# BEP33_6panel_DESKTOP-T8KKGMJ_Mai-19-0145.net
KiCad netlist of a schematic drawn in EAGLE
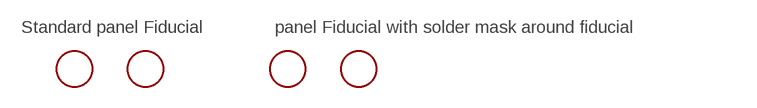
[diagram p0: schematic, sheet 1]
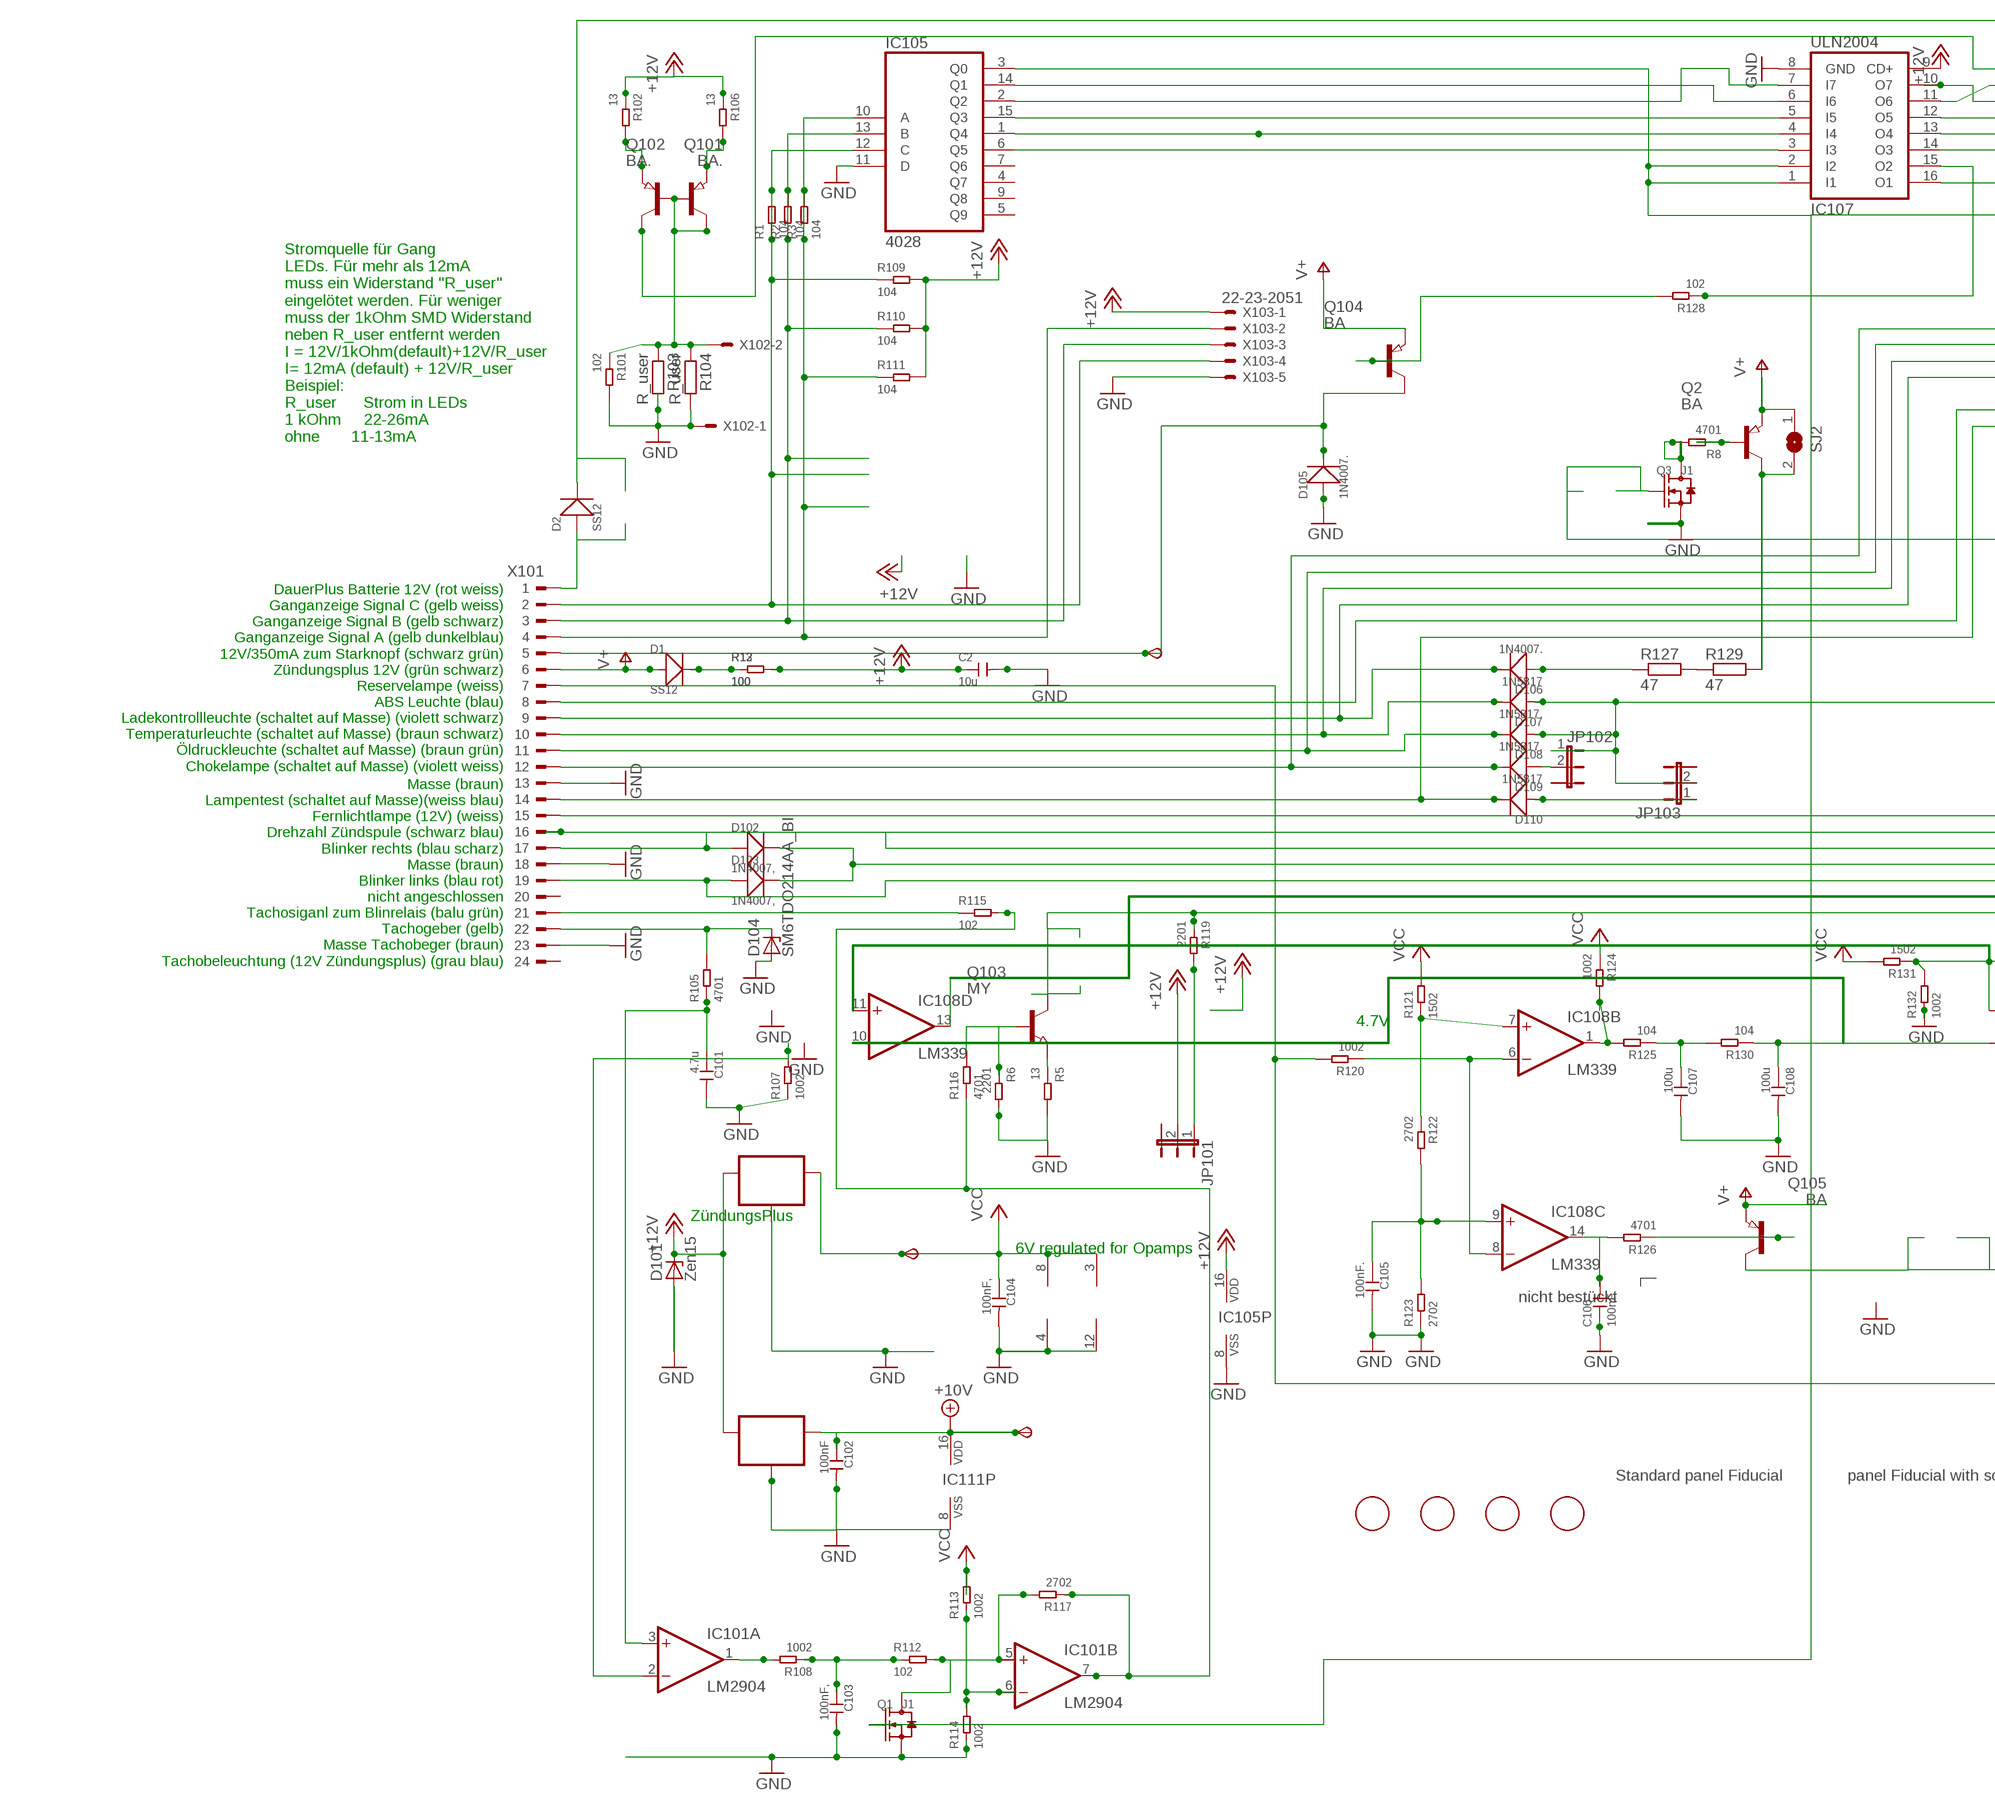
[diagram p1: schematic, sheet 2, part 1 of 2]
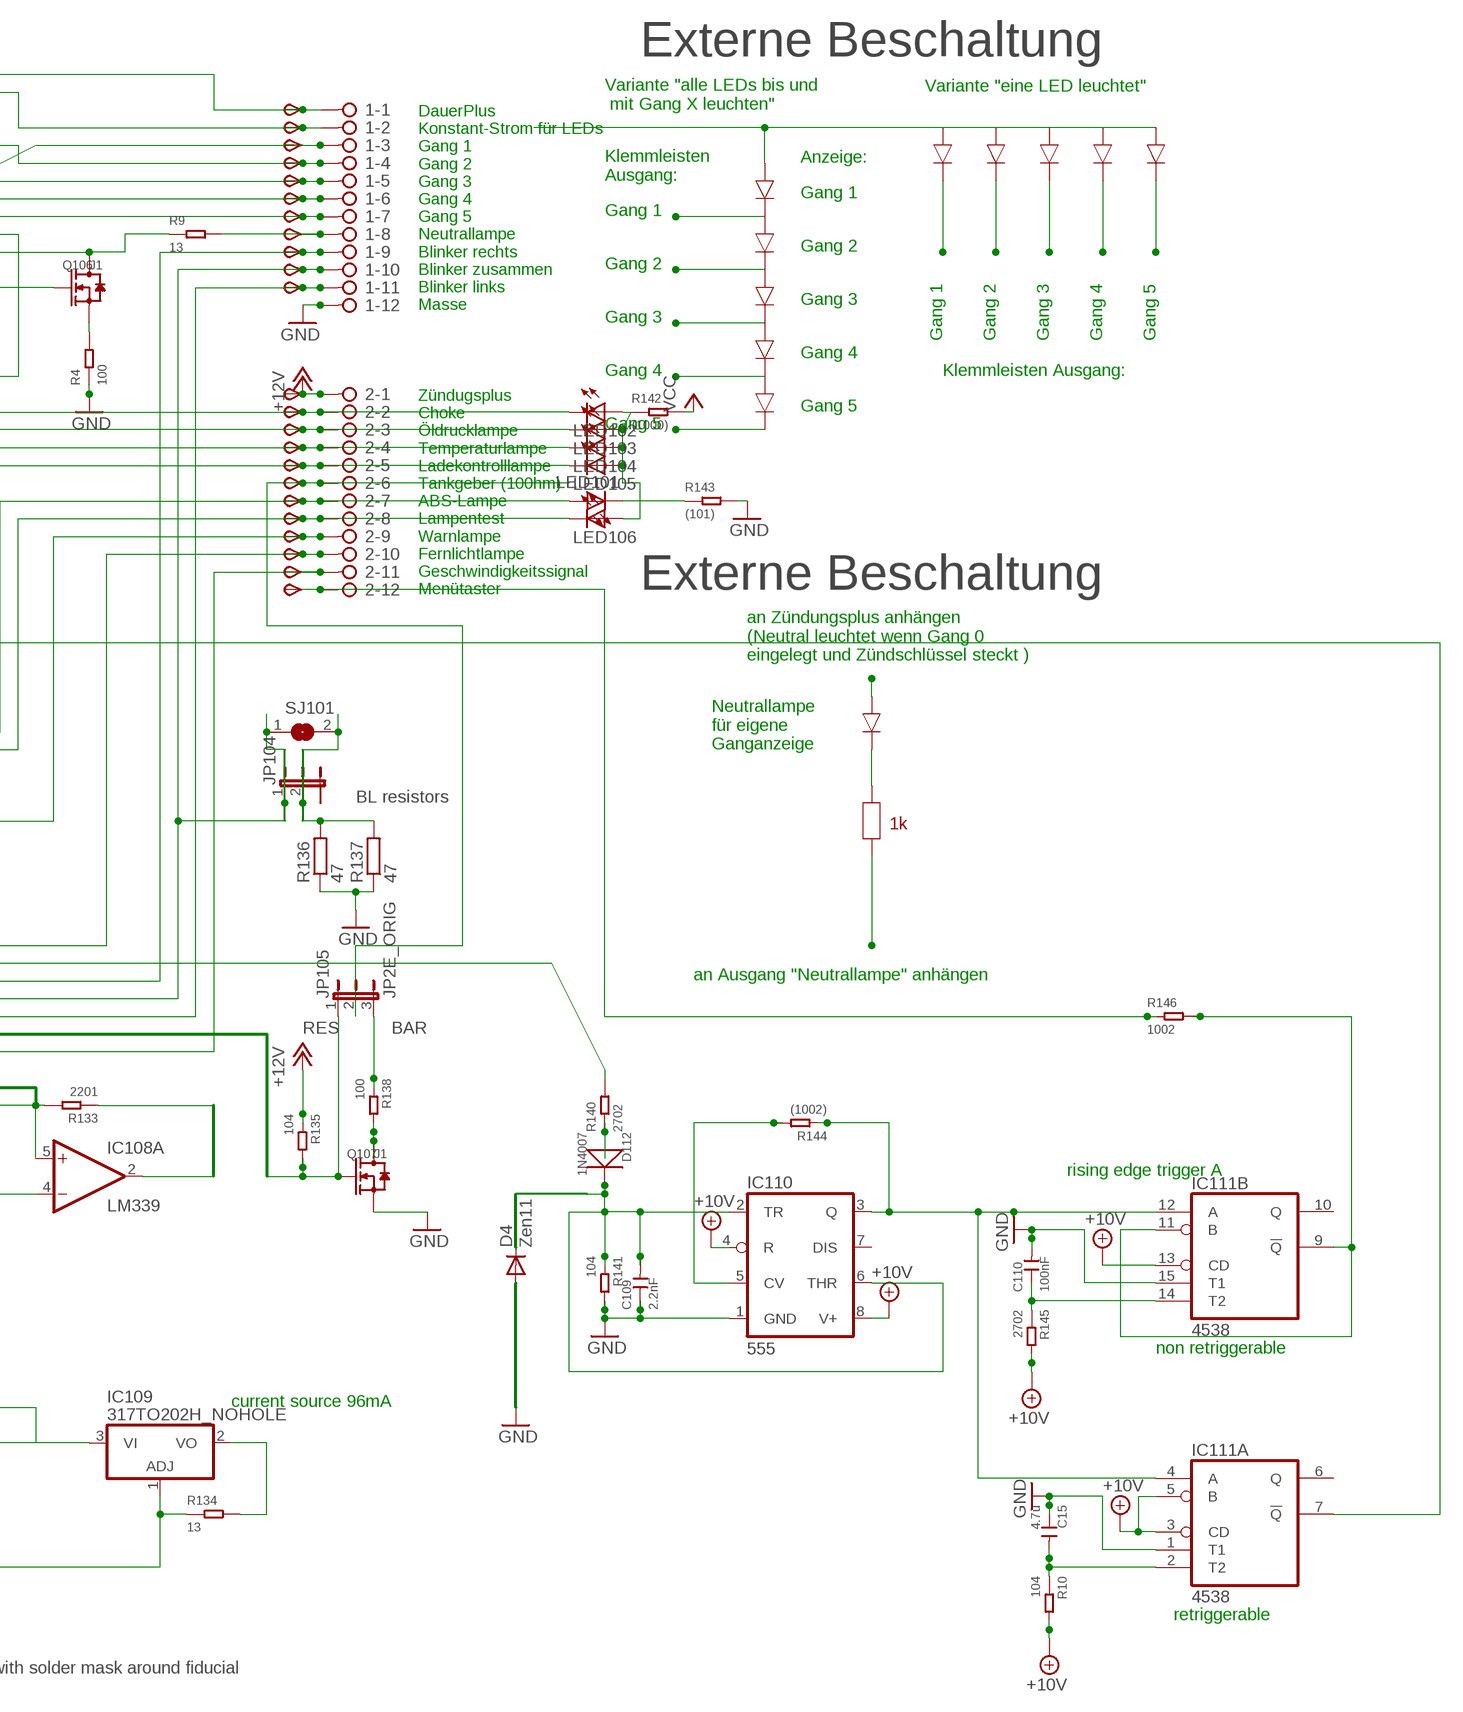
[diagram p2: schematic, sheet 2, part 2 of 2]
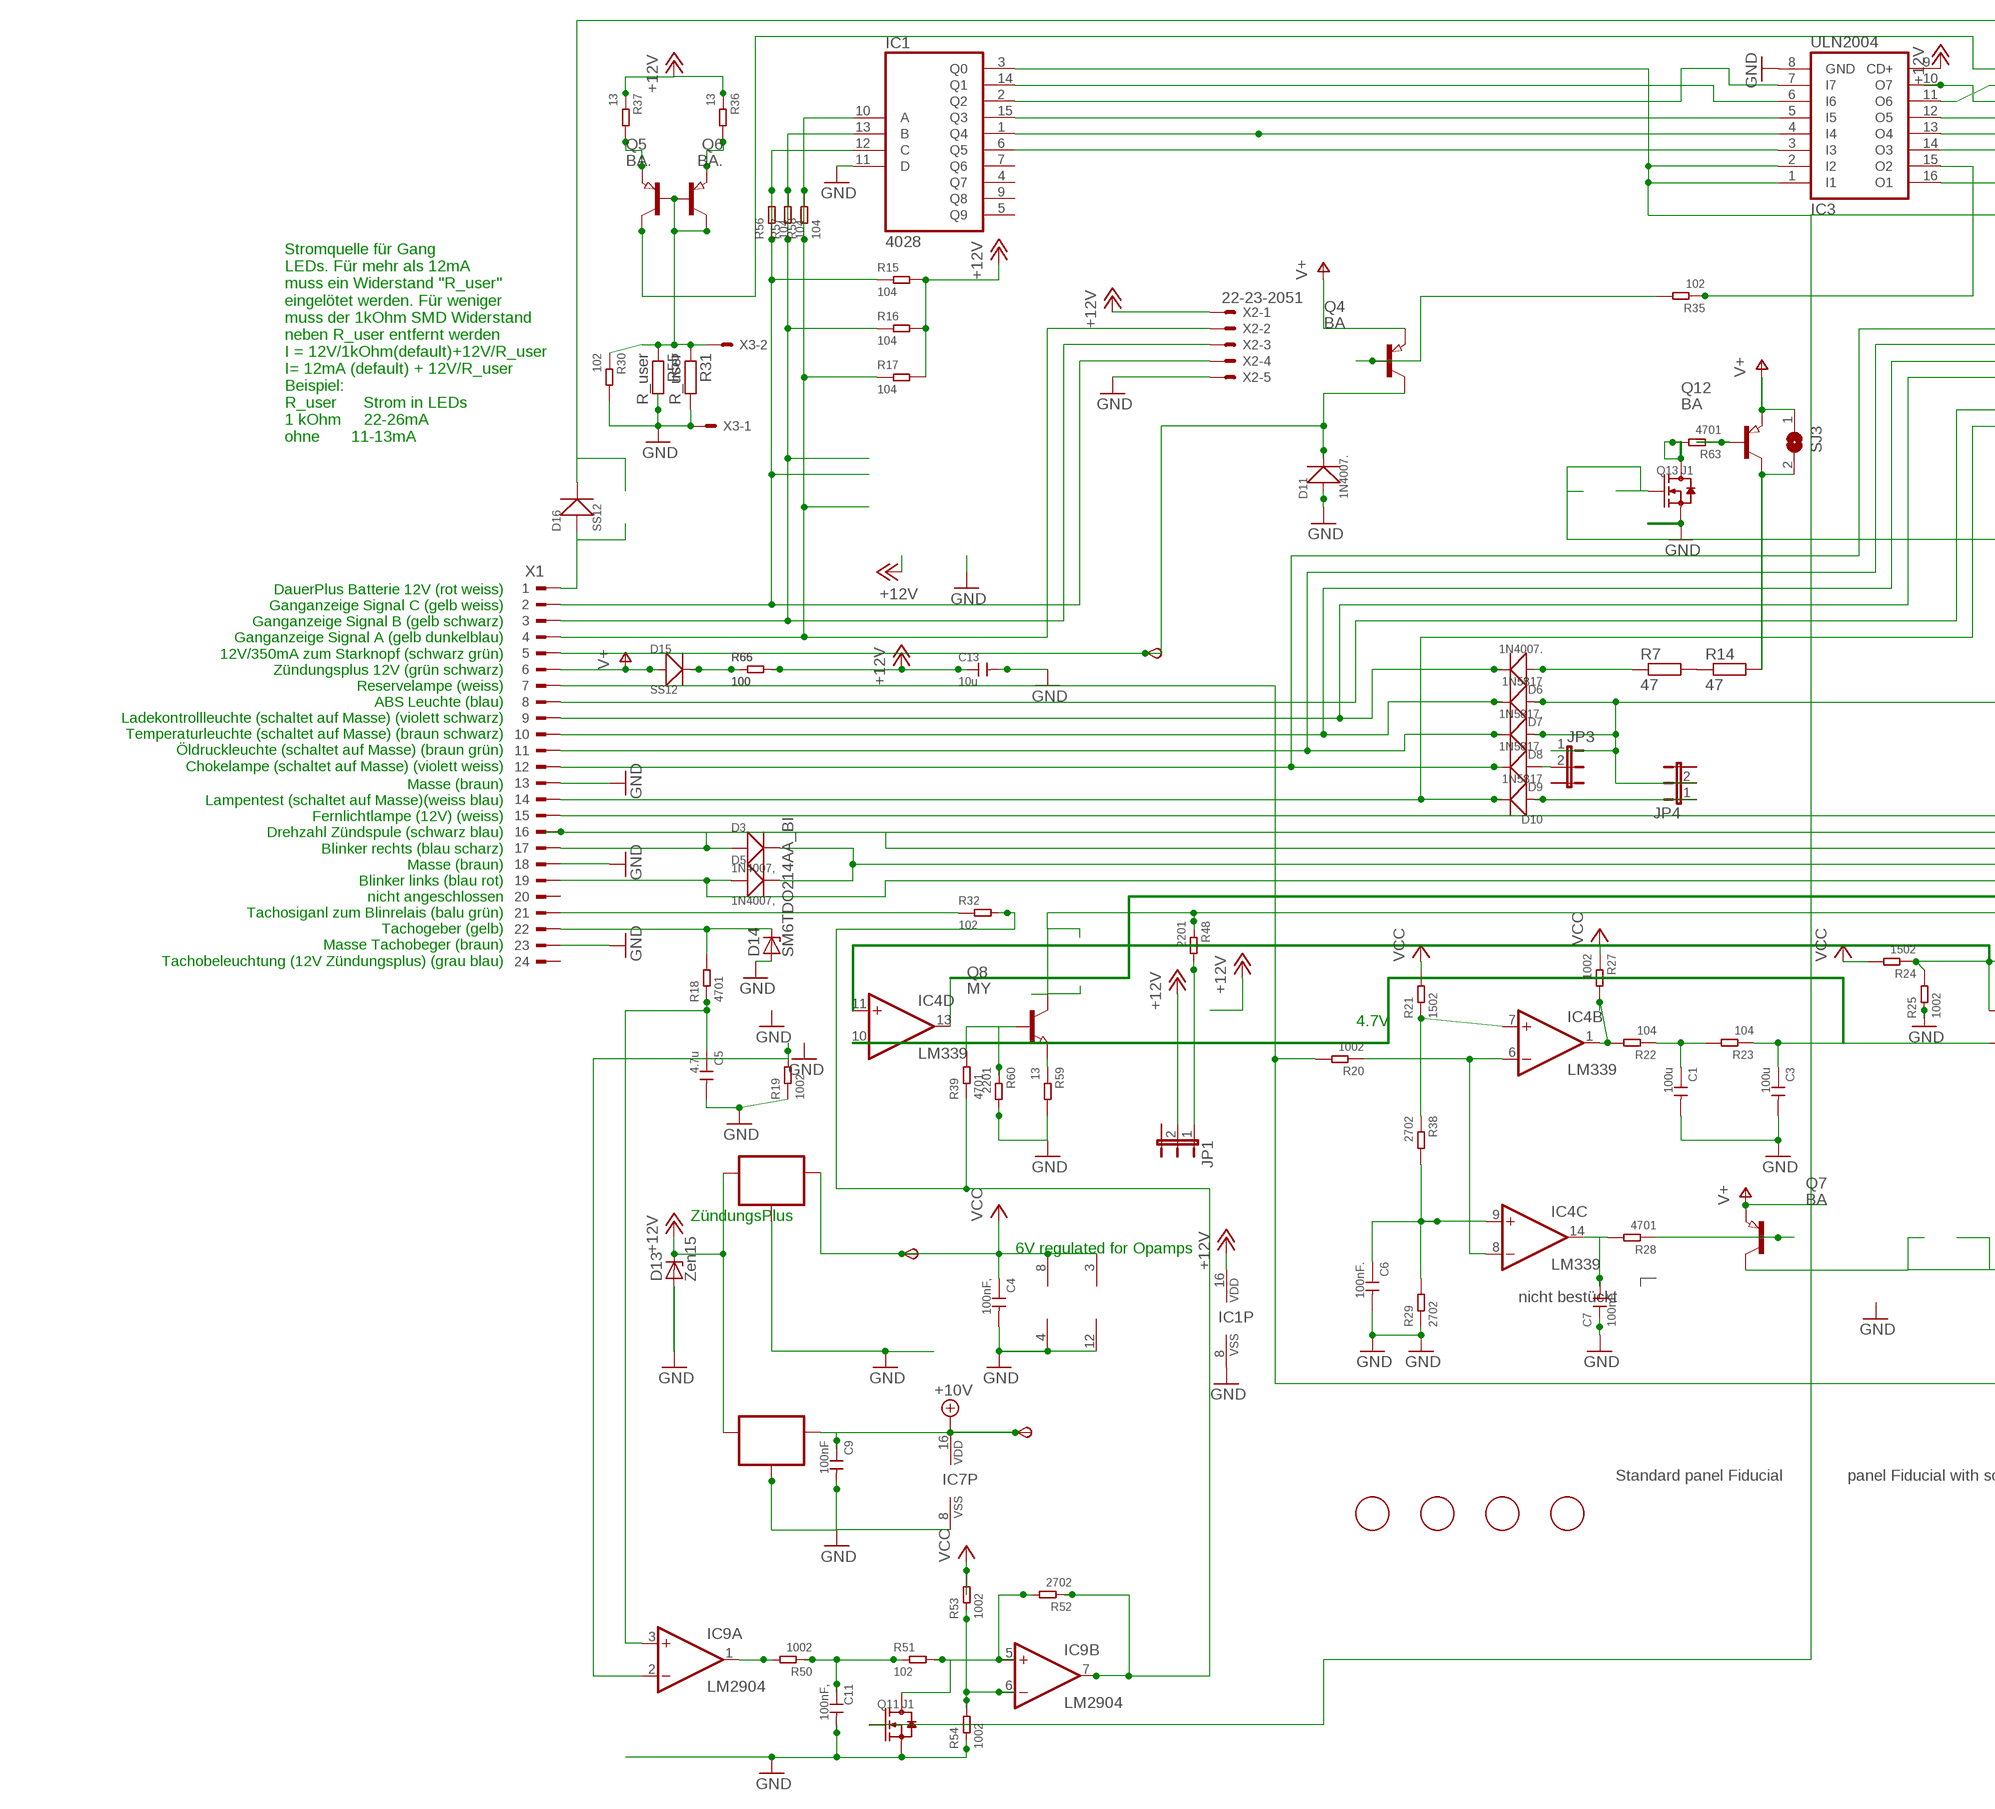
[diagram p3: schematic, sheet 3, part 1 of 2]
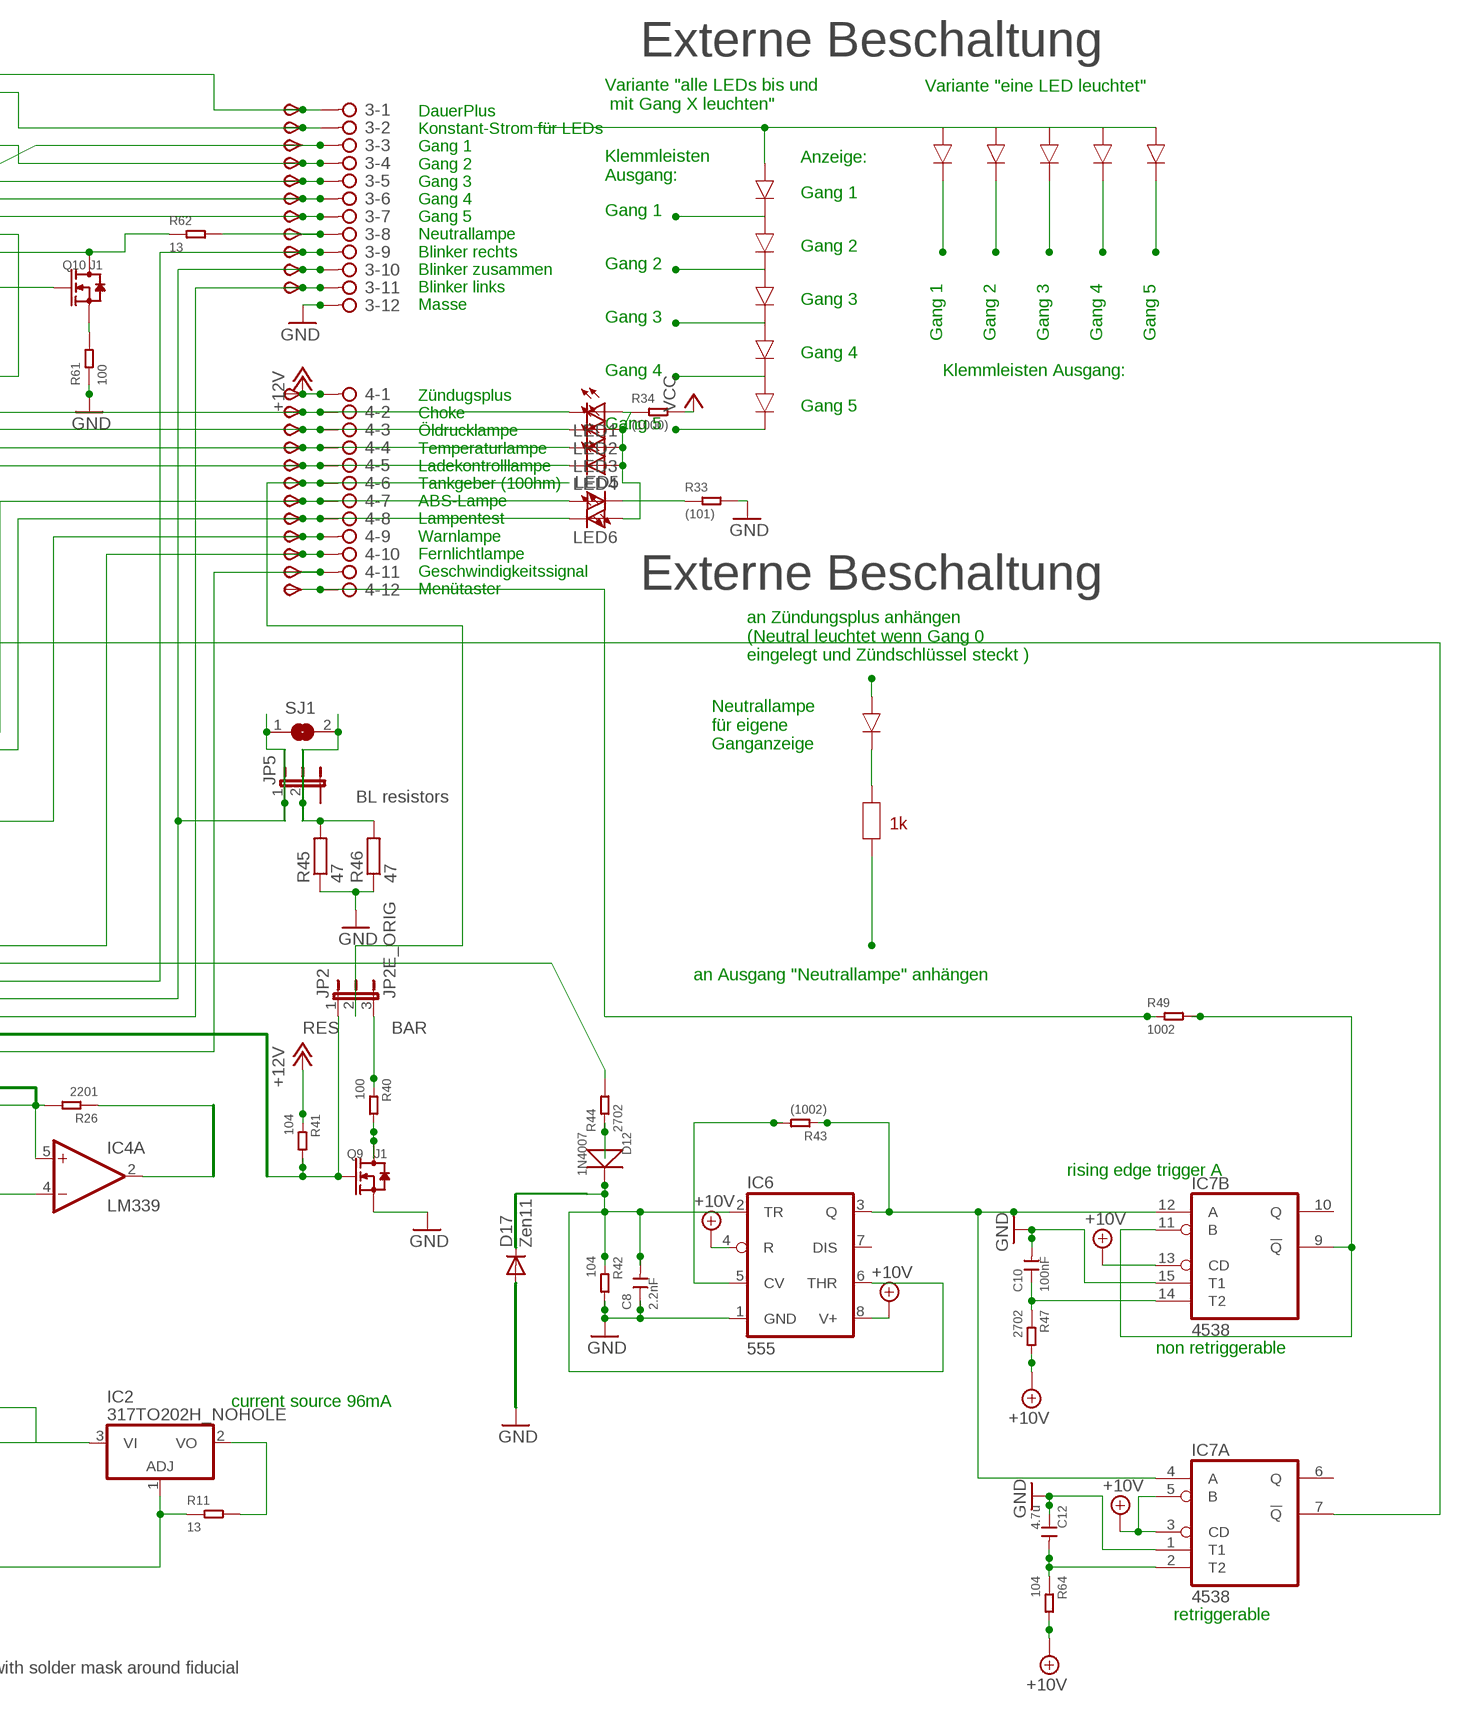
[diagram p4: schematic, sheet 3, part 2 of 2]
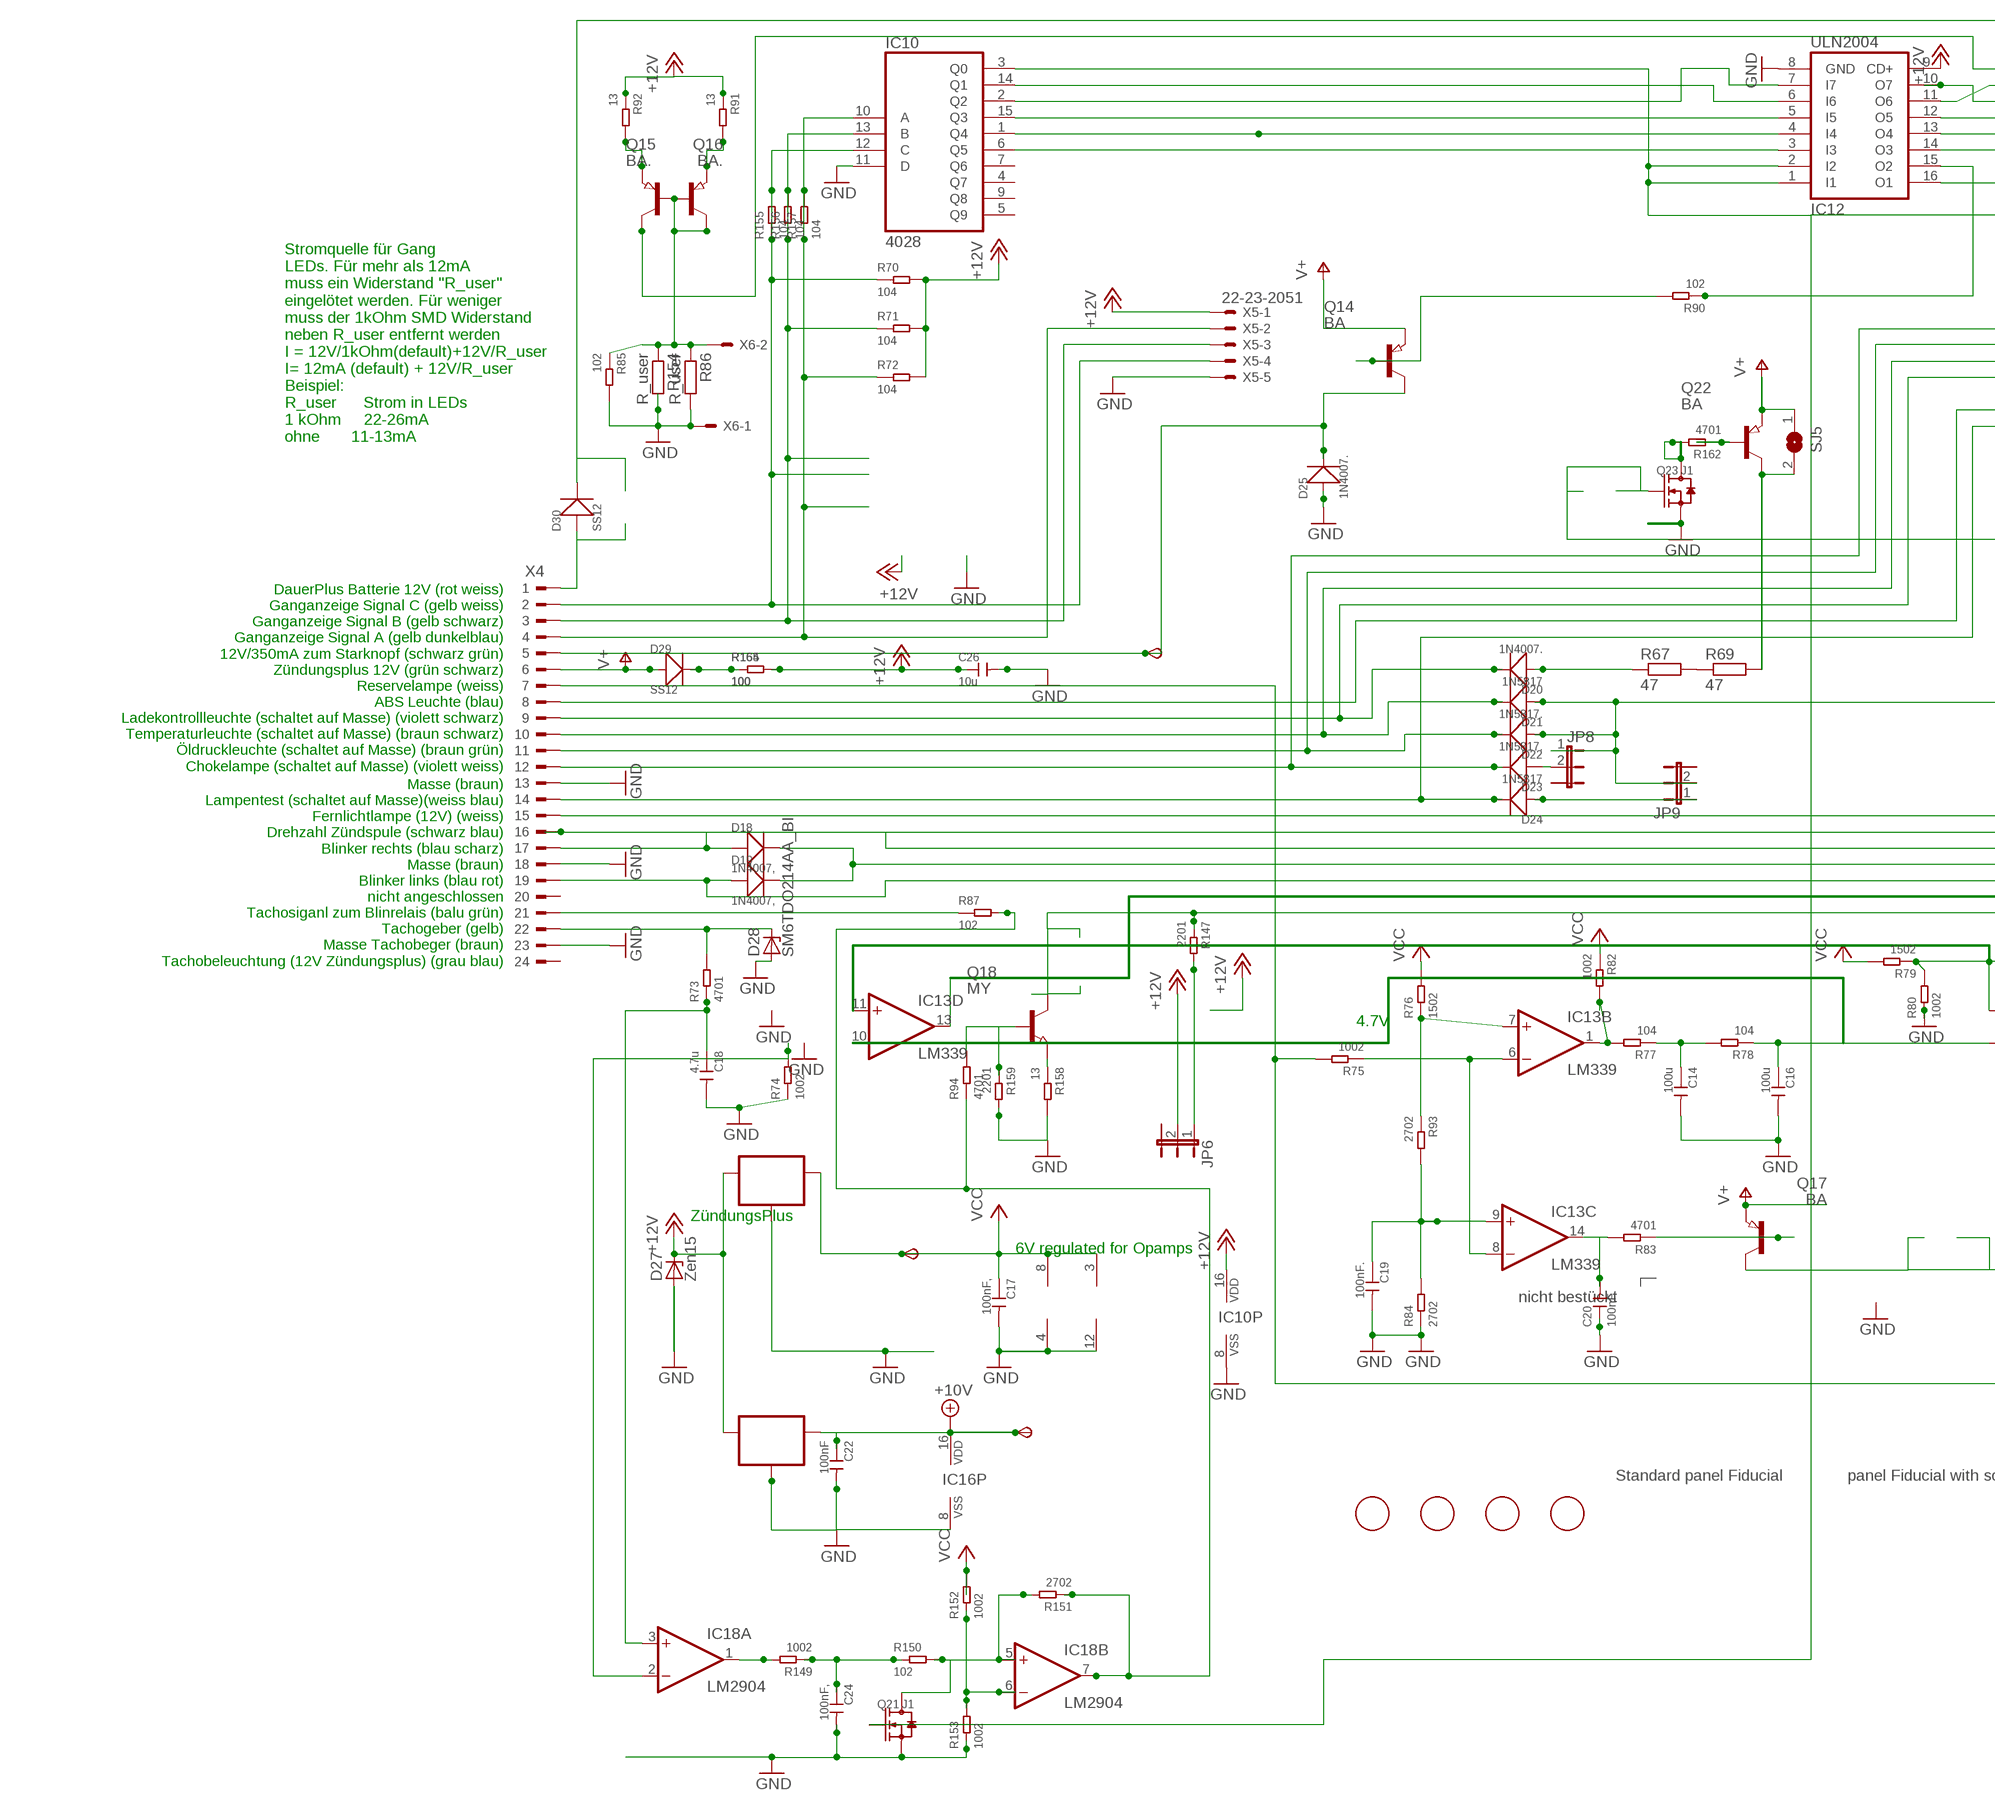
[diagram p5: schematic, sheet 4, part 1 of 2]
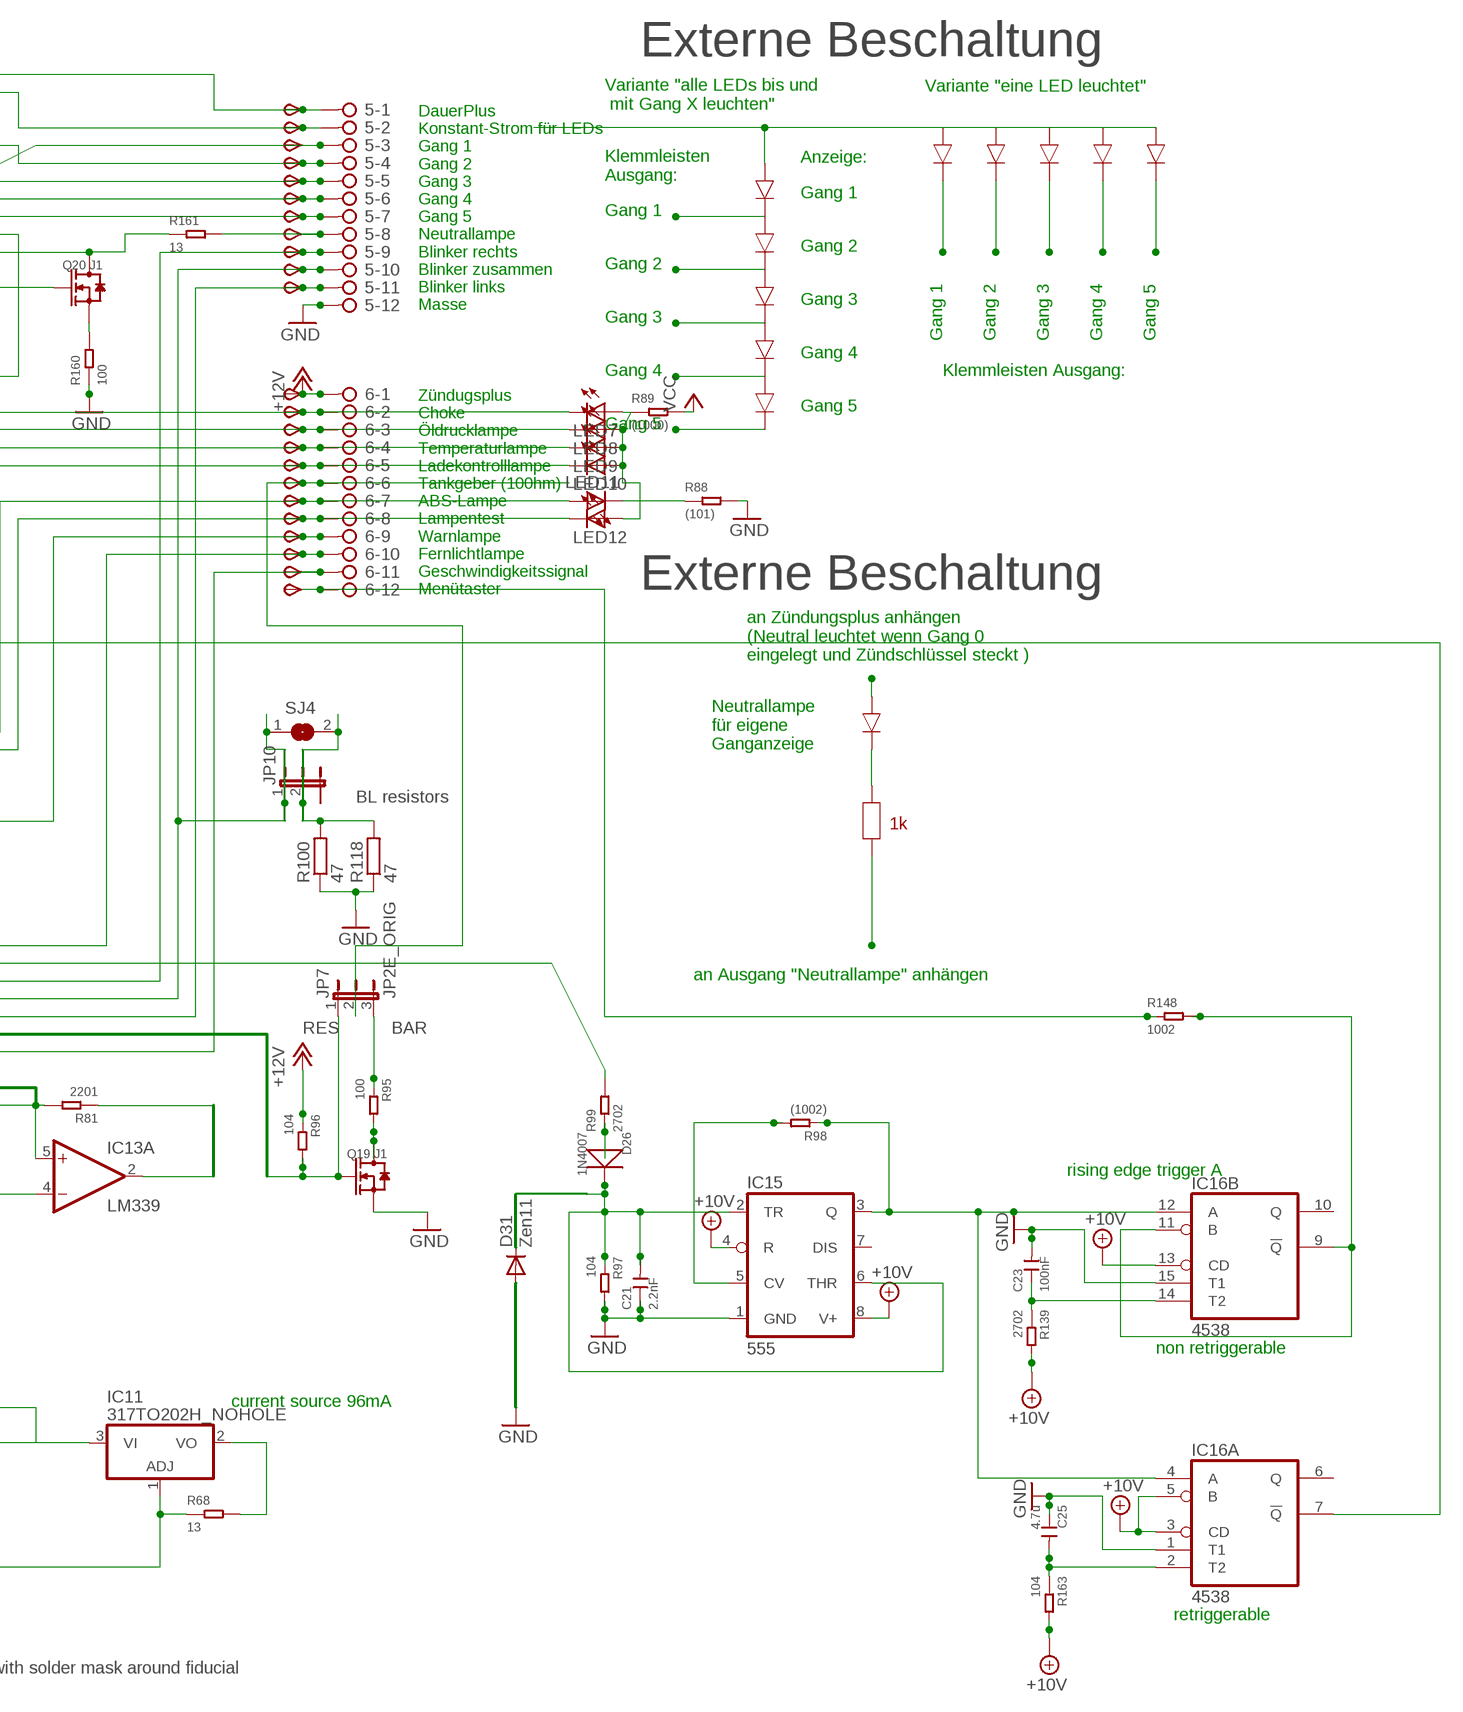
[diagram p6: schematic, sheet 4, part 2 of 2]
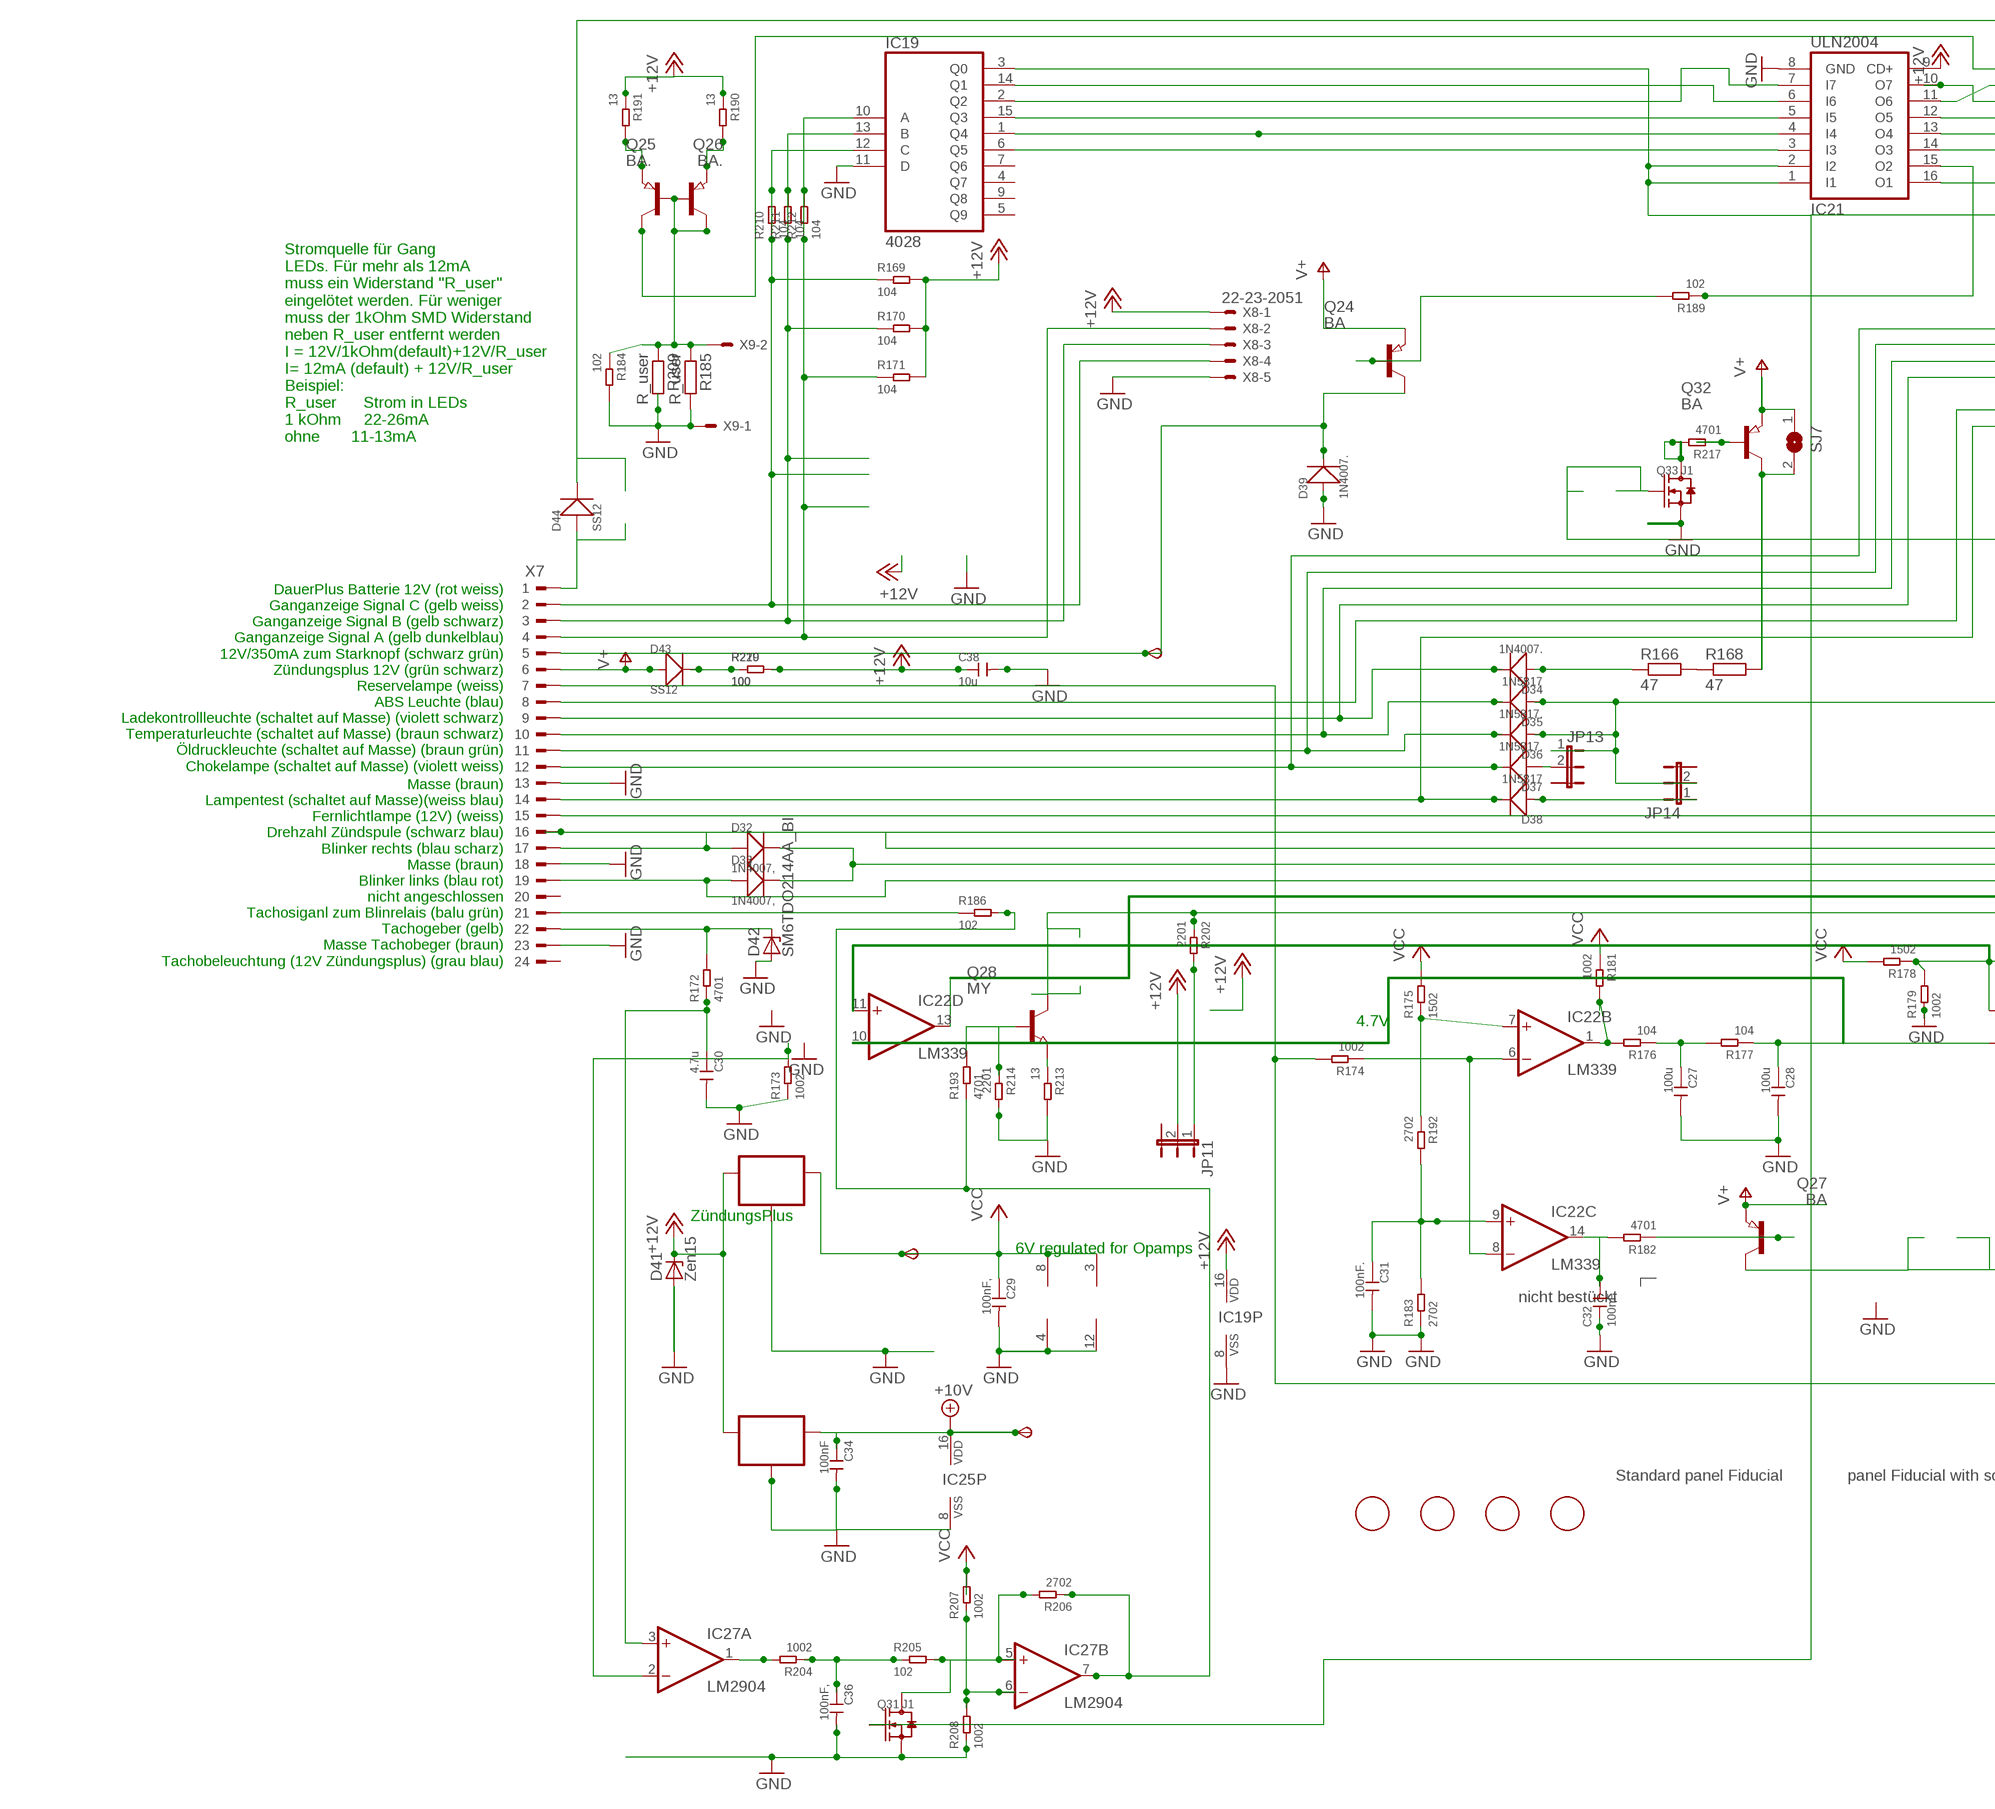
[diagram p7: schematic, sheet 5, part 1 of 2]
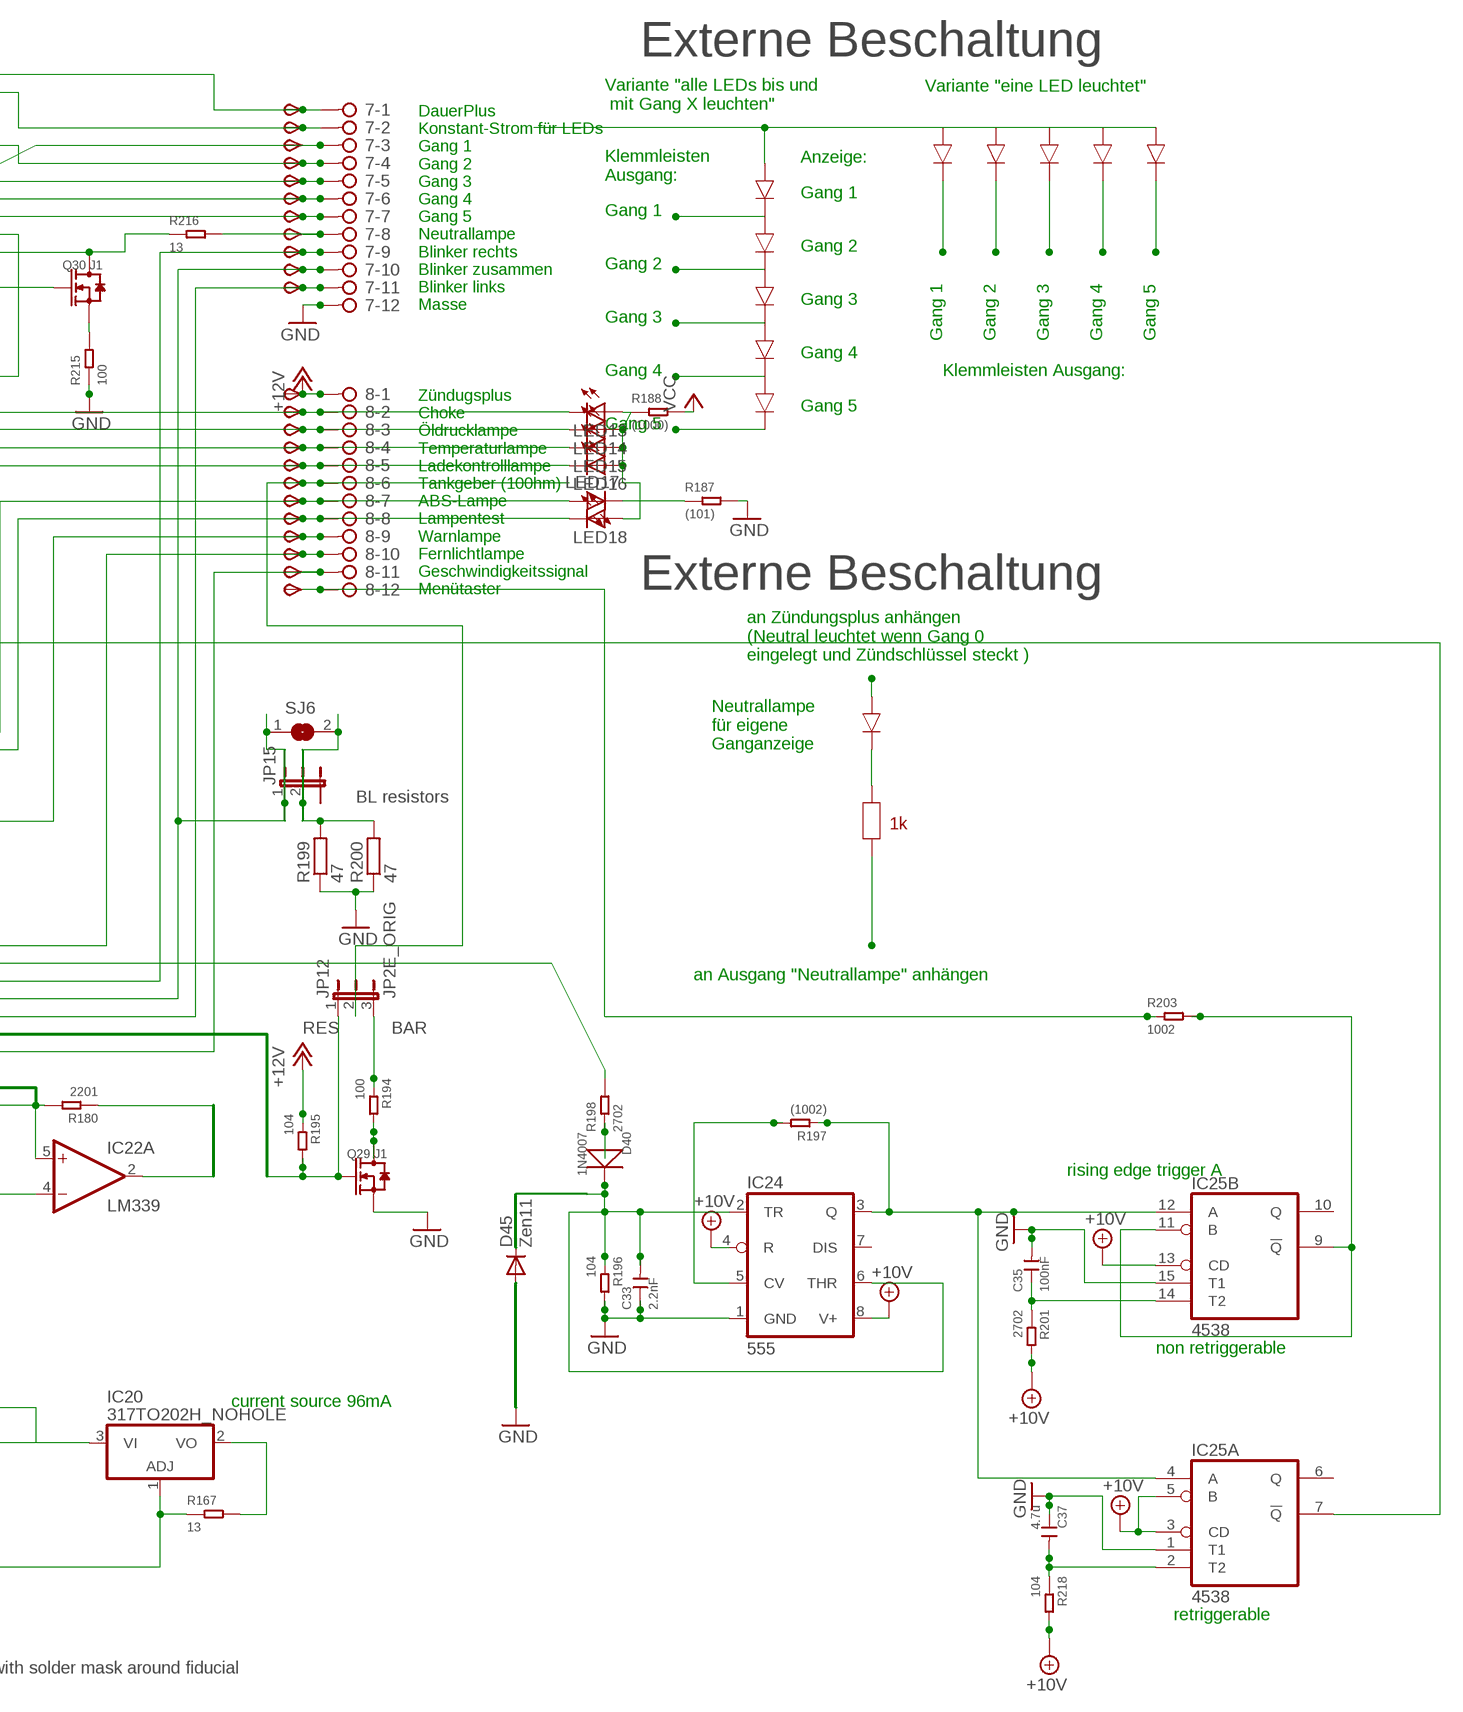
[diagram p8: schematic, sheet 5, part 2 of 2]
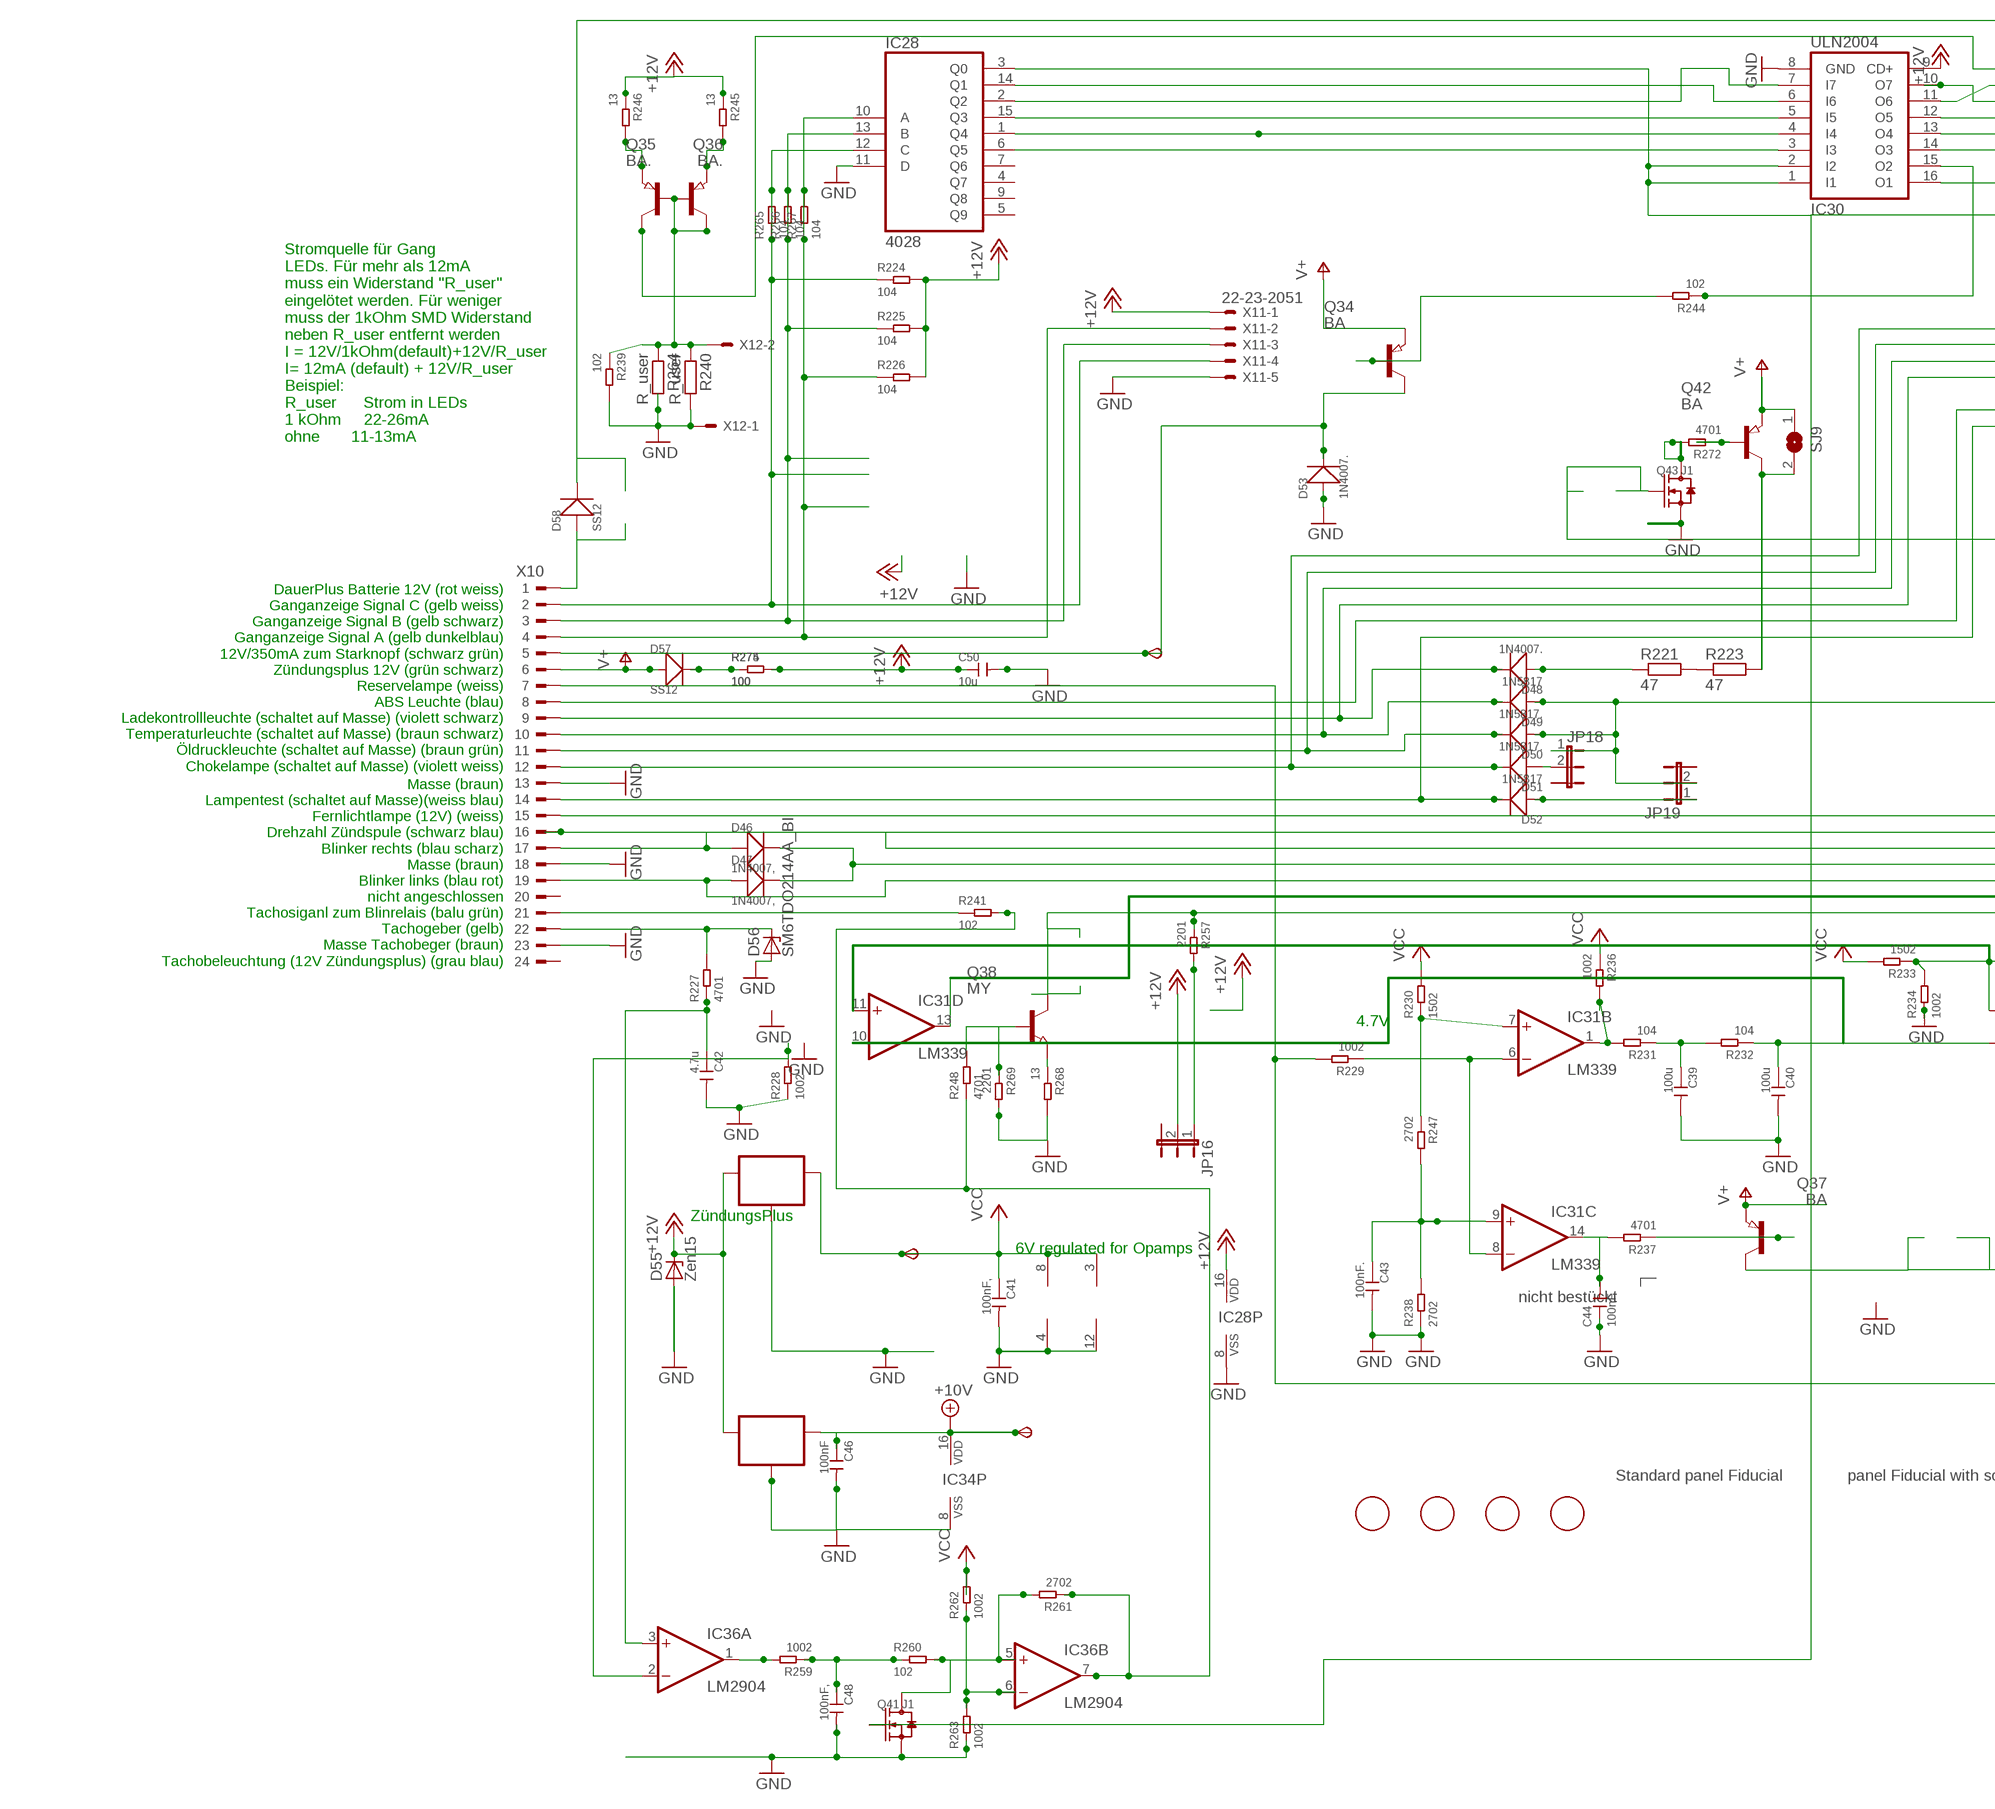
[diagram p9: schematic, sheet 6, part 1 of 2]
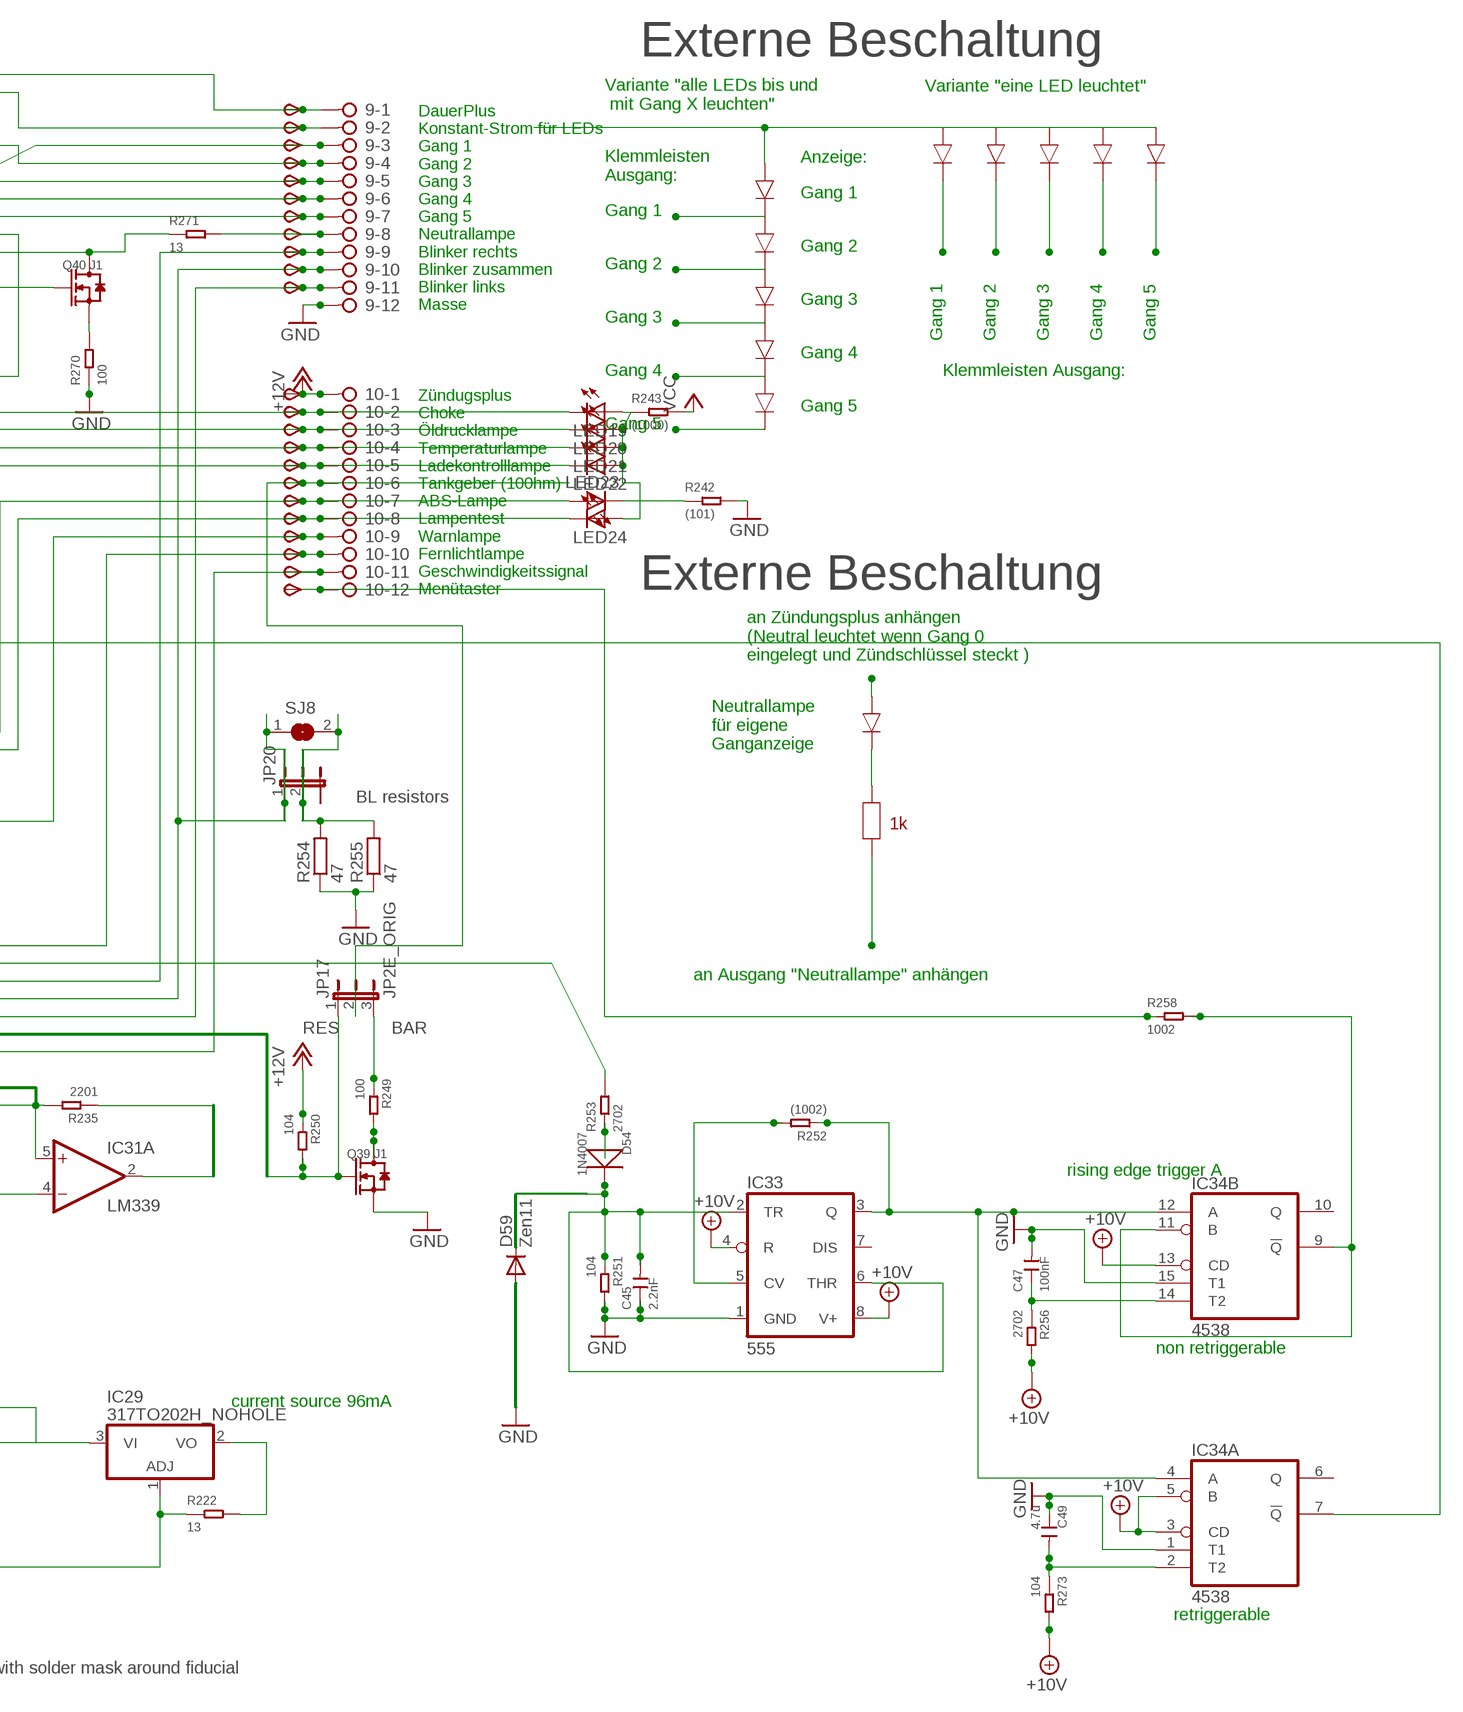
[diagram p10: schematic, sheet 6, part 2 of 2]
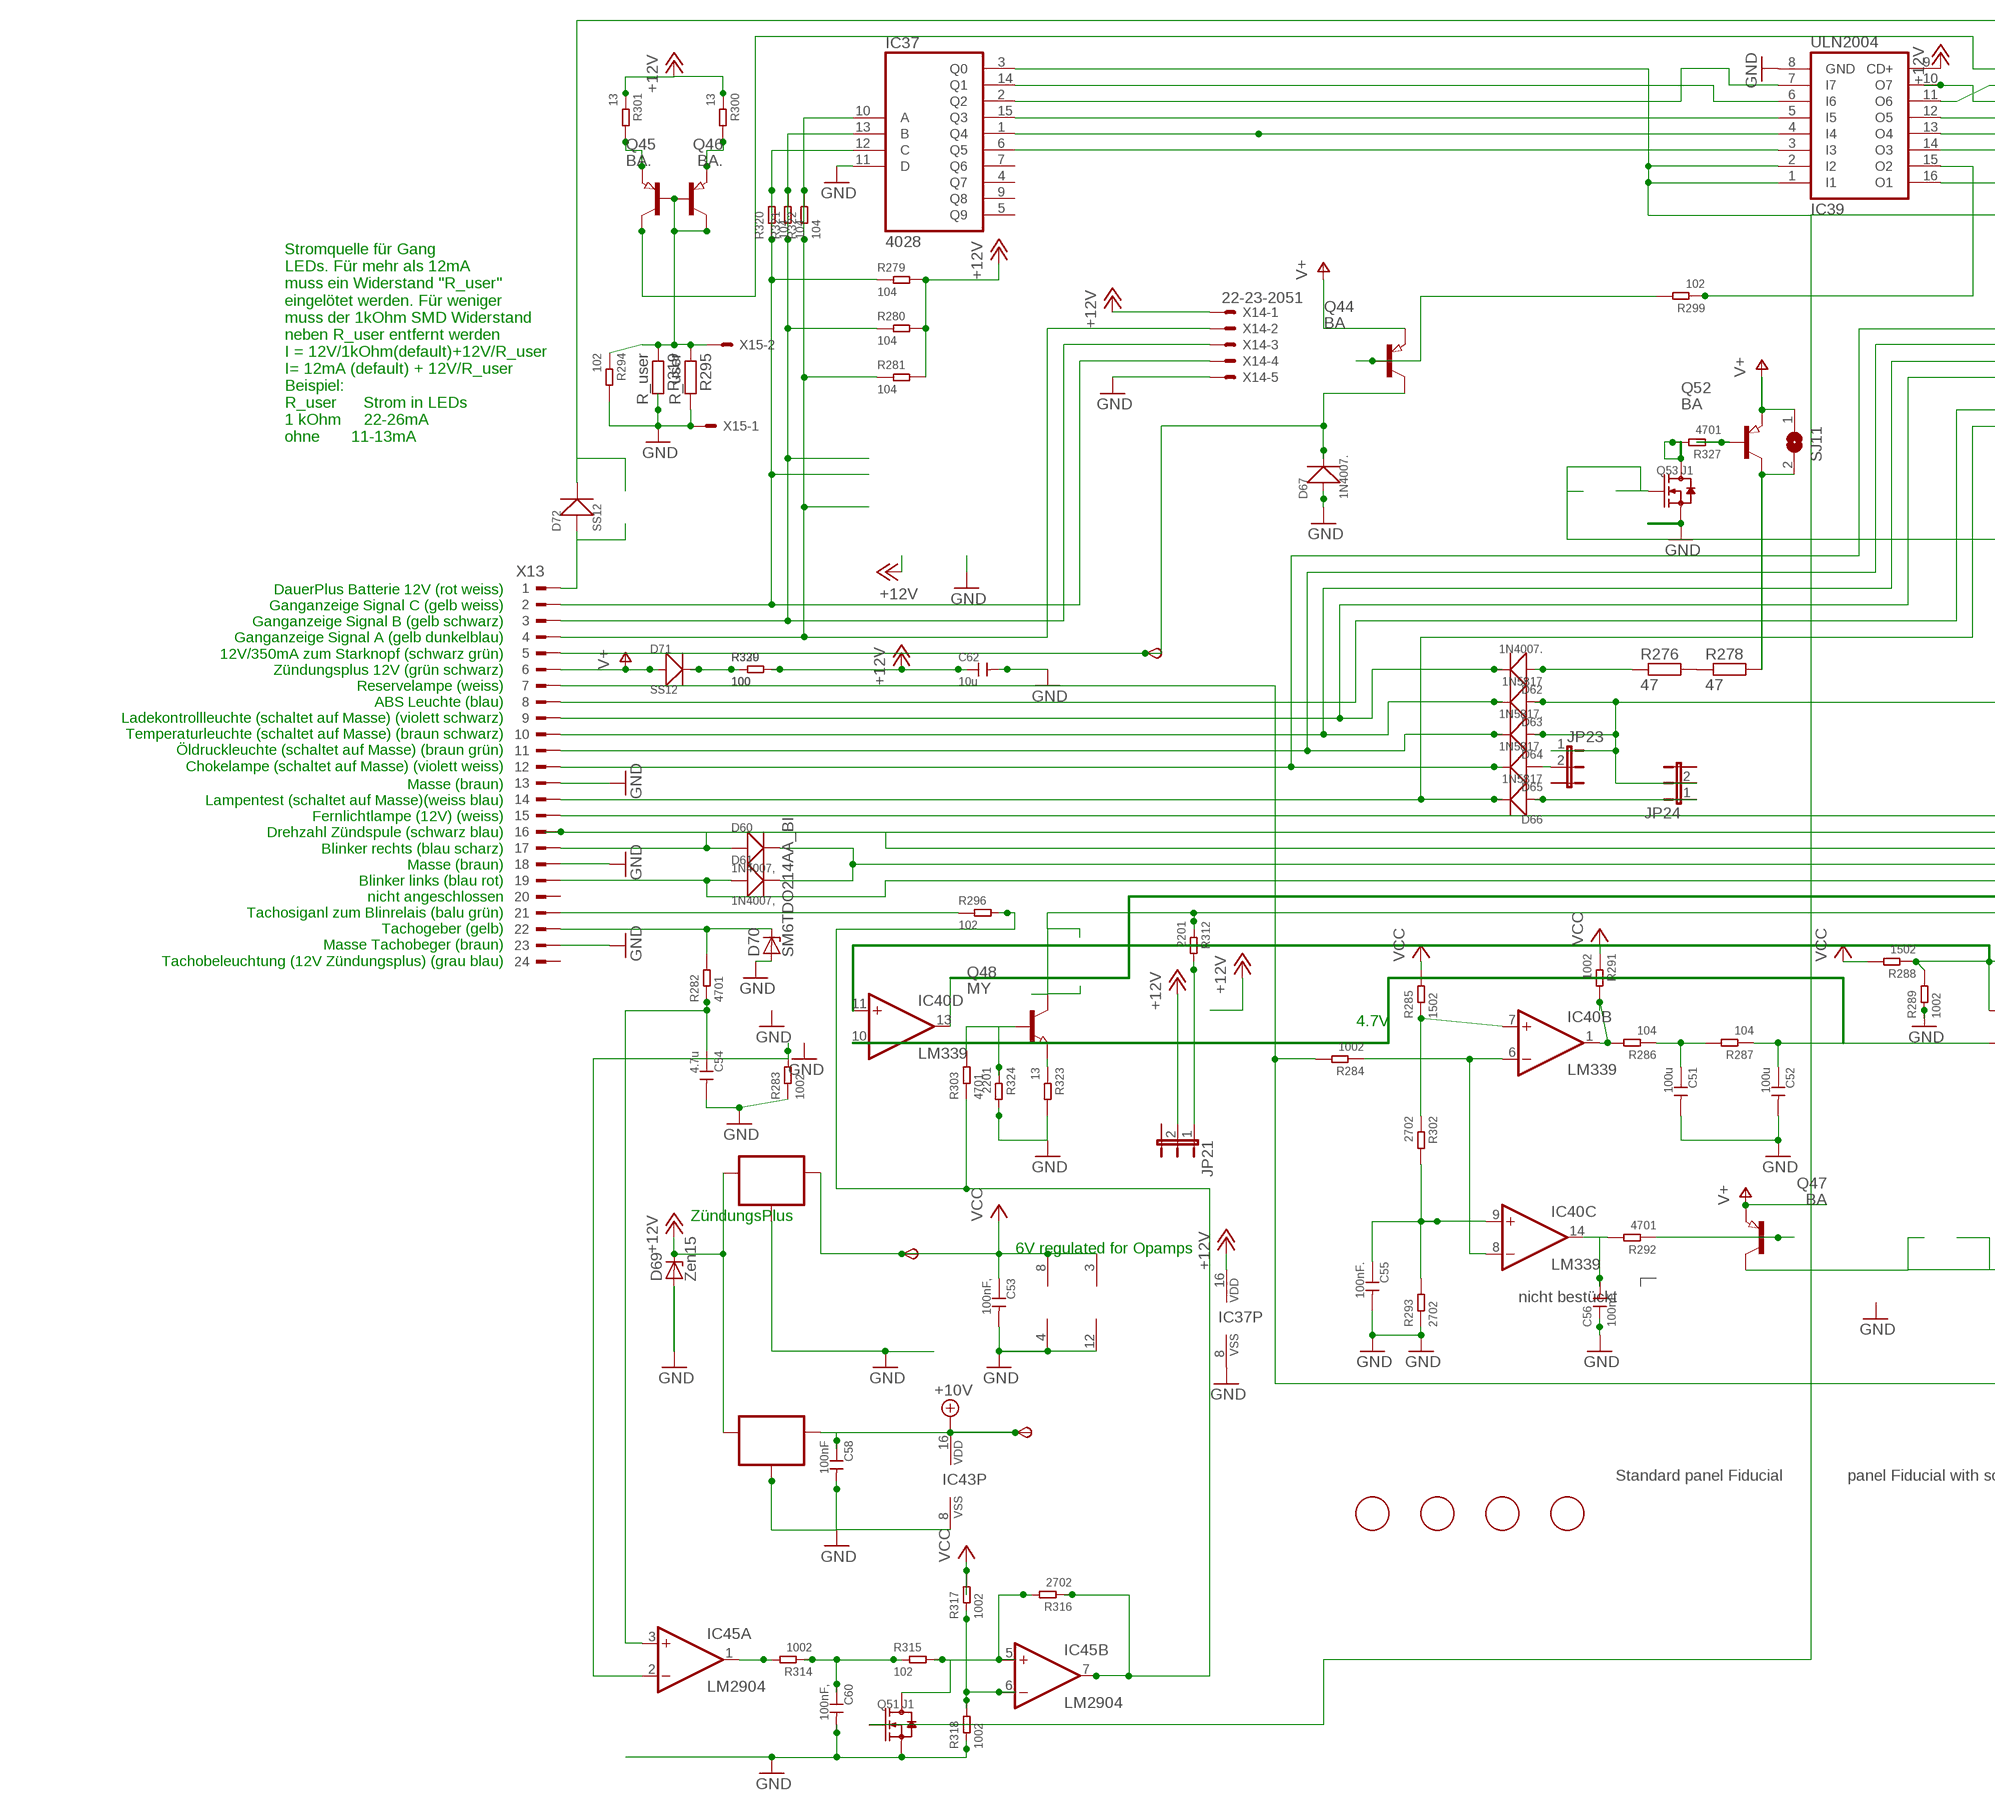
[diagram p11: schematic, sheet 7, part 1 of 2]
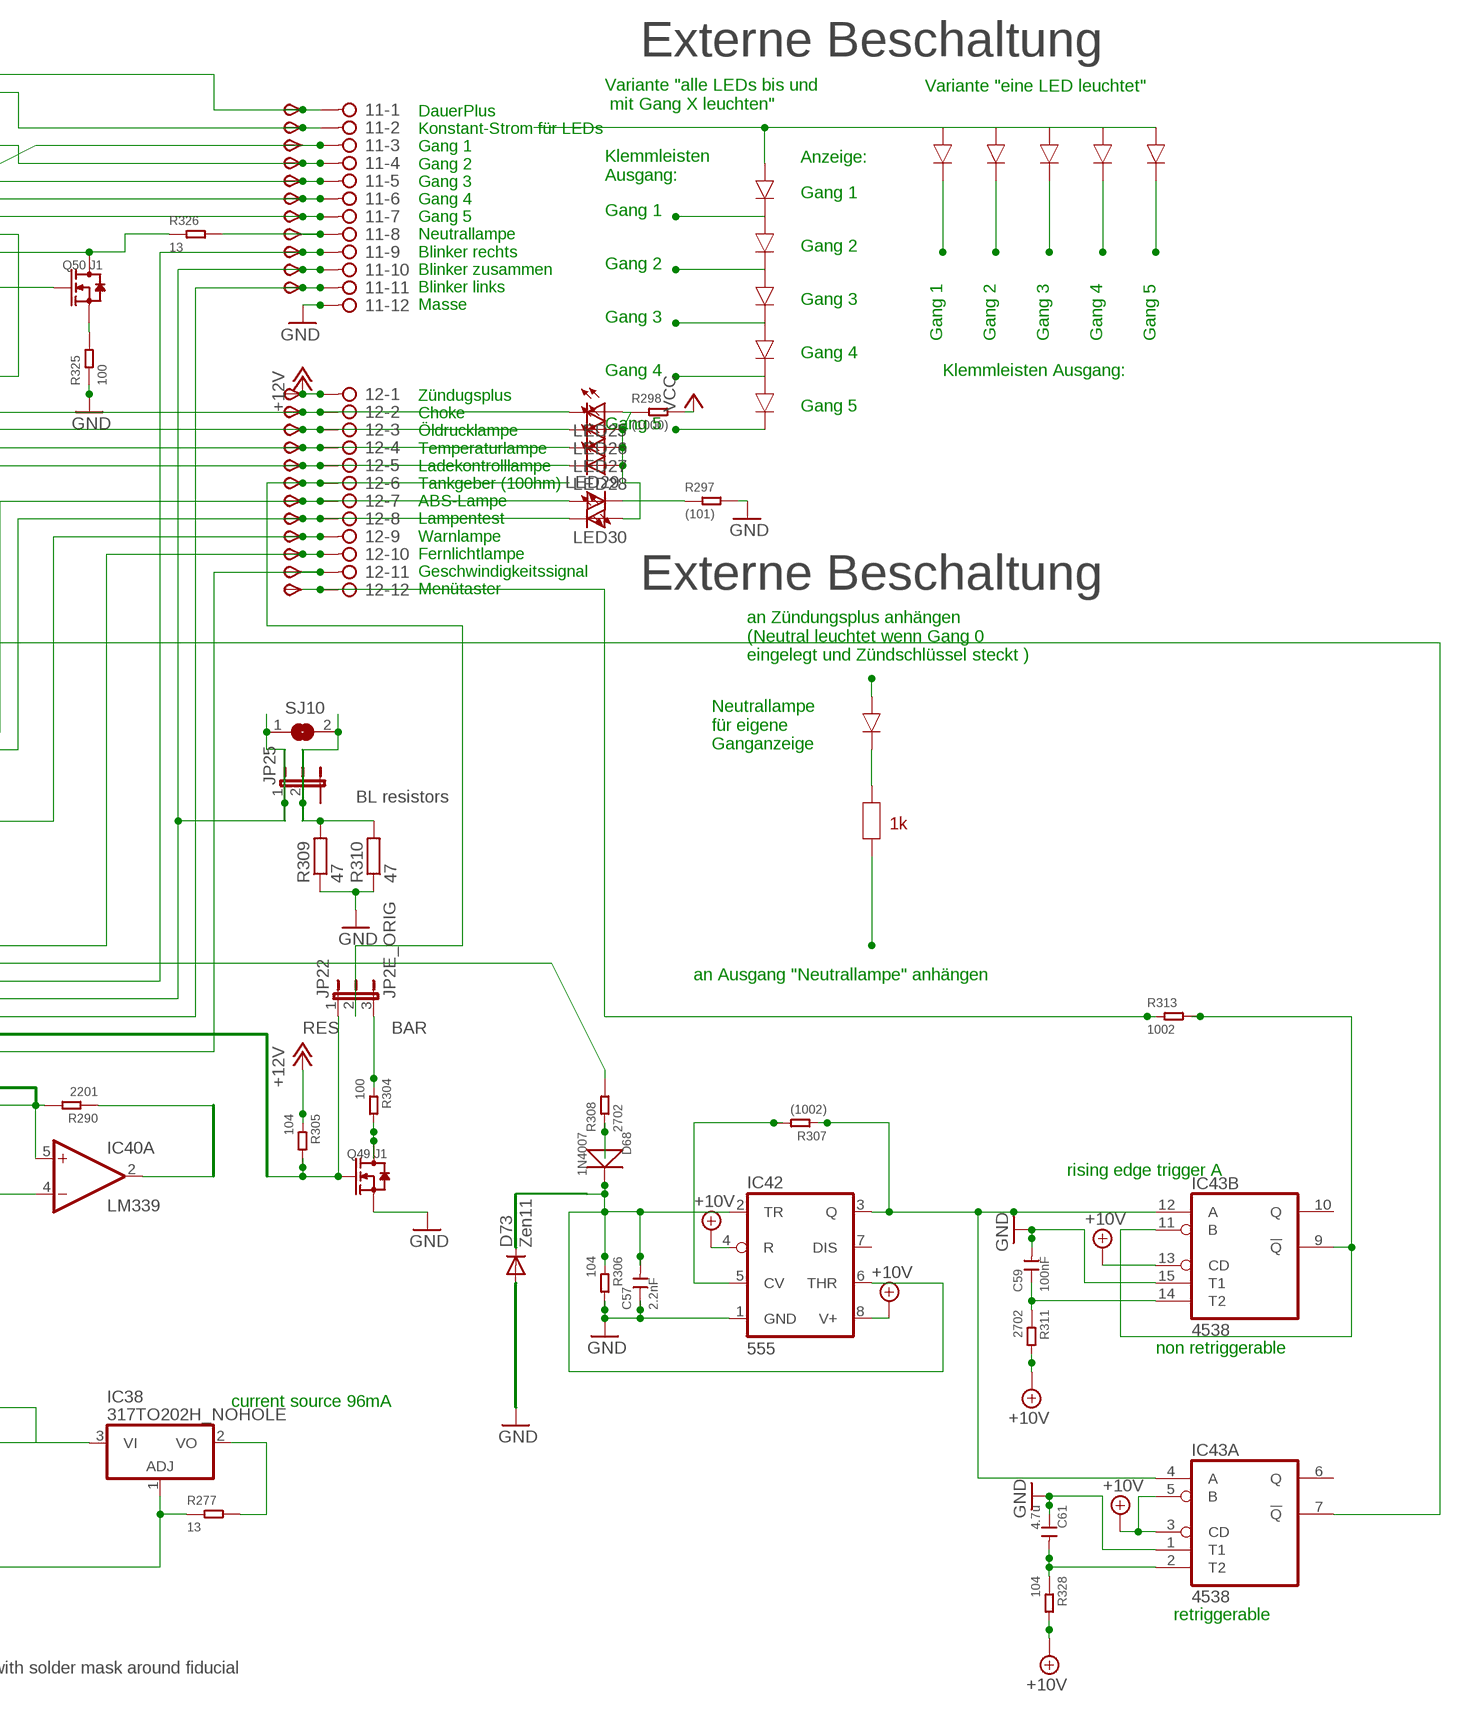
[diagram p12: schematic, sheet 7, part 2 of 2]

(export (version "E")
  (design (tool "Eeschema 10.0.6"))
  (components
    (comp (ref "3")
      (value "2081-1132")
      (footprint "eagle-import:12-PIN")
      (libsource (lib "eagle-import") (part "2081-1132"))
    )
    (comp (ref "4")
      (value "2081-1132")
      (footprint "eagle-import:12-PIN")
      (libsource (lib "eagle-import") (part "2081-1132"))
    )
    (comp (ref "6V1")
      (value "TPSB2.0")
      (footprint "eagle-import:B2.0")
      (libsource (lib "eagle-import") (part "TPSB2.0"))
    )
    (comp (ref "10V1")
      (value "TPSB2.0")
      (footprint "eagle-import:B2.0")
      (libsource (lib "eagle-import") (part "TPSB2.0"))
    )
    (comp (ref "C1")
      (value "100u")
      (footprint "eagle-import:C1206")
      (fields (field (name "MPN") "GRM31CR60J107ME39L"))
      (libsource (lib "eagle-import") (part "CERAMIC-100UF-6.3V-20%-X5R(1206)"))
    )
    (comp (ref "C3")
      (value "100u")
      (footprint "eagle-import:C1206")
      (fields (field (name "MPN") "GRM31CR60J107ME39L"))
      (libsource (lib "eagle-import") (part "CERAMIC-100UF-6.3V-20%-X5R(1206)"))
    )
    (comp (ref "C4")
      (value "100nF,")
      (footprint "eagle-import:C0805")
      (fields (field (name "MPN") "CC0805KRX7R9BB104"))
      (libsource (lib "eagle-import") (part "CERAMIC-100NF-50V-10%-X7R(0805)"))
    )
    (comp (ref "C5")
      (value "4.7u")
      (footprint "eagle-import:C0805")
      (fields (field (name "MPN") "CC0805KKX5R8BB475"))
      (libsource (lib "eagle-import") (part "CERAMIC-4.7UF-25V-10%-X5R(0805)"))
    )
    (comp (ref "C6")
      (value "100nF.")
      (footprint "eagle-import:C0805")
      (fields (field (name "MPN") "CC0805KRX7R9BB104"))
      (libsource (lib "eagle-import") (part "CERAMIC-100NF-50V-10%-X7R(0805)"))
    )
    (comp (ref "C7")
      (value "100nF.")
      (footprint "eagle-import:C0805")
      (fields (field (name "MPN") "CC0805KRX7R9BB104"))
      (libsource (lib "eagle-import") (part "CERAMIC-100NF-50V-10%-X7R(0805)"))
    )
    (comp (ref "C8")
      (value "2.2nF")
      (footprint "eagle-import:C0805")
      (fields (field (name "MPN") "CC0805KRX7R9BB104"))
      (libsource (lib "eagle-import") (part "CERAMIC-100NF-50V-10%-X7R(0805)"))
    )
    (comp (ref "C9")
      (value "100nF")
      (footprint "eagle-import:C0805")
      (fields (field (name "MPN") "CC0805KRX7R9BB104"))
      (libsource (lib "eagle-import") (part "CERAMIC-100NF-50V-10%-X7R(0805)"))
    )
    (comp (ref "C10")
      (value "100nF")
      (footprint "eagle-import:C0805")
      (fields (field (name "MPN") "CC0805KRX7R9BB104"))
      (libsource (lib "eagle-import") (part "CERAMIC-100NF-50V-10%-X7R(0805)"))
    )
    (comp (ref "C11")
      (value "100nF,")
      (footprint "eagle-import:C0805")
      (fields (field (name "MPN") "CC0805KRX7R9BB104"))
      (libsource (lib "eagle-import") (part "CERAMIC-100NF-50V-10%-X7R(0805)"))
    )
    (comp (ref "C12")
      (value "4.7u")
      (footprint "eagle-import:C0805")
      (fields (field (name "MPN") "CC0805KKX5R8BB475"))
      (libsource (lib "eagle-import") (part "CERAMIC-4.7UF-25V-10%-X5R(0805)"))
    )
    (comp (ref "C13")
      (value "10u")
      (footprint "eagle-import:C1206")
      (fields (field (name "MPN") "GRM31CR60J107ME39L"))
      (libsource (lib "eagle-import") (part "CERAMIC-100UF-6.3V-20%-X5R(1206)"))
    )
    (comp (ref "D3")
      (value "1N4007,")
      (footprint "eagle-import:DO-214AC")
      (fields (field (name "MPN") "1N4007"))
      (libsource (lib "eagle-import") (part "DIODE-GEN-PURPOSE-1KV-1A(DO-214AC)"))
    )
    (comp (ref "D5")
      (value "1N4007,")
      (footprint "eagle-import:DO-214AC")
      (fields (field (name "MPN") "1N4007"))
      (libsource (lib "eagle-import") (part "DIODE-GEN-PURPOSE-1KV-1A(DO-214AC)"))
    )
    (comp (ref "D6")
      (value "1N4007.")
      (footprint "eagle-import:DO-214AC")
      (fields (field (name "MPN") "1N4007"))
      (libsource (lib "eagle-import") (part "DIODE-GEN-PURPOSE-1KV-1A(DO-214AC)"))
    )
    (comp (ref "D7")
      (value "1N5817")
      (footprint "eagle-import:DO-214AC_SLIM")
      (libsource (lib "eagle-import") (part "DIODE-GEN-PURPOSE-1KV-1A(DO-214AC)DO-214AC/1206"))
    )
    (comp (ref "D8")
      (value "1N5817.")
      (footprint "eagle-import:DO-214AC_SLIM")
      (libsource (lib "eagle-import") (part "DIODE-GEN-PURPOSE-1KV-1A(DO-214AC)DO-214AC/1206"))
    )
    (comp (ref "D9")
      (value "1N5817.")
      (footprint "eagle-import:DO-214AC_SLIM")
      (libsource (lib "eagle-import") (part "DIODE-GEN-PURPOSE-1KV-1A(DO-214AC)DO-214AC/1206"))
    )
    (comp (ref "D10")
      (value "1N5817")
      (footprint "eagle-import:DO-214AC_SLIM")
      (libsource (lib "eagle-import") (part "DIODE-GEN-PURPOSE-1KV-1A(DO-214AC)DO-214AC/1206"))
    )
    (comp (ref "D11")
      (value "1N4007.")
      (footprint "eagle-import:DO-214AC")
      (fields (field (name "MPN") "1N4007"))
      (libsource (lib "eagle-import") (part "DIODE-GEN-PURPOSE-1KV-1A(DO-214AC)"))
    )
    (comp (ref "D12")
      (value "1N4007")
      (footprint "eagle-import:DO-214AC")
      (libsource (lib "eagle-import") (part "DIODE-GEN-PURPOSE-1KV-1A(DO-214AC)"))
    )
    (comp (ref "D13")
      (value "Zen15")
      (footprint "eagle-import:DO214AA")
      (libsource (lib "eagle-import") (part "SM6T"))
    )
    (comp (ref "D14")
      (value "SM6TDO214AA_BI")
      (footprint "eagle-import:DO214AA_BI")
      (libsource (lib "eagle-import") (part "SM6TDO214AA_BI"))
    )
    (comp (ref "D15")
      (value "SS12")
      (footprint "eagle-import:DO-214AC_SLIM")
      (libsource (lib "eagle-import") (part "DIODE-GEN-PURPOSE-1KV-1A(DO-214AC)DO-214AC/1206"))
    )
    (comp (ref "D16")
      (value "SS12")
      (footprint "eagle-import:DO-214AC_SLIM")
      (libsource (lib "eagle-import") (part "DIODE-GEN-PURPOSE-1KV-1A(DO-214AC)DO-214AC/1206"))
    )
    (comp (ref "D17")
      (value "Zen11")
      (footprint "eagle-import:SOD-123_MINI-SMA")
      (libsource (lib "eagle-import") (part "CGRM400-G1"))
    )
    (comp (ref "FID3")
      (value "FIDUCIAL")
      (footprint "eagle-import:FIDUCIAL_1MM")
      (libsource (lib "eagle-import") (part "FIDUCIAL"))
    )
    (comp (ref "FID4")
      (value "FIDUCIAL")
      (footprint "eagle-import:FIDUCIAL_1MM")
      (libsource (lib "eagle-import") (part "FIDUCIAL"))
    )
    (comp (ref "FID5")
      (value "FIDUCIAL")
      (footprint "eagle-import:FIDUCIAL_1MM")
      (libsource (lib "eagle-import") (part "FIDUCIAL"))
    )
    (comp (ref "FID6")
      (value "FIDUCIAL")
      (footprint "eagle-import:FIDUCIAL_1MM")
      (libsource (lib "eagle-import") (part "FIDUCIAL"))
    )
    (comp (ref "IC1")
      (value "4028")
      (footprint "eagle-import:SO16")
      (libsource (lib "eagle-import") (part "4028D"))
    )
    (comp (ref "IC2")
      (value "317TO202H_NOHOLE")
      (footprint "eagle-import:TO220H_NOHOLE")
      (libsource (lib "eagle-import") (part "317TO202H_NOHOLE"))
    )
    (comp (ref "IC3")
      (value "ULN2004")
      (footprint "eagle-import:SO16")
      (libsource (lib "eagle-import") (part "ULN2004AD"))
    )
    (comp (ref "IC4")
      (value "LM339")
      (footprint "eagle-import:SO14")
      (libsource (lib "eagle-import") (part "LM339D"))
    )
    (comp (ref "IC5")
      (value "78L06")
      (footprint "eagle-import:SOT89_ROUND")
      (libsource (lib "eagle-import") (part "78LXXSOT89_ROUND"))
    )
    (comp (ref "IC6")
      (value "555")
      (footprint "eagle-import:SO08")
      (libsource (lib "eagle-import") (part "555DNE"))
    )
    (comp (ref "IC7")
      (value "4538")
      (footprint "eagle-import:SO16")
      (libsource (lib "eagle-import") (part "4538D"))
    )
    (comp (ref "IC8")
      (value "78L10")
      (footprint "eagle-import:SOT89_ROUND")
      (libsource (lib "eagle-import") (part "78LXXSOT89_ROUND"))
    )
    (comp (ref "IC9")
      (value "LM2904")
      (footprint "eagle-import:SO08")
      (libsource (lib "eagle-import") (part "LM358D"))
    )
    (comp (ref "JP1")
      (value "JP2EJP2_SMALLPADS")
      (footprint "eagle-import:JP2_SMALLPADS")
      (libsource (lib "eagle-import") (part "JP2EJP2_SMALLPADS"))
    )
    (comp (ref "JP2")
      (value "JP2E_ORIG")
      (footprint "eagle-import:JP2_ORIG_SMALLPADS")
      (libsource (lib "eagle-import") (part "JP2E_ORIG"))
    )
    (comp (ref "JP3")
      (value "JP2EJP2_SMALLPADS")
      (footprint "eagle-import:JP2_SMALLPADS")
      (libsource (lib "eagle-import") (part "JP2EJP2_SMALLPADS"))
    )
    (comp (ref "JP4")
      (value "JP2EJP2_SMALLPADS")
      (footprint "eagle-import:JP2_SMALLPADS")
      (libsource (lib "eagle-import") (part "JP2EJP2_SMALLPADS"))
    )
    (comp (ref "JP5")
      (value "JP2EJP2_SMALLPADS")
      (footprint "eagle-import:JP2_SMALLPADS")
      (libsource (lib "eagle-import") (part "JP2EJP2_SMALLPADS"))
    )
    (comp (ref "LED1")
      (value "LEDLD260")
      (footprint "eagle-import:LD260")
      (libsource (lib "eagle-import") (part "LEDLD260"))
    )
    (comp (ref "LED2")
      (value "LEDLD260")
      (footprint "eagle-import:LD260")
      (libsource (lib "eagle-import") (part "LEDLD260"))
    )
    (comp (ref "LED3")
      (value "LEDLD260")
      (footprint "eagle-import:LD260")
      (libsource (lib "eagle-import") (part "LEDLD260"))
    )
    (comp (ref "LED4")
      (value "LEDLD260")
      (footprint "eagle-import:LD260")
      (libsource (lib "eagle-import") (part "LEDLD260"))
    )
    (comp (ref "LED5")
      (value "LEDLD260")
      (footprint "eagle-import:LD260")
      (libsource (lib "eagle-import") (part "LEDLD260"))
    )
    (comp (ref "LED6")
      (value "LEDLD260")
      (footprint "eagle-import:LD260")
      (libsource (lib "eagle-import") (part "LEDLD260"))
    )
    (comp (ref "Q4")
      (value "BA")
      (footprint "eagle-import:SOT89")
      (libsource (lib "eagle-import") (part "PNP-TRANSISTOR_SOT89"))
    )
    (comp (ref "Q5")
      (value "BA.")
      (footprint "eagle-import:SOT89")
      (libsource (lib "eagle-import") (part "PNP-TRANSISTOR_SOT89"))
    )
    (comp (ref "Q6")
      (value "BA.")
      (footprint "eagle-import:SOT89")
      (libsource (lib "eagle-import") (part "PNP-TRANSISTOR_SOT89"))
    )
    (comp (ref "Q7")
      (value "BA")
      (footprint "eagle-import:SOT89")
      (libsource (lib "eagle-import") (part "PNP-TRANSISTOR_SOT89"))
    )
    (comp (ref "Q8")
      (value "MY")
      (footprint "eagle-import:SOT89")
      (libsource (lib "eagle-import") (part "NPN-TRANSISTOR_SOT89"))
    )
    (comp (ref "Q9")
      (value "J1")
      (footprint "eagle-import:SOT-23")
      (fields (field (name "MPN") "BSS138W-7-F"))
      (libsource (lib "eagle-import") (part "SMD-MOSFET-N-CH-50V-200MA-BSS138W-7-F(SOT-23)"))
    )
    (comp (ref "Q10")
      (value "J1")
      (footprint "eagle-import:SOT-23")
      (fields (field (name "MPN") "BSS138W-7-F"))
      (libsource (lib "eagle-import") (part "SMD-MOSFET-N-CH-50V-200MA-BSS138W-7-F(SOT-23)"))
    )
    (comp (ref "Q11")
      (value "J1")
      (footprint "eagle-import:SOT-23")
      (fields (field (name "MPN") "BSS138W-7-F"))
      (libsource (lib "eagle-import") (part "SMD-MOSFET-N-CH-50V-200MA-BSS138W-7-F(SOT-23)"))
    )
    (comp (ref "Q12")
      (value "BA")
      (footprint "eagle-import:SOT89")
      (libsource (lib "eagle-import") (part "PNP-TRANSISTOR_SOT89"))
    )
    (comp (ref "Q13")
      (value "J1")
      (footprint "eagle-import:SOT-23")
      (fields (field (name "MPN") "BSS138W-7-F"))
      (libsource (lib "eagle-import") (part "SMD-MOSFET-N-CH-50V-200MA-BSS138W-7-F(SOT-23)"))
    )
    (comp (ref "R7")
      (value "47")
      (footprint "eagle-import:V235_17_1MM")
      (libsource (lib "eagle-import") (part "R-EU_V235/17_1MM"))
    )
    (comp (ref "R11")
      (value "13")
      (footprint "eagle-import:R1206")
      (fields (field (name "MPN") "RC1206JR-0713RL"))
      (libsource (lib "eagle-import") (part "SMD-RES-13R-5%-1/4W(1206)"))
    )
    (comp (ref "R14")
      (value "47")
      (footprint "eagle-import:V235_17_1MM")
      (libsource (lib "eagle-import") (part "R-EU_V235/17_1MM"))
    )
    (comp (ref "R15")
      (value "104")
      (footprint "eagle-import:R0805")
      (fields (field (name "MPN") "RC0805FR-0710KL"))
      (libsource (lib "eagle-import") (part "SMD-RES-10K-1%-1/8W(0805)"))
    )
    (comp (ref "R16")
      (value "104")
      (footprint "eagle-import:R0805")
      (fields (field (name "MPN") "RC0805FR-0710KL"))
      (libsource (lib "eagle-import") (part "SMD-RES-10K-1%-1/8W(0805)"))
    )
    (comp (ref "R17")
      (value "104")
      (footprint "eagle-import:R0805")
      (fields (field (name "MPN") "RC0805FR-0710KL"))
      (libsource (lib "eagle-import") (part "SMD-RES-10K-1%-1/8W(0805)"))
    )
    (comp (ref "R18")
      (value "4701")
      (footprint "eagle-import:R0805")
      (fields (field (name "MPN") "RC0805JR-074K7L"))
      (libsource (lib "eagle-import") (part "SMD-RES-4.7K-5%-1/8W(0805)"))
    )
    (comp (ref "R19")
      (value "1002")
      (footprint "eagle-import:R0805")
      (fields (field (name "MPN") "RC0805FR-0710KL"))
      (libsource (lib "eagle-import") (part "SMD-RES-10K-1%-1/8W(0805)"))
    )
    (comp (ref "R20")
      (value "1002")
      (footprint "eagle-import:R0805")
      (fields (field (name "MPN") "RC0805FR-0710KL"))
      (libsource (lib "eagle-import") (part "SMD-RES-10K-1%-1/8W(0805)"))
    )
    (comp (ref "R21")
      (value "1502")
      (footprint "eagle-import:R0805")
      (fields (field (name "MPN") "RC0805FR-0710KL"))
      (libsource (lib "eagle-import") (part "SMD-RES-10K-1%-1/8W(0805)"))
    )
    (comp (ref "R22")
      (value "104")
      (footprint "eagle-import:R0805")
      (fields (field (name "MPN") "RC0805FR-0710KL"))
      (libsource (lib "eagle-import") (part "SMD-RES-10K-1%-1/8W(0805)"))
    )
    (comp (ref "R23")
      (value "104")
      (footprint "eagle-import:R0805")
      (fields (field (name "MPN") "RC0805FR-0710KL"))
      (libsource (lib "eagle-import") (part "SMD-RES-10K-1%-1/8W(0805)"))
    )
    (comp (ref "R24")
      (value "1502")
      (footprint "eagle-import:R0805")
      (fields (field (name "MPN") "RC0805FR-0710KL"))
      (libsource (lib "eagle-import") (part "SMD-RES-10K-1%-1/8W(0805)"))
    )
    (comp (ref "R25")
      (value "1002")
      (footprint "eagle-import:R0805")
      (fields (field (name "MPN") "RC0805FR-0710KL"))
      (libsource (lib "eagle-import") (part "SMD-RES-10K-1%-1/8W(0805)"))
    )
    (comp (ref "R26")
      (value "2201")
      (footprint "eagle-import:R0805")
      (fields (field (name "MPN") "RC0805JR-072K2L"))
      (libsource (lib "eagle-import") (part "SMD-RES-2.2K-5%-1/8W(0805)"))
    )
    (comp (ref "R27")
      (value "1002")
      (footprint "eagle-import:R0805")
      (fields (field (name "MPN") "RC0805FR-0710KL"))
      (libsource (lib "eagle-import") (part "SMD-RES-10K-1%-1/8W(0805)"))
    )
    (comp (ref "R28")
      (value "4701")
      (footprint "eagle-import:R0805")
      (fields (field (name "MPN") "RC0805JR-074K7L"))
      (libsource (lib "eagle-import") (part "SMD-RES-4.7K-5%-1/8W(0805)"))
    )
    (comp (ref "R29")
      (value "2702")
      (footprint "eagle-import:R0805")
      (fields (field (name "MPN") "RC0805JR-074K7L"))
      (libsource (lib "eagle-import") (part "SMD-RES-4.7K-5%-1/8W(0805)"))
    )
    (comp (ref "R30")
      (value "102")
      (footprint "eagle-import:R0805")
      (fields (field (name "MPN") "RC0805JR-071KL"))
      (libsource (lib "eagle-import") (part "SMD-RES-1K-5%-1/8W(0805)"))
    )
    (comp (ref "R31")
      (value "R_user")
      (footprint "eagle-import:R0805")
      (libsource (lib "eagle-import") (part "R-EU_R0805"))
    )
    (comp (ref "R32")
      (value "102")
      (footprint "eagle-import:R0805")
      (fields (field (name "MPN") "RC0805JR-07220RL"))
      (libsource (lib "eagle-import") (part "SMD-RES-220R-5%-1/8W(0805)"))
    )
    (comp (ref "R33")
      (value "(101)")
      (footprint "eagle-import:R0805")
      (fields (field (name "MPN") "RC0805JR-07100RL"))
      (libsource (lib "eagle-import") (part "SMD-RES-100R-5%-1/8W(0805)"))
    )
    (comp (ref "R34")
      (value "(1000)")
      (footprint "eagle-import:R0805")
      (fields (field (name "MPN") "RC0805JR-07100RL"))
      (libsource (lib "eagle-import") (part "SMD-RES-100R-5%-1/8W(0805)"))
    )
    (comp (ref "R35")
      (value "102")
      (footprint "eagle-import:R0805")
      (fields (field (name "MPN") "RC0805JR-071KL"))
      (libsource (lib "eagle-import") (part "SMD-RES-1K-5%-1/8W(0805)"))
    )
    (comp (ref "R36")
      (value "13")
      (footprint "eagle-import:R1206")
      (fields (field (name "MPN") "RC1206JR-0713RL"))
      (libsource (lib "eagle-import") (part "SMD-RES-13R-5%-1/4W(1206)"))
    )
    (comp (ref "R37")
      (value "13")
      (footprint "eagle-import:R1206")
      (fields (field (name "MPN") "RC1206JR-0713RL"))
      (libsource (lib "eagle-import") (part "SMD-RES-13R-5%-1/4W(1206)"))
    )
    (comp (ref "R38")
      (value "2702")
      (footprint "eagle-import:R0805")
      (fields (field (name "MPN") "RC0805JR-074K7L"))
      (libsource (lib "eagle-import") (part "SMD-RES-4.7K-5%-1/8W(0805)"))
    )
    (comp (ref "R39")
      (value "4701")
      (footprint "eagle-import:R0805")
      (fields (field (name "MPN") "RC0805JR-074K7L"))
      (libsource (lib "eagle-import") (part "SMD-RES-4.7K-5%-1/8W(0805)"))
    )
    (comp (ref "R40")
      (value "100")
      (footprint "eagle-import:R0805")
      (fields (field (name "MPN") "RC0805JR-072K2L"))
      (libsource (lib "eagle-import") (part "SMD-RES-2.2K-5%-1/8W(0805)"))
    )
    (comp (ref "R41")
      (value "104")
      (footprint "eagle-import:R0805")
      (fields (field (name "MPN") "RC0805FR-0710KL"))
      (libsource (lib "eagle-import") (part "SMD-RES-10K-1%-1/8W(0805)"))
    )
    (comp (ref "R42")
      (value "104")
      (footprint "eagle-import:R0805")
      (fields (field (name "MPN") "RC0805FR-0710KL"))
      (libsource (lib "eagle-import") (part "SMD-RES-10K-1%-1/8W(0805)"))
    )
    (comp (ref "R43")
      (value "(1002)")
      (footprint "eagle-import:R0805")
      (fields (field (name "MPN") "RC0805FR-0710KL"))
      (libsource (lib "eagle-import") (part "SMD-RES-10K-1%-1/8W(0805)"))
    )
    (comp (ref "R44")
      (value "2702")
      (footprint "eagle-import:R0805")
      (fields (field (name "MPN") "RC0805FR-0710KL"))
      (libsource (lib "eagle-import") (part "SMD-RES-10K-1%-1/8W(0805)"))
    )
    (comp (ref "R45")
      (value "47")
      (footprint "eagle-import:V235_17_1MM")
      (libsource (lib "eagle-import") (part "R-EU_V235/17_1MM"))
    )
    (comp (ref "R46")
      (value "47")
      (footprint "eagle-import:V235_17_1MM")
      (libsource (lib "eagle-import") (part "R-EU_V235/17_1MM"))
    )
    (comp (ref "R47")
      (value "2702")
      (footprint "eagle-import:R0805")
      (fields (field (name "MPN") "RC0805JR-074K7L"))
      (libsource (lib "eagle-import") (part "SMD-RES-4.7K-5%-1/8W(0805)"))
    )
    (comp (ref "R48")
      (value "2201")
      (footprint "eagle-import:R0805")
      (fields (field (name "MPN") "RC0805JR-072K2L"))
      (libsource (lib "eagle-import") (part "SMD-RES-2.2K-5%-1/8W(0805)"))
    )
    (comp (ref "R49")
      (value "1002")
      (footprint "eagle-import:R0805")
      (fields (field (name "MPN") "RC0805JR-074K7L"))
      (libsource (lib "eagle-import") (part "SMD-RES-4.7K-5%-1/8W(0805)"))
    )
    (comp (ref "R50")
      (value "1002")
      (footprint "eagle-import:R0805")
      (fields (field (name "MPN") "RC0805FR-0710KL"))
      (libsource (lib "eagle-import") (part "SMD-RES-10K-1%-1/8W(0805)"))
    )
    (comp (ref "R51")
      (value "102")
      (footprint "eagle-import:R0805")
      (fields (field (name "MPN") "RC0805JR-071KL"))
      (libsource (lib "eagle-import") (part "SMD-RES-1K-5%-1/8W(0805)"))
    )
    (comp (ref "R52")
      (value "2702")
      (footprint "eagle-import:R0805")
      (fields (field (name "MPN") "RC0805JR-074K7L"))
      (libsource (lib "eagle-import") (part "SMD-RES-4.7K-5%-1/8W(0805)"))
    )
    (comp (ref "R53")
      (value "1002")
      (footprint "eagle-import:R0805")
      (fields (field (name "MPN") "RC0805JR-071KL"))
      (libsource (lib "eagle-import") (part "SMD-RES-1K-5%-1/8W(0805)"))
    )
    (comp (ref "R54")
      (value "1002")
      (footprint "eagle-import:R0805")
      (fields (field (name "MPN") "RC0805JR-071KL"))
      (libsource (lib "eagle-import") (part "SMD-RES-1K-5%-1/8W(0805)"))
    )
    (comp (ref "R55")
      (value "R_user")
      (footprint "eagle-import:R0805")
      (libsource (lib "eagle-import") (part "R-EU_R0805"))
    )
    (comp (ref "R56")
      (value "104")
      (footprint "eagle-import:R0805")
      (fields (field (name "MPN") "RC0805FR-0710KL"))
      (libsource (lib "eagle-import") (part "SMD-RES-10K-1%-1/8W(0805)"))
    )
    (comp (ref "R57")
      (value "104")
      (footprint "eagle-import:R0805")
      (fields (field (name "MPN") "RC0805FR-0710KL"))
      (libsource (lib "eagle-import") (part "SMD-RES-10K-1%-1/8W(0805)"))
    )
    (comp (ref "R58")
      (value "104")
      (footprint "eagle-import:R0805")
      (fields (field (name "MPN") "RC0805FR-0710KL"))
      (libsource (lib "eagle-import") (part "SMD-RES-10K-1%-1/8W(0805)"))
    )
    (comp (ref "R59")
      (value "13")
      (footprint "eagle-import:R1206")
      (fields (field (name "MPN") "RC1206JR-0713RL"))
      (libsource (lib "eagle-import") (part "SMD-RES-13R-5%-1/4W(1206)"))
    )
    (comp (ref "R60")
      (value "2201")
      (footprint "eagle-import:R0805")
      (fields (field (name "MPN") "RC0805JR-071KL"))
      (libsource (lib "eagle-import") (part "SMD-RES-1K-5%-1/8W(0805)"))
    )
    (comp (ref "R61")
      (value "100")
      (footprint "eagle-import:R0805")
      (fields (field (name "MPN") "RC0805JR-07220RL"))
      (libsource (lib "eagle-import") (part "SMD-RES-220R-5%-1/8W(0805)"))
    )
    (comp (ref "R62")
      (value "13")
      (footprint "eagle-import:R1206")
      (fields (field (name "MPN") "RC1206JR-0713RL"))
      (libsource (lib "eagle-import") (part "SMD-RES-13R-5%-1/4W(1206)"))
    )
    (comp (ref "R63")
      (value "4701")
      (footprint "eagle-import:R0805")
      (fields (field (name "MPN") "RC0805JR-074K7L"))
      (libsource (lib "eagle-import") (part "SMD-RES-4.7K-5%-1/8W(0805)"))
    )
    (comp (ref "R64")
      (value "104")
      (footprint "eagle-import:R0805")
      (fields (field (name "MPN") "RC0805JR-074K7L"))
      (libsource (lib "eagle-import") (part "SMD-RES-4.7K-5%-1/8W(0805)"))
    )
    (comp (ref "R65")
      (value "100")
      (footprint "eagle-import:R0805")
      (fields (field (name "MPN") "RC0805JR-072K2L"))
      (libsource (lib "eagle-import") (part "SMD-RES-2.2K-5%-1/8W(0805)"))
    )
    (comp (ref "R66")
      (value "100")
      (footprint "eagle-import:R0805")
      (fields (field (name "MPN") "RC0805JR-072K2L"))
      (libsource (lib "eagle-import") (part "SMD-RES-2.2K-5%-1/8W(0805)"))
    )
    (comp (ref "SJ1")
      (value "SJ")
      (footprint "eagle-import:SJ")
      (libsource (lib "eagle-import") (part "solder-jumper_SJ"))
    )
    (comp (ref "SJ3") (value "SJ") (footprint "eagle-import:SJ") (libsource (lib "eagle-import") (part "SJ")))
    (comp (ref "START1")
      (value "TPSB2.0")
      (footprint "eagle-import:B2.0")
      (libsource (lib "eagle-import") (part "TPSB2.0"))
    )
    (comp (ref "TP14")
      (value "TPSB2.0")
      (footprint "eagle-import:B2.0")
      (libsource (lib "eagle-import") (part "TPSB2.0"))
    )
    (comp (ref "TP15")
      (value "TPSB2.0")
      (footprint "eagle-import:B2.0")
      (libsource (lib "eagle-import") (part "TPSB2.0"))
    )
    (comp (ref "TP20")
      (value "TPSB2.0")
      (footprint "eagle-import:B2.0")
      (libsource (lib "eagle-import") (part "TPSB2.0"))
    )
    (comp (ref "TP27")
      (value "TPSB2.0")
      (footprint "eagle-import:B2.0")
      (libsource (lib "eagle-import") (part "TPSB2.0"))
    )
    (comp (ref "TP28")
      (value "TPSB2.0")
      (footprint "eagle-import:B2.0")
      (libsource (lib "eagle-import") (part "TPSB2.0"))
    )
    (comp (ref "TP29")
      (value "TPSB2.0")
      (footprint "eagle-import:B2.0")
      (libsource (lib "eagle-import") (part "TPSB2.0"))
    )
    (comp (ref "TP30")
      (value "TPSB2.0")
      (footprint "eagle-import:B2.0")
      (libsource (lib "eagle-import") (part "TPSB2.0"))
    )
    (comp (ref "TP31")
      (value "TPSB2.0")
      (footprint "eagle-import:B2.0")
      (libsource (lib "eagle-import") (part "TPSB2.0"))
    )
    (comp (ref "TP32")
      (value "TPSB2.0")
      (footprint "eagle-import:B2.0")
      (libsource (lib "eagle-import") (part "TPSB2.0"))
    )
    (comp (ref "TP33")
      (value "TPSB2.0")
      (footprint "eagle-import:B2.0")
      (libsource (lib "eagle-import") (part "TPSB2.0"))
    )
    (comp (ref "TP34")
      (value "TPSB2.0")
      (footprint "eagle-import:B2.0")
      (libsource (lib "eagle-import") (part "TPSB2.0"))
    )
    (comp (ref "TP35")
      (value "TPSB2.0")
      (footprint "eagle-import:B2.0")
      (libsource (lib "eagle-import") (part "TPSB2.0"))
    )
    (comp (ref "TP36")
      (value "TPSB2.0")
      (footprint "eagle-import:B2.0")
      (libsource (lib "eagle-import") (part "TPSB2.0"))
    )
    (comp (ref "TP37")
      (value "TPSB2.0")
      (footprint "eagle-import:B2.0")
      (libsource (lib "eagle-import") (part "TPSB2.0"))
    )
    (comp (ref "TP38")
      (value "TPSB2.0")
      (footprint "eagle-import:B2.0")
      (libsource (lib "eagle-import") (part "TPSB2.0"))
    )
    (comp (ref "TP39")
      (value "TPSB2.0")
      (footprint "eagle-import:B2.0")
      (libsource (lib "eagle-import") (part "TPSB2.0"))
    )
    (comp (ref "TP40")
      (value "TPSB2.0")
      (footprint "eagle-import:B2.0")
      (libsource (lib "eagle-import") (part "TPSB2.0"))
    )
    (comp (ref "TP41")
      (value "TPSB2.0")
      (footprint "eagle-import:B2.0")
      (libsource (lib "eagle-import") (part "TPSB2.0"))
    )
    (comp (ref "TP42")
      (value "TPSB1,27")
      (footprint "eagle-import:B1,27")
      (libsource (lib "eagle-import") (part "TPSB1,27"))
    )
    (comp (ref "TP43")
      (value "TPSB2.0")
      (footprint "eagle-import:B2.0")
      (libsource (lib "eagle-import") (part "TPSB2.0"))
    )
    (comp (ref "TP44")
      (value "TPSB2.0")
      (footprint "eagle-import:B2.0")
      (libsource (lib "eagle-import") (part "TPSB2.0"))
    )
    (comp (ref "TP45")
      (value "TPSB2.0")
      (footprint "eagle-import:B2.0")
      (libsource (lib "eagle-import") (part "TPSB2.0"))
    )
    (comp (ref "TP46")
      (value "TPSB2.0")
      (footprint "eagle-import:B2.0")
      (libsource (lib "eagle-import") (part "TPSB2.0"))
    )
    (comp (ref "X1")
      (value "CON_BMWV2")
      (footprint "eagle-import:24-PIN_V2")
      (libsource (lib "eagle-import") (part "CON_BMWV2"))
    )
    (comp (ref "X2")
      (value "22-23-2051")
      (footprint "eagle-import:22-23-2051")
      (fields (field (name "MF") "MOLEX"))
      (libsource (lib "eagle-import") (part "22-23-2051"))
    )
    (comp (ref "X3")
      (value "22-23-2021")
      (footprint "eagle-import:22-23-2021")
      (fields (field (name "MF") "MOLEX"))
      (libsource (lib "eagle-import") (part "22-23-2021"))
    )
    (comp (ref "1")
      (value "2081-1132")
      (footprint "eagle-import:12-PIN")
      (libsource (lib "eagle-import") (part "2081-1132"))
    )
    (comp (ref "2")
      (value "2081-1132")
      (footprint "eagle-import:12-PIN")
      (libsource (lib "eagle-import") (part "2081-1132"))
    )
    (comp (ref "6V")
      (value "TPSB2.0")
      (footprint "eagle-import:B2.0")
      (libsource (lib "eagle-import") (part "TPSB2.0"))
    )
    (comp (ref "10V")
      (value "TPSB2.0")
      (footprint "eagle-import:B2.0")
      (libsource (lib "eagle-import") (part "TPSB2.0"))
    )
    (comp (ref "C2")
      (value "10u")
      (footprint "eagle-import:C1206")
      (fields (field (name "MPN") "GRM31CR60J107ME39L"))
      (libsource (lib "eagle-import") (part "CERAMIC-100UF-6.3V-20%-X5R(1206)"))
    )
    (comp (ref "C15")
      (value "4.7u")
      (footprint "eagle-import:C0805")
      (fields (field (name "MPN") "CC0805KKX5R8BB475"))
      (libsource (lib "eagle-import") (part "CERAMIC-4.7UF-25V-10%-X5R(0805)"))
    )
    (comp (ref "C101")
      (value "4.7u")
      (footprint "eagle-import:C0805")
      (fields (field (name "MPN") "CC0805KKX5R8BB475"))
      (libsource (lib "eagle-import") (part "CERAMIC-4.7UF-25V-10%-X5R(0805)"))
    )
    (comp (ref "C102")
      (value "100nF")
      (footprint "eagle-import:C0805")
      (fields (field (name "MPN") "CC0805KRX7R9BB104"))
      (libsource (lib "eagle-import") (part "CERAMIC-100NF-50V-10%-X7R(0805)"))
    )
    (comp (ref "C103")
      (value "100nF,")
      (footprint "eagle-import:C0805")
      (fields (field (name "MPN") "CC0805KRX7R9BB104"))
      (libsource (lib "eagle-import") (part "CERAMIC-100NF-50V-10%-X7R(0805)"))
    )
    (comp (ref "C104")
      (value "100nF,")
      (footprint "eagle-import:C0805")
      (fields (field (name "MPN") "CC0805KRX7R9BB104"))
      (libsource (lib "eagle-import") (part "CERAMIC-100NF-50V-10%-X7R(0805)"))
    )
    (comp (ref "C105")
      (value "100nF.")
      (footprint "eagle-import:C0805")
      (fields (field (name "MPN") "CC0805KRX7R9BB104"))
      (libsource (lib "eagle-import") (part "CERAMIC-100NF-50V-10%-X7R(0805)"))
    )
    (comp (ref "C106")
      (value "100nF.")
      (footprint "eagle-import:C0805")
      (fields (field (name "MPN") "CC0805KRX7R9BB104"))
      (libsource (lib "eagle-import") (part "CERAMIC-100NF-50V-10%-X7R(0805)"))
    )
    (comp (ref "C107")
      (value "100u")
      (footprint "eagle-import:C1206")
      (fields (field (name "MPN") "GRM31CR60J107ME39L"))
      (libsource (lib "eagle-import") (part "CERAMIC-100UF-6.3V-20%-X5R(1206)"))
    )
    (comp (ref "C108")
      (value "100u")
      (footprint "eagle-import:C1206")
      (fields (field (name "MPN") "GRM31CR60J107ME39L"))
      (libsource (lib "eagle-import") (part "CERAMIC-100UF-6.3V-20%-X5R(1206)"))
    )
    (comp (ref "C109")
      (value "2.2nF")
      (footprint "eagle-import:C0805")
      (fields (field (name "MPN") "CC0805KRX7R9BB104"))
      (libsource (lib "eagle-import") (part "CERAMIC-100NF-50V-10%-X7R(0805)"))
    )
    (comp (ref "C110")
      (value "100nF")
      (footprint "eagle-import:C0805")
      (fields (field (name "MPN") "CC0805KRX7R9BB104"))
      (libsource (lib "eagle-import") (part "CERAMIC-100NF-50V-10%-X7R(0805)"))
    )
    (comp (ref "D1")
      (value "SS12")
      (footprint "eagle-import:DO-214AC_SLIM")
      (libsource (lib "eagle-import") (part "DIODE-GEN-PURPOSE-1KV-1A(DO-214AC)DO-214AC/1206"))
    )
    (comp (ref "D2")
      (value "SS12")
      (footprint "eagle-import:DO-214AC_SLIM")
      (libsource (lib "eagle-import") (part "DIODE-GEN-PURPOSE-1KV-1A(DO-214AC)DO-214AC/1206"))
    )
    (comp (ref "D4")
      (value "Zen11")
      (footprint "eagle-import:SOD-123_MINI-SMA")
      (libsource (lib "eagle-import") (part "CGRM400-G1"))
    )
    (comp (ref "D101")
      (value "Zen15")
      (footprint "eagle-import:DO214AA")
      (libsource (lib "eagle-import") (part "SM6T"))
    )
    (comp (ref "D102")
      (value "1N4007,")
      (footprint "eagle-import:DO-214AC")
      (fields (field (name "MPN") "1N4007"))
      (libsource (lib "eagle-import") (part "DIODE-GEN-PURPOSE-1KV-1A(DO-214AC)"))
    )
    (comp (ref "D103")
      (value "1N4007,")
      (footprint "eagle-import:DO-214AC")
      (fields (field (name "MPN") "1N4007"))
      (libsource (lib "eagle-import") (part "DIODE-GEN-PURPOSE-1KV-1A(DO-214AC)"))
    )
    (comp (ref "D104")
      (value "SM6TDO214AA_BI")
      (footprint "eagle-import:DO214AA_BI")
      (libsource (lib "eagle-import") (part "SM6TDO214AA_BI"))
    )
    (comp (ref "D105")
      (value "1N4007.")
      (footprint "eagle-import:DO-214AC")
      (fields (field (name "MPN") "1N4007"))
      (libsource (lib "eagle-import") (part "DIODE-GEN-PURPOSE-1KV-1A(DO-214AC)"))
    )
    (comp (ref "D106")
      (value "1N4007.")
      (footprint "eagle-import:DO-214AC")
      (fields (field (name "MPN") "1N4007"))
      (libsource (lib "eagle-import") (part "DIODE-GEN-PURPOSE-1KV-1A(DO-214AC)"))
    )
    (comp (ref "D107")
      (value "1N5817")
      (footprint "eagle-import:DO-214AC_SLIM")
      (libsource (lib "eagle-import") (part "DIODE-GEN-PURPOSE-1KV-1A(DO-214AC)DO-214AC/1206"))
    )
    (comp (ref "D108")
      (value "1N5817.")
      (footprint "eagle-import:DO-214AC_SLIM")
      (libsource (lib "eagle-import") (part "DIODE-GEN-PURPOSE-1KV-1A(DO-214AC)DO-214AC/1206"))
    )
    (comp (ref "D109")
      (value "1N5817.")
      (footprint "eagle-import:DO-214AC_SLIM")
      (libsource (lib "eagle-import") (part "DIODE-GEN-PURPOSE-1KV-1A(DO-214AC)DO-214AC/1206"))
    )
    (comp (ref "D110")
      (value "1N5817")
      (footprint "eagle-import:DO-214AC_SLIM")
      (libsource (lib "eagle-import") (part "DIODE-GEN-PURPOSE-1KV-1A(DO-214AC)DO-214AC/1206"))
    )
    (comp (ref "D112")
      (value "1N4007")
      (footprint "eagle-import:DO-214AC")
      (libsource (lib "eagle-import") (part "DIODE-GEN-PURPOSE-1KV-1A(DO-214AC)"))
    )
    (comp (ref "FID101")
      (value "FIDUCIAL")
      (footprint "eagle-import:FIDUCIAL_1MM")
      (libsource (lib "eagle-import") (part "FIDUCIAL"))
    )
    (comp (ref "FID102")
      (value "FIDUCIAL")
      (footprint "eagle-import:FIDUCIAL_1MM")
      (libsource (lib "eagle-import") (part "FIDUCIAL"))
    )
    (comp (ref "FID103")
      (value "FIDUCIAL")
      (footprint "eagle-import:FIDUCIAL_1MM")
      (libsource (lib "eagle-import") (part "FIDUCIAL"))
    )
    (comp (ref "FID104")
      (value "FIDUCIAL")
      (footprint "eagle-import:FIDUCIAL_1MM")
      (libsource (lib "eagle-import") (part "FIDUCIAL"))
    )
    (comp (ref "IC101")
      (value "LM2904")
      (footprint "eagle-import:SO08")
      (libsource (lib "eagle-import") (part "LM358D"))
    )
    (comp (ref "IC102")
      (value "78L06")
      (footprint "eagle-import:SOT89_ROUND")
      (libsource (lib "eagle-import") (part "78LXXSOT89_ROUND"))
    )
    (comp (ref "IC104")
      (value "78L10")
      (footprint "eagle-import:SOT89_ROUND")
      (libsource (lib "eagle-import") (part "78LXXSOT89_ROUND"))
    )
    (comp (ref "IC105")
      (value "4028")
      (footprint "eagle-import:SO16")
      (libsource (lib "eagle-import") (part "4028D"))
    )
    (comp (ref "IC107")
      (value "ULN2004")
      (footprint "eagle-import:SO16")
      (libsource (lib "eagle-import") (part "ULN2004AD"))
    )
    (comp (ref "IC108")
      (value "LM339")
      (footprint "eagle-import:SO14")
      (libsource (lib "eagle-import") (part "LM339D"))
    )
    (comp (ref "IC109")
      (value "317TO202H_NOHOLE")
      (footprint "eagle-import:TO220H_NOHOLE")
      (libsource (lib "eagle-import") (part "317TO202H_NOHOLE"))
    )
    (comp (ref "IC110")
      (value "555")
      (footprint "eagle-import:SO08")
      (libsource (lib "eagle-import") (part "555DNE"))
    )
    (comp (ref "IC111")
      (value "4538")
      (footprint "eagle-import:SO16")
      (libsource (lib "eagle-import") (part "4538D"))
    )
    (comp (ref "JP101")
      (value "JP2EJP2_SMALLPADS")
      (footprint "eagle-import:JP2_SMALLPADS")
      (libsource (lib "eagle-import") (part "JP2EJP2_SMALLPADS"))
    )
    (comp (ref "JP102")
      (value "JP2EJP2_SMALLPADS")
      (footprint "eagle-import:JP2_SMALLPADS")
      (libsource (lib "eagle-import") (part "JP2EJP2_SMALLPADS"))
    )
    (comp (ref "JP103")
      (value "JP2EJP2_SMALLPADS")
      (footprint "eagle-import:JP2_SMALLPADS")
      (libsource (lib "eagle-import") (part "JP2EJP2_SMALLPADS"))
    )
    (comp (ref "JP104")
      (value "JP2EJP2_SMALLPADS")
      (footprint "eagle-import:JP2_SMALLPADS")
      (libsource (lib "eagle-import") (part "JP2EJP2_SMALLPADS"))
    )
    (comp (ref "JP105")
      (value "JP2E_ORIG")
      (footprint "eagle-import:JP2_ORIG_SMALLPADS")
      (libsource (lib "eagle-import") (part "JP2E_ORIG"))
    )
    (comp (ref "LED101")
      (value "LEDLD260")
      (footprint "eagle-import:LD260")
      (libsource (lib "eagle-import") (part "LEDLD260"))
    )
    (comp (ref "LED102")
      (value "LEDLD260")
      (footprint "eagle-import:LD260")
      (libsource (lib "eagle-import") (part "LEDLD260"))
    )
    (comp (ref "LED103")
      (value "LEDLD260")
      (footprint "eagle-import:LD260")
      (libsource (lib "eagle-import") (part "LEDLD260"))
    )
    (comp (ref "LED104")
      (value "LEDLD260")
      (footprint "eagle-import:LD260")
      (libsource (lib "eagle-import") (part "LEDLD260"))
    )
    (comp (ref "LED105")
      (value "LEDLD260")
      (footprint "eagle-import:LD260")
      (libsource (lib "eagle-import") (part "LEDLD260"))
    )
    (comp (ref "LED106")
      (value "LEDLD260")
      (footprint "eagle-import:LD260")
      (libsource (lib "eagle-import") (part "LEDLD260"))
    )
    (comp (ref "Q1")
      (value "J1")
      (footprint "eagle-import:SOT-23")
      (fields (field (name "MPN") "BSS138W-7-F"))
      (libsource (lib "eagle-import") (part "SMD-MOSFET-N-CH-50V-200MA-BSS138W-7-F(SOT-23)"))
    )
    (comp (ref "Q2")
      (value "BA")
      (footprint "eagle-import:SOT89")
      (libsource (lib "eagle-import") (part "PNP-TRANSISTOR_SOT89"))
    )
    (comp (ref "Q3")
      (value "J1")
      (footprint "eagle-import:SOT-23")
      (fields (field (name "MPN") "BSS138W-7-F"))
      (libsource (lib "eagle-import") (part "SMD-MOSFET-N-CH-50V-200MA-BSS138W-7-F(SOT-23)"))
    )
    (comp (ref "Q101")
      (value "BA.")
      (footprint "eagle-import:SOT89")
      (libsource (lib "eagle-import") (part "PNP-TRANSISTOR_SOT89"))
    )
    (comp (ref "Q102")
      (value "BA.")
      (footprint "eagle-import:SOT89")
      (libsource (lib "eagle-import") (part "PNP-TRANSISTOR_SOT89"))
    )
    (comp (ref "Q103")
      (value "MY")
      (footprint "eagle-import:SOT89")
      (libsource (lib "eagle-import") (part "NPN-TRANSISTOR_SOT89"))
    )
    (comp (ref "Q104")
      (value "BA")
      (footprint "eagle-import:SOT89")
      (libsource (lib "eagle-import") (part "PNP-TRANSISTOR_SOT89"))
    )
    (comp (ref "Q105")
      (value "BA")
      (footprint "eagle-import:SOT89")
      (libsource (lib "eagle-import") (part "PNP-TRANSISTOR_SOT89"))
    )
    (comp (ref "Q106")
      (value "J1")
      (footprint "eagle-import:SOT-23")
      (fields (field (name "MPN") "BSS138W-7-F"))
      (libsource (lib "eagle-import") (part "SMD-MOSFET-N-CH-50V-200MA-BSS138W-7-F(SOT-23)"))
    )
    (comp (ref "Q107")
      (value "J1")
      (footprint "eagle-import:SOT-23")
      (fields (field (name "MPN") "BSS138W-7-F"))
      (libsource (lib "eagle-import") (part "SMD-MOSFET-N-CH-50V-200MA-BSS138W-7-F(SOT-23)"))
    )
    (comp (ref "R1")
      (value "104")
      (footprint "eagle-import:R0805")
      (fields (field (name "MPN") "RC0805FR-0710KL"))
      (libsource (lib "eagle-import") (part "SMD-RES-10K-1%-1/8W(0805)"))
    )
    (comp (ref "R2")
      (value "104")
      (footprint "eagle-import:R0805")
      (fields (field (name "MPN") "RC0805FR-0710KL"))
      (libsource (lib "eagle-import") (part "SMD-RES-10K-1%-1/8W(0805)"))
    )
    (comp (ref "R3")
      (value "104")
      (footprint "eagle-import:R0805")
      (fields (field (name "MPN") "RC0805FR-0710KL"))
      (libsource (lib "eagle-import") (part "SMD-RES-10K-1%-1/8W(0805)"))
    )
    (comp (ref "R4")
      (value "100")
      (footprint "eagle-import:R0805")
      (fields (field (name "MPN") "RC0805JR-07220RL"))
      (libsource (lib "eagle-import") (part "SMD-RES-220R-5%-1/8W(0805)"))
    )
    (comp (ref "R5")
      (value "13")
      (footprint "eagle-import:R1206")
      (fields (field (name "MPN") "RC1206JR-0713RL"))
      (libsource (lib "eagle-import") (part "SMD-RES-13R-5%-1/4W(1206)"))
    )
    (comp (ref "R6")
      (value "2201")
      (footprint "eagle-import:R0805")
      (fields (field (name "MPN") "RC0805JR-071KL"))
      (libsource (lib "eagle-import") (part "SMD-RES-1K-5%-1/8W(0805)"))
    )
    (comp (ref "R8")
      (value "4701")
      (footprint "eagle-import:R0805")
      (fields (field (name "MPN") "RC0805JR-074K7L"))
      (libsource (lib "eagle-import") (part "SMD-RES-4.7K-5%-1/8W(0805)"))
    )
    (comp (ref "R9")
      (value "13")
      (footprint "eagle-import:R1206")
      (fields (field (name "MPN") "RC1206JR-0713RL"))
      (libsource (lib "eagle-import") (part "SMD-RES-13R-5%-1/4W(1206)"))
    )
    (comp (ref "R10")
      (value "104")
      (footprint "eagle-import:R0805")
      (fields (field (name "MPN") "RC0805JR-074K7L"))
      (libsource (lib "eagle-import") (part "SMD-RES-4.7K-5%-1/8W(0805)"))
    )
    (comp (ref "R12")
      (value "100")
      (footprint "eagle-import:R0805")
      (fields (field (name "MPN") "RC0805JR-072K2L"))
      (libsource (lib "eagle-import") (part "SMD-RES-2.2K-5%-1/8W(0805)"))
    )
    (comp (ref "R13")
      (value "100")
      (footprint "eagle-import:R0805")
      (fields (field (name "MPN") "RC0805JR-072K2L"))
      (libsource (lib "eagle-import") (part "SMD-RES-2.2K-5%-1/8W(0805)"))
    )
    (comp (ref "R101")
      (value "102")
      (footprint "eagle-import:R0805")
      (fields (field (name "MPN") "RC0805JR-071KL"))
      (libsource (lib "eagle-import") (part "SMD-RES-1K-5%-1/8W(0805)"))
    )
    (comp (ref "R102")
      (value "13")
      (footprint "eagle-import:R1206")
      (fields (field (name "MPN") "RC1206JR-0713RL"))
      (libsource (lib "eagle-import") (part "SMD-RES-13R-5%-1/4W(1206)"))
    )
    (comp (ref "R103")
      (value "R_user")
      (footprint "eagle-import:R0805")
      (libsource (lib "eagle-import") (part "R-EU_R0805"))
    )
    (comp (ref "R104")
      (value "R_user")
      (footprint "eagle-import:R0805")
      (libsource (lib "eagle-import") (part "R-EU_R0805"))
    )
    (comp (ref "R105")
      (value "4701")
      (footprint "eagle-import:R0805")
      (fields (field (name "MPN") "RC0805JR-074K7L"))
      (libsource (lib "eagle-import") (part "SMD-RES-4.7K-5%-1/8W(0805)"))
    )
    (comp (ref "R106")
      (value "13")
      (footprint "eagle-import:R1206")
      (fields (field (name "MPN") "RC1206JR-0713RL"))
      (libsource (lib "eagle-import") (part "SMD-RES-13R-5%-1/4W(1206)"))
    )
    (comp (ref "R107")
      (value "1002")
      (footprint "eagle-import:R0805")
      (fields (field (name "MPN") "RC0805FR-0710KL"))
      (libsource (lib "eagle-import") (part "SMD-RES-10K-1%-1/8W(0805)"))
    )
    (comp (ref "R108")
      (value "1002")
      (footprint "eagle-import:R0805")
      (fields (field (name "MPN") "RC0805FR-0710KL"))
      (libsource (lib "eagle-import") (part "SMD-RES-10K-1%-1/8W(0805)"))
    )
    (comp (ref "R109")
      (value "104")
      (footprint "eagle-import:R0805")
      (fields (field (name "MPN") "RC0805FR-0710KL"))
      (libsource (lib "eagle-import") (part "SMD-RES-10K-1%-1/8W(0805)"))
    )
    (comp (ref "R110")
      (value "104")
      (footprint "eagle-import:R0805")
      (fields (field (name "MPN") "RC0805FR-0710KL"))
      (libsource (lib "eagle-import") (part "SMD-RES-10K-1%-1/8W(0805)"))
    )
    (comp (ref "R111")
      (value "104")
      (footprint "eagle-import:R0805")
      (fields (field (name "MPN") "RC0805FR-0710KL"))
      (libsource (lib "eagle-import") (part "SMD-RES-10K-1%-1/8W(0805)"))
    )
    (comp (ref "R112")
      (value "102")
      (footprint "eagle-import:R0805")
      (fields (field (name "MPN") "RC0805JR-071KL"))
      (libsource (lib "eagle-import") (part "SMD-RES-1K-5%-1/8W(0805)"))
    )
    (comp (ref "R113")
      (value "1002")
      (footprint "eagle-import:R0805")
      (fields (field (name "MPN") "RC0805JR-071KL"))
      (libsource (lib "eagle-import") (part "SMD-RES-1K-5%-1/8W(0805)"))
    )
    (comp (ref "R114")
      (value "1002")
      (footprint "eagle-import:R0805")
      (fields (field (name "MPN") "RC0805JR-071KL"))
      (libsource (lib "eagle-import") (part "SMD-RES-1K-5%-1/8W(0805)"))
    )
    (comp (ref "R115")
      (value "102")
      (footprint "eagle-import:R0805")
      (fields (field (name "MPN") "RC0805JR-07220RL"))
      (libsource (lib "eagle-import") (part "SMD-RES-220R-5%-1/8W(0805)"))
    )
    (comp (ref "R116")
      (value "4701")
      (footprint "eagle-import:R0805")
      (fields (field (name "MPN") "RC0805JR-074K7L"))
      (libsource (lib "eagle-import") (part "SMD-RES-4.7K-5%-1/8W(0805)"))
    )
    (comp (ref "R117")
      (value "2702")
      (footprint "eagle-import:R0805")
      (fields (field (name "MPN") "RC0805JR-074K7L"))
      (libsource (lib "eagle-import") (part "SMD-RES-4.7K-5%-1/8W(0805)"))
    )
    (comp (ref "R119")
      (value "2201")
      (footprint "eagle-import:R0805")
      (fields (field (name "MPN") "RC0805JR-072K2L"))
      (libsource (lib "eagle-import") (part "SMD-RES-2.2K-5%-1/8W(0805)"))
    )
    (comp (ref "R120")
      (value "1002")
      (footprint "eagle-import:R0805")
      (fields (field (name "MPN") "RC0805FR-0710KL"))
      (libsource (lib "eagle-import") (part "SMD-RES-10K-1%-1/8W(0805)"))
    )
    (comp (ref "R121")
      (value "1502")
      (footprint "eagle-import:R0805")
      (fields (field (name "MPN") "RC0805FR-0710KL"))
      (libsource (lib "eagle-import") (part "SMD-RES-10K-1%-1/8W(0805)"))
    )
    (comp (ref "R122")
      (value "2702")
      (footprint "eagle-import:R0805")
      (fields (field (name "MPN") "RC0805JR-074K7L"))
      (libsource (lib "eagle-import") (part "SMD-RES-4.7K-5%-1/8W(0805)"))
    )
    (comp (ref "R123")
      (value "2702")
      (footprint "eagle-import:R0805")
      (fields (field (name "MPN") "RC0805JR-074K7L"))
      (libsource (lib "eagle-import") (part "SMD-RES-4.7K-5%-1/8W(0805)"))
    )
    (comp (ref "R124")
      (value "1002")
      (footprint "eagle-import:R0805")
      (fields (field (name "MPN") "RC0805FR-0710KL"))
      (libsource (lib "eagle-import") (part "SMD-RES-10K-1%-1/8W(0805)"))
    )
    (comp (ref "R125")
      (value "104")
      (footprint "eagle-import:R0805")
      (fields (field (name "MPN") "RC0805FR-0710KL"))
      (libsource (lib "eagle-import") (part "SMD-RES-10K-1%-1/8W(0805)"))
    )
    (comp (ref "R126")
      (value "4701")
      (footprint "eagle-import:R0805")
      (fields (field (name "MPN") "RC0805JR-074K7L"))
      (libsource (lib "eagle-import") (part "SMD-RES-4.7K-5%-1/8W(0805)"))
    )
    (comp (ref "R127")
      (value "47")
      (footprint "eagle-import:V235_17_1MM")
      (libsource (lib "eagle-import") (part "R-EU_V235/17_1MM"))
    )
    (comp (ref "R128")
      (value "102")
      (footprint "eagle-import:R0805")
      (fields (field (name "MPN") "RC0805JR-071KL"))
      (libsource (lib "eagle-import") (part "SMD-RES-1K-5%-1/8W(0805)"))
    )
    (comp (ref "R129")
      (value "47")
      (footprint "eagle-import:V235_17_1MM")
      (libsource (lib "eagle-import") (part "R-EU_V235/17_1MM"))
    )
    (comp (ref "R130")
      (value "104")
      (footprint "eagle-import:R0805")
      (fields (field (name "MPN") "RC0805FR-0710KL"))
      (libsource (lib "eagle-import") (part "SMD-RES-10K-1%-1/8W(0805)"))
    )
    (comp (ref "R131")
      (value "1502")
      (footprint "eagle-import:R0805")
      (fields (field (name "MPN") "RC0805FR-0710KL"))
      (libsource (lib "eagle-import") (part "SMD-RES-10K-1%-1/8W(0805)"))
    )
    (comp (ref "R132")
      (value "1002")
      (footprint "eagle-import:R0805")
      (fields (field (name "MPN") "RC0805FR-0710KL"))
      (libsource (lib "eagle-import") (part "SMD-RES-10K-1%-1/8W(0805)"))
    )
    (comp (ref "R133")
      (value "2201")
      (footprint "eagle-import:R0805")
      (fields (field (name "MPN") "RC0805JR-072K2L"))
      (libsource (lib "eagle-import") (part "SMD-RES-2.2K-5%-1/8W(0805)"))
    )
    (comp (ref "R134")
      (value "13")
      (footprint "eagle-import:R1206")
      (fields (field (name "MPN") "RC1206JR-0713RL"))
      (libsource (lib "eagle-import") (part "SMD-RES-13R-5%-1/4W(1206)"))
    )
    (comp (ref "R135")
      (value "104")
      (footprint "eagle-import:R0805")
      (fields (field (name "MPN") "RC0805FR-0710KL"))
      (libsource (lib "eagle-import") (part "SMD-RES-10K-1%-1/8W(0805)"))
    )
    (comp (ref "R136")
      (value "47")
      (footprint "eagle-import:V235_17_1MM")
      (libsource (lib "eagle-import") (part "R-EU_V235/17_1MM"))
    )
    (comp (ref "R137")
      (value "47")
      (footprint "eagle-import:V235_17_1MM")
      (libsource (lib "eagle-import") (part "R-EU_V235/17_1MM"))
    )
    (comp (ref "R138")
      (value "100")
      (footprint "eagle-import:R0805")
      (fields (field (name "MPN") "RC0805JR-072K2L"))
      (libsource (lib "eagle-import") (part "SMD-RES-2.2K-5%-1/8W(0805)"))
    )
    (comp (ref "R140")
      (value "2702")
      (footprint "eagle-import:R0805")
      (fields (field (name "MPN") "RC0805FR-0710KL"))
      (libsource (lib "eagle-import") (part "SMD-RES-10K-1%-1/8W(0805)"))
    )
    (comp (ref "R141")
      (value "104")
      (footprint "eagle-import:R0805")
      (fields (field (name "MPN") "RC0805FR-0710KL"))
      (libsource (lib "eagle-import") (part "SMD-RES-10K-1%-1/8W(0805)"))
    )
    (comp (ref "R142")
      (value "(1000)")
      (footprint "eagle-import:R0805")
      (fields (field (name "MPN") "RC0805JR-07100RL"))
      (libsource (lib "eagle-import") (part "SMD-RES-100R-5%-1/8W(0805)"))
    )
    (comp (ref "R143")
      (value "(101)")
      (footprint "eagle-import:R0805")
      (fields (field (name "MPN") "RC0805JR-07100RL"))
      (libsource (lib "eagle-import") (part "SMD-RES-100R-5%-1/8W(0805)"))
    )
    (comp (ref "R144")
      (value "(1002)")
      (footprint "eagle-import:R0805")
      (fields (field (name "MPN") "RC0805FR-0710KL"))
      (libsource (lib "eagle-import") (part "SMD-RES-10K-1%-1/8W(0805)"))
    )
    (comp (ref "R145")
      (value "2702")
      (footprint "eagle-import:R0805")
      (fields (field (name "MPN") "RC0805JR-074K7L"))
      (libsource (lib "eagle-import") (part "SMD-RES-4.7K-5%-1/8W(0805)"))
    )
    (comp (ref "R146")
      (value "1002")
      (footprint "eagle-import:R0805")
      (fields (field (name "MPN") "RC0805JR-074K7L"))
      (libsource (lib "eagle-import") (part "SMD-RES-4.7K-5%-1/8W(0805)"))
    )
    (comp (ref "SJ2") (value "SJ") (footprint "eagle-import:SJ") (libsource (lib "eagle-import") (part "SJ")))
    (comp (ref "SJ101")
      (value "SJ")
      (footprint "eagle-import:SJ")
      (libsource (lib "eagle-import") (part "solder-jumper_SJ"))
    )
    (comp (ref "START")
      (value "TPSB2.0")
      (footprint "eagle-import:B2.0")
      (libsource (lib "eagle-import") (part "TPSB2.0"))
    )
    (comp (ref "TP1")
      (value "TPSB2.0")
      (footprint "eagle-import:B2.0")
      (libsource (lib "eagle-import") (part "TPSB2.0"))
    )
    (comp (ref "TP2")
      (value "TPSB2.0")
      (footprint "eagle-import:B2.0")
      (libsource (lib "eagle-import") (part "TPSB2.0"))
    )
    (comp (ref "TP3")
      (value "TPSB2.0")
      (footprint "eagle-import:B2.0")
      (libsource (lib "eagle-import") (part "TPSB2.0"))
    )
    (comp (ref "TP4")
      (value "TPSB2.0")
      (footprint "eagle-import:B2.0")
      (libsource (lib "eagle-import") (part "TPSB2.0"))
    )
    (comp (ref "TP5")
      (value "TPSB2.0")
      (footprint "eagle-import:B2.0")
      (libsource (lib "eagle-import") (part "TPSB2.0"))
    )
    (comp (ref "TP6")
      (value "TPSB2.0")
      (footprint "eagle-import:B2.0")
      (libsource (lib "eagle-import") (part "TPSB2.0"))
    )
    (comp (ref "TP7")
      (value "TPSB2.0")
      (footprint "eagle-import:B2.0")
      (libsource (lib "eagle-import") (part "TPSB2.0"))
    )
    (comp (ref "TP8")
      (value "TPSB2.0")
      (footprint "eagle-import:B2.0")
      (libsource (lib "eagle-import") (part "TPSB2.0"))
    )
    (comp (ref "TP9")
      (value "TPSB2.0")
      (footprint "eagle-import:B2.0")
      (libsource (lib "eagle-import") (part "TPSB2.0"))
    )
    (comp (ref "TP10")
      (value "TPSB2.0")
      (footprint "eagle-import:B2.0")
      (libsource (lib "eagle-import") (part "TPSB2.0"))
    )
    (comp (ref "TP11")
      (value "TPSB2.0")
      (footprint "eagle-import:B2.0")
      (libsource (lib "eagle-import") (part "TPSB2.0"))
    )
    (comp (ref "TP12")
      (value "TPSB2.0")
      (footprint "eagle-import:B2.0")
      (libsource (lib "eagle-import") (part "TPSB2.0"))
    )
    (comp (ref "TP13")
      (value "TPSB2.0")
      (footprint "eagle-import:B2.0")
      (libsource (lib "eagle-import") (part "TPSB2.0"))
    )
    (comp (ref "TP16")
      (value "TPSB2.0")
      (footprint "eagle-import:B2.0")
      (libsource (lib "eagle-import") (part "TPSB2.0"))
    )
    (comp (ref "TP17")
      (value "TPSB2.0")
      (footprint "eagle-import:B2.0")
      (libsource (lib "eagle-import") (part "TPSB2.0"))
    )
    (comp (ref "TP18")
      (value "TPSB2.0")
      (footprint "eagle-import:B2.0")
      (libsource (lib "eagle-import") (part "TPSB2.0"))
    )
    (comp (ref "TP19")
      (value "TPSB2.0")
      (footprint "eagle-import:B2.0")
      (libsource (lib "eagle-import") (part "TPSB2.0"))
    )
    (comp (ref "TP21")
      (value "TPSB2.0")
      (footprint "eagle-import:B2.0")
      (libsource (lib "eagle-import") (part "TPSB2.0"))
    )
    (comp (ref "TP22")
      (value "TPSB2.0")
      (footprint "eagle-import:B2.0")
      (libsource (lib "eagle-import") (part "TPSB2.0"))
    )
    (comp (ref "TP23")
      (value "TPSB2.0")
      (footprint "eagle-import:B2.0")
      (libsource (lib "eagle-import") (part "TPSB2.0"))
    )
    (comp (ref "TP24")
      (value "TPSB1,27")
      (footprint "eagle-import:B1,27")
      (libsource (lib "eagle-import") (part "TPSB1,27"))
    )
    (comp (ref "TP25")
      (value "TPSB2.0")
      (footprint "eagle-import:B2.0")
      (libsource (lib "eagle-import") (part "TPSB2.0"))
    )
    (comp (ref "TP26")
      (value "TPSB2.0")
      (footprint "eagle-import:B2.0")
      (libsource (lib "eagle-import") (part "TPSB2.0"))
    )
    (comp (ref "X101")
      (value "CON_BMWV2")
      (footprint "eagle-import:24-PIN_V2")
      (libsource (lib "eagle-import") (part "CON_BMWV2"))
    )
    (comp (ref "X102")
      (value "22-23-2021")
      (footprint "eagle-import:22-23-2021")
      (fields (field (name "MF") "MOLEX"))
      (libsource (lib "eagle-import") (part "22-23-2021"))
    )
    (comp (ref "X103")
      (value "22-23-2051")
      (footprint "eagle-import:22-23-2051")
      (fields (field (name "MF") "MOLEX"))
      (libsource (lib "eagle-import") (part "22-23-2051"))
    )
    (comp (ref "FID1")
      (value "FIDUCIAL")
      (footprint "eagle-import:FIDUCIAL_1MM")
      (libsource (lib "eagle-import") (part "FIDUCIAL"))
    )
    (comp (ref "FID1B")
      (value "FIDUCIALFIDUCIAL_1MM_WITH_SOLDERMASK")
      (footprint "eagle-import:FIDUCIAL_1MM_WITH_SOLDERMASK")
      (libsource (lib "eagle-import") (part "FIDUCIALFIDUCIAL_1MM_WITH_SOLDERMASK"))
    )
    (comp (ref "FID2")
      (value "FIDUCIAL")
      (footprint "eagle-import:FIDUCIAL_1MM")
      (libsource (lib "eagle-import") (part "FIDUCIAL"))
    )
    (comp (ref "FID2B")
      (value "FIDUCIALFIDUCIAL_1MM_WITH_SOLDERMASK")
      (footprint "eagle-import:FIDUCIAL_1MM_WITH_SOLDERMASK")
      (libsource (lib "eagle-import") (part "FIDUCIALFIDUCIAL_1MM_WITH_SOLDERMASK"))
    )
    (comp (ref "5")
      (value "2081-1132")
      (footprint "eagle-import:12-PIN")
      (libsource (lib "eagle-import") (part "2081-1132"))
    )
    (comp (ref "6")
      (value "2081-1132")
      (footprint "eagle-import:12-PIN")
      (libsource (lib "eagle-import") (part "2081-1132"))
    )
    (comp (ref "6V2")
      (value "TPSB2.0")
      (footprint "eagle-import:B2.0")
      (libsource (lib "eagle-import") (part "TPSB2.0"))
    )
    (comp (ref "10V2")
      (value "TPSB2.0")
      (footprint "eagle-import:B2.0")
      (libsource (lib "eagle-import") (part "TPSB2.0"))
    )
    (comp (ref "C14")
      (value "100u")
      (footprint "eagle-import:C1206")
      (fields (field (name "MPN") "GRM31CR60J107ME39L"))
      (libsource (lib "eagle-import") (part "CERAMIC-100UF-6.3V-20%-X5R(1206)"))
    )
    (comp (ref "C16")
      (value "100u")
      (footprint "eagle-import:C1206")
      (fields (field (name "MPN") "GRM31CR60J107ME39L"))
      (libsource (lib "eagle-import") (part "CERAMIC-100UF-6.3V-20%-X5R(1206)"))
    )
    (comp (ref "C17")
      (value "100nF,")
      (footprint "eagle-import:C0805")
      (fields (field (name "MPN") "CC0805KRX7R9BB104"))
      (libsource (lib "eagle-import") (part "CERAMIC-100NF-50V-10%-X7R(0805)"))
    )
    (comp (ref "C18")
      (value "4.7u")
      (footprint "eagle-import:C0805")
      (fields (field (name "MPN") "CC0805KKX5R8BB475"))
      (libsource (lib "eagle-import") (part "CERAMIC-4.7UF-25V-10%-X5R(0805)"))
    )
    (comp (ref "C19")
      (value "100nF.")
      (footprint "eagle-import:C0805")
      (fields (field (name "MPN") "CC0805KRX7R9BB104"))
      (libsource (lib "eagle-import") (part "CERAMIC-100NF-50V-10%-X7R(0805)"))
    )
    (comp (ref "C20")
      (value "100nF.")
      (footprint "eagle-import:C0805")
      (fields (field (name "MPN") "CC0805KRX7R9BB104"))
      (libsource (lib "eagle-import") (part "CERAMIC-100NF-50V-10%-X7R(0805)"))
    )
    (comp (ref "C21")
      (value "2.2nF")
      (footprint "eagle-import:C0805")
      (fields (field (name "MPN") "CC0805KRX7R9BB104"))
      (libsource (lib "eagle-import") (part "CERAMIC-100NF-50V-10%-X7R(0805)"))
    )
    (comp (ref "C22")
      (value "100nF")
      (footprint "eagle-import:C0805")
      (fields (field (name "MPN") "CC0805KRX7R9BB104"))
      (libsource (lib "eagle-import") (part "CERAMIC-100NF-50V-10%-X7R(0805)"))
    )
    (comp (ref "C23")
      (value "100nF")
      (footprint "eagle-import:C0805")
      (fields (field (name "MPN") "CC0805KRX7R9BB104"))
      (libsource (lib "eagle-import") (part "CERAMIC-100NF-50V-10%-X7R(0805)"))
    )
    (comp (ref "C24")
      (value "100nF,")
      (footprint "eagle-import:C0805")
      (fields (field (name "MPN") "CC0805KRX7R9BB104"))
      (libsource (lib "eagle-import") (part "CERAMIC-100NF-50V-10%-X7R(0805)"))
    )
    (comp (ref "C25")
      (value "4.7u")
      (footprint "eagle-import:C0805")
      (fields (field (name "MPN") "CC0805KKX5R8BB475"))
      (libsource (lib "eagle-import") (part "CERAMIC-4.7UF-25V-10%-X5R(0805)"))
    )
    (comp (ref "C26")
      (value "10u")
      (footprint "eagle-import:C1206")
      (fields (field (name "MPN") "GRM31CR60J107ME39L"))
      (libsource (lib "eagle-import") (part "CERAMIC-100UF-6.3V-20%-X5R(1206)"))
    )
    (comp (ref "D18")
      (value "1N4007,")
      (footprint "eagle-import:DO-214AC")
      (fields (field (name "MPN") "1N4007"))
      (libsource (lib "eagle-import") (part "DIODE-GEN-PURPOSE-1KV-1A(DO-214AC)"))
    )
    (comp (ref "D19")
      (value "1N4007,")
      (footprint "eagle-import:DO-214AC")
      (fields (field (name "MPN") "1N4007"))
      (libsource (lib "eagle-import") (part "DIODE-GEN-PURPOSE-1KV-1A(DO-214AC)"))
    )
    (comp (ref "D20")
      (value "1N4007.")
      (footprint "eagle-import:DO-214AC")
      (fields (field (name "MPN") "1N4007"))
      (libsource (lib "eagle-import") (part "DIODE-GEN-PURPOSE-1KV-1A(DO-214AC)"))
    )
    (comp (ref "D21")
      (value "1N5817")
      (footprint "eagle-import:DO-214AC_SLIM")
      (libsource (lib "eagle-import") (part "DIODE-GEN-PURPOSE-1KV-1A(DO-214AC)DO-214AC/1206"))
    )
    (comp (ref "D22")
      (value "1N5817.")
      (footprint "eagle-import:DO-214AC_SLIM")
      (libsource (lib "eagle-import") (part "DIODE-GEN-PURPOSE-1KV-1A(DO-214AC)DO-214AC/1206"))
    )
    (comp (ref "D23")
      (value "1N5817.")
      (footprint "eagle-import:DO-214AC_SLIM")
      (libsource (lib "eagle-import") (part "DIODE-GEN-PURPOSE-1KV-1A(DO-214AC)DO-214AC/1206"))
    )
    (comp (ref "D24")
      (value "1N5817")
      (footprint "eagle-import:DO-214AC_SLIM")
      (libsource (lib "eagle-import") (part "DIODE-GEN-PURPOSE-1KV-1A(DO-214AC)DO-214AC/1206"))
    )
    (comp (ref "D25")
      (value "1N4007.")
      (footprint "eagle-import:DO-214AC")
      (fields (field (name "MPN") "1N4007"))
      (libsource (lib "eagle-import") (part "DIODE-GEN-PURPOSE-1KV-1A(DO-214AC)"))
    )
    (comp (ref "D26")
      (value "1N4007")
      (footprint "eagle-import:DO-214AC")
      (libsource (lib "eagle-import") (part "DIODE-GEN-PURPOSE-1KV-1A(DO-214AC)"))
    )
    (comp (ref "D27")
      (value "Zen15")
      (footprint "eagle-import:DO214AA")
      (libsource (lib "eagle-import") (part "SM6T"))
    )
    (comp (ref "D28")
      (value "SM6TDO214AA_BI")
      (footprint "eagle-import:DO214AA_BI")
      (libsource (lib "eagle-import") (part "SM6TDO214AA_BI"))
    )
    (comp (ref "D29")
      (value "SS12")
      (footprint "eagle-import:DO-214AC_SLIM")
      (libsource (lib "eagle-import") (part "DIODE-GEN-PURPOSE-1KV-1A(DO-214AC)DO-214AC/1206"))
    )
    (comp (ref "D30")
      (value "SS12")
      (footprint "eagle-import:DO-214AC_SLIM")
      (libsource (lib "eagle-import") (part "DIODE-GEN-PURPOSE-1KV-1A(DO-214AC)DO-214AC/1206"))
    )
    (comp (ref "D31")
      (value "Zen11")
      (footprint "eagle-import:SOD-123_MINI-SMA")
      (libsource (lib "eagle-import") (part "CGRM400-G1"))
    )
    (comp (ref "FID7")
      (value "FIDUCIAL")
      (footprint "eagle-import:FIDUCIAL_1MM")
      (libsource (lib "eagle-import") (part "FIDUCIAL"))
    )
    (comp (ref "FID8")
      (value "FIDUCIAL")
      (footprint "eagle-import:FIDUCIAL_1MM")
      (libsource (lib "eagle-import") (part "FIDUCIAL"))
    )
    (comp (ref "FID9")
      (value "FIDUCIAL")
      (footprint "eagle-import:FIDUCIAL_1MM")
      (libsource (lib "eagle-import") (part "FIDUCIAL"))
    )
    (comp (ref "FID10")
      (value "FIDUCIAL")
      (footprint "eagle-import:FIDUCIAL_1MM")
      (libsource (lib "eagle-import") (part "FIDUCIAL"))
    )
    (comp (ref "IC10")
      (value "4028")
      (footprint "eagle-import:SO16")
      (libsource (lib "eagle-import") (part "4028D"))
    )
    (comp (ref "IC11")
      (value "317TO202H_NOHOLE")
      (footprint "eagle-import:TO220H_NOHOLE")
      (libsource (lib "eagle-import") (part "317TO202H_NOHOLE"))
    )
    (comp (ref "IC12")
      (value "ULN2004")
      (footprint "eagle-import:SO16")
      (libsource (lib "eagle-import") (part "ULN2004AD"))
    )
    (comp (ref "IC13")
      (value "LM339")
      (footprint "eagle-import:SO14")
      (libsource (lib "eagle-import") (part "LM339D"))
    )
    (comp (ref "IC14")
      (value "78L06")
      (footprint "eagle-import:SOT89_ROUND")
      (libsource (lib "eagle-import") (part "78LXXSOT89_ROUND"))
    )
    (comp (ref "IC15")
      (value "555")
      (footprint "eagle-import:SO08")
      (libsource (lib "eagle-import") (part "555DNE"))
    )
    (comp (ref "IC16")
      (value "4538")
      (footprint "eagle-import:SO16")
      (libsource (lib "eagle-import") (part "4538D"))
    )
    (comp (ref "IC17")
      (value "78L10")
      (footprint "eagle-import:SOT89_ROUND")
      (libsource (lib "eagle-import") (part "78LXXSOT89_ROUND"))
    )
    (comp (ref "IC18")
      (value "LM2904")
      (footprint "eagle-import:SO08")
      (libsource (lib "eagle-import") (part "LM358D"))
    )
    (comp (ref "JP6")
      (value "JP2EJP2_SMALLPADS")
      (footprint "eagle-import:JP2_SMALLPADS")
      (libsource (lib "eagle-import") (part "JP2EJP2_SMALLPADS"))
    )
    (comp (ref "JP7")
      (value "JP2E_ORIG")
      (footprint "eagle-import:JP2_ORIG_SMALLPADS")
      (libsource (lib "eagle-import") (part "JP2E_ORIG"))
    )
    (comp (ref "JP8")
      (value "JP2EJP2_SMALLPADS")
      (footprint "eagle-import:JP2_SMALLPADS")
      (libsource (lib "eagle-import") (part "JP2EJP2_SMALLPADS"))
    )
    (comp (ref "JP9")
      (value "JP2EJP2_SMALLPADS")
      (footprint "eagle-import:JP2_SMALLPADS")
      (libsource (lib "eagle-import") (part "JP2EJP2_SMALLPADS"))
    )
    (comp (ref "JP10")
      (value "JP2EJP2_SMALLPADS")
      (footprint "eagle-import:JP2_SMALLPADS")
      (libsource (lib "eagle-import") (part "JP2EJP2_SMALLPADS"))
    )
    (comp (ref "LED7")
      (value "LEDLD260")
      (footprint "eagle-import:LD260")
      (libsource (lib "eagle-import") (part "LEDLD260"))
    )
    (comp (ref "LED8")
      (value "LEDLD260")
      (footprint "eagle-import:LD260")
      (libsource (lib "eagle-import") (part "LEDLD260"))
    )
    (comp (ref "LED9")
      (value "LEDLD260")
      (footprint "eagle-import:LD260")
      (libsource (lib "eagle-import") (part "LEDLD260"))
    )
    (comp (ref "LED10")
      (value "LEDLD260")
      (footprint "eagle-import:LD260")
      (libsource (lib "eagle-import") (part "LEDLD260"))
    )
    (comp (ref "LED11")
      (value "LEDLD260")
      (footprint "eagle-import:LD260")
      (libsource (lib "eagle-import") (part "LEDLD260"))
    )
    (comp (ref "LED12")
      (value "LEDLD260")
      (footprint "eagle-import:LD260")
      (libsource (lib "eagle-import") (part "LEDLD260"))
    )
    (comp (ref "Q14")
      (value "BA")
      (footprint "eagle-import:SOT89")
      (libsource (lib "eagle-import") (part "PNP-TRANSISTOR_SOT89"))
    )
    (comp (ref "Q15")
      (value "BA.")
      (footprint "eagle-import:SOT89")
      (libsource (lib "eagle-import") (part "PNP-TRANSISTOR_SOT89"))
    )
    (comp (ref "Q16")
      (value "BA.")
      (footprint "eagle-import:SOT89")
      (libsource (lib "eagle-import") (part "PNP-TRANSISTOR_SOT89"))
    )
    (comp (ref "Q17")
      (value "BA")
      (footprint "eagle-import:SOT89")
      (libsource (lib "eagle-import") (part "PNP-TRANSISTOR_SOT89"))
    )
    (comp (ref "Q18")
      (value "MY")
      (footprint "eagle-import:SOT89")
      (libsource (lib "eagle-import") (part "NPN-TRANSISTOR_SOT89"))
    )
    (comp (ref "Q19")
      (value "J1")
      (footprint "eagle-import:SOT-23")
      (fields (field (name "MPN") "BSS138W-7-F"))
      (libsource (lib "eagle-import") (part "SMD-MOSFET-N-CH-50V-200MA-BSS138W-7-F(SOT-23)"))
    )
    (comp (ref "Q20")
      (value "J1")
      (footprint "eagle-import:SOT-23")
      (fields (field (name "MPN") "BSS138W-7-F"))
      (libsource (lib "eagle-import") (part "SMD-MOSFET-N-CH-50V-200MA-BSS138W-7-F(SOT-23)"))
    )
    (comp (ref "Q21")
      (value "J1")
      (footprint "eagle-import:SOT-23")
      (fields (field (name "MPN") "BSS138W-7-F"))
      (libsource (lib "eagle-import") (part "SMD-MOSFET-N-CH-50V-200MA-BSS138W-7-F(SOT-23)"))
    )
    (comp (ref "Q22")
      (value "BA")
      (footprint "eagle-import:SOT89")
      (libsource (lib "eagle-import") (part "PNP-TRANSISTOR_SOT89"))
    )
    (comp (ref "Q23")
      (value "J1")
      (footprint "eagle-import:SOT-23")
      (fields (field (name "MPN") "BSS138W-7-F"))
      (libsource (lib "eagle-import") (part "SMD-MOSFET-N-CH-50V-200MA-BSS138W-7-F(SOT-23)"))
    )
    (comp (ref "R67")
      (value "47")
      (footprint "eagle-import:V235_17_1MM")
      (libsource (lib "eagle-import") (part "R-EU_V235/17_1MM"))
    )
    (comp (ref "R68")
      (value "13")
      (footprint "eagle-import:R1206")
      (fields (field (name "MPN") "RC1206JR-0713RL"))
      (libsource (lib "eagle-import") (part "SMD-RES-13R-5%-1/4W(1206)"))
    )
    (comp (ref "R69")
      (value "47")
      (footprint "eagle-import:V235_17_1MM")
      (libsource (lib "eagle-import") (part "R-EU_V235/17_1MM"))
    )
    (comp (ref "R70")
      (value "104")
      (footprint "eagle-import:R0805")
      (fields (field (name "MPN") "RC0805FR-0710KL"))
      (libsource (lib "eagle-import") (part "SMD-RES-10K-1%-1/8W(0805)"))
    )
    (comp (ref "R71")
      (value "104")
      (footprint "eagle-import:R0805")
      (fields (field (name "MPN") "RC0805FR-0710KL"))
      (libsource (lib "eagle-import") (part "SMD-RES-10K-1%-1/8W(0805)"))
    )
    (comp (ref "R72")
      (value "104")
      (footprint "eagle-import:R0805")
      (fields (field (name "MPN") "RC0805FR-0710KL"))
      (libsource (lib "eagle-import") (part "SMD-RES-10K-1%-1/8W(0805)"))
    )
    (comp (ref "R73")
      (value "4701")
      (footprint "eagle-import:R0805")
      (fields (field (name "MPN") "RC0805JR-074K7L"))
      (libsource (lib "eagle-import") (part "SMD-RES-4.7K-5%-1/8W(0805)"))
    )
    (comp (ref "R74")
      (value "1002")
      (footprint "eagle-import:R0805")
      (fields (field (name "MPN") "RC0805FR-0710KL"))
      (libsource (lib "eagle-import") (part "SMD-RES-10K-1%-1/8W(0805)"))
    )
    (comp (ref "R75")
      (value "1002")
      (footprint "eagle-import:R0805")
      (fields (field (name "MPN") "RC0805FR-0710KL"))
      (libsource (lib "eagle-import") (part "SMD-RES-10K-1%-1/8W(0805)"))
    )
    (comp (ref "R76")
      (value "1502")
      (footprint "eagle-import:R0805")
      (fields (field (name "MPN") "RC0805FR-0710KL"))
      (libsource (lib "eagle-import") (part "SMD-RES-10K-1%-1/8W(0805)"))
    )
    (comp (ref "R77")
      (value "104")
      (footprint "eagle-import:R0805")
      (fields (field (name "MPN") "RC0805FR-0710KL"))
      (libsource (lib "eagle-import") (part "SMD-RES-10K-1%-1/8W(0805)"))
    )
    (comp (ref "R78")
      (value "104")
      (footprint "eagle-import:R0805")
      (fields (field (name "MPN") "RC0805FR-0710KL"))
      (libsource (lib "eagle-import") (part "SMD-RES-10K-1%-1/8W(0805)"))
    )
    (comp (ref "R79")
      (value "1502")
      (footprint "eagle-import:R0805")
      (fields (field (name "MPN") "RC0805FR-0710KL"))
      (libsource (lib "eagle-import") (part "SMD-RES-10K-1%-1/8W(0805)"))
    )
    (comp (ref "R80")
      (value "1002")
      (footprint "eagle-import:R0805")
      (fields (field (name "MPN") "RC0805FR-0710KL"))
      (libsource (lib "eagle-import") (part "SMD-RES-10K-1%-1/8W(0805)"))
    )
    (comp (ref "R81")
      (value "2201")
      (footprint "eagle-import:R0805")
      (fields (field (name "MPN") "RC0805JR-072K2L"))
      (libsource (lib "eagle-import") (part "SMD-RES-2.2K-5%-1/8W(0805)"))
    )
    (comp (ref "R82")
      (value "1002")
      (footprint "eagle-import:R0805")
      (fields (field (name "MPN") "RC0805FR-0710KL"))
      (libsource (lib "eagle-import") (part "SMD-RES-10K-1%-1/8W(0805)"))
    )
    (comp (ref "R83")
      (value "4701")
      (footprint "eagle-import:R0805")
      (fields (field (name "MPN") "RC0805JR-074K7L"))
      (libsource (lib "eagle-import") (part "SMD-RES-4.7K-5%-1/8W(0805)"))
    )
    (comp (ref "R84")
      (value "2702")
      (footprint "eagle-import:R0805")
      (fields (field (name "MPN") "RC0805JR-074K7L"))
      (libsource (lib "eagle-import") (part "SMD-RES-4.7K-5%-1/8W(0805)"))
    )
    (comp (ref "R85")
      (value "102")
      (footprint "eagle-import:R0805")
      (fields (field (name "MPN") "RC0805JR-071KL"))
      (libsource (lib "eagle-import") (part "SMD-RES-1K-5%-1/8W(0805)"))
    )
    (comp (ref "R86")
      (value "R_user")
      (footprint "eagle-import:R0805")
      (libsource (lib "eagle-import") (part "R-EU_R0805"))
    )
    (comp (ref "R87")
      (value "102")
      (footprint "eagle-import:R0805")
      (fields (field (name "MPN") "RC0805JR-07220RL"))
      (libsource (lib "eagle-import") (part "SMD-RES-220R-5%-1/8W(0805)"))
    )
    (comp (ref "R88")
      (value "(101)")
      (footprint "eagle-import:R0805")
      (fields (field (name "MPN") "RC0805JR-07100RL"))
      (libsource (lib "eagle-import") (part "SMD-RES-100R-5%-1/8W(0805)"))
    )
    (comp (ref "R89")
      (value "(1000)")
      (footprint "eagle-import:R0805")
      (fields (field (name "MPN") "RC0805JR-07100RL"))
      (libsource (lib "eagle-import") (part "SMD-RES-100R-5%-1/8W(0805)"))
    )
    (comp (ref "R90")
      (value "102")
      (footprint "eagle-import:R0805")
      (fields (field (name "MPN") "RC0805JR-071KL"))
      (libsource (lib "eagle-import") (part "SMD-RES-1K-5%-1/8W(0805)"))
    )
    (comp (ref "R91")
      (value "13")
      (footprint "eagle-import:R1206")
      (fields (field (name "MPN") "RC1206JR-0713RL"))
      (libsource (lib "eagle-import") (part "SMD-RES-13R-5%-1/4W(1206)"))
    )
    (comp (ref "R92")
      (value "13")
      (footprint "eagle-import:R1206")
      (fields (field (name "MPN") "RC1206JR-0713RL"))
      (libsource (lib "eagle-import") (part "SMD-RES-13R-5%-1/4W(1206)"))
    )
    (comp (ref "R93")
      (value "2702")
      (footprint "eagle-import:R0805")
      (fields (field (name "MPN") "RC0805JR-074K7L"))
      (libsource (lib "eagle-import") (part "SMD-RES-4.7K-5%-1/8W(0805)"))
    )
    (comp (ref "R94")
      (value "4701")
      (footprint "eagle-import:R0805")
      (fields (field (name "MPN") "RC0805JR-074K7L"))
      (libsource (lib "eagle-import") (part "SMD-RES-4.7K-5%-1/8W(0805)"))
    )
    (comp (ref "R95")
      (value "100")
      (footprint "eagle-import:R0805")
      (fields (field (name "MPN") "RC0805JR-072K2L"))
      (libsource (lib "eagle-import") (part "SMD-RES-2.2K-5%-1/8W(0805)"))
    )
    (comp (ref "R96")
      (value "104")
      (footprint "eagle-import:R0805")
      (fields (field (name "MPN") "RC0805FR-0710KL"))
      (libsource (lib "eagle-import") (part "SMD-RES-10K-1%-1/8W(0805)"))
    )
    (comp (ref "R97")
      (value "104")
      (footprint "eagle-import:R0805")
      (fields (field (name "MPN") "RC0805FR-0710KL"))
      (libsource (lib "eagle-import") (part "SMD-RES-10K-1%-1/8W(0805)"))
    )
    (comp (ref "R98")
      (value "(1002)")
      (footprint "eagle-import:R0805")
      (fields (field (name "MPN") "RC0805FR-0710KL"))
      (libsource (lib "eagle-import") (part "SMD-RES-10K-1%-1/8W(0805)"))
    )
    (comp (ref "R99")
      (value "2702")
      (footprint "eagle-import:R0805")
      (fields (field (name "MPN") "RC0805FR-0710KL"))
      (libsource (lib "eagle-import") (part "SMD-RES-10K-1%-1/8W(0805)"))
    )
    (comp (ref "R100")
      (value "47")
      (footprint "eagle-import:V235_17_1MM")
      (libsource (lib "eagle-import") (part "R-EU_V235/17_1MM"))
    )
    (comp (ref "R118")
      (value "47")
      (footprint "eagle-import:V235_17_1MM")
      (libsource (lib "eagle-import") (part "R-EU_V235/17_1MM"))
    )
    (comp (ref "R139")
      (value "2702")
      (footprint "eagle-import:R0805")
      (fields (field (name "MPN") "RC0805JR-074K7L"))
      (libsource (lib "eagle-import") (part "SMD-RES-4.7K-5%-1/8W(0805)"))
    )
    (comp (ref "R147")
      (value "2201")
      (footprint "eagle-import:R0805")
      (fields (field (name "MPN") "RC0805JR-072K2L"))
      (libsource (lib "eagle-import") (part "SMD-RES-2.2K-5%-1/8W(0805)"))
    )
    (comp (ref "R148")
      (value "1002")
      (footprint "eagle-import:R0805")
      (fields (field (name "MPN") "RC0805JR-074K7L"))
      (libsource (lib "eagle-import") (part "SMD-RES-4.7K-5%-1/8W(0805)"))
    )
    (comp (ref "R149")
      (value "1002")
      (footprint "eagle-import:R0805")
      (fields (field (name "MPN") "RC0805FR-0710KL"))
      (libsource (lib "eagle-import") (part "SMD-RES-10K-1%-1/8W(0805)"))
    )
    (comp (ref "R150")
      (value "102")
      (footprint "eagle-import:R0805")
      (fields (field (name "MPN") "RC0805JR-071KL"))
      (libsource (lib "eagle-import") (part "SMD-RES-1K-5%-1/8W(0805)"))
    )
    (comp (ref "R151")
      (value "2702")
      (footprint "eagle-import:R0805")
      (fields (field (name "MPN") "RC0805JR-074K7L"))
      (libsource (lib "eagle-import") (part "SMD-RES-4.7K-5%-1/8W(0805)"))
    )
    (comp (ref "R152")
      (value "1002")
      (footprint "eagle-import:R0805")
      (fields (field (name "MPN") "RC0805JR-071KL"))
      (libsource (lib "eagle-import") (part "SMD-RES-1K-5%-1/8W(0805)"))
    )
    (comp (ref "R153")
      (value "1002")
      (footprint "eagle-import:R0805")
      (fields (field (name "MPN") "RC0805JR-071KL"))
      (libsource (lib "eagle-import") (part "SMD-RES-1K-5%-1/8W(0805)"))
    )
    (comp (ref "R154")
      (value "R_user")
      (footprint "eagle-import:R0805")
      (libsource (lib "eagle-import") (part "R-EU_R0805"))
    )
    (comp (ref "R155")
      (value "104")
      (footprint "eagle-import:R0805")
      (fields (field (name "MPN") "RC0805FR-0710KL"))
      (libsource (lib "eagle-import") (part "SMD-RES-10K-1%-1/8W(0805)"))
    )
    (comp (ref "R156")
      (value "104")
      (footprint "eagle-import:R0805")
      (fields (field (name "MPN") "RC0805FR-0710KL"))
      (libsource (lib "eagle-import") (part "SMD-RES-10K-1%-1/8W(0805)"))
    )
    (comp (ref "R157")
      (value "104")
      (footprint "eagle-import:R0805")
      (fields (field (name "MPN") "RC0805FR-0710KL"))
      (libsource (lib "eagle-import") (part "SMD-RES-10K-1%-1/8W(0805)"))
    )
    (comp (ref "R158")
      (value "13")
      (footprint "eagle-import:R1206")
      (fields (field (name "MPN") "RC1206JR-0713RL"))
      (libsource (lib "eagle-import") (part "SMD-RES-13R-5%-1/4W(1206)"))
    )
    (comp (ref "R159")
      (value "2201")
      (footprint "eagle-import:R0805")
      (fields (field (name "MPN") "RC0805JR-071KL"))
      (libsource (lib "eagle-import") (part "SMD-RES-1K-5%-1/8W(0805)"))
    )
    (comp (ref "R160")
      (value "100")
      (footprint "eagle-import:R0805")
      (fields (field (name "MPN") "RC0805JR-07220RL"))
      (libsource (lib "eagle-import") (part "SMD-RES-220R-5%-1/8W(0805)"))
    )
    (comp (ref "R161")
      (value "13")
      (footprint "eagle-import:R1206")
      (fields (field (name "MPN") "RC1206JR-0713RL"))
      (libsource (lib "eagle-import") (part "SMD-RES-13R-5%-1/4W(1206)"))
    )
    (comp (ref "R162")
      (value "4701")
      (footprint "eagle-import:R0805")
      (fields (field (name "MPN") "RC0805JR-074K7L"))
      (libsource (lib "eagle-import") (part "SMD-RES-4.7K-5%-1/8W(0805)"))
    )
    (comp (ref "R163")
      (value "104")
      (footprint "eagle-import:R0805")
      (fields (field (name "MPN") "RC0805JR-074K7L"))
      (libsource (lib "eagle-import") (part "SMD-RES-4.7K-5%-1/8W(0805)"))
    )
    (comp (ref "R164")
      (value "100")
      (footprint "eagle-import:R0805")
      (fields (field (name "MPN") "RC0805JR-072K2L"))
      (libsource (lib "eagle-import") (part "SMD-RES-2.2K-5%-1/8W(0805)"))
    )
    (comp (ref "R165")
      (value "100")
      (footprint "eagle-import:R0805")
      (fields (field (name "MPN") "RC0805JR-072K2L"))
      (libsource (lib "eagle-import") (part "SMD-RES-2.2K-5%-1/8W(0805)"))
    )
    (comp (ref "SJ4")
      (value "SJ")
      (footprint "eagle-import:SJ")
      (libsource (lib "eagle-import") (part "solder-jumper_SJ"))
    )
    (comp (ref "SJ5") (value "SJ") (footprint "eagle-import:SJ") (libsource (lib "eagle-import") (part "SJ")))
    (comp (ref "START2")
      (value "TPSB2.0")
      (footprint "eagle-import:B2.0")
      (libsource (lib "eagle-import") (part "TPSB2.0"))
    )
    (comp (ref "TP47")
      (value "TPSB2.0")
      (footprint "eagle-import:B2.0")
      (libsource (lib "eagle-import") (part "TPSB2.0"))
    )
    (comp (ref "TP48")
      (value "TPSB2.0")
      (footprint "eagle-import:B2.0")
      (libsource (lib "eagle-import") (part "TPSB2.0"))
    )
    (comp (ref "TP49")
      (value "TPSB2.0")
      (footprint "eagle-import:B2.0")
      (libsource (lib "eagle-import") (part "TPSB2.0"))
    )
    (comp (ref "TP50")
      (value "TPSB2.0")
      (footprint "eagle-import:B2.0")
      (libsource (lib "eagle-import") (part "TPSB2.0"))
    )
    (comp (ref "TP51")
      (value "TPSB2.0")
      (footprint "eagle-import:B2.0")
      (libsource (lib "eagle-import") (part "TPSB2.0"))
    )
    (comp (ref "TP52")
      (value "TPSB2.0")
      (footprint "eagle-import:B2.0")
      (libsource (lib "eagle-import") (part "TPSB2.0"))
    )
    (comp (ref "TP53")
      (value "TPSB2.0")
      (footprint "eagle-import:B2.0")
      (libsource (lib "eagle-import") (part "TPSB2.0"))
    )
    (comp (ref "TP54")
      (value "TPSB2.0")
      (footprint "eagle-import:B2.0")
      (libsource (lib "eagle-import") (part "TPSB2.0"))
    )
    (comp (ref "TP55")
      (value "TPSB2.0")
      (footprint "eagle-import:B2.0")
      (libsource (lib "eagle-import") (part "TPSB2.0"))
    )
    (comp (ref "TP56")
      (value "TPSB2.0")
      (footprint "eagle-import:B2.0")
      (libsource (lib "eagle-import") (part "TPSB2.0"))
    )
    (comp (ref "TP57")
      (value "TPSB2.0")
      (footprint "eagle-import:B2.0")
      (libsource (lib "eagle-import") (part "TPSB2.0"))
    )
    (comp (ref "TP58")
      (value "TPSB2.0")
      (footprint "eagle-import:B2.0")
      (libsource (lib "eagle-import") (part "TPSB2.0"))
    )
    (comp (ref "TP59")
      (value "TPSB2.0")
      (footprint "eagle-import:B2.0")
      (libsource (lib "eagle-import") (part "TPSB2.0"))
    )
    (comp (ref "TP60")
      (value "TPSB2.0")
      (footprint "eagle-import:B2.0")
      (libsource (lib "eagle-import") (part "TPSB2.0"))
    )
    (comp (ref "TP61")
      (value "TPSB2.0")
      (footprint "eagle-import:B2.0")
      (libsource (lib "eagle-import") (part "TPSB2.0"))
    )
    (comp (ref "TP62")
      (value "TPSB2.0")
      (footprint "eagle-import:B2.0")
      (libsource (lib "eagle-import") (part "TPSB2.0"))
    )
    (comp (ref "TP63")
      (value "TPSB2.0")
      (footprint "eagle-import:B2.0")
      (libsource (lib "eagle-import") (part "TPSB2.0"))
    )
    (comp (ref "TP64")
      (value "TPSB2.0")
      (footprint "eagle-import:B2.0")
      (libsource (lib "eagle-import") (part "TPSB2.0"))
    )
    (comp (ref "TP65")
      (value "TPSB1,27")
      (footprint "eagle-import:B1,27")
      (libsource (lib "eagle-import") (part "TPSB1,27"))
    )
    (comp (ref "TP66")
      (value "TPSB2.0")
      (footprint "eagle-import:B2.0")
      (libsource (lib "eagle-import") (part "TPSB2.0"))
    )
    (comp (ref "TP67")
      (value "TPSB2.0")
      (footprint "eagle-import:B2.0")
      (libsource (lib "eagle-import") (part "TPSB2.0"))
    )
    (comp (ref "TP68")
      (value "TPSB2.0")
      (footprint "eagle-import:B2.0")
      (libsource (lib "eagle-import") (part "TPSB2.0"))
    )
    (comp (ref "TP69")
      (value "TPSB2.0")
      (footprint "eagle-import:B2.0")
      (libsource (lib "eagle-import") (part "TPSB2.0"))
    )
    (comp (ref "X4")
      (value "CON_BMWV2")
      (footprint "eagle-import:24-PIN_V2")
      (libsource (lib "eagle-import") (part "CON_BMWV2"))
    )
    (comp (ref "X5")
      (value "22-23-2051")
      (footprint "eagle-import:22-23-2051")
      (fields (field (name "MF") "MOLEX"))
      (libsource (lib "eagle-import") (part "22-23-2051"))
    )
    (comp (ref "X6")
      (value "22-23-2021")
      (footprint "eagle-import:22-23-2021")
      (fields (field (name "MF") "MOLEX"))
      (libsource (lib "eagle-import") (part "22-23-2021"))
    )
    (comp (ref "6V3")
      (value "TPSB2.0")
      (footprint "eagle-import:B2.0")
      (libsource (lib "eagle-import") (part "TPSB2.0"))
    )
    (comp (ref "7")
      (value "2081-1132")
      (footprint "eagle-import:12-PIN")
      (libsource (lib "eagle-import") (part "2081-1132"))
    )
    (comp (ref "8")
      (value "2081-1132")
      (footprint "eagle-import:12-PIN")
      (libsource (lib "eagle-import") (part "2081-1132"))
    )
    (comp (ref "10V3")
      (value "TPSB2.0")
      (footprint "eagle-import:B2.0")
      (libsource (lib "eagle-import") (part "TPSB2.0"))
    )
    (comp (ref "C27")
      (value "100u")
      (footprint "eagle-import:C1206")
      (fields (field (name "MPN") "GRM31CR60J107ME39L"))
      (libsource (lib "eagle-import") (part "CERAMIC-100UF-6.3V-20%-X5R(1206)"))
    )
    (comp (ref "C28")
      (value "100u")
      (footprint "eagle-import:C1206")
      (fields (field (name "MPN") "GRM31CR60J107ME39L"))
      (libsource (lib "eagle-import") (part "CERAMIC-100UF-6.3V-20%-X5R(1206)"))
    )
    (comp (ref "C29")
      (value "100nF,")
      (footprint "eagle-import:C0805")
      (fields (field (name "MPN") "CC0805KRX7R9BB104"))
      (libsource (lib "eagle-import") (part "CERAMIC-100NF-50V-10%-X7R(0805)"))
    )
    (comp (ref "C30")
      (value "4.7u")
      (footprint "eagle-import:C0805")
      (fields (field (name "MPN") "CC0805KKX5R8BB475"))
      (libsource (lib "eagle-import") (part "CERAMIC-4.7UF-25V-10%-X5R(0805)"))
    )
    (comp (ref "C31")
      (value "100nF.")
      (footprint "eagle-import:C0805")
      (fields (field (name "MPN") "CC0805KRX7R9BB104"))
      (libsource (lib "eagle-import") (part "CERAMIC-100NF-50V-10%-X7R(0805)"))
    )
    (comp (ref "C32")
      (value "100nF.")
      (footprint "eagle-import:C0805")
      (fields (field (name "MPN") "CC0805KRX7R9BB104"))
      (libsource (lib "eagle-import") (part "CERAMIC-100NF-50V-10%-X7R(0805)"))
    )
    (comp (ref "C33")
      (value "2.2nF")
      (footprint "eagle-import:C0805")
      (fields (field (name "MPN") "CC0805KRX7R9BB104"))
      (libsource (lib "eagle-import") (part "CERAMIC-100NF-50V-10%-X7R(0805)"))
    )
    (comp (ref "C34")
      (value "100nF")
      (footprint "eagle-import:C0805")
      (fields (field (name "MPN") "CC0805KRX7R9BB104"))
      (libsource (lib "eagle-import") (part "CERAMIC-100NF-50V-10%-X7R(0805)"))
    )
    (comp (ref "C35")
      (value "100nF")
      (footprint "eagle-import:C0805")
      (fields (field (name "MPN") "CC0805KRX7R9BB104"))
      (libsource (lib "eagle-import") (part "CERAMIC-100NF-50V-10%-X7R(0805)"))
    )
    (comp (ref "C36")
      (value "100nF,")
      (footprint "eagle-import:C0805")
      (fields (field (name "MPN") "CC0805KRX7R9BB104"))
      (libsource (lib "eagle-import") (part "CERAMIC-100NF-50V-10%-X7R(0805)"))
    )
    (comp (ref "C37")
      (value "4.7u")
      (footprint "eagle-import:C0805")
      (fields (field (name "MPN") "CC0805KKX5R8BB475"))
      (libsource (lib "eagle-import") (part "CERAMIC-4.7UF-25V-10%-X5R(0805)"))
    )
    (comp (ref "C38")
      (value "10u")
      (footprint "eagle-import:C1206")
      (fields (field (name "MPN") "GRM31CR60J107ME39L"))
      (libsource (lib "eagle-import") (part "CERAMIC-100UF-6.3V-20%-X5R(1206)"))
    )
    (comp (ref "D32")
      (value "1N4007,")
      (footprint "eagle-import:DO-214AC")
      (fields (field (name "MPN") "1N4007"))
      (libsource (lib "eagle-import") (part "DIODE-GEN-PURPOSE-1KV-1A(DO-214AC)"))
    )
    (comp (ref "D33")
      (value "1N4007,")
      (footprint "eagle-import:DO-214AC")
      (fields (field (name "MPN") "1N4007"))
      (libsource (lib "eagle-import") (part "DIODE-GEN-PURPOSE-1KV-1A(DO-214AC)"))
    )
    (comp (ref "D34")
      (value "1N4007.")
      (footprint "eagle-import:DO-214AC")
      (fields (field (name "MPN") "1N4007"))
      (libsource (lib "eagle-import") (part "DIODE-GEN-PURPOSE-1KV-1A(DO-214AC)"))
    )
    (comp (ref "D35")
      (value "1N5817")
      (footprint "eagle-import:DO-214AC_SLIM")
      (libsource (lib "eagle-import") (part "DIODE-GEN-PURPOSE-1KV-1A(DO-214AC)DO-214AC/1206"))
    )
    (comp (ref "D36")
      (value "1N5817.")
      (footprint "eagle-import:DO-214AC_SLIM")
      (libsource (lib "eagle-import") (part "DIODE-GEN-PURPOSE-1KV-1A(DO-214AC)DO-214AC/1206"))
    )
    (comp (ref "D37")
      (value "1N5817.")
      (footprint "eagle-import:DO-214AC_SLIM")
      (libsource (lib "eagle-import") (part "DIODE-GEN-PURPOSE-1KV-1A(DO-214AC)DO-214AC/1206"))
    )
    (comp (ref "D38")
      (value "1N5817")
      (footprint "eagle-import:DO-214AC_SLIM")
      (libsource (lib "eagle-import") (part "DIODE-GEN-PURPOSE-1KV-1A(DO-214AC)DO-214AC/1206"))
    )
    (comp (ref "D39")
      (value "1N4007.")
      (footprint "eagle-import:DO-214AC")
      (fields (field (name "MPN") "1N4007"))
      (libsource (lib "eagle-import") (part "DIODE-GEN-PURPOSE-1KV-1A(DO-214AC)"))
    )
    (comp (ref "D40")
      (value "1N4007")
      (footprint "eagle-import:DO-214AC")
      (libsource (lib "eagle-import") (part "DIODE-GEN-PURPOSE-1KV-1A(DO-214AC)"))
    )
    (comp (ref "D41")
      (value "Zen15")
      (footprint "eagle-import:DO214AA")
      (libsource (lib "eagle-import") (part "SM6T"))
    )
    (comp (ref "D42")
      (value "SM6TDO214AA_BI")
      (footprint "eagle-import:DO214AA_BI")
      (libsource (lib "eagle-import") (part "SM6TDO214AA_BI"))
    )
    (comp (ref "D43")
      (value "SS12")
      (footprint "eagle-import:DO-214AC_SLIM")
      (libsource (lib "eagle-import") (part "DIODE-GEN-PURPOSE-1KV-1A(DO-214AC)DO-214AC/1206"))
    )
    (comp (ref "D44")
      (value "SS12")
      (footprint "eagle-import:DO-214AC_SLIM")
      (libsource (lib "eagle-import") (part "DIODE-GEN-PURPOSE-1KV-1A(DO-214AC)DO-214AC/1206"))
    )
    (comp (ref "D45")
      (value "Zen11")
      (footprint "eagle-import:SOD-123_MINI-SMA")
      (libsource (lib "eagle-import") (part "CGRM400-G1"))
    )
    (comp (ref "FID11")
      (value "FIDUCIAL")
      (footprint "eagle-import:FIDUCIAL_1MM")
      (libsource (lib "eagle-import") (part "FIDUCIAL"))
    )
    (comp (ref "FID12")
      (value "FIDUCIAL")
      (footprint "eagle-import:FIDUCIAL_1MM")
      (libsource (lib "eagle-import") (part "FIDUCIAL"))
    )
    (comp (ref "FID13")
      (value "FIDUCIAL")
      (footprint "eagle-import:FIDUCIAL_1MM")
      (libsource (lib "eagle-import") (part "FIDUCIAL"))
    )
    (comp (ref "FID14")
      (value "FIDUCIAL")
      (footprint "eagle-import:FIDUCIAL_1MM")
      (libsource (lib "eagle-import") (part "FIDUCIAL"))
    )
    (comp (ref "IC19")
      (value "4028")
      (footprint "eagle-import:SO16")
      (libsource (lib "eagle-import") (part "4028D"))
    )
    (comp (ref "IC20")
      (value "317TO202H_NOHOLE")
      (footprint "eagle-import:TO220H_NOHOLE")
      (libsource (lib "eagle-import") (part "317TO202H_NOHOLE"))
    )
    (comp (ref "IC21")
      (value "ULN2004")
      (footprint "eagle-import:SO16")
      (libsource (lib "eagle-import") (part "ULN2004AD"))
    )
    (comp (ref "IC22")
      (value "LM339")
      (footprint "eagle-import:SO14")
      (libsource (lib "eagle-import") (part "LM339D"))
    )
    (comp (ref "IC23")
      (value "78L06")
      (footprint "eagle-import:SOT89_ROUND")
      (libsource (lib "eagle-import") (part "78LXXSOT89_ROUND"))
    )
    (comp (ref "IC24")
      (value "555")
      (footprint "eagle-import:SO08")
      (libsource (lib "eagle-import") (part "555DNE"))
    )
    (comp (ref "IC25")
      (value "4538")
      (footprint "eagle-import:SO16")
      (libsource (lib "eagle-import") (part "4538D"))
    )
    (comp (ref "IC26")
      (value "78L10")
      (footprint "eagle-import:SOT89_ROUND")
      (libsource (lib "eagle-import") (part "78LXXSOT89_ROUND"))
    )
    (comp (ref "IC27")
      (value "LM2904")
      (footprint "eagle-import:SO08")
      (libsource (lib "eagle-import") (part "LM358D"))
    )
    (comp (ref "JP11")
      (value "JP2EJP2_SMALLPADS")
      (footprint "eagle-import:JP2_SMALLPADS")
      (libsource (lib "eagle-import") (part "JP2EJP2_SMALLPADS"))
    )
    (comp (ref "JP12")
      (value "JP2E_ORIG")
      (footprint "eagle-import:JP2_ORIG_SMALLPADS")
      (libsource (lib "eagle-import") (part "JP2E_ORIG"))
    )
    (comp (ref "JP13")
      (value "JP2EJP2_SMALLPADS")
      (footprint "eagle-import:JP2_SMALLPADS")
      (libsource (lib "eagle-import") (part "JP2EJP2_SMALLPADS"))
    )
    (comp (ref "JP14")
      (value "JP2EJP2_SMALLPADS")
      (footprint "eagle-import:JP2_SMALLPADS")
      (libsource (lib "eagle-import") (part "JP2EJP2_SMALLPADS"))
    )
    (comp (ref "JP15")
      (value "JP2EJP2_SMALLPADS")
      (footprint "eagle-import:JP2_SMALLPADS")
      (libsource (lib "eagle-import") (part "JP2EJP2_SMALLPADS"))
    )
    (comp (ref "LED13")
      (value "LEDLD260")
      (footprint "eagle-import:LD260")
      (libsource (lib "eagle-import") (part "LEDLD260"))
    )
    (comp (ref "LED14")
      (value "LEDLD260")
      (footprint "eagle-import:LD260")
      (libsource (lib "eagle-import") (part "LEDLD260"))
    )
    (comp (ref "LED15")
      (value "LEDLD260")
      (footprint "eagle-import:LD260")
      (libsource (lib "eagle-import") (part "LEDLD260"))
    )
    (comp (ref "LED16")
      (value "LEDLD260")
      (footprint "eagle-import:LD260")
      (libsource (lib "eagle-import") (part "LEDLD260"))
    )
    (comp (ref "LED17")
      (value "LEDLD260")
      (footprint "eagle-import:LD260")
      (libsource (lib "eagle-import") (part "LEDLD260"))
    )
    (comp (ref "LED18")
      (value "LEDLD260")
      (footprint "eagle-import:LD260")
      (libsource (lib "eagle-import") (part "LEDLD260"))
    )
    (comp (ref "Q24")
      (value "BA")
      (footprint "eagle-import:SOT89")
      (libsource (lib "eagle-import") (part "PNP-TRANSISTOR_SOT89"))
    )
    (comp (ref "Q25")
      (value "BA.")
      (footprint "eagle-import:SOT89")
      (libsource (lib "eagle-import") (part "PNP-TRANSISTOR_SOT89"))
    )
    (comp (ref "Q26")
      (value "BA.")
      (footprint "eagle-import:SOT89")
      (libsource (lib "eagle-import") (part "PNP-TRANSISTOR_SOT89"))
    )
    (comp (ref "Q27")
      (value "BA")
      (footprint "eagle-import:SOT89")
      (libsource (lib "eagle-import") (part "PNP-TRANSISTOR_SOT89"))
    )
    (comp (ref "Q28")
      (value "MY")
      (footprint "eagle-import:SOT89")
      (libsource (lib "eagle-import") (part "NPN-TRANSISTOR_SOT89"))
    )
    (comp (ref "Q29")
      (value "J1")
      (footprint "eagle-import:SOT-23")
      (fields (field (name "MPN") "BSS138W-7-F"))
      (libsource (lib "eagle-import") (part "SMD-MOSFET-N-CH-50V-200MA-BSS138W-7-F(SOT-23)"))
    )
    (comp (ref "Q30")
      (value "J1")
      (footprint "eagle-import:SOT-23")
      (fields (field (name "MPN") "BSS138W-7-F"))
      (libsource (lib "eagle-import") (part "SMD-MOSFET-N-CH-50V-200MA-BSS138W-7-F(SOT-23)"))
    )
    (comp (ref "Q31")
      (value "J1")
      (footprint "eagle-import:SOT-23")
      (fields (field (name "MPN") "BSS138W-7-F"))
      (libsource (lib "eagle-import") (part "SMD-MOSFET-N-CH-50V-200MA-BSS138W-7-F(SOT-23)"))
    )
    (comp (ref "Q32")
      (value "BA")
      (footprint "eagle-import:SOT89")
      (libsource (lib "eagle-import") (part "PNP-TRANSISTOR_SOT89"))
    )
    (comp (ref "Q33")
      (value "J1")
      (footprint "eagle-import:SOT-23")
      (fields (field (name "MPN") "BSS138W-7-F"))
      (libsource (lib "eagle-import") (part "SMD-MOSFET-N-CH-50V-200MA-BSS138W-7-F(SOT-23)"))
    )
    (comp (ref "R166")
      (value "47")
      (footprint "eagle-import:V235_17_1MM")
      (libsource (lib "eagle-import") (part "R-EU_V235/17_1MM"))
    )
    (comp (ref "R167")
      (value "13")
      (footprint "eagle-import:R1206")
      (fields (field (name "MPN") "RC1206JR-0713RL"))
      (libsource (lib "eagle-import") (part "SMD-RES-13R-5%-1/4W(1206)"))
    )
    (comp (ref "R168")
      (value "47")
      (footprint "eagle-import:V235_17_1MM")
      (libsource (lib "eagle-import") (part "R-EU_V235/17_1MM"))
    )
    (comp (ref "R169")
      (value "104")
      (footprint "eagle-import:R0805")
      (fields (field (name "MPN") "RC0805FR-0710KL"))
      (libsource (lib "eagle-import") (part "SMD-RES-10K-1%-1/8W(0805)"))
    )
    (comp (ref "R170")
      (value "104")
      (footprint "eagle-import:R0805")
      (fields (field (name "MPN") "RC0805FR-0710KL"))
      (libsource (lib "eagle-import") (part "SMD-RES-10K-1%-1/8W(0805)"))
    )
    (comp (ref "R171")
      (value "104")
      (footprint "eagle-import:R0805")
      (fields (field (name "MPN") "RC0805FR-0710KL"))
      (libsource (lib "eagle-import") (part "SMD-RES-10K-1%-1/8W(0805)"))
    )
    (comp (ref "R172")
      (value "4701")
      (footprint "eagle-import:R0805")
      (fields (field (name "MPN") "RC0805JR-074K7L"))
      (libsource (lib "eagle-import") (part "SMD-RES-4.7K-5%-1/8W(0805)"))
    )
    (comp (ref "R173")
      (value "1002")
      (footprint "eagle-import:R0805")
      (fields (field (name "MPN") "RC0805FR-0710KL"))
      (libsource (lib "eagle-import") (part "SMD-RES-10K-1%-1/8W(0805)"))
    )
    (comp (ref "R174")
      (value "1002")
      (footprint "eagle-import:R0805")
      (fields (field (name "MPN") "RC0805FR-0710KL"))
      (libsource (lib "eagle-import") (part "SMD-RES-10K-1%-1/8W(0805)"))
    )
    (comp (ref "R175")
      (value "1502")
      (footprint "eagle-import:R0805")
      (fields (field (name "MPN") "RC0805FR-0710KL"))
      (libsource (lib "eagle-import") (part "SMD-RES-10K-1%-1/8W(0805)"))
    )
    (comp (ref "R176")
      (value "104")
      (footprint "eagle-import:R0805")
      (fields (field (name "MPN") "RC0805FR-0710KL"))
      (libsource (lib "eagle-import") (part "SMD-RES-10K-1%-1/8W(0805)"))
    )
    (comp (ref "R177")
      (value "104")
      (footprint "eagle-import:R0805")
      (fields (field (name "MPN") "RC0805FR-0710KL"))
      (libsource (lib "eagle-import") (part "SMD-RES-10K-1%-1/8W(0805)"))
    )
    (comp (ref "R178")
      (value "1502")
      (footprint "eagle-import:R0805")
      (fields (field (name "MPN") "RC0805FR-0710KL"))
      (libsource (lib "eagle-import") (part "SMD-RES-10K-1%-1/8W(0805)"))
    )
    (comp (ref "R179")
      (value "1002")
      (footprint "eagle-import:R0805")
      (fields (field (name "MPN") "RC0805FR-0710KL"))
      (libsource (lib "eagle-import") (part "SMD-RES-10K-1%-1/8W(0805)"))
    )
    (comp (ref "R180")
      (value "2201")
      (footprint "eagle-import:R0805")
      (fields (field (name "MPN") "RC0805JR-072K2L"))
      (libsource (lib "eagle-import") (part "SMD-RES-2.2K-5%-1/8W(0805)"))
    )
    (comp (ref "R181")
      (value "1002")
      (footprint "eagle-import:R0805")
      (fields (field (name "MPN") "RC0805FR-0710KL"))
      (libsource (lib "eagle-import") (part "SMD-RES-10K-1%-1/8W(0805)"))
    )
    (comp (ref "R182")
      (value "4701")
      (footprint "eagle-import:R0805")
      (fields (field (name "MPN") "RC0805JR-074K7L"))
      (libsource (lib "eagle-import") (part "SMD-RES-4.7K-5%-1/8W(0805)"))
    )
    (comp (ref "R183")
      (value "2702")
      (footprint "eagle-import:R0805")
      (fields (field (name "MPN") "RC0805JR-074K7L"))
      (libsource (lib "eagle-import") (part "SMD-RES-4.7K-5%-1/8W(0805)"))
    )
    (comp (ref "R184")
      (value "102")
      (footprint "eagle-import:R0805")
      (fields (field (name "MPN") "RC0805JR-071KL"))
      (libsource (lib "eagle-import") (part "SMD-RES-1K-5%-1/8W(0805)"))
    )
    (comp (ref "R185")
      (value "R_user")
      (footprint "eagle-import:R0805")
      (libsource (lib "eagle-import") (part "R-EU_R0805"))
    )
    (comp (ref "R186")
      (value "102")
      (footprint "eagle-import:R0805")
      (fields (field (name "MPN") "RC0805JR-07220RL"))
      (libsource (lib "eagle-import") (part "SMD-RES-220R-5%-1/8W(0805)"))
    )
    (comp (ref "R187")
      (value "(101)")
      (footprint "eagle-import:R0805")
      (fields (field (name "MPN") "RC0805JR-07100RL"))
      (libsource (lib "eagle-import") (part "SMD-RES-100R-5%-1/8W(0805)"))
    )
    (comp (ref "R188")
      (value "(1000)")
      (footprint "eagle-import:R0805")
      (fields (field (name "MPN") "RC0805JR-07100RL"))
      (libsource (lib "eagle-import") (part "SMD-RES-100R-5%-1/8W(0805)"))
    )
    (comp (ref "R189")
      (value "102")
      (footprint "eagle-import:R0805")
      (fields (field (name "MPN") "RC0805JR-071KL"))
      (libsource (lib "eagle-import") (part "SMD-RES-1K-5%-1/8W(0805)"))
    )
    (comp (ref "R190")
      (value "13")
      (footprint "eagle-import:R1206")
      (fields (field (name "MPN") "RC1206JR-0713RL"))
      (libsource (lib "eagle-import") (part "SMD-RES-13R-5%-1/4W(1206)"))
    )
    (comp (ref "R191")
      (value "13")
      (footprint "eagle-import:R1206")
      (fields (field (name "MPN") "RC1206JR-0713RL"))
      (libsource (lib "eagle-import") (part "SMD-RES-13R-5%-1/4W(1206)"))
    )
    (comp (ref "R192")
      (value "2702")
      (footprint "eagle-import:R0805")
      (fields (field (name "MPN") "RC0805JR-074K7L"))
      (libsource (lib "eagle-import") (part "SMD-RES-4.7K-5%-1/8W(0805)"))
    )
    (comp (ref "R193")
      (value "4701")
      (footprint "eagle-import:R0805")
      (fields (field (name "MPN") "RC0805JR-074K7L"))
      (libsource (lib "eagle-import") (part "SMD-RES-4.7K-5%-1/8W(0805)"))
    )
    (comp (ref "R194")
      (value "100")
      (footprint "eagle-import:R0805")
      (fields (field (name "MPN") "RC0805JR-072K2L"))
      (libsource (lib "eagle-import") (part "SMD-RES-2.2K-5%-1/8W(0805)"))
    )
    (comp (ref "R195")
      (value "104")
      (footprint "eagle-import:R0805")
      (fields (field (name "MPN") "RC0805FR-0710KL"))
      (libsource (lib "eagle-import") (part "SMD-RES-10K-1%-1/8W(0805)"))
    )
    (comp (ref "R196")
      (value "104")
      (footprint "eagle-import:R0805")
      (fields (field (name "MPN") "RC0805FR-0710KL"))
      (libsource (lib "eagle-import") (part "SMD-RES-10K-1%-1/8W(0805)"))
    )
    (comp (ref "R197")
      (value "(1002)")
      (footprint "eagle-import:R0805")
      (fields (field (name "MPN") "RC0805FR-0710KL"))
      (libsource (lib "eagle-import") (part "SMD-RES-10K-1%-1/8W(0805)"))
    )
    (comp (ref "R198")
      (value "2702")
      (footprint "eagle-import:R0805")
      (fields (field (name "MPN") "RC0805FR-0710KL"))
      (libsource (lib "eagle-import") (part "SMD-RES-10K-1%-1/8W(0805)"))
    )
    (comp (ref "R199")
      (value "47")
      (footprint "eagle-import:V235_17_1MM")
      (libsource (lib "eagle-import") (part "R-EU_V235/17_1MM"))
    )
    (comp (ref "R200")
      (value "47")
      (footprint "eagle-import:V235_17_1MM")
      (libsource (lib "eagle-import") (part "R-EU_V235/17_1MM"))
    )
    (comp (ref "R201")
      (value "2702")
      (footprint "eagle-import:R0805")
      (fields (field (name "MPN") "RC0805JR-074K7L"))
      (libsource (lib "eagle-import") (part "SMD-RES-4.7K-5%-1/8W(0805)"))
    )
    (comp (ref "R202")
      (value "2201")
      (footprint "eagle-import:R0805")
      (fields (field (name "MPN") "RC0805JR-072K2L"))
      (libsource (lib "eagle-import") (part "SMD-RES-2.2K-5%-1/8W(0805)"))
    )
    (comp (ref "R203")
      (value "1002")
      (footprint "eagle-import:R0805")
      (fields (field (name "MPN") "RC0805JR-074K7L"))
      (libsource (lib "eagle-import") (part "SMD-RES-4.7K-5%-1/8W(0805)"))
    )
    (comp (ref "R204")
      (value "1002")
      (footprint "eagle-import:R0805")
      (fields (field (name "MPN") "RC0805FR-0710KL"))
      (libsource (lib "eagle-import") (part "SMD-RES-10K-1%-1/8W(0805)"))
    )
    (comp (ref "R205")
      (value "102")
      (footprint "eagle-import:R0805")
      (fields (field (name "MPN") "RC0805JR-071KL"))
      (libsource (lib "eagle-import") (part "SMD-RES-1K-5%-1/8W(0805)"))
    )
    (comp (ref "R206")
      (value "2702")
      (footprint "eagle-import:R0805")
      (fields (field (name "MPN") "RC0805JR-074K7L"))
      (libsource (lib "eagle-import") (part "SMD-RES-4.7K-5%-1/8W(0805)"))
    )
    (comp (ref "R207")
      (value "1002")
      (footprint "eagle-import:R0805")
      (fields (field (name "MPN") "RC0805JR-071KL"))
      (libsource (lib "eagle-import") (part "SMD-RES-1K-5%-1/8W(0805)"))
    )
    (comp (ref "R208")
      (value "1002")
      (footprint "eagle-import:R0805")
      (fields (field (name "MPN") "RC0805JR-071KL"))
      (libsource (lib "eagle-import") (part "SMD-RES-1K-5%-1/8W(0805)"))
    )
    (comp (ref "R209")
      (value "R_user")
      (footprint "eagle-import:R0805")
      (libsource (lib "eagle-import") (part "R-EU_R0805"))
    )
    (comp (ref "R210")
      (value "104")
      (footprint "eagle-import:R0805")
      (fields (field (name "MPN") "RC0805FR-0710KL"))
      (libsource (lib "eagle-import") (part "SMD-RES-10K-1%-1/8W(0805)"))
    )
    (comp (ref "R211")
      (value "104")
      (footprint "eagle-import:R0805")
      (fields (field (name "MPN") "RC0805FR-0710KL"))
      (libsource (lib "eagle-import") (part "SMD-RES-10K-1%-1/8W(0805)"))
    )
    (comp (ref "R212")
      (value "104")
      (footprint "eagle-import:R0805")
      (fields (field (name "MPN") "RC0805FR-0710KL"))
      (libsource (lib "eagle-import") (part "SMD-RES-10K-1%-1/8W(0805)"))
    )
    (comp (ref "R213")
      (value "13")
      (footprint "eagle-import:R1206")
      (fields (field (name "MPN") "RC1206JR-0713RL"))
      (libsource (lib "eagle-import") (part "SMD-RES-13R-5%-1/4W(1206)"))
    )
    (comp (ref "R214")
      (value "2201")
      (footprint "eagle-import:R0805")
      (fields (field (name "MPN") "RC0805JR-071KL"))
      (libsource (lib "eagle-import") (part "SMD-RES-1K-5%-1/8W(0805)"))
    )
    (comp (ref "R215")
      (value "100")
      (footprint "eagle-import:R0805")
      (fields (field (name "MPN") "RC0805JR-07220RL"))
      (libsource (lib "eagle-import") (part "SMD-RES-220R-5%-1/8W(0805)"))
    )
    (comp (ref "R216")
      (value "13")
      (footprint "eagle-import:R1206")
      (fields (field (name "MPN") "RC1206JR-0713RL"))
      (libsource (lib "eagle-import") (part "SMD-RES-13R-5%-1/4W(1206)"))
    )
    (comp (ref "R217")
      (value "4701")
      (footprint "eagle-import:R0805")
      (fields (field (name "MPN") "RC0805JR-074K7L"))
      (libsource (lib "eagle-import") (part "SMD-RES-4.7K-5%-1/8W(0805)"))
    )
    (comp (ref "R218")
      (value "104")
      (footprint "eagle-import:R0805")
      (fields (field (name "MPN") "RC0805JR-074K7L"))
      (libsource (lib "eagle-import") (part "SMD-RES-4.7K-5%-1/8W(0805)"))
    )
    (comp (ref "R219")
      (value "100")
      (footprint "eagle-import:R0805")
      (fields (field (name "MPN") "RC0805JR-072K2L"))
      (libsource (lib "eagle-import") (part "SMD-RES-2.2K-5%-1/8W(0805)"))
    )
    (comp (ref "R220")
      (value "100")
      (footprint "eagle-import:R0805")
      (fields (field (name "MPN") "RC0805JR-072K2L"))
      (libsource (lib "eagle-import") (part "SMD-RES-2.2K-5%-1/8W(0805)"))
    )
    (comp (ref "SJ6")
      (value "SJ")
      (footprint "eagle-import:SJ")
      (libsource (lib "eagle-import") (part "solder-jumper_SJ"))
    )
    (comp (ref "SJ7") (value "SJ") (footprint "eagle-import:SJ") (libsource (lib "eagle-import") (part "SJ")))
    (comp (ref "START3")
      (value "TPSB2.0")
      (footprint "eagle-import:B2.0")
      (libsource (lib "eagle-import") (part "TPSB2.0"))
    )
    (comp (ref "TP70")
      (value "TPSB2.0")
      (footprint "eagle-import:B2.0")
      (libsource (lib "eagle-import") (part "TPSB2.0"))
    )
    (comp (ref "TP71")
      (value "TPSB2.0")
      (footprint "eagle-import:B2.0")
      (libsource (lib "eagle-import") (part "TPSB2.0"))
    )
    (comp (ref "TP72")
      (value "TPSB2.0")
      (footprint "eagle-import:B2.0")
      (libsource (lib "eagle-import") (part "TPSB2.0"))
    )
    (comp (ref "TP73")
      (value "TPSB2.0")
      (footprint "eagle-import:B2.0")
      (libsource (lib "eagle-import") (part "TPSB2.0"))
    )
    (comp (ref "TP74")
      (value "TPSB2.0")
      (footprint "eagle-import:B2.0")
      (libsource (lib "eagle-import") (part "TPSB2.0"))
    )
    (comp (ref "TP75")
      (value "TPSB2.0")
      (footprint "eagle-import:B2.0")
      (libsource (lib "eagle-import") (part "TPSB2.0"))
    )
    (comp (ref "TP76")
      (value "TPSB2.0")
      (footprint "eagle-import:B2.0")
      (libsource (lib "eagle-import") (part "TPSB2.0"))
    )
    (comp (ref "TP77")
      (value "TPSB2.0")
      (footprint "eagle-import:B2.0")
      (libsource (lib "eagle-import") (part "TPSB2.0"))
    )
    (comp (ref "TP78")
      (value "TPSB2.0")
      (footprint "eagle-import:B2.0")
      (libsource (lib "eagle-import") (part "TPSB2.0"))
    )
    (comp (ref "TP79")
      (value "TPSB2.0")
      (footprint "eagle-import:B2.0")
      (libsource (lib "eagle-import") (part "TPSB2.0"))
    )
    (comp (ref "TP80")
      (value "TPSB2.0")
      (footprint "eagle-import:B2.0")
      (libsource (lib "eagle-import") (part "TPSB2.0"))
    )
    (comp (ref "TP81")
      (value "TPSB2.0")
      (footprint "eagle-import:B2.0")
      (libsource (lib "eagle-import") (part "TPSB2.0"))
    )
    (comp (ref "TP82")
      (value "TPSB2.0")
      (footprint "eagle-import:B2.0")
      (libsource (lib "eagle-import") (part "TPSB2.0"))
    )
    (comp (ref "TP83")
      (value "TPSB2.0")
      (footprint "eagle-import:B2.0")
      (libsource (lib "eagle-import") (part "TPSB2.0"))
    )
    (comp (ref "TP84")
      (value "TPSB2.0")
      (footprint "eagle-import:B2.0")
      (libsource (lib "eagle-import") (part "TPSB2.0"))
    )
    (comp (ref "TP85")
      (value "TPSB2.0")
      (footprint "eagle-import:B2.0")
      (libsource (lib "eagle-import") (part "TPSB2.0"))
    )
    (comp (ref "TP86")
      (value "TPSB2.0")
      (footprint "eagle-import:B2.0")
      (libsource (lib "eagle-import") (part "TPSB2.0"))
    )
    (comp (ref "TP87")
      (value "TPSB2.0")
      (footprint "eagle-import:B2.0")
      (libsource (lib "eagle-import") (part "TPSB2.0"))
    )
    (comp (ref "TP88")
      (value "TPSB1,27")
      (footprint "eagle-import:B1,27")
      (libsource (lib "eagle-import") (part "TPSB1,27"))
    )
    (comp (ref "TP89")
      (value "TPSB2.0")
      (footprint "eagle-import:B2.0")
      (libsource (lib "eagle-import") (part "TPSB2.0"))
    )
    (comp (ref "TP90")
      (value "TPSB2.0")
      (footprint "eagle-import:B2.0")
      (libsource (lib "eagle-import") (part "TPSB2.0"))
    )
    (comp (ref "TP91")
      (value "TPSB2.0")
      (footprint "eagle-import:B2.0")
      (libsource (lib "eagle-import") (part "TPSB2.0"))
    )
    (comp (ref "TP92")
      (value "TPSB2.0")
      (footprint "eagle-import:B2.0")
      (libsource (lib "eagle-import") (part "TPSB2.0"))
    )
    (comp (ref "X7")
      (value "CON_BMWV2")
      (footprint "eagle-import:24-PIN_V2")
      (libsource (lib "eagle-import") (part "CON_BMWV2"))
    )
    (comp (ref "X8")
      (value "22-23-2051")
      (footprint "eagle-import:22-23-2051")
      (fields (field (name "MF") "MOLEX"))
      (libsource (lib "eagle-import") (part "22-23-2051"))
    )
    (comp (ref "X9")
      (value "22-23-2021")
      (footprint "eagle-import:22-23-2021")
      (fields (field (name "MF") "MOLEX"))
      (libsource (lib "eagle-import") (part "22-23-2021"))
    )
    (comp (ref "6V4")
      (value "TPSB2.0")
      (footprint "eagle-import:B2.0")
      (libsource (lib "eagle-import") (part "TPSB2.0"))
    )
    (comp (ref "9")
      (value "2081-1132")
      (footprint "eagle-import:12-PIN")
      (libsource (lib "eagle-import") (part "2081-1132"))
    )
    (comp (ref "10")
      (value "2081-1132")
      (footprint "eagle-import:12-PIN")
      (libsource (lib "eagle-import") (part "2081-1132"))
    )
    (comp (ref "10V4")
      (value "TPSB2.0")
      (footprint "eagle-import:B2.0")
      (libsource (lib "eagle-import") (part "TPSB2.0"))
    )
    (comp (ref "C39")
      (value "100u")
      (footprint "eagle-import:C1206")
      (fields (field (name "MPN") "GRM31CR60J107ME39L"))
      (libsource (lib "eagle-import") (part "CERAMIC-100UF-6.3V-20%-X5R(1206)"))
    )
    (comp (ref "C40")
      (value "100u")
      (footprint "eagle-import:C1206")
      (fields (field (name "MPN") "GRM31CR60J107ME39L"))
      (libsource (lib "eagle-import") (part "CERAMIC-100UF-6.3V-20%-X5R(1206)"))
    )
    (comp (ref "C41")
      (value "100nF,")
      (footprint "eagle-import:C0805")
      (fields (field (name "MPN") "CC0805KRX7R9BB104"))
      (libsource (lib "eagle-import") (part "CERAMIC-100NF-50V-10%-X7R(0805)"))
    )
    (comp (ref "C42")
      (value "4.7u")
      (footprint "eagle-import:C0805")
      (fields (field (name "MPN") "CC0805KKX5R8BB475"))
      (libsource (lib "eagle-import") (part "CERAMIC-4.7UF-25V-10%-X5R(0805)"))
    )
    (comp (ref "C43")
      (value "100nF.")
      (footprint "eagle-import:C0805")
      (fields (field (name "MPN") "CC0805KRX7R9BB104"))
      (libsource (lib "eagle-import") (part "CERAMIC-100NF-50V-10%-X7R(0805)"))
    )
    (comp (ref "C44")
      (value "100nF.")
      (footprint "eagle-import:C0805")
      (fields (field (name "MPN") "CC0805KRX7R9BB104"))
      (libsource (lib "eagle-import") (part "CERAMIC-100NF-50V-10%-X7R(0805)"))
    )
    (comp (ref "C45")
      (value "2.2nF")
      (footprint "eagle-import:C0805")
      (fields (field (name "MPN") "CC0805KRX7R9BB104"))
      (libsource (lib "eagle-import") (part "CERAMIC-100NF-50V-10%-X7R(0805)"))
    )
    (comp (ref "C46")
      (value "100nF")
      (footprint "eagle-import:C0805")
      (fields (field (name "MPN") "CC0805KRX7R9BB104"))
      (libsource (lib "eagle-import") (part "CERAMIC-100NF-50V-10%-X7R(0805)"))
    )
    (comp (ref "C47")
      (value "100nF")
      (footprint "eagle-import:C0805")
      (fields (field (name "MPN") "CC0805KRX7R9BB104"))
      (libsource (lib "eagle-import") (part "CERAMIC-100NF-50V-10%-X7R(0805)"))
    )
    (comp (ref "C48")
      (value "100nF,")
      (footprint "eagle-import:C0805")
      (fields (field (name "MPN") "CC0805KRX7R9BB104"))
      (libsource (lib "eagle-import") (part "CERAMIC-100NF-50V-10%-X7R(0805)"))
    )
    (comp (ref "C49")
      (value "4.7u")
      (footprint "eagle-import:C0805")
      (fields (field (name "MPN") "CC0805KKX5R8BB475"))
      (libsource (lib "eagle-import") (part "CERAMIC-4.7UF-25V-10%-X5R(0805)"))
    )
    (comp (ref "C50")
      (value "10u")
      (footprint "eagle-import:C1206")
      (fields (field (name "MPN") "GRM31CR60J107ME39L"))
      (libsource (lib "eagle-import") (part "CERAMIC-100UF-6.3V-20%-X5R(1206)"))
    )
    (comp (ref "D46")
      (value "1N4007,")
      (footprint "eagle-import:DO-214AC")
      (fields (field (name "MPN") "1N4007"))
      (libsource (lib "eagle-import") (part "DIODE-GEN-PURPOSE-1KV-1A(DO-214AC)"))
    )
    (comp (ref "D47")
      (value "1N4007,")
      (footprint "eagle-import:DO-214AC")
      (fields (field (name "MPN") "1N4007"))
      (libsource (lib "eagle-import") (part "DIODE-GEN-PURPOSE-1KV-1A(DO-214AC)"))
    )
    (comp (ref "D48")
      (value "1N4007.")
      (footprint "eagle-import:DO-214AC")
      (fields (field (name "MPN") "1N4007"))
      (libsource (lib "eagle-import") (part "DIODE-GEN-PURPOSE-1KV-1A(DO-214AC)"))
    )
    (comp (ref "D49")
      (value "1N5817")
      (footprint "eagle-import:DO-214AC_SLIM")
      (libsource (lib "eagle-import") (part "DIODE-GEN-PURPOSE-1KV-1A(DO-214AC)DO-214AC/1206"))
    )
    (comp (ref "D50")
      (value "1N5817.")
      (footprint "eagle-import:DO-214AC_SLIM")
      (libsource (lib "eagle-import") (part "DIODE-GEN-PURPOSE-1KV-1A(DO-214AC)DO-214AC/1206"))
    )
    (comp (ref "D51")
      (value "1N5817.")
      (footprint "eagle-import:DO-214AC_SLIM")
      (libsource (lib "eagle-import") (part "DIODE-GEN-PURPOSE-1KV-1A(DO-214AC)DO-214AC/1206"))
    )
    (comp (ref "D52")
      (value "1N5817")
      (footprint "eagle-import:DO-214AC_SLIM")
      (libsource (lib "eagle-import") (part "DIODE-GEN-PURPOSE-1KV-1A(DO-214AC)DO-214AC/1206"))
    )
    (comp (ref "D53")
      (value "1N4007.")
      (footprint "eagle-import:DO-214AC")
      (fields (field (name "MPN") "1N4007"))
      (libsource (lib "eagle-import") (part "DIODE-GEN-PURPOSE-1KV-1A(DO-214AC)"))
    )
    (comp (ref "D54")
      (value "1N4007")
      (footprint "eagle-import:DO-214AC")
      (libsource (lib "eagle-import") (part "DIODE-GEN-PURPOSE-1KV-1A(DO-214AC)"))
    )
    (comp (ref "D55")
      (value "Zen15")
      (footprint "eagle-import:DO214AA")
      (libsource (lib "eagle-import") (part "SM6T"))
    )
    (comp (ref "D56")
      (value "SM6TDO214AA_BI")
      (footprint "eagle-import:DO214AA_BI")
      (libsource (lib "eagle-import") (part "SM6TDO214AA_BI"))
    )
    (comp (ref "D57")
      (value "SS12")
      (footprint "eagle-import:DO-214AC_SLIM")
      (libsource (lib "eagle-import") (part "DIODE-GEN-PURPOSE-1KV-1A(DO-214AC)DO-214AC/1206"))
    )
    (comp (ref "D58")
      (value "SS12")
      (footprint "eagle-import:DO-214AC_SLIM")
      (libsource (lib "eagle-import") (part "DIODE-GEN-PURPOSE-1KV-1A(DO-214AC)DO-214AC/1206"))
    )
    (comp (ref "D59")
      (value "Zen11")
      (footprint "eagle-import:SOD-123_MINI-SMA")
      (libsource (lib "eagle-import") (part "CGRM400-G1"))
    )
    (comp (ref "FID15")
      (value "FIDUCIAL")
      (footprint "eagle-import:FIDUCIAL_1MM")
      (libsource (lib "eagle-import") (part "FIDUCIAL"))
    )
    (comp (ref "FID16")
      (value "FIDUCIAL")
      (footprint "eagle-import:FIDUCIAL_1MM")
      (libsource (lib "eagle-import") (part "FIDUCIAL"))
    )
    (comp (ref "FID17")
      (value "FIDUCIAL")
      (footprint "eagle-import:FIDUCIAL_1MM")
      (libsource (lib "eagle-import") (part "FIDUCIAL"))
    )
    (comp (ref "FID18")
      (value "FIDUCIAL")
      (footprint "eagle-import:FIDUCIAL_1MM")
      (libsource (lib "eagle-import") (part "FIDUCIAL"))
    )
    (comp (ref "IC28")
      (value "4028")
      (footprint "eagle-import:SO16")
      (libsource (lib "eagle-import") (part "4028D"))
    )
    (comp (ref "IC29")
      (value "317TO202H_NOHOLE")
      (footprint "eagle-import:TO220H_NOHOLE")
      (libsource (lib "eagle-import") (part "317TO202H_NOHOLE"))
    )
    (comp (ref "IC30")
      (value "ULN2004")
      (footprint "eagle-import:SO16")
      (libsource (lib "eagle-import") (part "ULN2004AD"))
    )
    (comp (ref "IC31")
      (value "LM339")
      (footprint "eagle-import:SO14")
      (libsource (lib "eagle-import") (part "LM339D"))
    )
    (comp (ref "IC32")
      (value "78L06")
      (footprint "eagle-import:SOT89_ROUND")
      (libsource (lib "eagle-import") (part "78LXXSOT89_ROUND"))
    )
    (comp (ref "IC33")
      (value "555")
      (footprint "eagle-import:SO08")
      (libsource (lib "eagle-import") (part "555DNE"))
    )
    (comp (ref "IC34")
      (value "4538")
      (footprint "eagle-import:SO16")
      (libsource (lib "eagle-import") (part "4538D"))
    )
    (comp (ref "IC35")
      (value "78L10")
      (footprint "eagle-import:SOT89_ROUND")
      (libsource (lib "eagle-import") (part "78LXXSOT89_ROUND"))
    )
    (comp (ref "IC36")
      (value "LM2904")
      (footprint "eagle-import:SO08")
      (libsource (lib "eagle-import") (part "LM358D"))
    )
    (comp (ref "JP16")
      (value "JP2EJP2_SMALLPADS")
      (footprint "eagle-import:JP2_SMALLPADS")
      (libsource (lib "eagle-import") (part "JP2EJP2_SMALLPADS"))
    )
    (comp (ref "JP17")
      (value "JP2E_ORIG")
      (footprint "eagle-import:JP2_ORIG_SMALLPADS")
      (libsource (lib "eagle-import") (part "JP2E_ORIG"))
    )
    (comp (ref "JP18")
      (value "JP2EJP2_SMALLPADS")
      (footprint "eagle-import:JP2_SMALLPADS")
      (libsource (lib "eagle-import") (part "JP2EJP2_SMALLPADS"))
    )
    (comp (ref "JP19")
      (value "JP2EJP2_SMALLPADS")
      (footprint "eagle-import:JP2_SMALLPADS")
      (libsource (lib "eagle-import") (part "JP2EJP2_SMALLPADS"))
    )
    (comp (ref "JP20")
      (value "JP2EJP2_SMALLPADS")
      (footprint "eagle-import:JP2_SMALLPADS")
      (libsource (lib "eagle-import") (part "JP2EJP2_SMALLPADS"))
    )
    (comp (ref "LED19")
      (value "LEDLD260")
      (footprint "eagle-import:LD260")
      (libsource (lib "eagle-import") (part "LEDLD260"))
    )
    (comp (ref "LED20")
      (value "LEDLD260")
      (footprint "eagle-import:LD260")
      (libsource (lib "eagle-import") (part "LEDLD260"))
    )
    (comp (ref "LED21")
      (value "LEDLD260")
      (footprint "eagle-import:LD260")
      (libsource (lib "eagle-import") (part "LEDLD260"))
    )
    (comp (ref "LED22")
      (value "LEDLD260")
      (footprint "eagle-import:LD260")
      (libsource (lib "eagle-import") (part "LEDLD260"))
    )
    (comp (ref "LED23")
      (value "LEDLD260")
      (footprint "eagle-import:LD260")
      (libsource (lib "eagle-import") (part "LEDLD260"))
    )
    (comp (ref "LED24")
      (value "LEDLD260")
      (footprint "eagle-import:LD260")
      (libsource (lib "eagle-import") (part "LEDLD260"))
    )
    (comp (ref "Q34")
      (value "BA")
      (footprint "eagle-import:SOT89")
      (libsource (lib "eagle-import") (part "PNP-TRANSISTOR_SOT89"))
    )
    (comp (ref "Q35")
      (value "BA.")
      (footprint "eagle-import:SOT89")
      (libsource (lib "eagle-import") (part "PNP-TRANSISTOR_SOT89"))
    )
    (comp (ref "Q36")
      (value "BA.")
      (footprint "eagle-import:SOT89")
      (libsource (lib "eagle-import") (part "PNP-TRANSISTOR_SOT89"))
    )
    (comp (ref "Q37")
      (value "BA")
      (footprint "eagle-import:SOT89")
      (libsource (lib "eagle-import") (part "PNP-TRANSISTOR_SOT89"))
    )
    (comp (ref "Q38")
      (value "MY")
      (footprint "eagle-import:SOT89")
      (libsource (lib "eagle-import") (part "NPN-TRANSISTOR_SOT89"))
    )
    (comp (ref "Q39")
      (value "J1")
      (footprint "eagle-import:SOT-23")
      (fields (field (name "MPN") "BSS138W-7-F"))
      (libsource (lib "eagle-import") (part "SMD-MOSFET-N-CH-50V-200MA-BSS138W-7-F(SOT-23)"))
    )
    (comp (ref "Q40")
      (value "J1")
      (footprint "eagle-import:SOT-23")
      (fields (field (name "MPN") "BSS138W-7-F"))
      (libsource (lib "eagle-import") (part "SMD-MOSFET-N-CH-50V-200MA-BSS138W-7-F(SOT-23)"))
    )
    (comp (ref "Q41")
      (value "J1")
      (footprint "eagle-import:SOT-23")
      (fields (field (name "MPN") "BSS138W-7-F"))
      (libsource (lib "eagle-import") (part "SMD-MOSFET-N-CH-50V-200MA-BSS138W-7-F(SOT-23)"))
    )
    (comp (ref "Q42")
      (value "BA")
      (footprint "eagle-import:SOT89")
      (libsource (lib "eagle-import") (part "PNP-TRANSISTOR_SOT89"))
    )
    (comp (ref "Q43")
      (value "J1")
      (footprint "eagle-import:SOT-23")
      (fields (field (name "MPN") "BSS138W-7-F"))
      (libsource (lib "eagle-import") (part "SMD-MOSFET-N-CH-50V-200MA-BSS138W-7-F(SOT-23)"))
    )
    (comp (ref "R221")
      (value "47")
      (footprint "eagle-import:V235_17_1MM")
      (libsource (lib "eagle-import") (part "R-EU_V235/17_1MM"))
    )
    (comp (ref "R222")
      (value "13")
      (footprint "eagle-import:R1206")
      (fields (field (name "MPN") "RC1206JR-0713RL"))
      (libsource (lib "eagle-import") (part "SMD-RES-13R-5%-1/4W(1206)"))
    )
    (comp (ref "R223")
      (value "47")
      (footprint "eagle-import:V235_17_1MM")
      (libsource (lib "eagle-import") (part "R-EU_V235/17_1MM"))
    )
    (comp (ref "R224")
      (value "104")
      (footprint "eagle-import:R0805")
      (fields (field (name "MPN") "RC0805FR-0710KL"))
      (libsource (lib "eagle-import") (part "SMD-RES-10K-1%-1/8W(0805)"))
    )
    (comp (ref "R225")
      (value "104")
      (footprint "eagle-import:R0805")
      (fields (field (name "MPN") "RC0805FR-0710KL"))
      (libsource (lib "eagle-import") (part "SMD-RES-10K-1%-1/8W(0805)"))
    )
    (comp (ref "R226")
      (value "104")
      (footprint "eagle-import:R0805")
      (fields (field (name "MPN") "RC0805FR-0710KL"))
      (libsource (lib "eagle-import") (part "SMD-RES-10K-1%-1/8W(0805)"))
    )
    (comp (ref "R227")
      (value "4701")
      (footprint "eagle-import:R0805")
      (fields (field (name "MPN") "RC0805JR-074K7L"))
      (libsource (lib "eagle-import") (part "SMD-RES-4.7K-5%-1/8W(0805)"))
    )
    (comp (ref "R228")
      (value "1002")
      (footprint "eagle-import:R0805")
      (fields (field (name "MPN") "RC0805FR-0710KL"))
      (libsource (lib "eagle-import") (part "SMD-RES-10K-1%-1/8W(0805)"))
    )
    (comp (ref "R229")
      (value "1002")
      (footprint "eagle-import:R0805")
      (fields (field (name "MPN") "RC0805FR-0710KL"))
      (libsource (lib "eagle-import") (part "SMD-RES-10K-1%-1/8W(0805)"))
    )
    (comp (ref "R230")
      (value "1502")
      (footprint "eagle-import:R0805")
      (fields (field (name "MPN") "RC0805FR-0710KL"))
      (libsource (lib "eagle-import") (part "SMD-RES-10K-1%-1/8W(0805)"))
    )
    (comp (ref "R231")
      (value "104")
      (footprint "eagle-import:R0805")
      (fields (field (name "MPN") "RC0805FR-0710KL"))
      (libsource (lib "eagle-import") (part "SMD-RES-10K-1%-1/8W(0805)"))
    )
    (comp (ref "R232")
      (value "104")
      (footprint "eagle-import:R0805")
      (fields (field (name "MPN") "RC0805FR-0710KL"))
      (libsource (lib "eagle-import") (part "SMD-RES-10K-1%-1/8W(0805)"))
    )
    (comp (ref "R233")
      (value "1502")
      (footprint "eagle-import:R0805")
      (fields (field (name "MPN") "RC0805FR-0710KL"))
      (libsource (lib "eagle-import") (part "SMD-RES-10K-1%-1/8W(0805)"))
    )
    (comp (ref "R234")
      (value "1002")
      (footprint "eagle-import:R0805")
      (fields (field (name "MPN") "RC0805FR-0710KL"))
      (libsource (lib "eagle-import") (part "SMD-RES-10K-1%-1/8W(0805)"))
    )
    (comp (ref "R235")
      (value "2201")
      (footprint "eagle-import:R0805")
      (fields (field (name "MPN") "RC0805JR-072K2L"))
      (libsource (lib "eagle-import") (part "SMD-RES-2.2K-5%-1/8W(0805)"))
    )
    (comp (ref "R236")
      (value "1002")
      (footprint "eagle-import:R0805")
      (fields (field (name "MPN") "RC0805FR-0710KL"))
      (libsource (lib "eagle-import") (part "SMD-RES-10K-1%-1/8W(0805)"))
    )
    (comp (ref "R237")
      (value "4701")
      (footprint "eagle-import:R0805")
      (fields (field (name "MPN") "RC0805JR-074K7L"))
      (libsource (lib "eagle-import") (part "SMD-RES-4.7K-5%-1/8W(0805)"))
    )
    (comp (ref "R238")
      (value "2702")
      (footprint "eagle-import:R0805")
      (fields (field (name "MPN") "RC0805JR-074K7L"))
      (libsource (lib "eagle-import") (part "SMD-RES-4.7K-5%-1/8W(0805)"))
    )
    (comp (ref "R239")
      (value "102")
      (footprint "eagle-import:R0805")
      (fields (field (name "MPN") "RC0805JR-071KL"))
      (libsource (lib "eagle-import") (part "SMD-RES-1K-5%-1/8W(0805)"))
    )
    (comp (ref "R240")
      (value "R_user")
      (footprint "eagle-import:R0805")
      (libsource (lib "eagle-import") (part "R-EU_R0805"))
    )
    (comp (ref "R241")
      (value "102")
      (footprint "eagle-import:R0805")
      (fields (field (name "MPN") "RC0805JR-07220RL"))
      (libsource (lib "eagle-import") (part "SMD-RES-220R-5%-1/8W(0805)"))
    )
    (comp (ref "R242")
      (value "(101)")
      (footprint "eagle-import:R0805")
      (fields (field (name "MPN") "RC0805JR-07100RL"))
      (libsource (lib "eagle-import") (part "SMD-RES-100R-5%-1/8W(0805)"))
    )
    (comp (ref "R243")
      (value "(1000)")
      (footprint "eagle-import:R0805")
      (fields (field (name "MPN") "RC0805JR-07100RL"))
      (libsource (lib "eagle-import") (part "SMD-RES-100R-5%-1/8W(0805)"))
    )
    (comp (ref "R244")
      (value "102")
      (footprint "eagle-import:R0805")
      (fields (field (name "MPN") "RC0805JR-071KL"))
      (libsource (lib "eagle-import") (part "SMD-RES-1K-5%-1/8W(0805)"))
    )
    (comp (ref "R245")
      (value "13")
      (footprint "eagle-import:R1206")
      (fields (field (name "MPN") "RC1206JR-0713RL"))
      (libsource (lib "eagle-import") (part "SMD-RES-13R-5%-1/4W(1206)"))
    )
    (comp (ref "R246")
      (value "13")
      (footprint "eagle-import:R1206")
      (fields (field (name "MPN") "RC1206JR-0713RL"))
      (libsource (lib "eagle-import") (part "SMD-RES-13R-5%-1/4W(1206)"))
    )
    (comp (ref "R247")
      (value "2702")
      (footprint "eagle-import:R0805")
      (fields (field (name "MPN") "RC0805JR-074K7L"))
      (libsource (lib "eagle-import") (part "SMD-RES-4.7K-5%-1/8W(0805)"))
    )
    (comp (ref "R248")
      (value "4701")
      (footprint "eagle-import:R0805")
      (fields (field (name "MPN") "RC0805JR-074K7L"))
      (libsource (lib "eagle-import") (part "SMD-RES-4.7K-5%-1/8W(0805)"))
    )
    (comp (ref "R249")
      (value "100")
      (footprint "eagle-import:R0805")
      (fields (field (name "MPN") "RC0805JR-072K2L"))
      (libsource (lib "eagle-import") (part "SMD-RES-2.2K-5%-1/8W(0805)"))
    )
    (comp (ref "R250")
      (value "104")
      (footprint "eagle-import:R0805")
      (fields (field (name "MPN") "RC0805FR-0710KL"))
      (libsource (lib "eagle-import") (part "SMD-RES-10K-1%-1/8W(0805)"))
    )
    (comp (ref "R251")
      (value "104")
      (footprint "eagle-import:R0805")
      (fields (field (name "MPN") "RC0805FR-0710KL"))
      (libsource (lib "eagle-import") (part "SMD-RES-10K-1%-1/8W(0805)"))
    )
    (comp (ref "R252")
      (value "(1002)")
      (footprint "eagle-import:R0805")
      (fields (field (name "MPN") "RC0805FR-0710KL"))
      (libsource (lib "eagle-import") (part "SMD-RES-10K-1%-1/8W(0805)"))
    )
    (comp (ref "R253")
      (value "2702")
      (footprint "eagle-import:R0805")
      (fields (field (name "MPN") "RC0805FR-0710KL"))
      (libsource (lib "eagle-import") (part "SMD-RES-10K-1%-1/8W(0805)"))
    )
    (comp (ref "R254")
      (value "47")
      (footprint "eagle-import:V235_17_1MM")
      (libsource (lib "eagle-import") (part "R-EU_V235/17_1MM"))
    )
    (comp (ref "R255")
      (value "47")
      (footprint "eagle-import:V235_17_1MM")
      (libsource (lib "eagle-import") (part "R-EU_V235/17_1MM"))
    )
    (comp (ref "R256")
      (value "2702")
      (footprint "eagle-import:R0805")
      (fields (field (name "MPN") "RC0805JR-074K7L"))
      (libsource (lib "eagle-import") (part "SMD-RES-4.7K-5%-1/8W(0805)"))
    )
    (comp (ref "R257")
      (value "2201")
      (footprint "eagle-import:R0805")
      (fields (field (name "MPN") "RC0805JR-072K2L"))
      (libsource (lib "eagle-import") (part "SMD-RES-2.2K-5%-1/8W(0805)"))
    )
    (comp (ref "R258")
      (value "1002")
      (footprint "eagle-import:R0805")
      (fields (field (name "MPN") "RC0805JR-074K7L"))
      (libsource (lib "eagle-import") (part "SMD-RES-4.7K-5%-1/8W(0805)"))
    )
    (comp (ref "R259")
      (value "1002")
      (footprint "eagle-import:R0805")
      (fields (field (name "MPN") "RC0805FR-0710KL"))
      (libsource (lib "eagle-import") (part "SMD-RES-10K-1%-1/8W(0805)"))
    )
    (comp (ref "R260")
      (value "102")
      (footprint "eagle-import:R0805")
      (fields (field (name "MPN") "RC0805JR-071KL"))
      (libsource (lib "eagle-import") (part "SMD-RES-1K-5%-1/8W(0805)"))
    )
    (comp (ref "R261")
      (value "2702")
      (footprint "eagle-import:R0805")
      (fields (field (name "MPN") "RC0805JR-074K7L"))
      (libsource (lib "eagle-import") (part "SMD-RES-4.7K-5%-1/8W(0805)"))
    )
    (comp (ref "R262")
      (value "1002")
      (footprint "eagle-import:R0805")
      (fields (field (name "MPN") "RC0805JR-071KL"))
      (libsource (lib "eagle-import") (part "SMD-RES-1K-5%-1/8W(0805)"))
    )
    (comp (ref "R263")
      (value "1002")
      (footprint "eagle-import:R0805")
      (fields (field (name "MPN") "RC0805JR-071KL"))
      (libsource (lib "eagle-import") (part "SMD-RES-1K-5%-1/8W(0805)"))
    )
    (comp (ref "R264")
      (value "R_user")
      (footprint "eagle-import:R0805")
      (libsource (lib "eagle-import") (part "R-EU_R0805"))
    )
    (comp (ref "R265")
      (value "104")
      (footprint "eagle-import:R0805")
      (fields (field (name "MPN") "RC0805FR-0710KL"))
      (libsource (lib "eagle-import") (part "SMD-RES-10K-1%-1/8W(0805)"))
    )
    (comp (ref "R266")
      (value "104")
      (footprint "eagle-import:R0805")
      (fields (field (name "MPN") "RC0805FR-0710KL"))
      (libsource (lib "eagle-import") (part "SMD-RES-10K-1%-1/8W(0805)"))
    )
    (comp (ref "R267")
      (value "104")
      (footprint "eagle-import:R0805")
      (fields (field (name "MPN") "RC0805FR-0710KL"))
      (libsource (lib "eagle-import") (part "SMD-RES-10K-1%-1/8W(0805)"))
    )
    (comp (ref "R268")
      (value "13")
      (footprint "eagle-import:R1206")
      (fields (field (name "MPN") "RC1206JR-0713RL"))
      (libsource (lib "eagle-import") (part "SMD-RES-13R-5%-1/4W(1206)"))
    )
    (comp (ref "R269")
      (value "2201")
      (footprint "eagle-import:R0805")
      (fields (field (name "MPN") "RC0805JR-071KL"))
      (libsource (lib "eagle-import") (part "SMD-RES-1K-5%-1/8W(0805)"))
    )
    (comp (ref "R270")
      (value "100")
      (footprint "eagle-import:R0805")
      (fields (field (name "MPN") "RC0805JR-07220RL"))
      (libsource (lib "eagle-import") (part "SMD-RES-220R-5%-1/8W(0805)"))
    )
    (comp (ref "R271")
      (value "13")
      (footprint "eagle-import:R1206")
      (fields (field (name "MPN") "RC1206JR-0713RL"))
      (libsource (lib "eagle-import") (part "SMD-RES-13R-5%-1/4W(1206)"))
    )
    (comp (ref "R272")
      (value "4701")
      (footprint "eagle-import:R0805")
      (fields (field (name "MPN") "RC0805JR-074K7L"))
      (libsource (lib "eagle-import") (part "SMD-RES-4.7K-5%-1/8W(0805)"))
    )
    (comp (ref "R273")
      (value "104")
      (footprint "eagle-import:R0805")
      (fields (field (name "MPN") "RC0805JR-074K7L"))
      (libsource (lib "eagle-import") (part "SMD-RES-4.7K-5%-1/8W(0805)"))
    )
    (comp (ref "R274")
      (value "100")
      (footprint "eagle-import:R0805")
      (fields (field (name "MPN") "RC0805JR-072K2L"))
      (libsource (lib "eagle-import") (part "SMD-RES-2.2K-5%-1/8W(0805)"))
    )
    (comp (ref "R275")
      (value "100")
      (footprint "eagle-import:R0805")
      (fields (field (name "MPN") "RC0805JR-072K2L"))
      (libsource (lib "eagle-import") (part "SMD-RES-2.2K-5%-1/8W(0805)"))
    )
    (comp (ref "SJ8")
      (value "SJ")
      (footprint "eagle-import:SJ")
      (libsource (lib "eagle-import") (part "solder-jumper_SJ"))
    )
    (comp (ref "SJ9") (value "SJ") (footprint "eagle-import:SJ") (libsource (lib "eagle-import") (part "SJ")))
    (comp (ref "START4")
      (value "TPSB2.0")
      (footprint "eagle-import:B2.0")
      (libsource (lib "eagle-import") (part "TPSB2.0"))
    )
    (comp (ref "TP93")
      (value "TPSB2.0")
      (footprint "eagle-import:B2.0")
      (libsource (lib "eagle-import") (part "TPSB2.0"))
    )
    (comp (ref "TP94")
      (value "TPSB2.0")
      (footprint "eagle-import:B2.0")
      (libsource (lib "eagle-import") (part "TPSB2.0"))
    )
    (comp (ref "TP95")
      (value "TPSB2.0")
      (footprint "eagle-import:B2.0")
      (libsource (lib "eagle-import") (part "TPSB2.0"))
    )
    (comp (ref "TP96")
      (value "TPSB2.0")
      (footprint "eagle-import:B2.0")
      (libsource (lib "eagle-import") (part "TPSB2.0"))
    )
    (comp (ref "TP97")
      (value "TPSB2.0")
      (footprint "eagle-import:B2.0")
      (libsource (lib "eagle-import") (part "TPSB2.0"))
    )
    (comp (ref "TP98")
      (value "TPSB2.0")
      (footprint "eagle-import:B2.0")
      (libsource (lib "eagle-import") (part "TPSB2.0"))
    )
    (comp (ref "TP99")
      (value "TPSB2.0")
      (footprint "eagle-import:B2.0")
      (libsource (lib "eagle-import") (part "TPSB2.0"))
    )
    (comp (ref "TP100")
      (value "TPSB2.0")
      (footprint "eagle-import:B2.0")
      (libsource (lib "eagle-import") (part "TPSB2.0"))
    )
    (comp (ref "TP101")
      (value "TPSB2.0")
      (footprint "eagle-import:B2.0")
      (libsource (lib "eagle-import") (part "TPSB2.0"))
    )
    (comp (ref "TP102")
      (value "TPSB2.0")
      (footprint "eagle-import:B2.0")
      (libsource (lib "eagle-import") (part "TPSB2.0"))
    )
    (comp (ref "TP103")
      (value "TPSB2.0")
      (footprint "eagle-import:B2.0")
      (libsource (lib "eagle-import") (part "TPSB2.0"))
    )
    (comp (ref "TP104")
      (value "TPSB2.0")
      (footprint "eagle-import:B2.0")
      (libsource (lib "eagle-import") (part "TPSB2.0"))
    )
    (comp (ref "TP105")
      (value "TPSB2.0")
      (footprint "eagle-import:B2.0")
      (libsource (lib "eagle-import") (part "TPSB2.0"))
    )
    (comp (ref "TP106")
      (value "TPSB2.0")
      (footprint "eagle-import:B2.0")
      (libsource (lib "eagle-import") (part "TPSB2.0"))
    )
    (comp (ref "TP107")
      (value "TPSB2.0")
      (footprint "eagle-import:B2.0")
      (libsource (lib "eagle-import") (part "TPSB2.0"))
    )
    (comp (ref "TP108")
      (value "TPSB2.0")
      (footprint "eagle-import:B2.0")
      (libsource (lib "eagle-import") (part "TPSB2.0"))
    )
    (comp (ref "TP109")
      (value "TPSB2.0")
      (footprint "eagle-import:B2.0")
      (libsource (lib "eagle-import") (part "TPSB2.0"))
    )
    (comp (ref "TP110")
      (value "TPSB2.0")
      (footprint "eagle-import:B2.0")
      (libsource (lib "eagle-import") (part "TPSB2.0"))
    )
    (comp (ref "TP111")
      (value "TPSB1,27")
      (footprint "eagle-import:B1,27")
      (libsource (lib "eagle-import") (part "TPSB1,27"))
    )
    (comp (ref "TP112")
      (value "TPSB2.0")
      (footprint "eagle-import:B2.0")
      (libsource (lib "eagle-import") (part "TPSB2.0"))
    )
    (comp (ref "TP113")
      (value "TPSB2.0")
      (footprint "eagle-import:B2.0")
      (libsource (lib "eagle-import") (part "TPSB2.0"))
    )
    (comp (ref "TP114")
      (value "TPSB2.0")
      (footprint "eagle-import:B2.0")
      (libsource (lib "eagle-import") (part "TPSB2.0"))
    )
    (comp (ref "TP115")
      (value "TPSB2.0")
      (footprint "eagle-import:B2.0")
      (libsource (lib "eagle-import") (part "TPSB2.0"))
    )
    (comp (ref "X10")
      (value "CON_BMWV2")
      (footprint "eagle-import:24-PIN_V2")
      (libsource (lib "eagle-import") (part "CON_BMWV2"))
    )
    (comp (ref "X11")
      (value "22-23-2051")
      (footprint "eagle-import:22-23-2051")
      (fields (field (name "MF") "MOLEX"))
      (libsource (lib "eagle-import") (part "22-23-2051"))
    )
    (comp (ref "X12")
      (value "22-23-2021")
      (footprint "eagle-import:22-23-2021")
      (fields (field (name "MF") "MOLEX"))
      (libsource (lib "eagle-import") (part "22-23-2021"))
    )
    (comp (ref "6V5")
      (value "TPSB2.0")
      (footprint "eagle-import:B2.0")
      (libsource (lib "eagle-import") (part "TPSB2.0"))
    )
    (comp (ref "10V5")
      (value "TPSB2.0")
      (footprint "eagle-import:B2.0")
      (libsource (lib "eagle-import") (part "TPSB2.0"))
    )
    (comp (ref "11")
      (value "2081-1132")
      (footprint "eagle-import:12-PIN")
      (libsource (lib "eagle-import") (part "2081-1132"))
    )
    (comp (ref "12")
      (value "2081-1132")
      (footprint "eagle-import:12-PIN")
      (libsource (lib "eagle-import") (part "2081-1132"))
    )
    (comp (ref "C51")
      (value "100u")
      (footprint "eagle-import:C1206")
      (fields (field (name "MPN") "GRM31CR60J107ME39L"))
      (libsource (lib "eagle-import") (part "CERAMIC-100UF-6.3V-20%-X5R(1206)"))
    )
    (comp (ref "C52")
      (value "100u")
      (footprint "eagle-import:C1206")
      (fields (field (name "MPN") "GRM31CR60J107ME39L"))
      (libsource (lib "eagle-import") (part "CERAMIC-100UF-6.3V-20%-X5R(1206)"))
    )
    (comp (ref "C53")
      (value "100nF,")
      (footprint "eagle-import:C0805")
      (fields (field (name "MPN") "CC0805KRX7R9BB104"))
      (libsource (lib "eagle-import") (part "CERAMIC-100NF-50V-10%-X7R(0805)"))
    )
    (comp (ref "C54")
      (value "4.7u")
      (footprint "eagle-import:C0805")
      (fields (field (name "MPN") "CC0805KKX5R8BB475"))
      (libsource (lib "eagle-import") (part "CERAMIC-4.7UF-25V-10%-X5R(0805)"))
    )
    (comp (ref "C55")
      (value "100nF.")
      (footprint "eagle-import:C0805")
      (fields (field (name "MPN") "CC0805KRX7R9BB104"))
      (libsource (lib "eagle-import") (part "CERAMIC-100NF-50V-10%-X7R(0805)"))
    )
    (comp (ref "C56")
      (value "100nF.")
      (footprint "eagle-import:C0805")
      (fields (field (name "MPN") "CC0805KRX7R9BB104"))
      (libsource (lib "eagle-import") (part "CERAMIC-100NF-50V-10%-X7R(0805)"))
    )
    (comp (ref "C57")
      (value "2.2nF")
      (footprint "eagle-import:C0805")
      (fields (field (name "MPN") "CC0805KRX7R9BB104"))
      (libsource (lib "eagle-import") (part "CERAMIC-100NF-50V-10%-X7R(0805)"))
    )
    (comp (ref "C58")
      (value "100nF")
      (footprint "eagle-import:C0805")
      (fields (field (name "MPN") "CC0805KRX7R9BB104"))
      (libsource (lib "eagle-import") (part "CERAMIC-100NF-50V-10%-X7R(0805)"))
    )
    (comp (ref "C59")
      (value "100nF")
      (footprint "eagle-import:C0805")
      (fields (field (name "MPN") "CC0805KRX7R9BB104"))
      (libsource (lib "eagle-import") (part "CERAMIC-100NF-50V-10%-X7R(0805)"))
    )
    (comp (ref "C60")
      (value "100nF,")
      (footprint "eagle-import:C0805")
      (fields (field (name "MPN") "CC0805KRX7R9BB104"))
      (libsource (lib "eagle-import") (part "CERAMIC-100NF-50V-10%-X7R(0805)"))
    )
    (comp (ref "C61")
      (value "4.7u")
      (footprint "eagle-import:C0805")
      (fields (field (name "MPN") "CC0805KKX5R8BB475"))
      (libsource (lib "eagle-import") (part "CERAMIC-4.7UF-25V-10%-X5R(0805)"))
    )
    (comp (ref "C62")
      (value "10u")
      (footprint "eagle-import:C1206")
      (fields (field (name "MPN") "GRM31CR60J107ME39L"))
      (libsource (lib "eagle-import") (part "CERAMIC-100UF-6.3V-20%-X5R(1206)"))
    )
    (comp (ref "D60")
      (value "1N4007,")
      (footprint "eagle-import:DO-214AC")
      (fields (field (name "MPN") "1N4007"))
      (libsource (lib "eagle-import") (part "DIODE-GEN-PURPOSE-1KV-1A(DO-214AC)"))
    )
    (comp (ref "D61")
      (value "1N4007,")
      (footprint "eagle-import:DO-214AC")
      (fields (field (name "MPN") "1N4007"))
      (libsource (lib "eagle-import") (part "DIODE-GEN-PURPOSE-1KV-1A(DO-214AC)"))
    )
    (comp (ref "D62")
      (value "1N4007.")
      (footprint "eagle-import:DO-214AC")
      (fields (field (name "MPN") "1N4007"))
      (libsource (lib "eagle-import") (part "DIODE-GEN-PURPOSE-1KV-1A(DO-214AC)"))
    )
    (comp (ref "D63")
      (value "1N5817")
      (footprint "eagle-import:DO-214AC_SLIM")
      (libsource (lib "eagle-import") (part "DIODE-GEN-PURPOSE-1KV-1A(DO-214AC)DO-214AC/1206"))
    )
    (comp (ref "D64")
      (value "1N5817.")
      (footprint "eagle-import:DO-214AC_SLIM")
      (libsource (lib "eagle-import") (part "DIODE-GEN-PURPOSE-1KV-1A(DO-214AC)DO-214AC/1206"))
    )
    (comp (ref "D65")
      (value "1N5817.")
      (footprint "eagle-import:DO-214AC_SLIM")
      (libsource (lib "eagle-import") (part "DIODE-GEN-PURPOSE-1KV-1A(DO-214AC)DO-214AC/1206"))
    )
    (comp (ref "D66")
      (value "1N5817")
      (footprint "eagle-import:DO-214AC_SLIM")
      (libsource (lib "eagle-import") (part "DIODE-GEN-PURPOSE-1KV-1A(DO-214AC)DO-214AC/1206"))
    )
    (comp (ref "D67")
      (value "1N4007.")
      (footprint "eagle-import:DO-214AC")
      (fields (field (name "MPN") "1N4007"))
      (libsource (lib "eagle-import") (part "DIODE-GEN-PURPOSE-1KV-1A(DO-214AC)"))
    )
    (comp (ref "D68")
      (value "1N4007")
      (footprint "eagle-import:DO-214AC")
      (libsource (lib "eagle-import") (part "DIODE-GEN-PURPOSE-1KV-1A(DO-214AC)"))
    )
    (comp (ref "D69")
      (value "Zen15")
      (footprint "eagle-import:DO214AA")
      (libsource (lib "eagle-import") (part "SM6T"))
    )
    (comp (ref "D70")
      (value "SM6TDO214AA_BI")
      (footprint "eagle-import:DO214AA_BI")
      (libsource (lib "eagle-import") (part "SM6TDO214AA_BI"))
    )
    (comp (ref "D71")
      (value "SS12")
      (footprint "eagle-import:DO-214AC_SLIM")
      (libsource (lib "eagle-import") (part "DIODE-GEN-PURPOSE-1KV-1A(DO-214AC)DO-214AC/1206"))
    )
    (comp (ref "D72")
      (value "SS12")
      (footprint "eagle-import:DO-214AC_SLIM")
      (libsource (lib "eagle-import") (part "DIODE-GEN-PURPOSE-1KV-1A(DO-214AC)DO-214AC/1206"))
    )
    (comp (ref "D73")
      (value "Zen11")
      (footprint "eagle-import:SOD-123_MINI-SMA")
      (libsource (lib "eagle-import") (part "CGRM400-G1"))
    )
    (comp (ref "FID19")
      (value "FIDUCIAL")
      (footprint "eagle-import:FIDUCIAL_1MM")
      (libsource (lib "eagle-import") (part "FIDUCIAL"))
    )
    (comp (ref "FID20")
      (value "FIDUCIAL")
      (footprint "eagle-import:FIDUCIAL_1MM")
      (libsource (lib "eagle-import") (part "FIDUCIAL"))
    )
    (comp (ref "FID21")
      (value "FIDUCIAL")
      (footprint "eagle-import:FIDUCIAL_1MM")
      (libsource (lib "eagle-import") (part "FIDUCIAL"))
    )
    (comp (ref "FID22")
      (value "FIDUCIAL")
      (footprint "eagle-import:FIDUCIAL_1MM")
      (libsource (lib "eagle-import") (part "FIDUCIAL"))
    )
    (comp (ref "IC37")
      (value "4028")
      (footprint "eagle-import:SO16")
      (libsource (lib "eagle-import") (part "4028D"))
    )
    (comp (ref "IC38")
      (value "317TO202H_NOHOLE")
      (footprint "eagle-import:TO220H_NOHOLE")
      (libsource (lib "eagle-import") (part "317TO202H_NOHOLE"))
    )
    (comp (ref "IC39")
      (value "ULN2004")
      (footprint "eagle-import:SO16")
      (libsource (lib "eagle-import") (part "ULN2004AD"))
    )
    (comp (ref "IC40")
      (value "LM339")
      (footprint "eagle-import:SO14")
      (libsource (lib "eagle-import") (part "LM339D"))
    )
    (comp (ref "IC41")
      (value "78L06")
      (footprint "eagle-import:SOT89_ROUND")
      (libsource (lib "eagle-import") (part "78LXXSOT89_ROUND"))
    )
    (comp (ref "IC42")
      (value "555")
      (footprint "eagle-import:SO08")
      (libsource (lib "eagle-import") (part "555DNE"))
    )
    (comp (ref "IC43")
      (value "4538")
      (footprint "eagle-import:SO16")
      (libsource (lib "eagle-import") (part "4538D"))
    )
    (comp (ref "IC44")
      (value "78L10")
      (footprint "eagle-import:SOT89_ROUND")
      (libsource (lib "eagle-import") (part "78LXXSOT89_ROUND"))
    )
    (comp (ref "IC45")
      (value "LM2904")
      (footprint "eagle-import:SO08")
      (libsource (lib "eagle-import") (part "LM358D"))
    )
    (comp (ref "JP21")
      (value "JP2EJP2_SMALLPADS")
      (footprint "eagle-import:JP2_SMALLPADS")
      (libsource (lib "eagle-import") (part "JP2EJP2_SMALLPADS"))
    )
    (comp (ref "JP22")
      (value "JP2E_ORIG")
      (footprint "eagle-import:JP2_ORIG_SMALLPADS")
      (libsource (lib "eagle-import") (part "JP2E_ORIG"))
    )
    (comp (ref "JP23")
      (value "JP2EJP2_SMALLPADS")
      (footprint "eagle-import:JP2_SMALLPADS")
      (libsource (lib "eagle-import") (part "JP2EJP2_SMALLPADS"))
    )
    (comp (ref "JP24")
      (value "JP2EJP2_SMALLPADS")
      (footprint "eagle-import:JP2_SMALLPADS")
      (libsource (lib "eagle-import") (part "JP2EJP2_SMALLPADS"))
    )
    (comp (ref "JP25")
      (value "JP2EJP2_SMALLPADS")
      (footprint "eagle-import:JP2_SMALLPADS")
      (libsource (lib "eagle-import") (part "JP2EJP2_SMALLPADS"))
    )
    (comp (ref "LED25")
      (value "LEDLD260")
      (footprint "eagle-import:LD260")
      (libsource (lib "eagle-import") (part "LEDLD260"))
    )
    (comp (ref "LED26")
      (value "LEDLD260")
      (footprint "eagle-import:LD260")
      (libsource (lib "eagle-import") (part "LEDLD260"))
    )
    (comp (ref "LED27")
      (value "LEDLD260")
      (footprint "eagle-import:LD260")
      (libsource (lib "eagle-import") (part "LEDLD260"))
    )
    (comp (ref "LED28")
      (value "LEDLD260")
      (footprint "eagle-import:LD260")
      (libsource (lib "eagle-import") (part "LEDLD260"))
    )
    (comp (ref "LED29")
      (value "LEDLD260")
      (footprint "eagle-import:LD260")
      (libsource (lib "eagle-import") (part "LEDLD260"))
    )
    (comp (ref "LED30")
      (value "LEDLD260")
      (footprint "eagle-import:LD260")
      (libsource (lib "eagle-import") (part "LEDLD260"))
    )
    (comp (ref "Q44")
      (value "BA")
      (footprint "eagle-import:SOT89")
      (libsource (lib "eagle-import") (part "PNP-TRANSISTOR_SOT89"))
    )
    (comp (ref "Q45")
      (value "BA.")
      (footprint "eagle-import:SOT89")
      (libsource (lib "eagle-import") (part "PNP-TRANSISTOR_SOT89"))
    )
    (comp (ref "Q46")
      (value "BA.")
      (footprint "eagle-import:SOT89")
      (libsource (lib "eagle-import") (part "PNP-TRANSISTOR_SOT89"))
    )
    (comp (ref "Q47")
      (value "BA")
      (footprint "eagle-import:SOT89")
      (libsource (lib "eagle-import") (part "PNP-TRANSISTOR_SOT89"))
    )
    (comp (ref "Q48")
      (value "MY")
      (footprint "eagle-import:SOT89")
      (libsource (lib "eagle-import") (part "NPN-TRANSISTOR_SOT89"))
    )
    (comp (ref "Q49")
      (value "J1")
      (footprint "eagle-import:SOT-23")
      (fields (field (name "MPN") "BSS138W-7-F"))
      (libsource (lib "eagle-import") (part "SMD-MOSFET-N-CH-50V-200MA-BSS138W-7-F(SOT-23)"))
    )
    (comp (ref "Q50")
      (value "J1")
      (footprint "eagle-import:SOT-23")
      (fields (field (name "MPN") "BSS138W-7-F"))
      (libsource (lib "eagle-import") (part "SMD-MOSFET-N-CH-50V-200MA-BSS138W-7-F(SOT-23)"))
    )
    (comp (ref "Q51")
      (value "J1")
      (footprint "eagle-import:SOT-23")
      (fields (field (name "MPN") "BSS138W-7-F"))
      (libsource (lib "eagle-import") (part "SMD-MOSFET-N-CH-50V-200MA-BSS138W-7-F(SOT-23)"))
    )
    (comp (ref "Q52")
      (value "BA")
      (footprint "eagle-import:SOT89")
      (libsource (lib "eagle-import") (part "PNP-TRANSISTOR_SOT89"))
    )
    (comp (ref "Q53")
      (value "J1")
      (footprint "eagle-import:SOT-23")
      (fields (field (name "MPN") "BSS138W-7-F"))
      (libsource (lib "eagle-import") (part "SMD-MOSFET-N-CH-50V-200MA-BSS138W-7-F(SOT-23)"))
    )
    (comp (ref "R276")
      (value "47")
      (footprint "eagle-import:V235_17_1MM")
      (libsource (lib "eagle-import") (part "R-EU_V235/17_1MM"))
    )
    (comp (ref "R277")
      (value "13")
      (footprint "eagle-import:R1206")
      (fields (field (name "MPN") "RC1206JR-0713RL"))
      (libsource (lib "eagle-import") (part "SMD-RES-13R-5%-1/4W(1206)"))
    )
    (comp (ref "R278")
      (value "47")
      (footprint "eagle-import:V235_17_1MM")
      (libsource (lib "eagle-import") (part "R-EU_V235/17_1MM"))
    )
    (comp (ref "R279")
      (value "104")
      (footprint "eagle-import:R0805")
      (fields (field (name "MPN") "RC0805FR-0710KL"))
      (libsource (lib "eagle-import") (part "SMD-RES-10K-1%-1/8W(0805)"))
    )
    (comp (ref "R280")
      (value "104")
      (footprint "eagle-import:R0805")
      (fields (field (name "MPN") "RC0805FR-0710KL"))
      (libsource (lib "eagle-import") (part "SMD-RES-10K-1%-1/8W(0805)"))
    )
    (comp (ref "R281")
      (value "104")
      (footprint "eagle-import:R0805")
      (fields (field (name "MPN") "RC0805FR-0710KL"))
      (libsource (lib "eagle-import") (part "SMD-RES-10K-1%-1/8W(0805)"))
    )
    (comp (ref "R282")
      (value "4701")
      (footprint "eagle-import:R0805")
      (fields (field (name "MPN") "RC0805JR-074K7L"))
      (libsource (lib "eagle-import") (part "SMD-RES-4.7K-5%-1/8W(0805)"))
    )
    (comp (ref "R283")
      (value "1002")
      (footprint "eagle-import:R0805")
      (fields (field (name "MPN") "RC0805FR-0710KL"))
      (libsource (lib "eagle-import") (part "SMD-RES-10K-1%-1/8W(0805)"))
    )
    (comp (ref "R284")
      (value "1002")
      (footprint "eagle-import:R0805")
      (fields (field (name "MPN") "RC0805FR-0710KL"))
      (libsource (lib "eagle-import") (part "SMD-RES-10K-1%-1/8W(0805)"))
    )
    (comp (ref "R285")
      (value "1502")
      (footprint "eagle-import:R0805")
      (fields (field (name "MPN") "RC0805FR-0710KL"))
      (libsource (lib "eagle-import") (part "SMD-RES-10K-1%-1/8W(0805)"))
    )
    (comp (ref "R286")
      (value "104")
      (footprint "eagle-import:R0805")
      (fields (field (name "MPN") "RC0805FR-0710KL"))
      (libsource (lib "eagle-import") (part "SMD-RES-10K-1%-1/8W(0805)"))
    )
    (comp (ref "R287")
      (value "104")
      (footprint "eagle-import:R0805")
      (fields (field (name "MPN") "RC0805FR-0710KL"))
      (libsource (lib "eagle-import") (part "SMD-RES-10K-1%-1/8W(0805)"))
    )
    (comp (ref "R288")
      (value "1502")
      (footprint "eagle-import:R0805")
      (fields (field (name "MPN") "RC0805FR-0710KL"))
      (libsource (lib "eagle-import") (part "SMD-RES-10K-1%-1/8W(0805)"))
    )
    (comp (ref "R289")
      (value "1002")
      (footprint "eagle-import:R0805")
      (fields (field (name "MPN") "RC0805FR-0710KL"))
      (libsource (lib "eagle-import") (part "SMD-RES-10K-1%-1/8W(0805)"))
    )
    (comp (ref "R290")
      (value "2201")
      (footprint "eagle-import:R0805")
      (fields (field (name "MPN") "RC0805JR-072K2L"))
      (libsource (lib "eagle-import") (part "SMD-RES-2.2K-5%-1/8W(0805)"))
    )
    (comp (ref "R291")
      (value "1002")
      (footprint "eagle-import:R0805")
      (fields (field (name "MPN") "RC0805FR-0710KL"))
      (libsource (lib "eagle-import") (part "SMD-RES-10K-1%-1/8W(0805)"))
    )
    (comp (ref "R292")
      (value "4701")
      (footprint "eagle-import:R0805")
      (fields (field (name "MPN") "RC0805JR-074K7L"))
      (libsource (lib "eagle-import") (part "SMD-RES-4.7K-5%-1/8W(0805)"))
    )
    (comp (ref "R293")
      (value "2702")
      (footprint "eagle-import:R0805")
      (fields (field (name "MPN") "RC0805JR-074K7L"))
      (libsource (lib "eagle-import") (part "SMD-RES-4.7K-5%-1/8W(0805)"))
    )
    (comp (ref "R294")
      (value "102")
      (footprint "eagle-import:R0805")
      (fields (field (name "MPN") "RC0805JR-071KL"))
      (libsource (lib "eagle-import") (part "SMD-RES-1K-5%-1/8W(0805)"))
    )
    (comp (ref "R295")
      (value "R_user")
      (footprint "eagle-import:R0805")
      (libsource (lib "eagle-import") (part "R-EU_R0805"))
    )
    (comp (ref "R296")
      (value "102")
      (footprint "eagle-import:R0805")
      (fields (field (name "MPN") "RC0805JR-07220RL"))
      (libsource (lib "eagle-import") (part "SMD-RES-220R-5%-1/8W(0805)"))
    )
    (comp (ref "R297")
      (value "(101)")
      (footprint "eagle-import:R0805")
      (fields (field (name "MPN") "RC0805JR-07100RL"))
      (libsource (lib "eagle-import") (part "SMD-RES-100R-5%-1/8W(0805)"))
    )
    (comp (ref "R298")
      (value "(1000)")
      (footprint "eagle-import:R0805")
      (fields (field (name "MPN") "RC0805JR-07100RL"))
      (libsource (lib "eagle-import") (part "SMD-RES-100R-5%-1/8W(0805)"))
    )
    (comp (ref "R299")
      (value "102")
      (footprint "eagle-import:R0805")
      (fields (field (name "MPN") "RC0805JR-071KL"))
      (libsource (lib "eagle-import") (part "SMD-RES-1K-5%-1/8W(0805)"))
    )
    (comp (ref "R300")
      (value "13")
      (footprint "eagle-import:R1206")
      (fields (field (name "MPN") "RC1206JR-0713RL"))
      (libsource (lib "eagle-import") (part "SMD-RES-13R-5%-1/4W(1206)"))
    )
    (comp (ref "R301")
      (value "13")
      (footprint "eagle-import:R1206")
      (fields (field (name "MPN") "RC1206JR-0713RL"))
      (libsource (lib "eagle-import") (part "SMD-RES-13R-5%-1/4W(1206)"))
    )
    (comp (ref "R302")
      (value "2702")
      (footprint "eagle-import:R0805")
      (fields (field (name "MPN") "RC0805JR-074K7L"))
      (libsource (lib "eagle-import") (part "SMD-RES-4.7K-5%-1/8W(0805)"))
    )
    (comp (ref "R303")
      (value "4701")
      (footprint "eagle-import:R0805")
      (fields (field (name "MPN") "RC0805JR-074K7L"))
      (libsource (lib "eagle-import") (part "SMD-RES-4.7K-5%-1/8W(0805)"))
    )
    (comp (ref "R304")
      (value "100")
      (footprint "eagle-import:R0805")
      (fields (field (name "MPN") "RC0805JR-072K2L"))
      (libsource (lib "eagle-import") (part "SMD-RES-2.2K-5%-1/8W(0805)"))
    )
    (comp (ref "R305")
      (value "104")
      (footprint "eagle-import:R0805")
      (fields (field (name "MPN") "RC0805FR-0710KL"))
      (libsource (lib "eagle-import") (part "SMD-RES-10K-1%-1/8W(0805)"))
    )
    (comp (ref "R306")
      (value "104")
      (footprint "eagle-import:R0805")
      (fields (field (name "MPN") "RC0805FR-0710KL"))
      (libsource (lib "eagle-import") (part "SMD-RES-10K-1%-1/8W(0805)"))
    )
    (comp (ref "R307")
      (value "(1002)")
      (footprint "eagle-import:R0805")
      (fields (field (name "MPN") "RC0805FR-0710KL"))
      (libsource (lib "eagle-import") (part "SMD-RES-10K-1%-1/8W(0805)"))
    )
    (comp (ref "R308")
      (value "2702")
      (footprint "eagle-import:R0805")
      (fields (field (name "MPN") "RC0805FR-0710KL"))
      (libsource (lib "eagle-import") (part "SMD-RES-10K-1%-1/8W(0805)"))
    )
    (comp (ref "R309")
      (value "47")
      (footprint "eagle-import:V235_17_1MM")
      (libsource (lib "eagle-import") (part "R-EU_V235/17_1MM"))
    )
    (comp (ref "R310")
      (value "47")
      (footprint "eagle-import:V235_17_1MM")
      (libsource (lib "eagle-import") (part "R-EU_V235/17_1MM"))
    )
    (comp (ref "R311")
      (value "2702")
      (footprint "eagle-import:R0805")
      (fields (field (name "MPN") "RC0805JR-074K7L"))
      (libsource (lib "eagle-import") (part "SMD-RES-4.7K-5%-1/8W(0805)"))
    )
    (comp (ref "R312")
      (value "2201")
      (footprint "eagle-import:R0805")
      (fields (field (name "MPN") "RC0805JR-072K2L"))
      (libsource (lib "eagle-import") (part "SMD-RES-2.2K-5%-1/8W(0805)"))
    )
    (comp (ref "R313")
      (value "1002")
      (footprint "eagle-import:R0805")
      (fields (field (name "MPN") "RC0805JR-074K7L"))
      (libsource (lib "eagle-import") (part "SMD-RES-4.7K-5%-1/8W(0805)"))
    )
    (comp (ref "R314")
      (value "1002")
      (footprint "eagle-import:R0805")
      (fields (field (name "MPN") "RC0805FR-0710KL"))
      (libsource (lib "eagle-import") (part "SMD-RES-10K-1%-1/8W(0805)"))
    )
    (comp (ref "R315")
      (value "102")
      (footprint "eagle-import:R0805")
      (fields (field (name "MPN") "RC0805JR-071KL"))
      (libsource (lib "eagle-import") (part "SMD-RES-1K-5%-1/8W(0805)"))
    )
    (comp (ref "R316")
      (value "2702")
      (footprint "eagle-import:R0805")
      (fields (field (name "MPN") "RC0805JR-074K7L"))
      (libsource (lib "eagle-import") (part "SMD-RES-4.7K-5%-1/8W(0805)"))
    )
    (comp (ref "R317")
      (value "1002")
      (footprint "eagle-import:R0805")
      (fields (field (name "MPN") "RC0805JR-071KL"))
      (libsource (lib "eagle-import") (part "SMD-RES-1K-5%-1/8W(0805)"))
    )
    (comp (ref "R318")
      (value "1002")
      (footprint "eagle-import:R0805")
      (fields (field (name "MPN") "RC0805JR-071KL"))
      (libsource (lib "eagle-import") (part "SMD-RES-1K-5%-1/8W(0805)"))
    )
    (comp (ref "R319")
      (value "R_user")
      (footprint "eagle-import:R0805")
      (libsource (lib "eagle-import") (part "R-EU_R0805"))
    )
    (comp (ref "R320")
      (value "104")
      (footprint "eagle-import:R0805")
      (fields (field (name "MPN") "RC0805FR-0710KL"))
      (libsource (lib "eagle-import") (part "SMD-RES-10K-1%-1/8W(0805)"))
    )
    (comp (ref "R321")
      (value "104")
      (footprint "eagle-import:R0805")
      (fields (field (name "MPN") "RC0805FR-0710KL"))
      (libsource (lib "eagle-import") (part "SMD-RES-10K-1%-1/8W(0805)"))
    )
    (comp (ref "R322")
      (value "104")
      (footprint "eagle-import:R0805")
      (fields (field (name "MPN") "RC0805FR-0710KL"))
      (libsource (lib "eagle-import") (part "SMD-RES-10K-1%-1/8W(0805)"))
    )
    (comp (ref "R323")
      (value "13")
      (footprint "eagle-import:R1206")
      (fields (field (name "MPN") "RC1206JR-0713RL"))
      (libsource (lib "eagle-import") (part "SMD-RES-13R-5%-1/4W(1206)"))
    )
    (comp (ref "R324")
      (value "2201")
      (footprint "eagle-import:R0805")
      (fields (field (name "MPN") "RC0805JR-071KL"))
      (libsource (lib "eagle-import") (part "SMD-RES-1K-5%-1/8W(0805)"))
    )
    (comp (ref "R325")
      (value "100")
      (footprint "eagle-import:R0805")
      (fields (field (name "MPN") "RC0805JR-07220RL"))
      (libsource (lib "eagle-import") (part "SMD-RES-220R-5%-1/8W(0805)"))
    )
    (comp (ref "R326")
      (value "13")
      (footprint "eagle-import:R1206")
      (fields (field (name "MPN") "RC1206JR-0713RL"))
      (libsource (lib "eagle-import") (part "SMD-RES-13R-5%-1/4W(1206)"))
    )
    (comp (ref "R327")
      (value "4701")
      (footprint "eagle-import:R0805")
      (fields (field (name "MPN") "RC0805JR-074K7L"))
      (libsource (lib "eagle-import") (part "SMD-RES-4.7K-5%-1/8W(0805)"))
    )
    (comp (ref "R328")
      (value "104")
      (footprint "eagle-import:R0805")
      (fields (field (name "MPN") "RC0805JR-074K7L"))
      (libsource (lib "eagle-import") (part "SMD-RES-4.7K-5%-1/8W(0805)"))
    )
    (comp (ref "R329")
      (value "100")
      (footprint "eagle-import:R0805")
      (fields (field (name "MPN") "RC0805JR-072K2L"))
      (libsource (lib "eagle-import") (part "SMD-RES-2.2K-5%-1/8W(0805)"))
    )
    (comp (ref "R330")
      (value "100")
      (footprint "eagle-import:R0805")
      (fields (field (name "MPN") "RC0805JR-072K2L"))
      (libsource (lib "eagle-import") (part "SMD-RES-2.2K-5%-1/8W(0805)"))
    )
    (comp (ref "SJ10")
      (value "SJ")
      (footprint "eagle-import:SJ")
      (libsource (lib "eagle-import") (part "solder-jumper_SJ"))
    )
    (comp (ref "SJ11")
      (value "SJ")
      (footprint "eagle-import:SJ")
      (libsource (lib "eagle-import") (part "SJ"))
    )
    (comp (ref "START5")
      (value "TPSB2.0")
      (footprint "eagle-import:B2.0")
      (libsource (lib "eagle-import") (part "TPSB2.0"))
    )
    (comp (ref "TP116")
      (value "TPSB2.0")
      (footprint "eagle-import:B2.0")
      (libsource (lib "eagle-import") (part "TPSB2.0"))
    )
    (comp (ref "TP117")
      (value "TPSB2.0")
      (footprint "eagle-import:B2.0")
      (libsource (lib "eagle-import") (part "TPSB2.0"))
    )
    (comp (ref "TP118")
      (value "TPSB2.0")
      (footprint "eagle-import:B2.0")
      (libsource (lib "eagle-import") (part "TPSB2.0"))
    )
    (comp (ref "TP119")
      (value "TPSB2.0")
      (footprint "eagle-import:B2.0")
      (libsource (lib "eagle-import") (part "TPSB2.0"))
    )
    (comp (ref "TP120")
      (value "TPSB2.0")
      (footprint "eagle-import:B2.0")
      (libsource (lib "eagle-import") (part "TPSB2.0"))
    )
    (comp (ref "TP121")
      (value "TPSB2.0")
      (footprint "eagle-import:B2.0")
      (libsource (lib "eagle-import") (part "TPSB2.0"))
    )
    (comp (ref "TP122")
      (value "TPSB2.0")
      (footprint "eagle-import:B2.0")
      (libsource (lib "eagle-import") (part "TPSB2.0"))
    )
    (comp (ref "TP123")
      (value "TPSB2.0")
      (footprint "eagle-import:B2.0")
      (libsource (lib "eagle-import") (part "TPSB2.0"))
    )
    (comp (ref "TP124")
      (value "TPSB2.0")
      (footprint "eagle-import:B2.0")
      (libsource (lib "eagle-import") (part "TPSB2.0"))
    )
    (comp (ref "TP125")
      (value "TPSB2.0")
      (footprint "eagle-import:B2.0")
      (libsource (lib "eagle-import") (part "TPSB2.0"))
    )
    (comp (ref "TP126")
      (value "TPSB2.0")
      (footprint "eagle-import:B2.0")
      (libsource (lib "eagle-import") (part "TPSB2.0"))
    )
    (comp (ref "TP127")
      (value "TPSB2.0")
      (footprint "eagle-import:B2.0")
      (libsource (lib "eagle-import") (part "TPSB2.0"))
    )
    (comp (ref "TP128")
      (value "TPSB2.0")
      (footprint "eagle-import:B2.0")
      (libsource (lib "eagle-import") (part "TPSB2.0"))
    )
    (comp (ref "TP129")
      (value "TPSB2.0")
      (footprint "eagle-import:B2.0")
      (libsource (lib "eagle-import") (part "TPSB2.0"))
    )
    (comp (ref "TP130")
      (value "TPSB2.0")
      (footprint "eagle-import:B2.0")
      (libsource (lib "eagle-import") (part "TPSB2.0"))
    )
    (comp (ref "TP131")
      (value "TPSB2.0")
      (footprint "eagle-import:B2.0")
      (libsource (lib "eagle-import") (part "TPSB2.0"))
    )
    (comp (ref "TP132")
      (value "TPSB2.0")
      (footprint "eagle-import:B2.0")
      (libsource (lib "eagle-import") (part "TPSB2.0"))
    )
    (comp (ref "TP133")
      (value "TPSB2.0")
      (footprint "eagle-import:B2.0")
      (libsource (lib "eagle-import") (part "TPSB2.0"))
    )
    (comp (ref "TP134")
      (value "TPSB1,27")
      (footprint "eagle-import:B1,27")
      (libsource (lib "eagle-import") (part "TPSB1,27"))
    )
    (comp (ref "TP135")
      (value "TPSB2.0")
      (footprint "eagle-import:B2.0")
      (libsource (lib "eagle-import") (part "TPSB2.0"))
    )
    (comp (ref "TP136")
      (value "TPSB2.0")
      (footprint "eagle-import:B2.0")
      (libsource (lib "eagle-import") (part "TPSB2.0"))
    )
    (comp (ref "TP137")
      (value "TPSB2.0")
      (footprint "eagle-import:B2.0")
      (libsource (lib "eagle-import") (part "TPSB2.0"))
    )
    (comp (ref "TP138")
      (value "TPSB2.0")
      (footprint "eagle-import:B2.0")
      (libsource (lib "eagle-import") (part "TPSB2.0"))
    )
    (comp (ref "X13")
      (value "CON_BMWV2")
      (footprint "eagle-import:24-PIN_V2")
      (libsource (lib "eagle-import") (part "CON_BMWV2"))
    )
    (comp (ref "X14")
      (value "22-23-2051")
      (footprint "eagle-import:22-23-2051")
      (fields (field (name "MF") "MOLEX"))
      (libsource (lib "eagle-import") (part "22-23-2051"))
    )
    (comp (ref "X15")
      (value "22-23-2021")
      (footprint "eagle-import:22-23-2021")
      (fields (field (name "MF") "MOLEX"))
      (libsource (lib "eagle-import") (part "22-23-2021"))
    )
  )
  (nets
    (net (code "1") (name "+10V") (class "Default")
      (node (ref "10V") (pin "TP") (pinfunction "PP_TP") (pintype "input"))
      (node (ref "10V1") (pin "TP") (pinfunction "PP_TP") (pintype "input"))
      (node (ref "10V2") (pin "TP") (pinfunction "PP_TP") (pintype "input"))
      (node (ref "10V3") (pin "TP") (pinfunction "PP_TP") (pintype "input"))
      (node (ref "10V4") (pin "TP") (pinfunction "PP_TP") (pintype "input"))
      (node (ref "10V5") (pin "TP") (pinfunction "PP_TP") (pintype "input"))
      (node (ref "C102") (pin "1") (pinfunction "1_1") (pintype "passive"))
      (node (ref "C22") (pin "1") (pinfunction "1_1") (pintype "passive"))
      (node (ref "C34") (pin "1") (pinfunction "1_1") (pintype "passive"))
      (node (ref "C46") (pin "1") (pinfunction "1_1") (pintype "passive"))
      (node (ref "C58") (pin "1") (pinfunction "1_1") (pintype "passive"))
      (node (ref "C9") (pin "1") (pinfunction "1_1") (pintype "passive"))
      (node (ref "IC104") (pin "1") (pinfunction "OUT_1") (pintype "passive"))
      (node (ref "IC110") (pin "4") (pinfunction "R_4") (pintype "input"))
      (node (ref "IC110") (pin "8") (pinfunction "V+_8") (pintype "power_in"))
      (node (ref "IC111") (pin "13") (pinfunction "CD_13") (pintype "input"))
      (node (ref "IC111") (pin "16") (pinfunction "VDD_16") (pintype "power_in"))
      (node (ref "IC111") (pin "3") (pinfunction "CD_3") (pintype "input"))
      (node (ref "IC111") (pin "5") (pinfunction "B_5") (pintype "input"))
      (node (ref "IC15") (pin "4") (pinfunction "R_4") (pintype "input"))
      (node (ref "IC15") (pin "8") (pinfunction "V+_8") (pintype "power_in"))
      (node (ref "IC16") (pin "13") (pinfunction "CD_13") (pintype "input"))
      (node (ref "IC16") (pin "16") (pinfunction "VDD_16") (pintype "power_in"))
      (node (ref "IC16") (pin "3") (pinfunction "CD_3") (pintype "input"))
      (node (ref "IC16") (pin "5") (pinfunction "B_5") (pintype "input"))
      (node (ref "IC17") (pin "1") (pinfunction "OUT_1") (pintype "passive"))
      (node (ref "IC24") (pin "4") (pinfunction "R_4") (pintype "input"))
      (node (ref "IC24") (pin "8") (pinfunction "V+_8") (pintype "power_in"))
      (node (ref "IC25") (pin "13") (pinfunction "CD_13") (pintype "input"))
      (node (ref "IC25") (pin "16") (pinfunction "VDD_16") (pintype "power_in"))
      (node (ref "IC25") (pin "3") (pinfunction "CD_3") (pintype "input"))
      (node (ref "IC25") (pin "5") (pinfunction "B_5") (pintype "input"))
      (node (ref "IC26") (pin "1") (pinfunction "OUT_1") (pintype "passive"))
      (node (ref "IC33") (pin "4") (pinfunction "R_4") (pintype "input"))
      (node (ref "IC33") (pin "8") (pinfunction "V+_8") (pintype "power_in"))
      (node (ref "IC34") (pin "13") (pinfunction "CD_13") (pintype "input"))
      (node (ref "IC34") (pin "16") (pinfunction "VDD_16") (pintype "power_in"))
      (node (ref "IC34") (pin "3") (pinfunction "CD_3") (pintype "input"))
      (node (ref "IC34") (pin "5") (pinfunction "B_5") (pintype "input"))
      (node (ref "IC35") (pin "1") (pinfunction "OUT_1") (pintype "passive"))
      (node (ref "IC42") (pin "4") (pinfunction "R_4") (pintype "input"))
      (node (ref "IC42") (pin "8") (pinfunction "V+_8") (pintype "power_in"))
      (node (ref "IC43") (pin "13") (pinfunction "CD_13") (pintype "input"))
      (node (ref "IC43") (pin "16") (pinfunction "VDD_16") (pintype "power_in"))
      (node (ref "IC43") (pin "3") (pinfunction "CD_3") (pintype "input"))
      (node (ref "IC43") (pin "5") (pinfunction "B_5") (pintype "input"))
      (node (ref "IC44") (pin "1") (pinfunction "OUT_1") (pintype "passive"))
      (node (ref "IC6") (pin "4") (pinfunction "R_4") (pintype "input"))
      (node (ref "IC6") (pin "8") (pinfunction "V+_8") (pintype "power_in"))
      (node (ref "IC7") (pin "13") (pinfunction "CD_13") (pintype "input"))
      (node (ref "IC7") (pin "16") (pinfunction "VDD_16") (pintype "power_in"))
      (node (ref "IC7") (pin "3") (pinfunction "CD_3") (pintype "input"))
      (node (ref "IC7") (pin "5") (pinfunction "B_5") (pintype "input"))
      (node (ref "IC8") (pin "1") (pinfunction "OUT_1") (pintype "passive"))
      (node (ref "R10") (pin "2") (pinfunction "2_2") (pintype "passive"))
      (node (ref "R139") (pin "2") (pinfunction "2_2") (pintype "passive"))
      (node (ref "R145") (pin "2") (pinfunction "2_2") (pintype "passive"))
      (node (ref "R163") (pin "2") (pinfunction "2_2") (pintype "passive"))
      (node (ref "R201") (pin "2") (pinfunction "2_2") (pintype "passive"))
      (node (ref "R218") (pin "2") (pinfunction "2_2") (pintype "passive"))
      (node (ref "R256") (pin "2") (pinfunction "2_2") (pintype "passive"))
      (node (ref "R273") (pin "2") (pinfunction "2_2") (pintype "passive"))
      (node (ref "R311") (pin "2") (pinfunction "2_2") (pintype "passive"))
      (node (ref "R328") (pin "2") (pinfunction "2_2") (pintype "passive"))
      (node (ref "R47") (pin "2") (pinfunction "2_2") (pintype "passive"))
      (node (ref "R64") (pin "2") (pinfunction "2_2") (pintype "passive"))
    )
    (net (code "2") (name "+12V") (class "Default")
      (node (ref "10") (pin "1") (pinfunction "KL_1") (pintype "passive"))
      (node (ref "12") (pin "1") (pinfunction "KL_1") (pintype "passive"))
      (node (ref "2") (pin "1") (pinfunction "KL_1") (pintype "passive"))
      (node (ref "4") (pin "1") (pinfunction "KL_1") (pintype "passive"))
      (node (ref "6") (pin "1") (pinfunction "KL_1") (pintype "passive"))
      (node (ref "8") (pin "1") (pinfunction "KL_1") (pintype "passive"))
      (node (ref "C13") (pin "1") (pinfunction "1_1") (pintype "passive"))
      (node (ref "C2") (pin "1") (pinfunction "1_1") (pintype "passive"))
      (node (ref "C26") (pin "1") (pinfunction "1_1") (pintype "passive"))
      (node (ref "C38") (pin "1") (pinfunction "1_1") (pintype "passive"))
      (node (ref "C50") (pin "1") (pinfunction "1_1") (pintype "passive"))
      (node (ref "C62") (pin "1") (pinfunction "1_1") (pintype "passive"))
      (node (ref "D101") (pin "C") (pinfunction "C_C") (pintype "passive"))
      (node (ref "D13") (pin "C") (pinfunction "C_C") (pintype "passive"))
      (node (ref "D27") (pin "C") (pinfunction "C_C") (pintype "passive"))
      (node (ref "D41") (pin "C") (pinfunction "C_C") (pintype "passive"))
      (node (ref "D55") (pin "C") (pinfunction "C_C") (pintype "passive"))
      (node (ref "D69") (pin "C") (pinfunction "C_C") (pintype "passive"))
      (node (ref "IC1") (pin "16") (pinfunction "VDD_16") (pintype "power_in"))
      (node (ref "IC10") (pin "16") (pinfunction "VDD_16") (pintype "power_in"))
      (node (ref "IC102") (pin "3") (pinfunction "IN_3") (pintype "input"))
      (node (ref "IC104") (pin "3") (pinfunction "IN_3") (pintype "input"))
      (node (ref "IC105") (pin "16") (pinfunction "VDD_16") (pintype "power_in"))
      (node (ref "IC107") (pin "9") (pinfunction "CD+_9") (pintype "passive"))
      (node (ref "IC12") (pin "9") (pinfunction "CD+_9") (pintype "passive"))
      (node (ref "IC14") (pin "3") (pinfunction "IN_3") (pintype "input"))
      (node (ref "IC17") (pin "3") (pinfunction "IN_3") (pintype "input"))
      (node (ref "IC19") (pin "16") (pinfunction "VDD_16") (pintype "power_in"))
      (node (ref "IC21") (pin "9") (pinfunction "CD+_9") (pintype "passive"))
      (node (ref "IC23") (pin "3") (pinfunction "IN_3") (pintype "input"))
      (node (ref "IC26") (pin "3") (pinfunction "IN_3") (pintype "input"))
      (node (ref "IC28") (pin "16") (pinfunction "VDD_16") (pintype "power_in"))
      (node (ref "IC3") (pin "9") (pinfunction "CD+_9") (pintype "passive"))
      (node (ref "IC30") (pin "9") (pinfunction "CD+_9") (pintype "passive"))
      (node (ref "IC32") (pin "3") (pinfunction "IN_3") (pintype "input"))
      (node (ref "IC35") (pin "3") (pinfunction "IN_3") (pintype "input"))
      (node (ref "IC37") (pin "16") (pinfunction "VDD_16") (pintype "power_in"))
      (node (ref "IC39") (pin "9") (pinfunction "CD+_9") (pintype "passive"))
      (node (ref "IC41") (pin "3") (pinfunction "IN_3") (pintype "input"))
      (node (ref "IC44") (pin "3") (pinfunction "IN_3") (pintype "input"))
      (node (ref "IC5") (pin "3") (pinfunction "IN_3") (pintype "input"))
      (node (ref "IC8") (pin "3") (pinfunction "IN_3") (pintype "input"))
      (node (ref "JP1") (pin "2") (pinfunction "2_2") (pintype "passive"))
      (node (ref "JP101") (pin "2") (pinfunction "2_2") (pintype "passive"))
      (node (ref "JP11") (pin "2") (pinfunction "2_2") (pintype "passive"))
      (node (ref "JP16") (pin "2") (pinfunction "2_2") (pintype "passive"))
      (node (ref "JP21") (pin "2") (pinfunction "2_2") (pintype "passive"))
      (node (ref "JP6") (pin "2") (pinfunction "2_2") (pintype "passive"))
      (node (ref "R102") (pin "1") (pinfunction "1_1") (pintype "passive"))
      (node (ref "R106") (pin "1") (pinfunction "1_1") (pintype "passive"))
      (node (ref "R109") (pin "2") (pinfunction "2_2") (pintype "passive"))
      (node (ref "R110") (pin "2") (pinfunction "2_2") (pintype "passive"))
      (node (ref "R111") (pin "2") (pinfunction "2_2") (pintype "passive"))
      (node (ref "R12") (pin "2") (pinfunction "2_2") (pintype "passive"))
      (node (ref "R13") (pin "2") (pinfunction "2_2") (pintype "passive"))
      (node (ref "R135") (pin "1") (pinfunction "1_1") (pintype "passive"))
      (node (ref "R15") (pin "2") (pinfunction "2_2") (pintype "passive"))
      (node (ref "R16") (pin "2") (pinfunction "2_2") (pintype "passive"))
      (node (ref "R164") (pin "2") (pinfunction "2_2") (pintype "passive"))
      (node (ref "R165") (pin "2") (pinfunction "2_2") (pintype "passive"))
      (node (ref "R169") (pin "2") (pinfunction "2_2") (pintype "passive"))
      (node (ref "R17") (pin "2") (pinfunction "2_2") (pintype "passive"))
      (node (ref "R170") (pin "2") (pinfunction "2_2") (pintype "passive"))
      (node (ref "R171") (pin "2") (pinfunction "2_2") (pintype "passive"))
      (node (ref "R190") (pin "1") (pinfunction "1_1") (pintype "passive"))
      (node (ref "R191") (pin "1") (pinfunction "1_1") (pintype "passive"))
      (node (ref "R195") (pin "1") (pinfunction "1_1") (pintype "passive"))
      (node (ref "R219") (pin "2") (pinfunction "2_2") (pintype "passive"))
      (node (ref "R220") (pin "2") (pinfunction "2_2") (pintype "passive"))
      (node (ref "R224") (pin "2") (pinfunction "2_2") (pintype "passive"))
      (node (ref "R225") (pin "2") (pinfunction "2_2") (pintype "passive"))
      (node (ref "R226") (pin "2") (pinfunction "2_2") (pintype "passive"))
      (node (ref "R245") (pin "1") (pinfunction "1_1") (pintype "passive"))
      (node (ref "R246") (pin "1") (pinfunction "1_1") (pintype "passive"))
      (node (ref "R250") (pin "1") (pinfunction "1_1") (pintype "passive"))
      (node (ref "R274") (pin "2") (pinfunction "2_2") (pintype "passive"))
      (node (ref "R275") (pin "2") (pinfunction "2_2") (pintype "passive"))
      (node (ref "R279") (pin "2") (pinfunction "2_2") (pintype "passive"))
      (node (ref "R280") (pin "2") (pinfunction "2_2") (pintype "passive"))
      (node (ref "R281") (pin "2") (pinfunction "2_2") (pintype "passive"))
      (node (ref "R300") (pin "1") (pinfunction "1_1") (pintype "passive"))
      (node (ref "R301") (pin "1") (pinfunction "1_1") (pintype "passive"))
      (node (ref "R305") (pin "1") (pinfunction "1_1") (pintype "passive"))
      (node (ref "R329") (pin "2") (pinfunction "2_2") (pintype "passive"))
      (node (ref "R330") (pin "2") (pinfunction "2_2") (pintype "passive"))
      (node (ref "R36") (pin "1") (pinfunction "1_1") (pintype "passive"))
      (node (ref "R37") (pin "1") (pinfunction "1_1") (pintype "passive"))
      (node (ref "R41") (pin "1") (pinfunction "1_1") (pintype "passive"))
      (node (ref "R65") (pin "2") (pinfunction "2_2") (pintype "passive"))
      (node (ref "R66") (pin "2") (pinfunction "2_2") (pintype "passive"))
      (node (ref "R70") (pin "2") (pinfunction "2_2") (pintype "passive"))
      (node (ref "R71") (pin "2") (pinfunction "2_2") (pintype "passive"))
      (node (ref "R72") (pin "2") (pinfunction "2_2") (pintype "passive"))
      (node (ref "R91") (pin "1") (pinfunction "1_1") (pintype "passive"))
      (node (ref "R92") (pin "1") (pinfunction "1_1") (pintype "passive"))
      (node (ref "R96") (pin "1") (pinfunction "1_1") (pintype "passive"))
      (node (ref "TP114") (pin "TP") (pinfunction "PP_TP") (pintype "input"))
      (node (ref "TP12") (pin "TP") (pinfunction "PP_TP") (pintype "input"))
      (node (ref "TP137") (pin "TP") (pinfunction "PP_TP") (pintype "input"))
      (node (ref "TP45") (pin "TP") (pinfunction "PP_TP") (pintype "input"))
      (node (ref "TP68") (pin "TP") (pinfunction "PP_TP") (pintype "input"))
      (node (ref "TP91") (pin "TP") (pinfunction "PP_TP") (pintype "input"))
      (node (ref "X103") (pin "1") (pinfunction "S_1") (pintype "passive"))
      (node (ref "X11") (pin "1") (pinfunction "S_1") (pintype "passive"))
      (node (ref "X14") (pin "1") (pinfunction "S_1") (pintype "passive"))
      (node (ref "X2") (pin "1") (pinfunction "S_1") (pintype "passive"))
      (node (ref "X5") (pin "1") (pinfunction "S_1") (pintype "passive"))
      (node (ref "X8") (pin "1") (pinfunction "S_1") (pintype "passive"))
    )
    (net (code "3") (name "GND") (class "Default")
      (node (ref "1") (pin "12") (pinfunction "KL_12") (pintype "passive"))
      (node (ref "11") (pin "12") (pinfunction "KL_12") (pintype "passive"))
      (node (ref "3") (pin "12") (pinfunction "KL_12") (pintype "passive"))
      (node (ref "5") (pin "12") (pinfunction "KL_12") (pintype "passive"))
      (node (ref "7") (pin "12") (pinfunction "KL_12") (pintype "passive"))
      (node (ref "9") (pin "12") (pinfunction "KL_12") (pintype "passive"))
      (node (ref "C1") (pin "2") (pinfunction "2_2") (pintype "passive"))
      (node (ref "C10") (pin "2") (pinfunction "2_2") (pintype "passive"))
      (node (ref "C101") (pin "2") (pinfunction "2_2") (pintype "passive"))
      (node (ref "C102") (pin "2") (pinfunction "2_2") (pintype "passive"))
      (node (ref "C103") (pin "2") (pinfunction "2_2") (pintype "passive"))
      (node (ref "C104") (pin "2") (pinfunction "2_2") (pintype "passive"))
      (node (ref "C105") (pin "2") (pinfunction "2_2") (pintype "passive"))
      (node (ref "C106") (pin "1") (pinfunction "1_1") (pintype "passive"))
      (node (ref "C107") (pin "2") (pinfunction "2_2") (pintype "passive"))
      (node (ref "C108") (pin "2") (pinfunction "2_2") (pintype "passive"))
      (node (ref "C109") (pin "1") (pinfunction "1_1") (pintype "passive"))
      (node (ref "C11") (pin "2") (pinfunction "2_2") (pintype "passive"))
      (node (ref "C110") (pin "2") (pinfunction "2_2") (pintype "passive"))
      (node (ref "C12") (pin "1") (pinfunction "1_1") (pintype "passive"))
      (node (ref "C13") (pin "2") (pinfunction "2_2") (pintype "passive"))
      (node (ref "C14") (pin "2") (pinfunction "2_2") (pintype "passive"))
      (node (ref "C15") (pin "1") (pinfunction "1_1") (pintype "passive"))
      (node (ref "C16") (pin "2") (pinfunction "2_2") (pintype "passive"))
      (node (ref "C17") (pin "2") (pinfunction "2_2") (pintype "passive"))
      (node (ref "C18") (pin "2") (pinfunction "2_2") (pintype "passive"))
      (node (ref "C19") (pin "2") (pinfunction "2_2") (pintype "passive"))
      (node (ref "C2") (pin "2") (pinfunction "2_2") (pintype "passive"))
      (node (ref "C20") (pin "1") (pinfunction "1_1") (pintype "passive"))
      (node (ref "C21") (pin "1") (pinfunction "1_1") (pintype "passive"))
      (node (ref "C22") (pin "2") (pinfunction "2_2") (pintype "passive"))
      (node (ref "C23") (pin "2") (pinfunction "2_2") (pintype "passive"))
      (node (ref "C24") (pin "2") (pinfunction "2_2") (pintype "passive"))
      (node (ref "C25") (pin "1") (pinfunction "1_1") (pintype "passive"))
      (node (ref "C26") (pin "2") (pinfunction "2_2") (pintype "passive"))
      (node (ref "C27") (pin "2") (pinfunction "2_2") (pintype "passive"))
      (node (ref "C28") (pin "2") (pinfunction "2_2") (pintype "passive"))
      (node (ref "C29") (pin "2") (pinfunction "2_2") (pintype "passive"))
      (node (ref "C3") (pin "2") (pinfunction "2_2") (pintype "passive"))
      (node (ref "C30") (pin "2") (pinfunction "2_2") (pintype "passive"))
      (node (ref "C31") (pin "2") (pinfunction "2_2") (pintype "passive"))
      (node (ref "C32") (pin "1") (pinfunction "1_1") (pintype "passive"))
      (node (ref "C33") (pin "1") (pinfunction "1_1") (pintype "passive"))
      (node (ref "C34") (pin "2") (pinfunction "2_2") (pintype "passive"))
      (node (ref "C35") (pin "2") (pinfunction "2_2") (pintype "passive"))
      (node (ref "C36") (pin "2") (pinfunction "2_2") (pintype "passive"))
      (node (ref "C37") (pin "1") (pinfunction "1_1") (pintype "passive"))
      (node (ref "C38") (pin "2") (pinfunction "2_2") (pintype "passive"))
      (node (ref "C39") (pin "2") (pinfunction "2_2") (pintype "passive"))
      (node (ref "C4") (pin "2") (pinfunction "2_2") (pintype "passive"))
      (node (ref "C40") (pin "2") (pinfunction "2_2") (pintype "passive"))
      (node (ref "C41") (pin "2") (pinfunction "2_2") (pintype "passive"))
      (node (ref "C42") (pin "2") (pinfunction "2_2") (pintype "passive"))
      (node (ref "C43") (pin "2") (pinfunction "2_2") (pintype "passive"))
      (node (ref "C44") (pin "1") (pinfunction "1_1") (pintype "passive"))
      (node (ref "C45") (pin "1") (pinfunction "1_1") (pintype "passive"))
      (node (ref "C46") (pin "2") (pinfunction "2_2") (pintype "passive"))
      (node (ref "C47") (pin "2") (pinfunction "2_2") (pintype "passive"))
      (node (ref "C48") (pin "2") (pinfunction "2_2") (pintype "passive"))
      (node (ref "C49") (pin "1") (pinfunction "1_1") (pintype "passive"))
      (node (ref "C5") (pin "2") (pinfunction "2_2") (pintype "passive"))
      (node (ref "C50") (pin "2") (pinfunction "2_2") (pintype "passive"))
      (node (ref "C51") (pin "2") (pinfunction "2_2") (pintype "passive"))
      (node (ref "C52") (pin "2") (pinfunction "2_2") (pintype "passive"))
      (node (ref "C53") (pin "2") (pinfunction "2_2") (pintype "passive"))
      (node (ref "C54") (pin "2") (pinfunction "2_2") (pintype "passive"))
      (node (ref "C55") (pin "2") (pinfunction "2_2") (pintype "passive"))
      (node (ref "C56") (pin "1") (pinfunction "1_1") (pintype "passive"))
      (node (ref "C57") (pin "1") (pinfunction "1_1") (pintype "passive"))
      (node (ref "C58") (pin "2") (pinfunction "2_2") (pintype "passive"))
      (node (ref "C59") (pin "2") (pinfunction "2_2") (pintype "passive"))
      (node (ref "C6") (pin "2") (pinfunction "2_2") (pintype "passive"))
      (node (ref "C60") (pin "2") (pinfunction "2_2") (pintype "passive"))
      (node (ref "C61") (pin "1") (pinfunction "1_1") (pintype "passive"))
      (node (ref "C62") (pin "2") (pinfunction "2_2") (pintype "passive"))
      (node (ref "C7") (pin "1") (pinfunction "1_1") (pintype "passive"))
      (node (ref "C8") (pin "1") (pinfunction "1_1") (pintype "passive"))
      (node (ref "C9") (pin "2") (pinfunction "2_2") (pintype "passive"))
      (node (ref "D101") (pin "A") (pinfunction "A_A") (pintype "passive"))
      (node (ref "D104") (pin "A") (pinfunction "A_A") (pintype "passive"))
      (node (ref "D105") (pin "1") (pinfunction "+_1") (pintype "passive"))
      (node (ref "D11") (pin "1") (pinfunction "+_1") (pintype "passive"))
      (node (ref "D13") (pin "A") (pinfunction "A_A") (pintype "passive"))
      (node (ref "D14") (pin "A") (pinfunction "A_A") (pintype "passive"))
      (node (ref "D17") (pin "A") (pinfunction "A_A") (pintype "passive"))
      (node (ref "D25") (pin "1") (pinfunction "+_1") (pintype "passive"))
      (node (ref "D27") (pin "A") (pinfunction "A_A") (pintype "passive"))
      (node (ref "D28") (pin "A") (pinfunction "A_A") (pintype "passive"))
      (node (ref "D31") (pin "A") (pinfunction "A_A") (pintype "passive"))
      (node (ref "D39") (pin "1") (pinfunction "+_1") (pintype "passive"))
      (node (ref "D4") (pin "A") (pinfunction "A_A") (pintype "passive"))
      (node (ref "D41") (pin "A") (pinfunction "A_A") (pintype "passive"))
      (node (ref "D42") (pin "A") (pinfunction "A_A") (pintype "passive"))
      (node (ref "D45") (pin "A") (pinfunction "A_A") (pintype "passive"))
      (node (ref "D53") (pin "1") (pinfunction "+_1") (pintype "passive"))
      (node (ref "D55") (pin "A") (pinfunction "A_A") (pintype "passive"))
      (node (ref "D56") (pin "A") (pinfunction "A_A") (pintype "passive"))
      (node (ref "D59") (pin "A") (pinfunction "A_A") (pintype "passive"))
      (node (ref "D67") (pin "1") (pinfunction "+_1") (pintype "passive"))
      (node (ref "D69") (pin "A") (pinfunction "A_A") (pintype "passive"))
      (node (ref "D70") (pin "A") (pinfunction "A_A") (pintype "passive"))
      (node (ref "D73") (pin "A") (pinfunction "A_A") (pintype "passive"))
      (node (ref "IC1") (pin "11") (pinfunction "D_11") (pintype "input"))
      (node (ref "IC1") (pin "8") (pinfunction "VSS_8") (pintype "power_in"))
      (node (ref "IC10") (pin "11") (pinfunction "D_11") (pintype "input"))
      (node (ref "IC10") (pin "8") (pinfunction "VSS_8") (pintype "power_in"))
      (node (ref "IC101") (pin "4") (pinfunction "V-_4") (pintype "power_in"))
      (node (ref "IC102") (pin "2") (pinfunction "GND_2") (pintype "input"))
      (node (ref "IC102") (pin "2@1") (pinfunction "GND_2@1") (pintype "input"))
      (node (ref "IC104") (pin "2") (pinfunction "GND_2") (pintype "input"))
      (node (ref "IC104") (pin "2@1") (pinfunction "GND_2@1") (pintype "input"))
      (node (ref "IC105") (pin "11") (pinfunction "D_11") (pintype "input"))
      (node (ref "IC105") (pin "8") (pinfunction "VSS_8") (pintype "power_in"))
      (node (ref "IC107") (pin "8") (pinfunction "GND_8") (pintype "power_in"))
      (node (ref "IC108") (pin "12") (pinfunction "GND_12") (pintype "power_in"))
      (node (ref "IC110") (pin "1") (pinfunction "GND_1") (pintype "power_in"))
      (node (ref "IC111") (pin "1") (pinfunction "T1_1") (pintype "input"))
      (node (ref "IC111") (pin "15") (pinfunction "T1_15") (pintype "input"))
      (node (ref "IC111") (pin "8") (pinfunction "VSS_8") (pintype "power_in"))
      (node (ref "IC12") (pin "8") (pinfunction "GND_8") (pintype "power_in"))
      (node (ref "IC13") (pin "12") (pinfunction "GND_12") (pintype "power_in"))
      (node (ref "IC14") (pin "2") (pinfunction "GND_2") (pintype "input"))
      (node (ref "IC14") (pin "2@1") (pinfunction "GND_2@1") (pintype "input"))
      (node (ref "IC15") (pin "1") (pinfunction "GND_1") (pintype "power_in"))
      (node (ref "IC16") (pin "1") (pinfunction "T1_1") (pintype "input"))
      (node (ref "IC16") (pin "15") (pinfunction "T1_15") (pintype "input"))
      (node (ref "IC16") (pin "8") (pinfunction "VSS_8") (pintype "power_in"))
      (node (ref "IC17") (pin "2") (pinfunction "GND_2") (pintype "input"))
      (node (ref "IC17") (pin "2@1") (pinfunction "GND_2@1") (pintype "input"))
      (node (ref "IC18") (pin "4") (pinfunction "V-_4") (pintype "power_in"))
      (node (ref "IC19") (pin "11") (pinfunction "D_11") (pintype "input"))
      (node (ref "IC19") (pin "8") (pinfunction "VSS_8") (pintype "power_in"))
      (node (ref "IC21") (pin "8") (pinfunction "GND_8") (pintype "power_in"))
      (node (ref "IC22") (pin "12") (pinfunction "GND_12") (pintype "power_in"))
      (node (ref "IC23") (pin "2") (pinfunction "GND_2") (pintype "input"))
      (node (ref "IC23") (pin "2@1") (pinfunction "GND_2@1") (pintype "input"))
      (node (ref "IC24") (pin "1") (pinfunction "GND_1") (pintype "power_in"))
      (node (ref "IC25") (pin "1") (pinfunction "T1_1") (pintype "input"))
      (node (ref "IC25") (pin "15") (pinfunction "T1_15") (pintype "input"))
      (node (ref "IC25") (pin "8") (pinfunction "VSS_8") (pintype "power_in"))
      (node (ref "IC26") (pin "2") (pinfunction "GND_2") (pintype "input"))
      (node (ref "IC26") (pin "2@1") (pinfunction "GND_2@1") (pintype "input"))
      (node (ref "IC27") (pin "4") (pinfunction "V-_4") (pintype "power_in"))
      (node (ref "IC28") (pin "11") (pinfunction "D_11") (pintype "input"))
      (node (ref "IC28") (pin "8") (pinfunction "VSS_8") (pintype "power_in"))
      (node (ref "IC3") (pin "8") (pinfunction "GND_8") (pintype "power_in"))
      (node (ref "IC30") (pin "8") (pinfunction "GND_8") (pintype "power_in"))
      (node (ref "IC31") (pin "12") (pinfunction "GND_12") (pintype "power_in"))
      (node (ref "IC32") (pin "2") (pinfunction "GND_2") (pintype "input"))
      (node (ref "IC32") (pin "2@1") (pinfunction "GND_2@1") (pintype "input"))
      (node (ref "IC33") (pin "1") (pinfunction "GND_1") (pintype "power_in"))
      (node (ref "IC34") (pin "1") (pinfunction "T1_1") (pintype "input"))
      (node (ref "IC34") (pin "15") (pinfunction "T1_15") (pintype "input"))
      (node (ref "IC34") (pin "8") (pinfunction "VSS_8") (pintype "power_in"))
      (node (ref "IC35") (pin "2") (pinfunction "GND_2") (pintype "input"))
      (node (ref "IC35") (pin "2@1") (pinfunction "GND_2@1") (pintype "input"))
      (node (ref "IC36") (pin "4") (pinfunction "V-_4") (pintype "power_in"))
      (node (ref "IC37") (pin "11") (pinfunction "D_11") (pintype "input"))
      (node (ref "IC37") (pin "8") (pinfunction "VSS_8") (pintype "power_in"))
      (node (ref "IC39") (pin "8") (pinfunction "GND_8") (pintype "power_in"))
      (node (ref "IC4") (pin "12") (pinfunction "GND_12") (pintype "power_in"))
      (node (ref "IC40") (pin "12") (pinfunction "GND_12") (pintype "power_in"))
      (node (ref "IC41") (pin "2") (pinfunction "GND_2") (pintype "input"))
      (node (ref "IC41") (pin "2@1") (pinfunction "GND_2@1") (pintype "input"))
      (node (ref "IC42") (pin "1") (pinfunction "GND_1") (pintype "power_in"))
      (node (ref "IC43") (pin "1") (pinfunction "T1_1") (pintype "input"))
      (node (ref "IC43") (pin "15") (pinfunction "T1_15") (pintype "input"))
      (node (ref "IC43") (pin "8") (pinfunction "VSS_8") (pintype "power_in"))
      (node (ref "IC44") (pin "2") (pinfunction "GND_2") (pintype "input"))
      (node (ref "IC44") (pin "2@1") (pinfunction "GND_2@1") (pintype "input"))
      (node (ref "IC45") (pin "4") (pinfunction "V-_4") (pintype "power_in"))
      (node (ref "IC5") (pin "2") (pinfunction "GND_2") (pintype "input"))
      (node (ref "IC5") (pin "2@1") (pinfunction "GND_2@1") (pintype "input"))
      (node (ref "IC6") (pin "1") (pinfunction "GND_1") (pintype "power_in"))
      (node (ref "IC7") (pin "1") (pinfunction "T1_1") (pintype "input"))
      (node (ref "IC7") (pin "15") (pinfunction "T1_15") (pintype "input"))
      (node (ref "IC7") (pin "8") (pinfunction "VSS_8") (pintype "power_in"))
      (node (ref "IC8") (pin "2") (pinfunction "GND_2") (pintype "input"))
      (node (ref "IC8") (pin "2@1") (pinfunction "GND_2@1") (pintype "input"))
      (node (ref "IC9") (pin "4") (pinfunction "V-_4") (pintype "power_in"))
      (node (ref "Q1") (pin "2") (pinfunction "S_2") (pintype "passive"))
      (node (ref "Q107") (pin "2") (pinfunction "S_2") (pintype "passive"))
      (node (ref "Q11") (pin "2") (pinfunction "S_2") (pintype "passive"))
      (node (ref "Q13") (pin "2") (pinfunction "S_2") (pintype "passive"))
      (node (ref "Q19") (pin "2") (pinfunction "S_2") (pintype "passive"))
      (node (ref "Q21") (pin "2") (pinfunction "S_2") (pintype "passive"))
      (node (ref "Q23") (pin "2") (pinfunction "S_2") (pintype "passive"))
      (node (ref "Q29") (pin "2") (pinfunction "S_2") (pintype "passive"))
      (node (ref "Q3") (pin "2") (pinfunction "S_2") (pintype "passive"))
      (node (ref "Q31") (pin "2") (pinfunction "S_2") (pintype "passive"))
      (node (ref "Q33") (pin "2") (pinfunction "S_2") (pintype "passive"))
      (node (ref "Q39") (pin "2") (pinfunction "S_2") (pintype "passive"))
      (node (ref "Q41") (pin "2") (pinfunction "S_2") (pintype "passive"))
      (node (ref "Q43") (pin "2") (pinfunction "S_2") (pintype "passive"))
      (node (ref "Q49") (pin "2") (pinfunction "S_2") (pintype "passive"))
      (node (ref "Q51") (pin "2") (pinfunction "S_2") (pintype "passive"))
      (node (ref "Q53") (pin "2") (pinfunction "S_2") (pintype "passive"))
      (node (ref "Q9") (pin "2") (pinfunction "S_2") (pintype "passive"))
      (node (ref "R100") (pin "1") (pinfunction "1_1") (pintype "passive"))
      (node (ref "R101") (pin "2") (pinfunction "2_2") (pintype "passive"))
      (node (ref "R103") (pin "2") (pinfunction "2_2") (pintype "passive"))
      (node (ref "R104") (pin "2") (pinfunction "2_2") (pintype "passive"))
      (node (ref "R107") (pin "1") (pinfunction "1_1") (pintype "passive"))
      (node (ref "R114") (pin "1") (pinfunction "1_1") (pintype "passive"))
      (node (ref "R118") (pin "1") (pinfunction "1_1") (pintype "passive"))
      (node (ref "R123") (pin "1") (pinfunction "1_1") (pintype "passive"))
      (node (ref "R132") (pin "1") (pinfunction "1_1") (pintype "passive"))
      (node (ref "R136") (pin "1") (pinfunction "1_1") (pintype "passive"))
      (node (ref "R137") (pin "1") (pinfunction "1_1") (pintype "passive"))
      (node (ref "R141") (pin "2") (pinfunction "2_2") (pintype "passive"))
      (node (ref "R143") (pin "2") (pinfunction "2_2") (pintype "passive"))
      (node (ref "R153") (pin "1") (pinfunction "1_1") (pintype "passive"))
      (node (ref "R154") (pin "2") (pinfunction "2_2") (pintype "passive"))
      (node (ref "R158") (pin "2") (pinfunction "2_2") (pintype "passive"))
      (node (ref "R159") (pin "2") (pinfunction "2_2") (pintype "passive"))
      (node (ref "R160") (pin "1") (pinfunction "1_1") (pintype "passive"))
      (node (ref "R173") (pin "1") (pinfunction "1_1") (pintype "passive"))
      (node (ref "R179") (pin "1") (pinfunction "1_1") (pintype "passive"))
      (node (ref "R183") (pin "1") (pinfunction "1_1") (pintype "passive"))
      (node (ref "R184") (pin "2") (pinfunction "2_2") (pintype "passive"))
      (node (ref "R185") (pin "2") (pinfunction "2_2") (pintype "passive"))
      (node (ref "R187") (pin "2") (pinfunction "2_2") (pintype "passive"))
      (node (ref "R19") (pin "1") (pinfunction "1_1") (pintype "passive"))
      (node (ref "R196") (pin "2") (pinfunction "2_2") (pintype "passive"))
      (node (ref "R199") (pin "1") (pinfunction "1_1") (pintype "passive"))
      (node (ref "R200") (pin "1") (pinfunction "1_1") (pintype "passive"))
      (node (ref "R208") (pin "1") (pinfunction "1_1") (pintype "passive"))
      (node (ref "R209") (pin "2") (pinfunction "2_2") (pintype "passive"))
      (node (ref "R213") (pin "2") (pinfunction "2_2") (pintype "passive"))
      (node (ref "R214") (pin "2") (pinfunction "2_2") (pintype "passive"))
      (node (ref "R215") (pin "1") (pinfunction "1_1") (pintype "passive"))
      (node (ref "R228") (pin "1") (pinfunction "1_1") (pintype "passive"))
      (node (ref "R234") (pin "1") (pinfunction "1_1") (pintype "passive"))
      (node (ref "R238") (pin "1") (pinfunction "1_1") (pintype "passive"))
      (node (ref "R239") (pin "2") (pinfunction "2_2") (pintype "passive"))
      (node (ref "R240") (pin "2") (pinfunction "2_2") (pintype "passive"))
      (node (ref "R242") (pin "2") (pinfunction "2_2") (pintype "passive"))
      (node (ref "R25") (pin "1") (pinfunction "1_1") (pintype "passive"))
      (node (ref "R251") (pin "2") (pinfunction "2_2") (pintype "passive"))
      (node (ref "R254") (pin "1") (pinfunction "1_1") (pintype "passive"))
      (node (ref "R255") (pin "1") (pinfunction "1_1") (pintype "passive"))
      (node (ref "R263") (pin "1") (pinfunction "1_1") (pintype "passive"))
      (node (ref "R264") (pin "2") (pinfunction "2_2") (pintype "passive"))
      (node (ref "R268") (pin "2") (pinfunction "2_2") (pintype "passive"))
      (node (ref "R269") (pin "2") (pinfunction "2_2") (pintype "passive"))
      (node (ref "R270") (pin "1") (pinfunction "1_1") (pintype "passive"))
      (node (ref "R283") (pin "1") (pinfunction "1_1") (pintype "passive"))
      (node (ref "R289") (pin "1") (pinfunction "1_1") (pintype "passive"))
      (node (ref "R29") (pin "1") (pinfunction "1_1") (pintype "passive"))
      (node (ref "R293") (pin "1") (pinfunction "1_1") (pintype "passive"))
      (node (ref "R294") (pin "2") (pinfunction "2_2") (pintype "passive"))
      (node (ref "R295") (pin "2") (pinfunction "2_2") (pintype "passive"))
      (node (ref "R297") (pin "2") (pinfunction "2_2") (pintype "passive"))
      (node (ref "R30") (pin "2") (pinfunction "2_2") (pintype "passive"))
      (node (ref "R306") (pin "2") (pinfunction "2_2") (pintype "passive"))
      (node (ref "R309") (pin "1") (pinfunction "1_1") (pintype "passive"))
      (node (ref "R31") (pin "2") (pinfunction "2_2") (pintype "passive"))
      (node (ref "R310") (pin "1") (pinfunction "1_1") (pintype "passive"))
      (node (ref "R318") (pin "1") (pinfunction "1_1") (pintype "passive"))
      (node (ref "R319") (pin "2") (pinfunction "2_2") (pintype "passive"))
      (node (ref "R323") (pin "2") (pinfunction "2_2") (pintype "passive"))
      (node (ref "R324") (pin "2") (pinfunction "2_2") (pintype "passive"))
      (node (ref "R325") (pin "1") (pinfunction "1_1") (pintype "passive"))
      (node (ref "R33") (pin "2") (pinfunction "2_2") (pintype "passive"))
      (node (ref "R4") (pin "1") (pinfunction "1_1") (pintype "passive"))
      (node (ref "R42") (pin "2") (pinfunction "2_2") (pintype "passive"))
      (node (ref "R45") (pin "1") (pinfunction "1_1") (pintype "passive"))
      (node (ref "R46") (pin "1") (pinfunction "1_1") (pintype "passive"))
      (node (ref "R5") (pin "2") (pinfunction "2_2") (pintype "passive"))
      (node (ref "R54") (pin "1") (pinfunction "1_1") (pintype "passive"))
      (node (ref "R55") (pin "2") (pinfunction "2_2") (pintype "passive"))
      (node (ref "R59") (pin "2") (pinfunction "2_2") (pintype "passive"))
      (node (ref "R6") (pin "2") (pinfunction "2_2") (pintype "passive"))
      (node (ref "R60") (pin "2") (pinfunction "2_2") (pintype "passive"))
      (node (ref "R61") (pin "1") (pinfunction "1_1") (pintype "passive"))
      (node (ref "R74") (pin "1") (pinfunction "1_1") (pintype "passive"))
      (node (ref "R80") (pin "1") (pinfunction "1_1") (pintype "passive"))
      (node (ref "R84") (pin "1") (pinfunction "1_1") (pintype "passive"))
      (node (ref "R85") (pin "2") (pinfunction "2_2") (pintype "passive"))
      (node (ref "R86") (pin "2") (pinfunction "2_2") (pintype "passive"))
      (node (ref "R88") (pin "2") (pinfunction "2_2") (pintype "passive"))
      (node (ref "R97") (pin "2") (pinfunction "2_2") (pintype "passive"))
      (node (ref "X1") (pin "13") (pinfunction "13_13") (pintype "passive"))
      (node (ref "X1") (pin "18") (pinfunction "18_18") (pintype "passive"))
      (node (ref "X1") (pin "23") (pinfunction "23_23") (pintype "passive"))
      (node (ref "X10") (pin "13") (pinfunction "13_13") (pintype "passive"))
      (node (ref "X10") (pin "18") (pinfunction "18_18") (pintype "passive"))
      (node (ref "X10") (pin "23") (pinfunction "23_23") (pintype "passive"))
      (node (ref "X101") (pin "13") (pinfunction "13_13") (pintype "passive"))
      (node (ref "X101") (pin "18") (pinfunction "18_18") (pintype "passive"))
      (node (ref "X101") (pin "23") (pinfunction "23_23") (pintype "passive"))
      (node (ref "X102") (pin "1") (pinfunction "S_1") (pintype "passive"))
      (node (ref "X103") (pin "5") (pinfunction "S_5") (pintype "passive"))
      (node (ref "X11") (pin "5") (pinfunction "S_5") (pintype "passive"))
      (node (ref "X12") (pin "1") (pinfunction "S_1") (pintype "passive"))
      (node (ref "X13") (pin "13") (pinfunction "13_13") (pintype "passive"))
      (node (ref "X13") (pin "18") (pinfunction "18_18") (pintype "passive"))
      (node (ref "X13") (pin "23") (pinfunction "23_23") (pintype "passive"))
      (node (ref "X14") (pin "5") (pinfunction "S_5") (pintype "passive"))
      (node (ref "X15") (pin "1") (pinfunction "S_1") (pintype "passive"))
      (node (ref "X2") (pin "5") (pinfunction "S_5") (pintype "passive"))
      (node (ref "X3") (pin "1") (pinfunction "S_1") (pintype "passive"))
      (node (ref "X4") (pin "13") (pinfunction "13_13") (pintype "passive"))
      (node (ref "X4") (pin "18") (pinfunction "18_18") (pintype "passive"))
      (node (ref "X4") (pin "23") (pinfunction "23_23") (pintype "passive"))
      (node (ref "X5") (pin "5") (pinfunction "S_5") (pintype "passive"))
      (node (ref "X6") (pin "1") (pinfunction "S_1") (pintype "passive"))
      (node (ref "X7") (pin "13") (pinfunction "13_13") (pintype "passive"))
      (node (ref "X7") (pin "18") (pinfunction "18_18") (pintype "passive"))
      (node (ref "X7") (pin "23") (pinfunction "23_23") (pintype "passive"))
      (node (ref "X8") (pin "5") (pinfunction "S_5") (pintype "passive"))
      (node (ref "X9") (pin "1") (pinfunction "S_1") (pintype "passive"))
    )
    (net (code "4") (name "Net-(1A-KL)") (class "Default")
      (node (ref "1") (pin "1") (pinfunction "KL_1") (pintype "passive"))
      (node (ref "D2") (pin "2") (pinfunction "-_2") (pintype "passive"))
      (node (ref "TP1") (pin "TP") (pinfunction "PP_TP") (pintype "input"))
    )
    (net (code "5") (name "Net-(1B-KL)") (class "Default")
      (node (ref "1") (pin "10") (pinfunction "KL_10") (pintype "passive"))
      (node (ref "D102") (pin "2") (pinfunction "-_2") (pintype "passive"))
      (node (ref "D103") (pin "2") (pinfunction "-_2") (pintype "passive"))
      (node (ref "JP104") (pin "1") (pinfunction "1_1") (pintype "passive"))
      (node (ref "SJ101") (pin "1") (pinfunction "1_1") (pintype "passive"))
      (node (ref "TP10") (pin "TP") (pinfunction "PP_TP") (pintype "input"))
    )
    (net (code "6") (name "Net-(1C-KL)") (class "Default")
      (node (ref "1") (pin "11") (pinfunction "KL_11") (pintype "passive"))
      (node (ref "D103") (pin "1") (pinfunction "+_1") (pintype "passive"))
      (node (ref "TP11") (pin "TP") (pinfunction "PP_TP") (pintype "input"))
      (node (ref "X101") (pin "19") (pinfunction "19_19") (pintype "passive"))
    )
    (net (code "7") (name "Net-(1E-KL)") (class "Default")
      (node (ref "1") (pin "2") (pinfunction "KL_2") (pintype "passive"))
      (node (ref "Q101") (pin "2") (pinfunction "C_2") (pintype "passive"))
      (node (ref "TP2") (pin "TP") (pinfunction "PP_TP") (pintype "input"))
    )
    (net (code "8") (name "Net-(1F-KL)") (class "Default")
      (node (ref "1") (pin "3") (pinfunction "KL_3") (pintype "passive"))
      (node (ref "IC107") (pin "11") (pinfunction "O6_11") (pintype "open_collector"))
      (node (ref "TP3") (pin "TP") (pinfunction "PP_TP") (pintype "input"))
    )
    (net (code "9") (name "Net-(1G-KL)") (class "Default")
      (node (ref "1") (pin "4") (pinfunction "KL_4") (pintype "passive"))
      (node (ref "IC107") (pin "10") (pinfunction "O7_10") (pintype "open_collector"))
      (node (ref "TP4") (pin "TP") (pinfunction "PP_TP") (pintype "input"))
    )
    (net (code "10") (name "Net-(1H-KL)") (class "Default")
      (node (ref "1") (pin "5") (pinfunction "KL_5") (pintype "passive"))
      (node (ref "IC107") (pin "12") (pinfunction "O5_12") (pintype "open_collector"))
      (node (ref "TP5") (pin "TP") (pinfunction "PP_TP") (pintype "input"))
    )
    (net (code "11") (name "Net-(1I-KL)") (class "Default")
      (node (ref "1") (pin "6") (pinfunction "KL_6") (pintype "passive"))
      (node (ref "IC107") (pin "13") (pinfunction "O4_13") (pintype "open_collector"))
      (node (ref "TP6") (pin "TP") (pinfunction "PP_TP") (pintype "input"))
    )
    (net (code "12") (name "Net-(1J-KL)") (class "Default")
      (node (ref "1") (pin "7") (pinfunction "KL_7") (pintype "passive"))
      (node (ref "IC107") (pin "14") (pinfunction "O3_14") (pintype "open_collector"))
      (node (ref "TP7") (pin "TP") (pinfunction "PP_TP") (pintype "input"))
    )
    (net (code "13") (name "Net-(1K-KL)") (class "Default")
      (node (ref "1") (pin "8") (pinfunction "KL_8") (pintype "passive"))
      (node (ref "R9") (pin "2") (pinfunction "2_2") (pintype "passive"))
      (node (ref "TP8") (pin "TP") (pinfunction "PP_TP") (pintype "input"))
    )
    (net (code "14") (name "Net-(1L-KL)") (class "Default")
      (node (ref "1") (pin "9") (pinfunction "KL_9") (pintype "passive"))
      (node (ref "D102") (pin "1") (pinfunction "+_1") (pintype "passive"))
      (node (ref "TP9") (pin "TP") (pinfunction "PP_TP") (pintype "input"))
      (node (ref "X101") (pin "17") (pinfunction "17_17") (pintype "passive"))
    )
    (net (code "15") (name "Net-(2B-KL)") (class "Default")
      (node (ref "2") (pin "10") (pinfunction "KL_10") (pintype "passive"))
      (node (ref "TP25") (pin "TP") (pinfunction "PP_TP") (pintype "input"))
      (node (ref "X101") (pin "15") (pinfunction "15_15") (pintype "passive"))
    )
    (net (code "16") (name "Net-(2C-KL)") (class "Default")
      (node (ref "2") (pin "11") (pinfunction "KL_11") (pintype "passive"))
      (node (ref "Q103") (pin "2") (pinfunction "C_2") (pintype "passive"))
      (node (ref "R119") (pin "1") (pinfunction "1_1") (pintype "passive"))
      (node (ref "TP26") (pin "TP") (pinfunction "PP_TP") (pintype "input"))
    )
    (net (code "17") (name "Net-(2D-KL)") (class "Default")
      (node (ref "2") (pin "12") (pinfunction "KL_12") (pintype "passive"))
      (node (ref "R146") (pin "1") (pinfunction "1_1") (pintype "passive"))
      (node (ref "TP13") (pin "TP") (pinfunction "PP_TP") (pintype "input"))
    )
    (net (code "18") (name "Net-(2E-KL)") (class "Default")
      (node (ref "2") (pin "2") (pinfunction "KL_2") (pintype "passive"))
      (node (ref "D109") (pin "2") (pinfunction "-_2") (pintype "passive"))
      (node (ref "LED102") (pin "K") (pinfunction "C_K") (pintype "passive"))
      (node (ref "TP16") (pin "TP") (pinfunction "PP_TP") (pintype "input"))
      (node (ref "X101") (pin "12") (pinfunction "12_12") (pintype "passive"))
    )
    (net (code "19") (name "Net-(2F-KL)") (class "Default")
      (node (ref "2") (pin "3") (pinfunction "KL_3") (pintype "passive"))
      (node (ref "D108") (pin "2") (pinfunction "-_2") (pintype "passive"))
      (node (ref "LED103") (pin "K") (pinfunction "C_K") (pintype "passive"))
      (node (ref "TP17") (pin "TP") (pinfunction "PP_TP") (pintype "input"))
      (node (ref "X101") (pin "11") (pinfunction "11_11") (pintype "passive"))
    )
    (net (code "20") (name "Net-(2G-KL)") (class "Default")
      (node (ref "2") (pin "4") (pinfunction "KL_4") (pintype "passive"))
      (node (ref "D107") (pin "2") (pinfunction "-_2") (pintype "passive"))
      (node (ref "LED104") (pin "K") (pinfunction "C_K") (pintype "passive"))
      (node (ref "TP18") (pin "TP") (pinfunction "PP_TP") (pintype "input"))
      (node (ref "X101") (pin "10") (pinfunction "10_10") (pintype "passive"))
    )
    (net (code "21") (name "Net-(2H-KL)") (class "Default")
      (node (ref "2") (pin "5") (pinfunction "KL_5") (pintype "passive"))
      (node (ref "D106") (pin "2") (pinfunction "-_2") (pintype "passive"))
      (node (ref "LED105") (pin "K") (pinfunction "C_K") (pintype "passive"))
      (node (ref "TP19") (pin "TP") (pinfunction "PP_TP") (pintype "input"))
      (node (ref "X101") (pin "9") (pinfunction "9_9") (pintype "passive"))
    )
    (net (code "22") (name "Net-(2I-KL)") (class "Default")
      (node (ref "2") (pin "6") (pinfunction "KL_6") (pintype "passive"))
      (node (ref "JP105") (pin "2") (pinfunction "2_2") (pintype "passive"))
      (node (ref "TP21") (pin "TP") (pinfunction "PP_TP") (pintype "input"))
    )
    (net (code "23") (name "Net-(2J-KL)") (class "Default")
      (node (ref "2") (pin "7") (pinfunction "KL_7") (pintype "passive"))
      (node (ref "LED101") (pin "A") (pinfunction "A_A") (pintype "passive"))
      (node (ref "TP22") (pin "TP") (pinfunction "PP_TP") (pintype "input"))
      (node (ref "X101") (pin "8") (pinfunction "8_8") (pintype "passive"))
    )
    (net (code "24") (name "Net-(2K-KL)") (class "Default")
      (node (ref "2") (pin "8") (pinfunction "KL_8") (pintype "passive"))
      (node (ref "D110") (pin "2") (pinfunction "-_2") (pintype "passive"))
      (node (ref "LED106") (pin "K") (pinfunction "C_K") (pintype "passive"))
      (node (ref "TP23") (pin "TP") (pinfunction "PP_TP") (pintype "input"))
      (node (ref "X101") (pin "14") (pinfunction "14_14") (pintype "passive"))
    )
    (net (code "25") (name "Net-(2L-KL)") (class "Default")
      (node (ref "2") (pin "9") (pinfunction "KL_9") (pintype "passive"))
      (node (ref "D107") (pin "1") (pinfunction "+_1") (pintype "passive"))
      (node (ref "D108") (pin "1") (pinfunction "+_1") (pintype "passive"))
      (node (ref "JP102") (pin "1") (pinfunction "1_1") (pintype "passive"))
      (node (ref "JP103") (pin "2") (pinfunction "2_2") (pintype "passive"))
      (node (ref "TP24") (pin "TP") (pinfunction "PP_TP") (pintype "input"))
    )
    (net (code "26") (name "Net-(3A-KL)") (class "Default")
      (node (ref "3") (pin "1") (pinfunction "KL_1") (pintype "passive"))
      (node (ref "D16") (pin "2") (pinfunction "-_2") (pintype "passive"))
      (node (ref "TP14") (pin "TP") (pinfunction "PP_TP") (pintype "input"))
    )
    (net (code "27") (name "Net-(3B-KL)") (class "Default")
      (node (ref "3") (pin "10") (pinfunction "KL_10") (pintype "passive"))
      (node (ref "D3") (pin "2") (pinfunction "-_2") (pintype "passive"))
      (node (ref "D5") (pin "2") (pinfunction "-_2") (pintype "passive"))
      (node (ref "JP5") (pin "1") (pinfunction "1_1") (pintype "passive"))
      (node (ref "SJ1") (pin "1") (pinfunction "1_1") (pintype "passive"))
      (node (ref "TP33") (pin "TP") (pinfunction "PP_TP") (pintype "input"))
    )
    (net (code "28") (name "Net-(3C-KL)") (class "Default")
      (node (ref "3") (pin "11") (pinfunction "KL_11") (pintype "passive"))
      (node (ref "D5") (pin "1") (pinfunction "+_1") (pintype "passive"))
      (node (ref "TP34") (pin "TP") (pinfunction "PP_TP") (pintype "input"))
      (node (ref "X1") (pin "19") (pinfunction "19_19") (pintype "passive"))
    )
    (net (code "29") (name "Net-(3E-KL)") (class "Default")
      (node (ref "3") (pin "2") (pinfunction "KL_2") (pintype "passive"))
      (node (ref "Q6") (pin "2") (pinfunction "C_2") (pintype "passive"))
      (node (ref "TP15") (pin "TP") (pinfunction "PP_TP") (pintype "input"))
    )
    (net (code "30") (name "Net-(3F-KL)") (class "Default")
      (node (ref "3") (pin "3") (pinfunction "KL_3") (pintype "passive"))
      (node (ref "IC3") (pin "11") (pinfunction "O6_11") (pintype "open_collector"))
      (node (ref "TP20") (pin "TP") (pinfunction "PP_TP") (pintype "input"))
    )
    (net (code "31") (name "Net-(3G-KL)") (class "Default")
      (node (ref "3") (pin "4") (pinfunction "KL_4") (pintype "passive"))
      (node (ref "IC3") (pin "10") (pinfunction "O7_10") (pintype "open_collector"))
      (node (ref "TP27") (pin "TP") (pinfunction "PP_TP") (pintype "input"))
    )
    (net (code "32") (name "Net-(3H-KL)") (class "Default")
      (node (ref "3") (pin "5") (pinfunction "KL_5") (pintype "passive"))
      (node (ref "IC3") (pin "12") (pinfunction "O5_12") (pintype "open_collector"))
      (node (ref "TP28") (pin "TP") (pinfunction "PP_TP") (pintype "input"))
    )
    (net (code "33") (name "Net-(3I-KL)") (class "Default")
      (node (ref "3") (pin "6") (pinfunction "KL_6") (pintype "passive"))
      (node (ref "IC3") (pin "13") (pinfunction "O4_13") (pintype "open_collector"))
      (node (ref "TP29") (pin "TP") (pinfunction "PP_TP") (pintype "input"))
    )
    (net (code "34") (name "Net-(3J-KL)") (class "Default")
      (node (ref "3") (pin "7") (pinfunction "KL_7") (pintype "passive"))
      (node (ref "IC3") (pin "14") (pinfunction "O3_14") (pintype "open_collector"))
      (node (ref "TP30") (pin "TP") (pinfunction "PP_TP") (pintype "input"))
    )
    (net (code "35") (name "Net-(3K-KL)") (class "Default")
      (node (ref "3") (pin "8") (pinfunction "KL_8") (pintype "passive"))
      (node (ref "R62") (pin "2") (pinfunction "2_2") (pintype "passive"))
      (node (ref "TP31") (pin "TP") (pinfunction "PP_TP") (pintype "input"))
    )
    (net (code "36") (name "Net-(3L-KL)") (class "Default")
      (node (ref "3") (pin "9") (pinfunction "KL_9") (pintype "passive"))
      (node (ref "D3") (pin "1") (pinfunction "+_1") (pintype "passive"))
      (node (ref "TP32") (pin "TP") (pinfunction "PP_TP") (pintype "input"))
      (node (ref "X1") (pin "17") (pinfunction "17_17") (pintype "passive"))
    )
    (net (code "37") (name "Net-(4B-KL)") (class "Default")
      (node (ref "4") (pin "10") (pinfunction "KL_10") (pintype "passive"))
      (node (ref "TP43") (pin "TP") (pinfunction "PP_TP") (pintype "input"))
      (node (ref "X1") (pin "15") (pinfunction "15_15") (pintype "passive"))
    )
    (net (code "38") (name "Net-(4C-KL)") (class "Default")
      (node (ref "4") (pin "11") (pinfunction "KL_11") (pintype "passive"))
      (node (ref "Q8") (pin "2") (pinfunction "C_2") (pintype "passive"))
      (node (ref "R48") (pin "1") (pinfunction "1_1") (pintype "passive"))
      (node (ref "TP44") (pin "TP") (pinfunction "PP_TP") (pintype "input"))
    )
    (net (code "39") (name "Net-(4D-KL)") (class "Default")
      (node (ref "4") (pin "12") (pinfunction "KL_12") (pintype "passive"))
      (node (ref "R49") (pin "1") (pinfunction "1_1") (pintype "passive"))
      (node (ref "TP46") (pin "TP") (pinfunction "PP_TP") (pintype "input"))
    )
    (net (code "40") (name "Net-(4E-KL)") (class "Default")
      (node (ref "4") (pin "2") (pinfunction "KL_2") (pintype "passive"))
      (node (ref "D9") (pin "2") (pinfunction "-_2") (pintype "passive"))
      (node (ref "LED1") (pin "K") (pinfunction "C_K") (pintype "passive"))
      (node (ref "TP35") (pin "TP") (pinfunction "PP_TP") (pintype "input"))
      (node (ref "X1") (pin "12") (pinfunction "12_12") (pintype "passive"))
    )
    (net (code "41") (name "Net-(4F-KL)") (class "Default")
      (node (ref "4") (pin "3") (pinfunction "KL_3") (pintype "passive"))
      (node (ref "D8") (pin "2") (pinfunction "-_2") (pintype "passive"))
      (node (ref "LED2") (pin "K") (pinfunction "C_K") (pintype "passive"))
      (node (ref "TP36") (pin "TP") (pinfunction "PP_TP") (pintype "input"))
      (node (ref "X1") (pin "11") (pinfunction "11_11") (pintype "passive"))
    )
    (net (code "42") (name "Net-(4G-KL)") (class "Default")
      (node (ref "4") (pin "4") (pinfunction "KL_4") (pintype "passive"))
      (node (ref "D7") (pin "2") (pinfunction "-_2") (pintype "passive"))
      (node (ref "LED3") (pin "K") (pinfunction "C_K") (pintype "passive"))
      (node (ref "TP37") (pin "TP") (pinfunction "PP_TP") (pintype "input"))
      (node (ref "X1") (pin "10") (pinfunction "10_10") (pintype "passive"))
    )
    (net (code "43") (name "Net-(4H-KL)") (class "Default")
      (node (ref "4") (pin "5") (pinfunction "KL_5") (pintype "passive"))
      (node (ref "D6") (pin "2") (pinfunction "-_2") (pintype "passive"))
      (node (ref "LED4") (pin "K") (pinfunction "C_K") (pintype "passive"))
      (node (ref "TP38") (pin "TP") (pinfunction "PP_TP") (pintype "input"))
      (node (ref "X1") (pin "9") (pinfunction "9_9") (pintype "passive"))
    )
    (net (code "44") (name "Net-(4I-KL)") (class "Default")
      (node (ref "4") (pin "6") (pinfunction "KL_6") (pintype "passive"))
      (node (ref "JP2") (pin "2") (pinfunction "2_2") (pintype "passive"))
      (node (ref "TP39") (pin "TP") (pinfunction "PP_TP") (pintype "input"))
    )
    (net (code "45") (name "Net-(4J-KL)") (class "Default")
      (node (ref "4") (pin "7") (pinfunction "KL_7") (pintype "passive"))
      (node (ref "LED5") (pin "A") (pinfunction "A_A") (pintype "passive"))
      (node (ref "TP40") (pin "TP") (pinfunction "PP_TP") (pintype "input"))
      (node (ref "X1") (pin "8") (pinfunction "8_8") (pintype "passive"))
    )
    (net (code "46") (name "Net-(4K-KL)") (class "Default")
      (node (ref "4") (pin "8") (pinfunction "KL_8") (pintype "passive"))
      (node (ref "D10") (pin "2") (pinfunction "-_2") (pintype "passive"))
      (node (ref "LED6") (pin "K") (pinfunction "C_K") (pintype "passive"))
      (node (ref "TP41") (pin "TP") (pinfunction "PP_TP") (pintype "input"))
      (node (ref "X1") (pin "14") (pinfunction "14_14") (pintype "passive"))
    )
    (net (code "47") (name "Net-(4L-KL)") (class "Default")
      (node (ref "4") (pin "9") (pinfunction "KL_9") (pintype "passive"))
      (node (ref "D7") (pin "1") (pinfunction "+_1") (pintype "passive"))
      (node (ref "D8") (pin "1") (pinfunction "+_1") (pintype "passive"))
      (node (ref "JP3") (pin "1") (pinfunction "1_1") (pintype "passive"))
      (node (ref "JP4") (pin "2") (pinfunction "2_2") (pintype "passive"))
      (node (ref "TP42") (pin "TP") (pinfunction "PP_TP") (pintype "input"))
    )
    (net (code "48") (name "Net-(5A-KL)") (class "Default")
      (node (ref "5") (pin "1") (pinfunction "KL_1") (pintype "passive"))
      (node (ref "D30") (pin "2") (pinfunction "-_2") (pintype "passive"))
      (node (ref "TP47") (pin "TP") (pinfunction "PP_TP") (pintype "input"))
    )
    (net (code "49") (name "Net-(5B-KL)") (class "Default")
      (node (ref "5") (pin "10") (pinfunction "KL_10") (pintype "passive"))
      (node (ref "D18") (pin "2") (pinfunction "-_2") (pintype "passive"))
      (node (ref "D19") (pin "2") (pinfunction "-_2") (pintype "passive"))
      (node (ref "JP10") (pin "1") (pinfunction "1_1") (pintype "passive"))
      (node (ref "SJ4") (pin "1") (pinfunction "1_1") (pintype "passive"))
      (node (ref "TP56") (pin "TP") (pinfunction "PP_TP") (pintype "input"))
    )
    (net (code "50") (name "Net-(5C-KL)") (class "Default")
      (node (ref "5") (pin "11") (pinfunction "KL_11") (pintype "passive"))
      (node (ref "D19") (pin "1") (pinfunction "+_1") (pintype "passive"))
      (node (ref "TP57") (pin "TP") (pinfunction "PP_TP") (pintype "input"))
      (node (ref "X4") (pin "19") (pinfunction "19_19") (pintype "passive"))
    )
    (net (code "51") (name "Net-(5E-KL)") (class "Default")
      (node (ref "5") (pin "2") (pinfunction "KL_2") (pintype "passive"))
      (node (ref "Q16") (pin "2") (pinfunction "C_2") (pintype "passive"))
      (node (ref "TP48") (pin "TP") (pinfunction "PP_TP") (pintype "input"))
    )
    (net (code "52") (name "Net-(5F-KL)") (class "Default")
      (node (ref "5") (pin "3") (pinfunction "KL_3") (pintype "passive"))
      (node (ref "IC12") (pin "11") (pinfunction "O6_11") (pintype "open_collector"))
      (node (ref "TP49") (pin "TP") (pinfunction "PP_TP") (pintype "input"))
    )
    (net (code "53") (name "Net-(5G-KL)") (class "Default")
      (node (ref "5") (pin "4") (pinfunction "KL_4") (pintype "passive"))
      (node (ref "IC12") (pin "10") (pinfunction "O7_10") (pintype "open_collector"))
      (node (ref "TP50") (pin "TP") (pinfunction "PP_TP") (pintype "input"))
    )
    (net (code "54") (name "Net-(5H-KL)") (class "Default")
      (node (ref "5") (pin "5") (pinfunction "KL_5") (pintype "passive"))
      (node (ref "IC12") (pin "12") (pinfunction "O5_12") (pintype "open_collector"))
      (node (ref "TP51") (pin "TP") (pinfunction "PP_TP") (pintype "input"))
    )
    (net (code "55") (name "Net-(5I-KL)") (class "Default")
      (node (ref "5") (pin "6") (pinfunction "KL_6") (pintype "passive"))
      (node (ref "IC12") (pin "13") (pinfunction "O4_13") (pintype "open_collector"))
      (node (ref "TP52") (pin "TP") (pinfunction "PP_TP") (pintype "input"))
    )
    (net (code "56") (name "Net-(5J-KL)") (class "Default")
      (node (ref "5") (pin "7") (pinfunction "KL_7") (pintype "passive"))
      (node (ref "IC12") (pin "14") (pinfunction "O3_14") (pintype "open_collector"))
      (node (ref "TP53") (pin "TP") (pinfunction "PP_TP") (pintype "input"))
    )
    (net (code "57") (name "Net-(5K-KL)") (class "Default")
      (node (ref "5") (pin "8") (pinfunction "KL_8") (pintype "passive"))
      (node (ref "R161") (pin "2") (pinfunction "2_2") (pintype "passive"))
      (node (ref "TP54") (pin "TP") (pinfunction "PP_TP") (pintype "input"))
    )
    (net (code "58") (name "Net-(5L-KL)") (class "Default")
      (node (ref "5") (pin "9") (pinfunction "KL_9") (pintype "passive"))
      (node (ref "D18") (pin "1") (pinfunction "+_1") (pintype "passive"))
      (node (ref "TP55") (pin "TP") (pinfunction "PP_TP") (pintype "input"))
      (node (ref "X4") (pin "17") (pinfunction "17_17") (pintype "passive"))
    )
    (net (code "59") (name "Net-(6B-KL)") (class "Default")
      (node (ref "6") (pin "10") (pinfunction "KL_10") (pintype "passive"))
      (node (ref "TP66") (pin "TP") (pinfunction "PP_TP") (pintype "input"))
      (node (ref "X4") (pin "15") (pinfunction "15_15") (pintype "passive"))
    )
    (net (code "60") (name "Net-(6C-KL)") (class "Default")
      (node (ref "6") (pin "11") (pinfunction "KL_11") (pintype "passive"))
      (node (ref "Q18") (pin "2") (pinfunction "C_2") (pintype "passive"))
      (node (ref "R147") (pin "1") (pinfunction "1_1") (pintype "passive"))
      (node (ref "TP67") (pin "TP") (pinfunction "PP_TP") (pintype "input"))
    )
    (net (code "61") (name "Net-(6D-KL)") (class "Default")
      (node (ref "6") (pin "12") (pinfunction "KL_12") (pintype "passive"))
      (node (ref "R148") (pin "1") (pinfunction "1_1") (pintype "passive"))
      (node (ref "TP69") (pin "TP") (pinfunction "PP_TP") (pintype "input"))
    )
    (net (code "62") (name "Net-(6E-KL)") (class "Default")
      (node (ref "6") (pin "2") (pinfunction "KL_2") (pintype "passive"))
      (node (ref "D23") (pin "2") (pinfunction "-_2") (pintype "passive"))
      (node (ref "LED7") (pin "K") (pinfunction "C_K") (pintype "passive"))
      (node (ref "TP58") (pin "TP") (pinfunction "PP_TP") (pintype "input"))
      (node (ref "X4") (pin "12") (pinfunction "12_12") (pintype "passive"))
    )
    (net (code "63") (name "Net-(6F-KL)") (class "Default")
      (node (ref "6") (pin "3") (pinfunction "KL_3") (pintype "passive"))
      (node (ref "D22") (pin "2") (pinfunction "-_2") (pintype "passive"))
      (node (ref "LED8") (pin "K") (pinfunction "C_K") (pintype "passive"))
      (node (ref "TP59") (pin "TP") (pinfunction "PP_TP") (pintype "input"))
      (node (ref "X4") (pin "11") (pinfunction "11_11") (pintype "passive"))
    )
    (net (code "64") (name "Net-(6G-KL)") (class "Default")
      (node (ref "6") (pin "4") (pinfunction "KL_4") (pintype "passive"))
      (node (ref "D21") (pin "2") (pinfunction "-_2") (pintype "passive"))
      (node (ref "LED9") (pin "K") (pinfunction "C_K") (pintype "passive"))
      (node (ref "TP60") (pin "TP") (pinfunction "PP_TP") (pintype "input"))
      (node (ref "X4") (pin "10") (pinfunction "10_10") (pintype "passive"))
    )
    (net (code "65") (name "Net-(6H-KL)") (class "Default")
      (node (ref "6") (pin "5") (pinfunction "KL_5") (pintype "passive"))
      (node (ref "D20") (pin "2") (pinfunction "-_2") (pintype "passive"))
      (node (ref "LED10") (pin "K") (pinfunction "C_K") (pintype "passive"))
      (node (ref "TP61") (pin "TP") (pinfunction "PP_TP") (pintype "input"))
      (node (ref "X4") (pin "9") (pinfunction "9_9") (pintype "passive"))
    )
    (net (code "66") (name "Net-(6I-KL)") (class "Default")
      (node (ref "6") (pin "6") (pinfunction "KL_6") (pintype "passive"))
      (node (ref "JP7") (pin "2") (pinfunction "2_2") (pintype "passive"))
      (node (ref "TP62") (pin "TP") (pinfunction "PP_TP") (pintype "input"))
    )
    (net (code "67") (name "Net-(6J-KL)") (class "Default")
      (node (ref "6") (pin "7") (pinfunction "KL_7") (pintype "passive"))
      (node (ref "LED11") (pin "A") (pinfunction "A_A") (pintype "passive"))
      (node (ref "TP63") (pin "TP") (pinfunction "PP_TP") (pintype "input"))
      (node (ref "X4") (pin "8") (pinfunction "8_8") (pintype "passive"))
    )
    (net (code "68") (name "Net-(6K-KL)") (class "Default")
      (node (ref "6") (pin "8") (pinfunction "KL_8") (pintype "passive"))
      (node (ref "D24") (pin "2") (pinfunction "-_2") (pintype "passive"))
      (node (ref "LED12") (pin "K") (pinfunction "C_K") (pintype "passive"))
      (node (ref "TP64") (pin "TP") (pinfunction "PP_TP") (pintype "input"))
      (node (ref "X4") (pin "14") (pinfunction "14_14") (pintype "passive"))
    )
    (net (code "69") (name "Net-(6L-KL)") (class "Default")
      (node (ref "6") (pin "9") (pinfunction "KL_9") (pintype "passive"))
      (node (ref "D21") (pin "1") (pinfunction "+_1") (pintype "passive"))
      (node (ref "D22") (pin "1") (pinfunction "+_1") (pintype "passive"))
      (node (ref "JP8") (pin "1") (pinfunction "1_1") (pintype "passive"))
      (node (ref "JP9") (pin "2") (pinfunction "2_2") (pintype "passive"))
      (node (ref "TP65") (pin "TP") (pinfunction "PP_TP") (pintype "input"))
    )
    (net (code "70") (name "Net-(7A-KL)") (class "Default")
      (node (ref "7") (pin "1") (pinfunction "KL_1") (pintype "passive"))
      (node (ref "D44") (pin "2") (pinfunction "-_2") (pintype "passive"))
      (node (ref "TP70") (pin "TP") (pinfunction "PP_TP") (pintype "input"))
    )
    (net (code "71") (name "Net-(7B-KL)") (class "Default")
      (node (ref "7") (pin "10") (pinfunction "KL_10") (pintype "passive"))
      (node (ref "D32") (pin "2") (pinfunction "-_2") (pintype "passive"))
      (node (ref "D33") (pin "2") (pinfunction "-_2") (pintype "passive"))
      (node (ref "JP15") (pin "1") (pinfunction "1_1") (pintype "passive"))
      (node (ref "SJ6") (pin "1") (pinfunction "1_1") (pintype "passive"))
      (node (ref "TP79") (pin "TP") (pinfunction "PP_TP") (pintype "input"))
    )
    (net (code "72") (name "Net-(7C-KL)") (class "Default")
      (node (ref "7") (pin "11") (pinfunction "KL_11") (pintype "passive"))
      (node (ref "D33") (pin "1") (pinfunction "+_1") (pintype "passive"))
      (node (ref "TP80") (pin "TP") (pinfunction "PP_TP") (pintype "input"))
      (node (ref "X7") (pin "19") (pinfunction "19_19") (pintype "passive"))
    )
    (net (code "73") (name "Net-(7E-KL)") (class "Default")
      (node (ref "7") (pin "2") (pinfunction "KL_2") (pintype "passive"))
      (node (ref "Q26") (pin "2") (pinfunction "C_2") (pintype "passive"))
      (node (ref "TP71") (pin "TP") (pinfunction "PP_TP") (pintype "input"))
    )
    (net (code "74") (name "Net-(7F-KL)") (class "Default")
      (node (ref "7") (pin "3") (pinfunction "KL_3") (pintype "passive"))
      (node (ref "IC21") (pin "11") (pinfunction "O6_11") (pintype "open_collector"))
      (node (ref "TP72") (pin "TP") (pinfunction "PP_TP") (pintype "input"))
    )
    (net (code "75") (name "Net-(7G-KL)") (class "Default")
      (node (ref "7") (pin "4") (pinfunction "KL_4") (pintype "passive"))
      (node (ref "IC21") (pin "10") (pinfunction "O7_10") (pintype "open_collector"))
      (node (ref "TP73") (pin "TP") (pinfunction "PP_TP") (pintype "input"))
    )
    (net (code "76") (name "Net-(7H-KL)") (class "Default")
      (node (ref "7") (pin "5") (pinfunction "KL_5") (pintype "passive"))
      (node (ref "IC21") (pin "12") (pinfunction "O5_12") (pintype "open_collector"))
      (node (ref "TP74") (pin "TP") (pinfunction "PP_TP") (pintype "input"))
    )
    (net (code "77") (name "Net-(7I-KL)") (class "Default")
      (node (ref "7") (pin "6") (pinfunction "KL_6") (pintype "passive"))
      (node (ref "IC21") (pin "13") (pinfunction "O4_13") (pintype "open_collector"))
      (node (ref "TP75") (pin "TP") (pinfunction "PP_TP") (pintype "input"))
    )
    (net (code "78") (name "Net-(7J-KL)") (class "Default")
      (node (ref "7") (pin "7") (pinfunction "KL_7") (pintype "passive"))
      (node (ref "IC21") (pin "14") (pinfunction "O3_14") (pintype "open_collector"))
      (node (ref "TP76") (pin "TP") (pinfunction "PP_TP") (pintype "input"))
    )
    (net (code "79") (name "Net-(7K-KL)") (class "Default")
      (node (ref "7") (pin "8") (pinfunction "KL_8") (pintype "passive"))
      (node (ref "R216") (pin "2") (pinfunction "2_2") (pintype "passive"))
      (node (ref "TP77") (pin "TP") (pinfunction "PP_TP") (pintype "input"))
    )
    (net (code "80") (name "Net-(7L-KL)") (class "Default")
      (node (ref "7") (pin "9") (pinfunction "KL_9") (pintype "passive"))
      (node (ref "D32") (pin "1") (pinfunction "+_1") (pintype "passive"))
      (node (ref "TP78") (pin "TP") (pinfunction "PP_TP") (pintype "input"))
      (node (ref "X7") (pin "17") (pinfunction "17_17") (pintype "passive"))
    )
    (net (code "81") (name "Net-(8B-KL)") (class "Default")
      (node (ref "8") (pin "10") (pinfunction "KL_10") (pintype "passive"))
      (node (ref "TP89") (pin "TP") (pinfunction "PP_TP") (pintype "input"))
      (node (ref "X7") (pin "15") (pinfunction "15_15") (pintype "passive"))
    )
    (net (code "82") (name "Net-(8C-KL)") (class "Default")
      (node (ref "8") (pin "11") (pinfunction "KL_11") (pintype "passive"))
      (node (ref "Q28") (pin "2") (pinfunction "C_2") (pintype "passive"))
      (node (ref "R202") (pin "1") (pinfunction "1_1") (pintype "passive"))
      (node (ref "TP90") (pin "TP") (pinfunction "PP_TP") (pintype "input"))
    )
    (net (code "83") (name "Net-(8D-KL)") (class "Default")
      (node (ref "8") (pin "12") (pinfunction "KL_12") (pintype "passive"))
      (node (ref "R203") (pin "1") (pinfunction "1_1") (pintype "passive"))
      (node (ref "TP92") (pin "TP") (pinfunction "PP_TP") (pintype "input"))
    )
    (net (code "84") (name "Net-(8E-KL)") (class "Default")
      (node (ref "8") (pin "2") (pinfunction "KL_2") (pintype "passive"))
      (node (ref "D37") (pin "2") (pinfunction "-_2") (pintype "passive"))
      (node (ref "LED13") (pin "K") (pinfunction "C_K") (pintype "passive"))
      (node (ref "TP81") (pin "TP") (pinfunction "PP_TP") (pintype "input"))
      (node (ref "X7") (pin "12") (pinfunction "12_12") (pintype "passive"))
    )
    (net (code "85") (name "Net-(8F-KL)") (class "Default")
      (node (ref "8") (pin "3") (pinfunction "KL_3") (pintype "passive"))
      (node (ref "D36") (pin "2") (pinfunction "-_2") (pintype "passive"))
      (node (ref "LED14") (pin "K") (pinfunction "C_K") (pintype "passive"))
      (node (ref "TP82") (pin "TP") (pinfunction "PP_TP") (pintype "input"))
      (node (ref "X7") (pin "11") (pinfunction "11_11") (pintype "passive"))
    )
    (net (code "86") (name "Net-(8G-KL)") (class "Default")
      (node (ref "8") (pin "4") (pinfunction "KL_4") (pintype "passive"))
      (node (ref "D35") (pin "2") (pinfunction "-_2") (pintype "passive"))
      (node (ref "LED15") (pin "K") (pinfunction "C_K") (pintype "passive"))
      (node (ref "TP83") (pin "TP") (pinfunction "PP_TP") (pintype "input"))
      (node (ref "X7") (pin "10") (pinfunction "10_10") (pintype "passive"))
    )
    (net (code "87") (name "Net-(8H-KL)") (class "Default")
      (node (ref "8") (pin "5") (pinfunction "KL_5") (pintype "passive"))
      (node (ref "D34") (pin "2") (pinfunction "-_2") (pintype "passive"))
      (node (ref "LED16") (pin "K") (pinfunction "C_K") (pintype "passive"))
      (node (ref "TP84") (pin "TP") (pinfunction "PP_TP") (pintype "input"))
      (node (ref "X7") (pin "9") (pinfunction "9_9") (pintype "passive"))
    )
    (net (code "88") (name "Net-(8I-KL)") (class "Default")
      (node (ref "8") (pin "6") (pinfunction "KL_6") (pintype "passive"))
      (node (ref "JP12") (pin "2") (pinfunction "2_2") (pintype "passive"))
      (node (ref "TP85") (pin "TP") (pinfunction "PP_TP") (pintype "input"))
    )
    (net (code "89") (name "Net-(8J-KL)") (class "Default")
      (node (ref "8") (pin "7") (pinfunction "KL_7") (pintype "passive"))
      (node (ref "LED17") (pin "A") (pinfunction "A_A") (pintype "passive"))
      (node (ref "TP86") (pin "TP") (pinfunction "PP_TP") (pintype "input"))
      (node (ref "X7") (pin "8") (pinfunction "8_8") (pintype "passive"))
    )
    (net (code "90") (name "Net-(8K-KL)") (class "Default")
      (node (ref "8") (pin "8") (pinfunction "KL_8") (pintype "passive"))
      (node (ref "D38") (pin "2") (pinfunction "-_2") (pintype "passive"))
      (node (ref "LED18") (pin "K") (pinfunction "C_K") (pintype "passive"))
      (node (ref "TP87") (pin "TP") (pinfunction "PP_TP") (pintype "input"))
      (node (ref "X7") (pin "14") (pinfunction "14_14") (pintype "passive"))
    )
    (net (code "91") (name "Net-(8L-KL)") (class "Default")
      (node (ref "8") (pin "9") (pinfunction "KL_9") (pintype "passive"))
      (node (ref "D35") (pin "1") (pinfunction "+_1") (pintype "passive"))
      (node (ref "D36") (pin "1") (pinfunction "+_1") (pintype "passive"))
      (node (ref "JP13") (pin "1") (pinfunction "1_1") (pintype "passive"))
      (node (ref "JP14") (pin "2") (pinfunction "2_2") (pintype "passive"))
      (node (ref "TP88") (pin "TP") (pinfunction "PP_TP") (pintype "input"))
    )
    (net (code "92") (name "Net-(9A-KL)") (class "Default")
      (node (ref "9") (pin "1") (pinfunction "KL_1") (pintype "passive"))
      (node (ref "D58") (pin "2") (pinfunction "-_2") (pintype "passive"))
      (node (ref "TP93") (pin "TP") (pinfunction "PP_TP") (pintype "input"))
    )
    (net (code "93") (name "Net-(9B-KL)") (class "Default")
      (node (ref "9") (pin "10") (pinfunction "KL_10") (pintype "passive"))
      (node (ref "D46") (pin "2") (pinfunction "-_2") (pintype "passive"))
      (node (ref "D47") (pin "2") (pinfunction "-_2") (pintype "passive"))
      (node (ref "JP20") (pin "1") (pinfunction "1_1") (pintype "passive"))
      (node (ref "SJ8") (pin "1") (pinfunction "1_1") (pintype "passive"))
      (node (ref "TP102") (pin "TP") (pinfunction "PP_TP") (pintype "input"))
    )
    (net (code "94") (name "Net-(9C-KL)") (class "Default")
      (node (ref "9") (pin "11") (pinfunction "KL_11") (pintype "passive"))
      (node (ref "D47") (pin "1") (pinfunction "+_1") (pintype "passive"))
      (node (ref "TP103") (pin "TP") (pinfunction "PP_TP") (pintype "input"))
      (node (ref "X10") (pin "19") (pinfunction "19_19") (pintype "passive"))
    )
    (net (code "95") (name "Net-(9E-KL)") (class "Default")
      (node (ref "9") (pin "2") (pinfunction "KL_2") (pintype "passive"))
      (node (ref "Q36") (pin "2") (pinfunction "C_2") (pintype "passive"))
      (node (ref "TP94") (pin "TP") (pinfunction "PP_TP") (pintype "input"))
    )
    (net (code "96") (name "Net-(9F-KL)") (class "Default")
      (node (ref "9") (pin "3") (pinfunction "KL_3") (pintype "passive"))
      (node (ref "IC30") (pin "11") (pinfunction "O6_11") (pintype "open_collector"))
      (node (ref "TP95") (pin "TP") (pinfunction "PP_TP") (pintype "input"))
    )
    (net (code "97") (name "Net-(9G-KL)") (class "Default")
      (node (ref "9") (pin "4") (pinfunction "KL_4") (pintype "passive"))
      (node (ref "IC30") (pin "10") (pinfunction "O7_10") (pintype "open_collector"))
      (node (ref "TP96") (pin "TP") (pinfunction "PP_TP") (pintype "input"))
    )
    (net (code "98") (name "Net-(9H-KL)") (class "Default")
      (node (ref "9") (pin "5") (pinfunction "KL_5") (pintype "passive"))
      (node (ref "IC30") (pin "12") (pinfunction "O5_12") (pintype "open_collector"))
      (node (ref "TP97") (pin "TP") (pinfunction "PP_TP") (pintype "input"))
    )
    (net (code "99") (name "Net-(9I-KL)") (class "Default")
      (node (ref "9") (pin "6") (pinfunction "KL_6") (pintype "passive"))
      (node (ref "IC30") (pin "13") (pinfunction "O4_13") (pintype "open_collector"))
      (node (ref "TP98") (pin "TP") (pinfunction "PP_TP") (pintype "input"))
    )
    (net (code "100") (name "Net-(9J-KL)") (class "Default")
      (node (ref "9") (pin "7") (pinfunction "KL_7") (pintype "passive"))
      (node (ref "IC30") (pin "14") (pinfunction "O3_14") (pintype "open_collector"))
      (node (ref "TP99") (pin "TP") (pinfunction "PP_TP") (pintype "input"))
    )
    (net (code "101") (name "Net-(9K-KL)") (class "Default")
      (node (ref "9") (pin "8") (pinfunction "KL_8") (pintype "passive"))
      (node (ref "R271") (pin "2") (pinfunction "2_2") (pintype "passive"))
      (node (ref "TP100") (pin "TP") (pinfunction "PP_TP") (pintype "input"))
    )
    (net (code "102") (name "Net-(9L-KL)") (class "Default")
      (node (ref "9") (pin "9") (pinfunction "KL_9") (pintype "passive"))
      (node (ref "D46") (pin "1") (pinfunction "+_1") (pintype "passive"))
      (node (ref "TP101") (pin "TP") (pinfunction "PP_TP") (pintype "input"))
      (node (ref "X10") (pin "17") (pinfunction "17_17") (pintype "passive"))
    )
    (net (code "103") (name "Net-(10B-KL)") (class "Default")
      (node (ref "10") (pin "10") (pinfunction "KL_10") (pintype "passive"))
      (node (ref "TP112") (pin "TP") (pinfunction "PP_TP") (pintype "input"))
      (node (ref "X10") (pin "15") (pinfunction "15_15") (pintype "passive"))
    )
    (net (code "104") (name "Net-(10C-KL)") (class "Default")
      (node (ref "10") (pin "11") (pinfunction "KL_11") (pintype "passive"))
      (node (ref "Q38") (pin "2") (pinfunction "C_2") (pintype "passive"))
      (node (ref "R257") (pin "1") (pinfunction "1_1") (pintype "passive"))
      (node (ref "TP113") (pin "TP") (pinfunction "PP_TP") (pintype "input"))
    )
    (net (code "105") (name "Net-(10D-KL)") (class "Default")
      (node (ref "10") (pin "12") (pinfunction "KL_12") (pintype "passive"))
      (node (ref "R258") (pin "1") (pinfunction "1_1") (pintype "passive"))
      (node (ref "TP115") (pin "TP") (pinfunction "PP_TP") (pintype "input"))
    )
    (net (code "106") (name "Net-(10E-KL)") (class "Default")
      (node (ref "10") (pin "2") (pinfunction "KL_2") (pintype "passive"))
      (node (ref "D51") (pin "2") (pinfunction "-_2") (pintype "passive"))
      (node (ref "LED19") (pin "K") (pinfunction "C_K") (pintype "passive"))
      (node (ref "TP104") (pin "TP") (pinfunction "PP_TP") (pintype "input"))
      (node (ref "X10") (pin "12") (pinfunction "12_12") (pintype "passive"))
    )
    (net (code "107") (name "Net-(10F-KL)") (class "Default")
      (node (ref "10") (pin "3") (pinfunction "KL_3") (pintype "passive"))
      (node (ref "D50") (pin "2") (pinfunction "-_2") (pintype "passive"))
      (node (ref "LED20") (pin "K") (pinfunction "C_K") (pintype "passive"))
      (node (ref "TP105") (pin "TP") (pinfunction "PP_TP") (pintype "input"))
      (node (ref "X10") (pin "11") (pinfunction "11_11") (pintype "passive"))
    )
    (net (code "108") (name "Net-(10G-KL)") (class "Default")
      (node (ref "10") (pin "4") (pinfunction "KL_4") (pintype "passive"))
      (node (ref "D49") (pin "2") (pinfunction "-_2") (pintype "passive"))
      (node (ref "LED21") (pin "K") (pinfunction "C_K") (pintype "passive"))
      (node (ref "TP106") (pin "TP") (pinfunction "PP_TP") (pintype "input"))
      (node (ref "X10") (pin "10") (pinfunction "10_10") (pintype "passive"))
    )
    (net (code "109") (name "Net-(10H-KL)") (class "Default")
      (node (ref "10") (pin "5") (pinfunction "KL_5") (pintype "passive"))
      (node (ref "D48") (pin "2") (pinfunction "-_2") (pintype "passive"))
      (node (ref "LED22") (pin "K") (pinfunction "C_K") (pintype "passive"))
      (node (ref "TP107") (pin "TP") (pinfunction "PP_TP") (pintype "input"))
      (node (ref "X10") (pin "9") (pinfunction "9_9") (pintype "passive"))
    )
    (net (code "110") (name "Net-(10I-KL)") (class "Default")
      (node (ref "10") (pin "6") (pinfunction "KL_6") (pintype "passive"))
      (node (ref "JP17") (pin "2") (pinfunction "2_2") (pintype "passive"))
      (node (ref "TP108") (pin "TP") (pinfunction "PP_TP") (pintype "input"))
    )
    (net (code "111") (name "Net-(10J-KL)") (class "Default")
      (node (ref "10") (pin "7") (pinfunction "KL_7") (pintype "passive"))
      (node (ref "LED23") (pin "A") (pinfunction "A_A") (pintype "passive"))
      (node (ref "TP109") (pin "TP") (pinfunction "PP_TP") (pintype "input"))
      (node (ref "X10") (pin "8") (pinfunction "8_8") (pintype "passive"))
    )
    (net (code "112") (name "Net-(10K-KL)") (class "Default")
      (node (ref "10") (pin "8") (pinfunction "KL_8") (pintype "passive"))
      (node (ref "D52") (pin "2") (pinfunction "-_2") (pintype "passive"))
      (node (ref "LED24") (pin "K") (pinfunction "C_K") (pintype "passive"))
      (node (ref "TP110") (pin "TP") (pinfunction "PP_TP") (pintype "input"))
      (node (ref "X10") (pin "14") (pinfunction "14_14") (pintype "passive"))
    )
    (net (code "113") (name "Net-(10L-KL)") (class "Default")
      (node (ref "10") (pin "9") (pinfunction "KL_9") (pintype "passive"))
      (node (ref "D49") (pin "1") (pinfunction "+_1") (pintype "passive"))
      (node (ref "D50") (pin "1") (pinfunction "+_1") (pintype "passive"))
      (node (ref "JP18") (pin "1") (pinfunction "1_1") (pintype "passive"))
      (node (ref "JP19") (pin "2") (pinfunction "2_2") (pintype "passive"))
      (node (ref "TP111") (pin "TP") (pinfunction "PP_TP") (pintype "input"))
    )
    (net (code "114") (name "Net-(11A-KL)") (class "Default")
      (node (ref "11") (pin "1") (pinfunction "KL_1") (pintype "passive"))
      (node (ref "D72") (pin "2") (pinfunction "-_2") (pintype "passive"))
      (node (ref "TP116") (pin "TP") (pinfunction "PP_TP") (pintype "input"))
    )
    (net (code "115") (name "Net-(11B-KL)") (class "Default")
      (node (ref "11") (pin "10") (pinfunction "KL_10") (pintype "passive"))
      (node (ref "D60") (pin "2") (pinfunction "-_2") (pintype "passive"))
      (node (ref "D61") (pin "2") (pinfunction "-_2") (pintype "passive"))
      (node (ref "JP25") (pin "1") (pinfunction "1_1") (pintype "passive"))
      (node (ref "SJ10") (pin "1") (pinfunction "1_1") (pintype "passive"))
      (node (ref "TP125") (pin "TP") (pinfunction "PP_TP") (pintype "input"))
    )
    (net (code "116") (name "Net-(11C-KL)") (class "Default")
      (node (ref "11") (pin "11") (pinfunction "KL_11") (pintype "passive"))
      (node (ref "D61") (pin "1") (pinfunction "+_1") (pintype "passive"))
      (node (ref "TP126") (pin "TP") (pinfunction "PP_TP") (pintype "input"))
      (node (ref "X13") (pin "19") (pinfunction "19_19") (pintype "passive"))
    )
    (net (code "117") (name "Net-(11E-KL)") (class "Default")
      (node (ref "11") (pin "2") (pinfunction "KL_2") (pintype "passive"))
      (node (ref "Q46") (pin "2") (pinfunction "C_2") (pintype "passive"))
      (node (ref "TP117") (pin "TP") (pinfunction "PP_TP") (pintype "input"))
    )
    (net (code "118") (name "Net-(11F-KL)") (class "Default")
      (node (ref "11") (pin "3") (pinfunction "KL_3") (pintype "passive"))
      (node (ref "IC39") (pin "11") (pinfunction "O6_11") (pintype "open_collector"))
      (node (ref "TP118") (pin "TP") (pinfunction "PP_TP") (pintype "input"))
    )
    (net (code "119") (name "Net-(11G-KL)") (class "Default")
      (node (ref "11") (pin "4") (pinfunction "KL_4") (pintype "passive"))
      (node (ref "IC39") (pin "10") (pinfunction "O7_10") (pintype "open_collector"))
      (node (ref "TP119") (pin "TP") (pinfunction "PP_TP") (pintype "input"))
    )
    (net (code "120") (name "Net-(11H-KL)") (class "Default")
      (node (ref "11") (pin "5") (pinfunction "KL_5") (pintype "passive"))
      (node (ref "IC39") (pin "12") (pinfunction "O5_12") (pintype "open_collector"))
      (node (ref "TP120") (pin "TP") (pinfunction "PP_TP") (pintype "input"))
    )
    (net (code "121") (name "Net-(11I-KL)") (class "Default")
      (node (ref "11") (pin "6") (pinfunction "KL_6") (pintype "passive"))
      (node (ref "IC39") (pin "13") (pinfunction "O4_13") (pintype "open_collector"))
      (node (ref "TP121") (pin "TP") (pinfunction "PP_TP") (pintype "input"))
    )
    (net (code "122") (name "Net-(11J-KL)") (class "Default")
      (node (ref "11") (pin "7") (pinfunction "KL_7") (pintype "passive"))
      (node (ref "IC39") (pin "14") (pinfunction "O3_14") (pintype "open_collector"))
      (node (ref "TP122") (pin "TP") (pinfunction "PP_TP") (pintype "input"))
    )
    (net (code "123") (name "Net-(11K-KL)") (class "Default")
      (node (ref "11") (pin "8") (pinfunction "KL_8") (pintype "passive"))
      (node (ref "R326") (pin "2") (pinfunction "2_2") (pintype "passive"))
      (node (ref "TP123") (pin "TP") (pinfunction "PP_TP") (pintype "input"))
    )
    (net (code "124") (name "Net-(11L-KL)") (class "Default")
      (node (ref "11") (pin "9") (pinfunction "KL_9") (pintype "passive"))
      (node (ref "D60") (pin "1") (pinfunction "+_1") (pintype "passive"))
      (node (ref "TP124") (pin "TP") (pinfunction "PP_TP") (pintype "input"))
      (node (ref "X13") (pin "17") (pinfunction "17_17") (pintype "passive"))
    )
    (net (code "125") (name "Net-(12B-KL)") (class "Default")
      (node (ref "12") (pin "10") (pinfunction "KL_10") (pintype "passive"))
      (node (ref "TP135") (pin "TP") (pinfunction "PP_TP") (pintype "input"))
      (node (ref "X13") (pin "15") (pinfunction "15_15") (pintype "passive"))
    )
    (net (code "126") (name "Net-(12C-KL)") (class "Default")
      (node (ref "12") (pin "11") (pinfunction "KL_11") (pintype "passive"))
      (node (ref "Q48") (pin "2") (pinfunction "C_2") (pintype "passive"))
      (node (ref "R312") (pin "1") (pinfunction "1_1") (pintype "passive"))
      (node (ref "TP136") (pin "TP") (pinfunction "PP_TP") (pintype "input"))
    )
    (net (code "127") (name "Net-(12D-KL)") (class "Default")
      (node (ref "12") (pin "12") (pinfunction "KL_12") (pintype "passive"))
      (node (ref "R313") (pin "1") (pinfunction "1_1") (pintype "passive"))
      (node (ref "TP138") (pin "TP") (pinfunction "PP_TP") (pintype "input"))
    )
    (net (code "128") (name "Net-(12E-KL)") (class "Default")
      (node (ref "12") (pin "2") (pinfunction "KL_2") (pintype "passive"))
      (node (ref "D65") (pin "2") (pinfunction "-_2") (pintype "passive"))
      (node (ref "LED25") (pin "K") (pinfunction "C_K") (pintype "passive"))
      (node (ref "TP127") (pin "TP") (pinfunction "PP_TP") (pintype "input"))
      (node (ref "X13") (pin "12") (pinfunction "12_12") (pintype "passive"))
    )
    (net (code "129") (name "Net-(12F-KL)") (class "Default")
      (node (ref "12") (pin "3") (pinfunction "KL_3") (pintype "passive"))
      (node (ref "D64") (pin "2") (pinfunction "-_2") (pintype "passive"))
      (node (ref "LED26") (pin "K") (pinfunction "C_K") (pintype "passive"))
      (node (ref "TP128") (pin "TP") (pinfunction "PP_TP") (pintype "input"))
      (node (ref "X13") (pin "11") (pinfunction "11_11") (pintype "passive"))
    )
    (net (code "130") (name "Net-(12G-KL)") (class "Default")
      (node (ref "12") (pin "4") (pinfunction "KL_4") (pintype "passive"))
      (node (ref "D63") (pin "2") (pinfunction "-_2") (pintype "passive"))
      (node (ref "LED27") (pin "K") (pinfunction "C_K") (pintype "passive"))
      (node (ref "TP129") (pin "TP") (pinfunction "PP_TP") (pintype "input"))
      (node (ref "X13") (pin "10") (pinfunction "10_10") (pintype "passive"))
    )
    (net (code "131") (name "Net-(12H-KL)") (class "Default")
      (node (ref "12") (pin "5") (pinfunction "KL_5") (pintype "passive"))
      (node (ref "D62") (pin "2") (pinfunction "-_2") (pintype "passive"))
      (node (ref "LED28") (pin "K") (pinfunction "C_K") (pintype "passive"))
      (node (ref "TP130") (pin "TP") (pinfunction "PP_TP") (pintype "input"))
      (node (ref "X13") (pin "9") (pinfunction "9_9") (pintype "passive"))
    )
    (net (code "132") (name "Net-(12I-KL)") (class "Default")
      (node (ref "12") (pin "6") (pinfunction "KL_6") (pintype "passive"))
      (node (ref "JP22") (pin "2") (pinfunction "2_2") (pintype "passive"))
      (node (ref "TP131") (pin "TP") (pinfunction "PP_TP") (pintype "input"))
    )
    (net (code "133") (name "Net-(12J-KL)") (class "Default")
      (node (ref "12") (pin "7") (pinfunction "KL_7") (pintype "passive"))
      (node (ref "LED29") (pin "A") (pinfunction "A_A") (pintype "passive"))
      (node (ref "TP132") (pin "TP") (pinfunction "PP_TP") (pintype "input"))
      (node (ref "X13") (pin "8") (pinfunction "8_8") (pintype "passive"))
    )
    (net (code "134") (name "Net-(12K-KL)") (class "Default")
      (node (ref "12") (pin "8") (pinfunction "KL_8") (pintype "passive"))
      (node (ref "D66") (pin "2") (pinfunction "-_2") (pintype "passive"))
      (node (ref "LED30") (pin "K") (pinfunction "C_K") (pintype "passive"))
      (node (ref "TP133") (pin "TP") (pinfunction "PP_TP") (pintype "input"))
      (node (ref "X13") (pin "14") (pinfunction "14_14") (pintype "passive"))
    )
    (net (code "135") (name "Net-(12L-KL)") (class "Default")
      (node (ref "12") (pin "9") (pinfunction "KL_9") (pintype "passive"))
      (node (ref "D63") (pin "1") (pinfunction "+_1") (pintype "passive"))
      (node (ref "D64") (pin "1") (pinfunction "+_1") (pintype "passive"))
      (node (ref "JP23") (pin "1") (pinfunction "1_1") (pintype "passive"))
      (node (ref "JP24") (pin "2") (pinfunction "2_2") (pintype "passive"))
      (node (ref "TP134") (pin "TP") (pinfunction "PP_TP") (pintype "input"))
    )
    (net (code "136") (name "Net-(C1-Pad1)") (class "Default")
      (node (ref "C1") (pin "1") (pinfunction "1_1") (pintype "passive"))
      (node (ref "R22") (pin "1") (pinfunction "1_1") (pintype "passive"))
      (node (ref "R23") (pin "2") (pinfunction "2_2") (pintype "passive"))
    )
    (net (code "137") (name "Net-(C11-Pad1)") (class "Default")
      (node (ref "C11") (pin "1") (pinfunction "1_1") (pintype "passive"))
      (node (ref "R50") (pin "1") (pinfunction "1_1") (pintype "passive"))
      (node (ref "R51") (pin "1") (pinfunction "1_1") (pintype "passive"))
    )
    (net (code "138") (name "Net-(C14-Pad1)") (class "Default")
      (node (ref "C14") (pin "1") (pinfunction "1_1") (pintype "passive"))
      (node (ref "R77") (pin "1") (pinfunction "1_1") (pintype "passive"))
      (node (ref "R78") (pin "2") (pinfunction "2_2") (pintype "passive"))
    )
    (net (code "139") (name "Net-(C24-Pad1)") (class "Default")
      (node (ref "C24") (pin "1") (pinfunction "1_1") (pintype "passive"))
      (node (ref "R149") (pin "1") (pinfunction "1_1") (pintype "passive"))
      (node (ref "R150") (pin "1") (pinfunction "1_1") (pintype "passive"))
    )
    (net (code "140") (name "Net-(C27-Pad1)") (class "Default")
      (node (ref "C27") (pin "1") (pinfunction "1_1") (pintype "passive"))
      (node (ref "R176") (pin "1") (pinfunction "1_1") (pintype "passive"))
      (node (ref "R177") (pin "2") (pinfunction "2_2") (pintype "passive"))
    )
    (net (code "141") (name "Net-(C36-Pad1)") (class "Default")
      (node (ref "C36") (pin "1") (pinfunction "1_1") (pintype "passive"))
      (node (ref "R204") (pin "1") (pinfunction "1_1") (pintype "passive"))
      (node (ref "R205") (pin "1") (pinfunction "1_1") (pintype "passive"))
    )
    (net (code "142") (name "Net-(C39-Pad1)") (class "Default")
      (node (ref "C39") (pin "1") (pinfunction "1_1") (pintype "passive"))
      (node (ref "R231") (pin "1") (pinfunction "1_1") (pintype "passive"))
      (node (ref "R232") (pin "2") (pinfunction "2_2") (pintype "passive"))
    )
    (net (code "143") (name "Net-(C48-Pad1)") (class "Default")
      (node (ref "C48") (pin "1") (pinfunction "1_1") (pintype "passive"))
      (node (ref "R259") (pin "1") (pinfunction "1_1") (pintype "passive"))
      (node (ref "R260") (pin "1") (pinfunction "1_1") (pintype "passive"))
    )
    (net (code "144") (name "Net-(C51-Pad1)") (class "Default")
      (node (ref "C51") (pin "1") (pinfunction "1_1") (pintype "passive"))
      (node (ref "R286") (pin "1") (pinfunction "1_1") (pintype "passive"))
      (node (ref "R287") (pin "2") (pinfunction "2_2") (pintype "passive"))
    )
    (net (code "145") (name "Net-(C60-Pad1)") (class "Default")
      (node (ref "C60") (pin "1") (pinfunction "1_1") (pintype "passive"))
      (node (ref "R314") (pin "1") (pinfunction "1_1") (pintype "passive"))
      (node (ref "R315") (pin "1") (pinfunction "1_1") (pintype "passive"))
    )
    (net (code "146") (name "Net-(C103-Pad1)") (class "Default")
      (node (ref "C103") (pin "1") (pinfunction "1_1") (pintype "passive"))
      (node (ref "R108") (pin "1") (pinfunction "1_1") (pintype "passive"))
      (node (ref "R112") (pin "1") (pinfunction "1_1") (pintype "passive"))
    )
    (net (code "147") (name "Net-(C107-Pad1)") (class "Default")
      (node (ref "C107") (pin "1") (pinfunction "1_1") (pintype "passive"))
      (node (ref "R125") (pin "1") (pinfunction "1_1") (pintype "passive"))
      (node (ref "R130") (pin "2") (pinfunction "2_2") (pintype "passive"))
    )
    (net (code "148") (name "Net-(D1--)") (class "Default")
      (node (ref "D1") (pin "2") (pinfunction "-_2") (pintype "passive"))
      (node (ref "R12") (pin "1") (pinfunction "1_1") (pintype "passive"))
      (node (ref "R13") (pin "1") (pinfunction "1_1") (pintype "passive"))
    )
    (net (code "149") (name "Net-(D2-+)") (class "Default")
      (node (ref "D2") (pin "1") (pinfunction "+_1") (pintype "passive"))
      (node (ref "X101") (pin "1") (pinfunction "1_1") (pintype "passive"))
    )
    (net (code "150") (name "Net-(D6-+)") (class "Default")
      (node (ref "D6") (pin "1") (pinfunction "+_1") (pintype "passive"))
      (node (ref "R7") (pin "1") (pinfunction "1_1") (pintype "passive"))
    )
    (net (code "151") (name "Net-(D9-+)") (class "Default")
      (node (ref "D9") (pin "1") (pinfunction "+_1") (pintype "passive"))
      (node (ref "JP3") (pin "2") (pinfunction "2_2") (pintype "passive"))
    )
    (net (code "152") (name "Net-(D10-+)") (class "Default")
      (node (ref "D10") (pin "1") (pinfunction "+_1") (pintype "passive"))
      (node (ref "JP4") (pin "1") (pinfunction "1_1") (pintype "passive"))
    )
    (net (code "153") (name "Net-(D11--)") (class "Default")
      (node (ref "D11") (pin "2") (pinfunction "-_2") (pintype "passive"))
      (node (ref "Q4") (pin "2") (pinfunction "C_2") (pintype "passive"))
      (node (ref "START1") (pin "TP") (pinfunction "PP_TP") (pintype "input"))
      (node (ref "X1") (pin "5") (pinfunction "5_5") (pintype "passive"))
    )
    (net (code "154") (name "Net-(D12-+)") (class "Default")
      (node (ref "D12") (pin "1") (pinfunction "+_1") (pintype "passive"))
      (node (ref "R44") (pin "1") (pinfunction "1_1") (pintype "passive"))
    )
    (net (code "155") (name "Net-(D12--)") (class "Default")
      (node (ref "C8") (pin "2") (pinfunction "2_2") (pintype "passive"))
      (node (ref "D12") (pin "2") (pinfunction "-_2") (pintype "passive"))
      (node (ref "D17") (pin "C") (pinfunction "C_C") (pintype "passive"))
      (node (ref "IC6") (pin "2") (pinfunction "TR_2") (pintype "input"))
      (node (ref "IC6") (pin "6") (pinfunction "THR_6") (pintype "input"))
      (node (ref "R42") (pin "1") (pinfunction "1_1") (pintype "passive"))
    )
    (net (code "156") (name "Net-(D14-PadC)") (class "Default")
      (node (ref "D14") (pin "C") (pinfunction "C_C") (pintype "passive"))
      (node (ref "R18") (pin "2") (pinfunction "2_2") (pintype "passive"))
      (node (ref "X1") (pin "22") (pinfunction "22_22") (pintype "passive"))
    )
    (net (code "157") (name "Net-(D15--)") (class "Default")
      (node (ref "D15") (pin "2") (pinfunction "-_2") (pintype "passive"))
      (node (ref "R65") (pin "1") (pinfunction "1_1") (pintype "passive"))
      (node (ref "R66") (pin "1") (pinfunction "1_1") (pintype "passive"))
    )
    (net (code "158") (name "Net-(D16-+)") (class "Default")
      (node (ref "D16") (pin "1") (pinfunction "+_1") (pintype "passive"))
      (node (ref "X1") (pin "1") (pinfunction "1_1") (pintype "passive"))
    )
    (net (code "159") (name "Net-(D20-+)") (class "Default")
      (node (ref "D20") (pin "1") (pinfunction "+_1") (pintype "passive"))
      (node (ref "R67") (pin "1") (pinfunction "1_1") (pintype "passive"))
    )
    (net (code "160") (name "Net-(D23-+)") (class "Default")
      (node (ref "D23") (pin "1") (pinfunction "+_1") (pintype "passive"))
      (node (ref "JP8") (pin "2") (pinfunction "2_2") (pintype "passive"))
    )
    (net (code "161") (name "Net-(D24-+)") (class "Default")
      (node (ref "D24") (pin "1") (pinfunction "+_1") (pintype "passive"))
      (node (ref "JP9") (pin "1") (pinfunction "1_1") (pintype "passive"))
    )
    (net (code "162") (name "Net-(D25--)") (class "Default")
      (node (ref "D25") (pin "2") (pinfunction "-_2") (pintype "passive"))
      (node (ref "Q14") (pin "2") (pinfunction "C_2") (pintype "passive"))
      (node (ref "START2") (pin "TP") (pinfunction "PP_TP") (pintype "input"))
      (node (ref "X4") (pin "5") (pinfunction "5_5") (pintype "passive"))
    )
    (net (code "163") (name "Net-(D26-+)") (class "Default")
      (node (ref "D26") (pin "1") (pinfunction "+_1") (pintype "passive"))
      (node (ref "R99") (pin "1") (pinfunction "1_1") (pintype "passive"))
    )
    (net (code "164") (name "Net-(D26--)") (class "Default")
      (node (ref "C21") (pin "2") (pinfunction "2_2") (pintype "passive"))
      (node (ref "D26") (pin "2") (pinfunction "-_2") (pintype "passive"))
      (node (ref "D31") (pin "C") (pinfunction "C_C") (pintype "passive"))
      (node (ref "IC15") (pin "2") (pinfunction "TR_2") (pintype "input"))
      (node (ref "IC15") (pin "6") (pinfunction "THR_6") (pintype "input"))
      (node (ref "R97") (pin "1") (pinfunction "1_1") (pintype "passive"))
    )
    (net (code "165") (name "Net-(D28-PadC)") (class "Default")
      (node (ref "D28") (pin "C") (pinfunction "C_C") (pintype "passive"))
      (node (ref "R73") (pin "2") (pinfunction "2_2") (pintype "passive"))
      (node (ref "X4") (pin "22") (pinfunction "22_22") (pintype "passive"))
    )
    (net (code "166") (name "Net-(D29--)") (class "Default")
      (node (ref "D29") (pin "2") (pinfunction "-_2") (pintype "passive"))
      (node (ref "R164") (pin "1") (pinfunction "1_1") (pintype "passive"))
      (node (ref "R165") (pin "1") (pinfunction "1_1") (pintype "passive"))
    )
    (net (code "167") (name "Net-(D30-+)") (class "Default")
      (node (ref "D30") (pin "1") (pinfunction "+_1") (pintype "passive"))
      (node (ref "X4") (pin "1") (pinfunction "1_1") (pintype "passive"))
    )
    (net (code "168") (name "Net-(D34-+)") (class "Default")
      (node (ref "D34") (pin "1") (pinfunction "+_1") (pintype "passive"))
      (node (ref "R166") (pin "1") (pinfunction "1_1") (pintype "passive"))
    )
    (net (code "169") (name "Net-(D37-+)") (class "Default")
      (node (ref "D37") (pin "1") (pinfunction "+_1") (pintype "passive"))
      (node (ref "JP13") (pin "2") (pinfunction "2_2") (pintype "passive"))
    )
    (net (code "170") (name "Net-(D38-+)") (class "Default")
      (node (ref "D38") (pin "1") (pinfunction "+_1") (pintype "passive"))
      (node (ref "JP14") (pin "1") (pinfunction "1_1") (pintype "passive"))
    )
    (net (code "171") (name "Net-(D39--)") (class "Default")
      (node (ref "D39") (pin "2") (pinfunction "-_2") (pintype "passive"))
      (node (ref "Q24") (pin "2") (pinfunction "C_2") (pintype "passive"))
      (node (ref "START3") (pin "TP") (pinfunction "PP_TP") (pintype "input"))
      (node (ref "X7") (pin "5") (pinfunction "5_5") (pintype "passive"))
    )
    (net (code "172") (name "Net-(D40-+)") (class "Default")
      (node (ref "D40") (pin "1") (pinfunction "+_1") (pintype "passive"))
      (node (ref "R198") (pin "1") (pinfunction "1_1") (pintype "passive"))
    )
    (net (code "173") (name "Net-(D40--)") (class "Default")
      (node (ref "C33") (pin "2") (pinfunction "2_2") (pintype "passive"))
      (node (ref "D40") (pin "2") (pinfunction "-_2") (pintype "passive"))
      (node (ref "D45") (pin "C") (pinfunction "C_C") (pintype "passive"))
      (node (ref "IC24") (pin "2") (pinfunction "TR_2") (pintype "input"))
      (node (ref "IC24") (pin "6") (pinfunction "THR_6") (pintype "input"))
      (node (ref "R196") (pin "1") (pinfunction "1_1") (pintype "passive"))
    )
    (net (code "174") (name "Net-(D42-PadC)") (class "Default")
      (node (ref "D42") (pin "C") (pinfunction "C_C") (pintype "passive"))
      (node (ref "R172") (pin "2") (pinfunction "2_2") (pintype "passive"))
      (node (ref "X7") (pin "22") (pinfunction "22_22") (pintype "passive"))
    )
    (net (code "175") (name "Net-(D43--)") (class "Default")
      (node (ref "D43") (pin "2") (pinfunction "-_2") (pintype "passive"))
      (node (ref "R219") (pin "1") (pinfunction "1_1") (pintype "passive"))
      (node (ref "R220") (pin "1") (pinfunction "1_1") (pintype "passive"))
    )
    (net (code "176") (name "Net-(D44-+)") (class "Default")
      (node (ref "D44") (pin "1") (pinfunction "+_1") (pintype "passive"))
      (node (ref "X7") (pin "1") (pinfunction "1_1") (pintype "passive"))
    )
    (net (code "177") (name "Net-(D48-+)") (class "Default")
      (node (ref "D48") (pin "1") (pinfunction "+_1") (pintype "passive"))
      (node (ref "R221") (pin "1") (pinfunction "1_1") (pintype "passive"))
    )
    (net (code "178") (name "Net-(D51-+)") (class "Default")
      (node (ref "D51") (pin "1") (pinfunction "+_1") (pintype "passive"))
      (node (ref "JP18") (pin "2") (pinfunction "2_2") (pintype "passive"))
    )
    (net (code "179") (name "Net-(D52-+)") (class "Default")
      (node (ref "D52") (pin "1") (pinfunction "+_1") (pintype "passive"))
      (node (ref "JP19") (pin "1") (pinfunction "1_1") (pintype "passive"))
    )
    (net (code "180") (name "Net-(D53--)") (class "Default")
      (node (ref "D53") (pin "2") (pinfunction "-_2") (pintype "passive"))
      (node (ref "Q34") (pin "2") (pinfunction "C_2") (pintype "passive"))
      (node (ref "START4") (pin "TP") (pinfunction "PP_TP") (pintype "input"))
      (node (ref "X10") (pin "5") (pinfunction "5_5") (pintype "passive"))
    )
    (net (code "181") (name "Net-(D54-+)") (class "Default")
      (node (ref "D54") (pin "1") (pinfunction "+_1") (pintype "passive"))
      (node (ref "R253") (pin "1") (pinfunction "1_1") (pintype "passive"))
    )
    (net (code "182") (name "Net-(D54--)") (class "Default")
      (node (ref "C45") (pin "2") (pinfunction "2_2") (pintype "passive"))
      (node (ref "D54") (pin "2") (pinfunction "-_2") (pintype "passive"))
      (node (ref "D59") (pin "C") (pinfunction "C_C") (pintype "passive"))
      (node (ref "IC33") (pin "2") (pinfunction "TR_2") (pintype "input"))
      (node (ref "IC33") (pin "6") (pinfunction "THR_6") (pintype "input"))
      (node (ref "R251") (pin "1") (pinfunction "1_1") (pintype "passive"))
    )
    (net (code "183") (name "Net-(D56-PadC)") (class "Default")
      (node (ref "D56") (pin "C") (pinfunction "C_C") (pintype "passive"))
      (node (ref "R227") (pin "2") (pinfunction "2_2") (pintype "passive"))
      (node (ref "X10") (pin "22") (pinfunction "22_22") (pintype "passive"))
    )
    (net (code "184") (name "Net-(D57--)") (class "Default")
      (node (ref "D57") (pin "2") (pinfunction "-_2") (pintype "passive"))
      (node (ref "R274") (pin "1") (pinfunction "1_1") (pintype "passive"))
      (node (ref "R275") (pin "1") (pinfunction "1_1") (pintype "passive"))
    )
    (net (code "185") (name "Net-(D58-+)") (class "Default")
      (node (ref "D58") (pin "1") (pinfunction "+_1") (pintype "passive"))
      (node (ref "X10") (pin "1") (pinfunction "1_1") (pintype "passive"))
    )
    (net (code "186") (name "Net-(D62-+)") (class "Default")
      (node (ref "D62") (pin "1") (pinfunction "+_1") (pintype "passive"))
      (node (ref "R276") (pin "1") (pinfunction "1_1") (pintype "passive"))
    )
    (net (code "187") (name "Net-(D65-+)") (class "Default")
      (node (ref "D65") (pin "1") (pinfunction "+_1") (pintype "passive"))
      (node (ref "JP23") (pin "2") (pinfunction "2_2") (pintype "passive"))
    )
    (net (code "188") (name "Net-(D66-+)") (class "Default")
      (node (ref "D66") (pin "1") (pinfunction "+_1") (pintype "passive"))
      (node (ref "JP24") (pin "1") (pinfunction "1_1") (pintype "passive"))
    )
    (net (code "189") (name "Net-(D67--)") (class "Default")
      (node (ref "D67") (pin "2") (pinfunction "-_2") (pintype "passive"))
      (node (ref "Q44") (pin "2") (pinfunction "C_2") (pintype "passive"))
      (node (ref "START5") (pin "TP") (pinfunction "PP_TP") (pintype "input"))
      (node (ref "X13") (pin "5") (pinfunction "5_5") (pintype "passive"))
    )
    (net (code "190") (name "Net-(D68-+)") (class "Default")
      (node (ref "D68") (pin "1") (pinfunction "+_1") (pintype "passive"))
      (node (ref "R308") (pin "1") (pinfunction "1_1") (pintype "passive"))
    )
    (net (code "191") (name "Net-(D68--)") (class "Default")
      (node (ref "C57") (pin "2") (pinfunction "2_2") (pintype "passive"))
      (node (ref "D68") (pin "2") (pinfunction "-_2") (pintype "passive"))
      (node (ref "D73") (pin "C") (pinfunction "C_C") (pintype "passive"))
      (node (ref "IC42") (pin "2") (pinfunction "TR_2") (pintype "input"))
      (node (ref "IC42") (pin "6") (pinfunction "THR_6") (pintype "input"))
      (node (ref "R306") (pin "1") (pinfunction "1_1") (pintype "passive"))
    )
    (net (code "192") (name "Net-(D70-PadC)") (class "Default")
      (node (ref "D70") (pin "C") (pinfunction "C_C") (pintype "passive"))
      (node (ref "R282") (pin "2") (pinfunction "2_2") (pintype "passive"))
      (node (ref "X13") (pin "22") (pinfunction "22_22") (pintype "passive"))
    )
    (net (code "193") (name "Net-(D71--)") (class "Default")
      (node (ref "D71") (pin "2") (pinfunction "-_2") (pintype "passive"))
      (node (ref "R329") (pin "1") (pinfunction "1_1") (pintype "passive"))
      (node (ref "R330") (pin "1") (pinfunction "1_1") (pintype "passive"))
    )
    (net (code "194") (name "Net-(D72-+)") (class "Default")
      (node (ref "D72") (pin "1") (pinfunction "+_1") (pintype "passive"))
      (node (ref "X13") (pin "1") (pinfunction "1_1") (pintype "passive"))
    )
    (net (code "195") (name "Net-(D104-PadC)") (class "Default")
      (node (ref "D104") (pin "C") (pinfunction "C_C") (pintype "passive"))
      (node (ref "R105") (pin "2") (pinfunction "2_2") (pintype "passive"))
      (node (ref "X101") (pin "22") (pinfunction "22_22") (pintype "passive"))
    )
    (net (code "196") (name "Net-(D105--)") (class "Default")
      (node (ref "D105") (pin "2") (pinfunction "-_2") (pintype "passive"))
      (node (ref "Q104") (pin "2") (pinfunction "C_2") (pintype "passive"))
      (node (ref "START") (pin "TP") (pinfunction "PP_TP") (pintype "input"))
      (node (ref "X101") (pin "5") (pinfunction "5_5") (pintype "passive"))
    )
    (net (code "197") (name "Net-(D106-+)") (class "Default")
      (node (ref "D106") (pin "1") (pinfunction "+_1") (pintype "passive"))
      (node (ref "R127") (pin "1") (pinfunction "1_1") (pintype "passive"))
    )
    (net (code "198") (name "Net-(D109-+)") (class "Default")
      (node (ref "D109") (pin "1") (pinfunction "+_1") (pintype "passive"))
      (node (ref "JP102") (pin "2") (pinfunction "2_2") (pintype "passive"))
    )
    (net (code "199") (name "Net-(D110-+)") (class "Default")
      (node (ref "D110") (pin "1") (pinfunction "+_1") (pintype "passive"))
      (node (ref "JP103") (pin "1") (pinfunction "1_1") (pintype "passive"))
    )
    (net (code "200") (name "Net-(D112-+)") (class "Default")
      (node (ref "D112") (pin "1") (pinfunction "+_1") (pintype "passive"))
      (node (ref "R140") (pin "1") (pinfunction "1_1") (pintype "passive"))
    )
    (net (code "201") (name "Net-(D112--)") (class "Default")
      (node (ref "C109") (pin "2") (pinfunction "2_2") (pintype "passive"))
      (node (ref "D112") (pin "2") (pinfunction "-_2") (pintype "passive"))
      (node (ref "D4") (pin "C") (pinfunction "C_C") (pintype "passive"))
      (node (ref "IC110") (pin "2") (pinfunction "TR_2") (pintype "input"))
      (node (ref "IC110") (pin "6") (pinfunction "THR_6") (pintype "input"))
      (node (ref "R141") (pin "1") (pinfunction "1_1") (pintype "passive"))
    )
    (net (code "202") (name "Net-(IC1A-A)") (class "Default")
      (node (ref "IC1") (pin "10") (pinfunction "A_10") (pintype "input"))
      (node (ref "R17") (pin "1") (pinfunction "1_1") (pintype "passive"))
      (node (ref "R58") (pin "1") (pinfunction "1_1") (pintype "passive"))
      (node (ref "R58") (pin "2") (pinfunction "2_2") (pintype "passive"))
      (node (ref "X1") (pin "4") (pinfunction "4_4") (pintype "passive"))
      (node (ref "X2") (pin "2") (pinfunction "S_2") (pintype "passive"))
    )
    (net (code "203") (name "Net-(IC1A-B)") (class "Default")
      (node (ref "IC1") (pin "13") (pinfunction "B_13") (pintype "input"))
      (node (ref "R16") (pin "1") (pinfunction "1_1") (pintype "passive"))
      (node (ref "R57") (pin "1") (pinfunction "1_1") (pintype "passive"))
      (node (ref "R57") (pin "2") (pinfunction "2_2") (pintype "passive"))
      (node (ref "X1") (pin "3") (pinfunction "3_3") (pintype "passive"))
      (node (ref "X2") (pin "3") (pinfunction "S_3") (pintype "passive"))
    )
    (net (code "204") (name "Net-(IC1A-C)") (class "Default")
      (node (ref "IC1") (pin "12") (pinfunction "C_12") (pintype "input"))
      (node (ref "R15") (pin "1") (pinfunction "1_1") (pintype "passive"))
      (node (ref "R56") (pin "1") (pinfunction "1_1") (pintype "passive"))
      (node (ref "R56") (pin "2") (pinfunction "2_2") (pintype "passive"))
      (node (ref "X1") (pin "2") (pinfunction "2_2") (pintype "passive"))
      (node (ref "X2") (pin "4") (pinfunction "S_4") (pintype "passive"))
    )
    (net (code "205") (name "Net-(IC1A-Q0)") (class "Default")
      (node (ref "IC1") (pin "3") (pinfunction "Q0_3") (pintype "output"))
      (node (ref "IC3") (pin "1") (pinfunction "I1_1") (pintype "input"))
      (node (ref "IC3") (pin "2") (pinfunction "I2_2") (pintype "input"))
      (node (ref "Q10") (pin "1") (pinfunction "G_1") (pintype "passive"))
      (node (ref "Q11") (pin "1") (pinfunction "G_1") (pintype "passive"))
    )
    (net (code "206") (name "Net-(IC1A-Q1)") (class "Default")
      (node (ref "IC1") (pin "14") (pinfunction "Q1_14") (pintype "output"))
      (node (ref "IC3") (pin "6") (pinfunction "I6_6") (pintype "input"))
    )
    (net (code "207") (name "Net-(IC1A-Q2)") (class "Default")
      (node (ref "IC1") (pin "2") (pinfunction "Q2_2") (pintype "output"))
      (node (ref "IC3") (pin "7") (pinfunction "I7_7") (pintype "input"))
    )
    (net (code "208") (name "Net-(IC1A-Q3)") (class "Default")
      (node (ref "IC1") (pin "15") (pinfunction "Q3_15") (pintype "output"))
      (node (ref "IC3") (pin "5") (pinfunction "I5_5") (pintype "input"))
    )
    (net (code "209") (name "Net-(IC1A-Q4)") (class "Default")
      (node (ref "IC1") (pin "1") (pinfunction "Q4_1") (pintype "output"))
      (node (ref "IC3") (pin "4") (pinfunction "I4_4") (pintype "input"))
    )
    (net (code "210") (name "Net-(IC1A-Q5)") (class "Default")
      (node (ref "IC1") (pin "6") (pinfunction "Q5_6") (pintype "output"))
      (node (ref "IC3") (pin "3") (pinfunction "I3_3") (pintype "input"))
    )
    (net (code "211") (name "Net-(IC2-ADJ)") (class "Default")
      (node (ref "IC2") (pin "1") (pinfunction "ADJ_1") (pintype "input"))
      (node (ref "R11") (pin "1") (pinfunction "1_1") (pintype "passive"))
      (node (ref "R20") (pin "2") (pinfunction "2_2") (pintype "passive"))
      (node (ref "X1") (pin "7") (pinfunction "7_7") (pintype "passive"))
    )
    (net (code "212") (name "Net-(IC2-VI)") (class "Default")
      (node (ref "IC2") (pin "3") (pinfunction "VI_3") (pintype "input"))
      (node (ref "Q7") (pin "2") (pinfunction "C_2") (pintype "passive"))
    )
    (net (code "213") (name "Net-(IC2-VO)") (class "Default")
      (node (ref "IC2") (pin "2") (pinfunction "VO_2") (pintype "passive"))
      (node (ref "R11") (pin "2") (pinfunction "2_2") (pintype "passive"))
    )
    (net (code "214") (name "Net-(IC3-O1)") (class "Default")
      (node (ref "IC3") (pin "16") (pinfunction "O1_16") (pintype "open_collector"))
      (node (ref "Q10") (pin "3") (pinfunction "D_3") (pintype "passive"))
      (node (ref "R62") (pin "1") (pinfunction "1_1") (pintype "passive"))
    )
    (net (code "215") (name "Net-(IC3-O2)") (class "Default")
      (node (ref "IC3") (pin "15") (pinfunction "O2_15") (pintype "open_collector"))
      (node (ref "R35") (pin "1") (pinfunction "1_1") (pintype "passive"))
    )
    (net (code "216") (name "Net-(IC4A-+IN)") (class "Default")
      (node (ref "IC4") (pin "11") (pinfunction "+IN_11") (pintype "input"))
      (node (ref "IC4") (pin "5") (pinfunction "+IN_5") (pintype "input"))
      (node (ref "R24") (pin "1") (pinfunction "1_1") (pintype "passive"))
      (node (ref "R25") (pin "2") (pinfunction "2_2") (pintype "passive"))
      (node (ref "R26") (pin "2") (pinfunction "2_2") (pintype "passive"))
    )
    (net (code "217") (name "Net-(IC4A--IN)") (class "Default")
      (node (ref "C3") (pin "1") (pinfunction "1_1") (pintype "passive"))
      (node (ref "IC4") (pin "10") (pinfunction "-IN_10") (pintype "input"))
      (node (ref "IC4") (pin "4") (pinfunction "-IN_4") (pintype "input"))
      (node (ref "R23") (pin "1") (pinfunction "1_1") (pintype "passive"))
    )
    (net (code "218") (name "Net-(IC4A-OUT)") (class "Default")
      (node (ref "IC4") (pin "2") (pinfunction "OUT_2") (pintype "open_collector"))
      (node (ref "R26") (pin "1") (pinfunction "1_1") (pintype "passive"))
    )
    (net (code "219") (name "Net-(IC4B-+IN)") (class "Default")
      (node (ref "IC4") (pin "7") (pinfunction "+IN_7") (pintype "input"))
      (node (ref "R21") (pin "1") (pinfunction "1_1") (pintype "passive"))
      (node (ref "R38") (pin "1") (pinfunction "1_1") (pintype "passive"))
    )
    (net (code "220") (name "Net-(IC4B--IN)") (class "Default")
      (node (ref "IC4") (pin "6") (pinfunction "-IN_6") (pintype "input"))
      (node (ref "IC4") (pin "8") (pinfunction "-IN_8") (pintype "input"))
      (node (ref "R20") (pin "1") (pinfunction "1_1") (pintype "passive"))
    )
    (net (code "221") (name "Net-(IC4B-OUT)") (class "Default")
      (node (ref "IC4") (pin "1") (pinfunction "OUT_1") (pintype "open_collector"))
      (node (ref "R22") (pin "2") (pinfunction "2_2") (pintype "passive"))
      (node (ref "R27") (pin "2") (pinfunction "2_2") (pintype "passive"))
    )
    (net (code "222") (name "Net-(IC4C-+IN)") (class "Default")
      (node (ref "C6") (pin "1") (pinfunction "1_1") (pintype "passive"))
      (node (ref "IC4") (pin "9") (pinfunction "+IN_9") (pintype "input"))
      (node (ref "R29") (pin "2") (pinfunction "2_2") (pintype "passive"))
      (node (ref "R38") (pin "2") (pinfunction "2_2") (pintype "passive"))
    )
    (net (code "223") (name "Net-(IC4C-OUT)") (class "Default")
      (node (ref "C7") (pin "2") (pinfunction "2_2") (pintype "passive"))
      (node (ref "IC4") (pin "14") (pinfunction "OUT_14") (pintype "open_collector"))
      (node (ref "R28") (pin "2") (pinfunction "2_2") (pintype "passive"))
    )
    (net (code "224") (name "Net-(IC4D-OUT)") (class "Default")
      (node (ref "IC4") (pin "13") (pinfunction "OUT_13") (pintype "open_collector"))
      (node (ref "JP2") (pin "1") (pinfunction "1_1") (pintype "passive"))
      (node (ref "Q9") (pin "1") (pinfunction "G_1") (pintype "passive"))
      (node (ref "R41") (pin "2") (pinfunction "2_2") (pintype "passive"))
    )
    (net (code "225") (name "Net-(IC6-CV)") (class "Default")
      (node (ref "IC6") (pin "5") (pinfunction "CV_5") (pintype "input"))
      (node (ref "R43") (pin "2") (pinfunction "2_2") (pintype "passive"))
    )
    (net (code "226") (name "Net-(IC6-Q)") (class "Default")
      (node (ref "IC6") (pin "3") (pinfunction "Q_3") (pintype "output"))
      (node (ref "IC7") (pin "12") (pinfunction "A_12") (pintype "input"))
      (node (ref "IC7") (pin "4") (pinfunction "A_4") (pintype "input"))
      (node (ref "R43") (pin "1") (pinfunction "1_1") (pintype "passive"))
    )
    (net (code "227") (name "Net-(IC7A-T2)") (class "Default")
      (node (ref "C12") (pin "2") (pinfunction "2_2") (pintype "passive"))
      (node (ref "IC7") (pin "2") (pinfunction "T2_2") (pintype "input"))
      (node (ref "R64") (pin "1") (pinfunction "1_1") (pintype "passive"))
    )
    (net (code "228") (name "Net-(IC7A-~{Q})") (class "Default")
      (node (ref "IC7") (pin "7") (pinfunction "~{Q}_7") (pintype "output"))
      (node (ref "Q13") (pin "1") (pinfunction "G_1") (pintype "passive"))
    )
    (net (code "229") (name "Net-(IC7B-B)") (class "Default")
      (node (ref "IC7") (pin "11") (pinfunction "B_11") (pintype "input"))
      (node (ref "IC7") (pin "9") (pinfunction "~{Q}_9") (pintype "output"))
      (node (ref "R49") (pin "2") (pinfunction "2_2") (pintype "passive"))
    )
    (net (code "230") (name "Net-(IC7B-T2)") (class "Default")
      (node (ref "C10") (pin "1") (pinfunction "1_1") (pintype "passive"))
      (node (ref "IC7") (pin "14") (pinfunction "T2_14") (pintype "input"))
      (node (ref "R47") (pin "1") (pinfunction "1_1") (pintype "passive"))
    )
    (net (code "231") (name "Net-(IC9A-+IN)") (class "Default")
      (node (ref "C5") (pin "1") (pinfunction "1_1") (pintype "passive"))
      (node (ref "IC9") (pin "3") (pinfunction "+IN_3") (pintype "input"))
      (node (ref "R18") (pin "1") (pinfunction "1_1") (pintype "passive"))
    )
    (net (code "232") (name "Net-(IC9A--IN)") (class "Default")
      (node (ref "IC9") (pin "2") (pinfunction "-IN_2") (pintype "input"))
      (node (ref "R19") (pin "2") (pinfunction "2_2") (pintype "passive"))
    )
    (net (code "233") (name "Net-(IC9A-OUT)") (class "Default")
      (node (ref "IC9") (pin "1") (pinfunction "OUT_1") (pintype "output"))
      (node (ref "R50") (pin "2") (pinfunction "2_2") (pintype "passive"))
    )
    (net (code "234") (name "Net-(IC9B-+IN)") (class "Default")
      (node (ref "IC9") (pin "5") (pinfunction "+IN_5") (pintype "input"))
      (node (ref "Q11") (pin "3") (pinfunction "D_3") (pintype "passive"))
      (node (ref "R51") (pin "2") (pinfunction "2_2") (pintype "passive"))
      (node (ref "R52") (pin "2") (pinfunction "2_2") (pintype "passive"))
    )
    (net (code "235") (name "Net-(IC9B--IN)") (class "Default")
      (node (ref "IC9") (pin "6") (pinfunction "-IN_6") (pintype "input"))
      (node (ref "R53") (pin "1") (pinfunction "1_1") (pintype "passive"))
      (node (ref "R54") (pin "2") (pinfunction "2_2") (pintype "passive"))
    )
    (net (code "236") (name "Net-(IC9B-OUT)") (class "Default")
      (node (ref "IC9") (pin "7") (pinfunction "OUT_7") (pintype "output"))
      (node (ref "R32") (pin "2") (pinfunction "2_2") (pintype "passive"))
      (node (ref "R39") (pin "1") (pinfunction "1_1") (pintype "passive"))
      (node (ref "R52") (pin "1") (pinfunction "1_1") (pintype "passive"))
    )
    (net (code "237") (name "Net-(IC10A-A)") (class "Default")
      (node (ref "IC10") (pin "10") (pinfunction "A_10") (pintype "input"))
      (node (ref "R157") (pin "1") (pinfunction "1_1") (pintype "passive"))
      (node (ref "R157") (pin "2") (pinfunction "2_2") (pintype "passive"))
      (node (ref "R72") (pin "1") (pinfunction "1_1") (pintype "passive"))
      (node (ref "X4") (pin "4") (pinfunction "4_4") (pintype "passive"))
      (node (ref "X5") (pin "2") (pinfunction "S_2") (pintype "passive"))
    )
    (net (code "238") (name "Net-(IC10A-B)") (class "Default")
      (node (ref "IC10") (pin "13") (pinfunction "B_13") (pintype "input"))
      (node (ref "R156") (pin "1") (pinfunction "1_1") (pintype "passive"))
      (node (ref "R156") (pin "2") (pinfunction "2_2") (pintype "passive"))
      (node (ref "R71") (pin "1") (pinfunction "1_1") (pintype "passive"))
      (node (ref "X4") (pin "3") (pinfunction "3_3") (pintype "passive"))
      (node (ref "X5") (pin "3") (pinfunction "S_3") (pintype "passive"))
    )
    (net (code "239") (name "Net-(IC10A-C)") (class "Default")
      (node (ref "IC10") (pin "12") (pinfunction "C_12") (pintype "input"))
      (node (ref "R155") (pin "1") (pinfunction "1_1") (pintype "passive"))
      (node (ref "R155") (pin "2") (pinfunction "2_2") (pintype "passive"))
      (node (ref "R70") (pin "1") (pinfunction "1_1") (pintype "passive"))
      (node (ref "X4") (pin "2") (pinfunction "2_2") (pintype "passive"))
      (node (ref "X5") (pin "4") (pinfunction "S_4") (pintype "passive"))
    )
    (net (code "240") (name "Net-(IC10A-Q0)") (class "Default")
      (node (ref "IC10") (pin "3") (pinfunction "Q0_3") (pintype "output"))
      (node (ref "IC12") (pin "1") (pinfunction "I1_1") (pintype "input"))
      (node (ref "IC12") (pin "2") (pinfunction "I2_2") (pintype "input"))
      (node (ref "Q20") (pin "1") (pinfunction "G_1") (pintype "passive"))
      (node (ref "Q21") (pin "1") (pinfunction "G_1") (pintype "passive"))
    )
    (net (code "241") (name "Net-(IC10A-Q1)") (class "Default")
      (node (ref "IC10") (pin "14") (pinfunction "Q1_14") (pintype "output"))
      (node (ref "IC12") (pin "6") (pinfunction "I6_6") (pintype "input"))
    )
    (net (code "242") (name "Net-(IC10A-Q2)") (class "Default")
      (node (ref "IC10") (pin "2") (pinfunction "Q2_2") (pintype "output"))
      (node (ref "IC12") (pin "7") (pinfunction "I7_7") (pintype "input"))
    )
    (net (code "243") (name "Net-(IC10A-Q3)") (class "Default")
      (node (ref "IC10") (pin "15") (pinfunction "Q3_15") (pintype "output"))
      (node (ref "IC12") (pin "5") (pinfunction "I5_5") (pintype "input"))
    )
    (net (code "244") (name "Net-(IC10A-Q4)") (class "Default")
      (node (ref "IC10") (pin "1") (pinfunction "Q4_1") (pintype "output"))
      (node (ref "IC12") (pin "4") (pinfunction "I4_4") (pintype "input"))
    )
    (net (code "245") (name "Net-(IC10A-Q5)") (class "Default")
      (node (ref "IC10") (pin "6") (pinfunction "Q5_6") (pintype "output"))
      (node (ref "IC12") (pin "3") (pinfunction "I3_3") (pintype "input"))
    )
    (net (code "246") (name "Net-(IC11-ADJ)") (class "Default")
      (node (ref "IC11") (pin "1") (pinfunction "ADJ_1") (pintype "input"))
      (node (ref "R68") (pin "1") (pinfunction "1_1") (pintype "passive"))
      (node (ref "R75") (pin "2") (pinfunction "2_2") (pintype "passive"))
      (node (ref "X4") (pin "7") (pinfunction "7_7") (pintype "passive"))
    )
    (net (code "247") (name "Net-(IC11-VI)") (class "Default")
      (node (ref "IC11") (pin "3") (pinfunction "VI_3") (pintype "input"))
      (node (ref "Q17") (pin "2") (pinfunction "C_2") (pintype "passive"))
    )
    (net (code "248") (name "Net-(IC11-VO)") (class "Default")
      (node (ref "IC11") (pin "2") (pinfunction "VO_2") (pintype "passive"))
      (node (ref "R68") (pin "2") (pinfunction "2_2") (pintype "passive"))
    )
    (net (code "249") (name "Net-(IC12-O1)") (class "Default")
      (node (ref "IC12") (pin "16") (pinfunction "O1_16") (pintype "open_collector"))
      (node (ref "Q20") (pin "3") (pinfunction "D_3") (pintype "passive"))
      (node (ref "R161") (pin "1") (pinfunction "1_1") (pintype "passive"))
    )
    (net (code "250") (name "Net-(IC12-O2)") (class "Default")
      (node (ref "IC12") (pin "15") (pinfunction "O2_15") (pintype "open_collector"))
      (node (ref "R90") (pin "1") (pinfunction "1_1") (pintype "passive"))
    )
    (net (code "251") (name "Net-(IC13A-+IN)") (class "Default")
      (node (ref "IC13") (pin "11") (pinfunction "+IN_11") (pintype "input"))
      (node (ref "IC13") (pin "5") (pinfunction "+IN_5") (pintype "input"))
      (node (ref "R79") (pin "1") (pinfunction "1_1") (pintype "passive"))
      (node (ref "R80") (pin "2") (pinfunction "2_2") (pintype "passive"))
      (node (ref "R81") (pin "2") (pinfunction "2_2") (pintype "passive"))
    )
    (net (code "252") (name "Net-(IC13A--IN)") (class "Default")
      (node (ref "C16") (pin "1") (pinfunction "1_1") (pintype "passive"))
      (node (ref "IC13") (pin "10") (pinfunction "-IN_10") (pintype "input"))
      (node (ref "IC13") (pin "4") (pinfunction "-IN_4") (pintype "input"))
      (node (ref "R78") (pin "1") (pinfunction "1_1") (pintype "passive"))
    )
    (net (code "253") (name "Net-(IC13A-OUT)") (class "Default")
      (node (ref "IC13") (pin "2") (pinfunction "OUT_2") (pintype "open_collector"))
      (node (ref "R81") (pin "1") (pinfunction "1_1") (pintype "passive"))
    )
    (net (code "254") (name "Net-(IC13B-+IN)") (class "Default")
      (node (ref "IC13") (pin "7") (pinfunction "+IN_7") (pintype "input"))
      (node (ref "R76") (pin "1") (pinfunction "1_1") (pintype "passive"))
      (node (ref "R93") (pin "1") (pinfunction "1_1") (pintype "passive"))
    )
    (net (code "255") (name "Net-(IC13B--IN)") (class "Default")
      (node (ref "IC13") (pin "6") (pinfunction "-IN_6") (pintype "input"))
      (node (ref "IC13") (pin "8") (pinfunction "-IN_8") (pintype "input"))
      (node (ref "R75") (pin "1") (pinfunction "1_1") (pintype "passive"))
    )
    (net (code "256") (name "Net-(IC13B-OUT)") (class "Default")
      (node (ref "IC13") (pin "1") (pinfunction "OUT_1") (pintype "open_collector"))
      (node (ref "R77") (pin "2") (pinfunction "2_2") (pintype "passive"))
      (node (ref "R82") (pin "2") (pinfunction "2_2") (pintype "passive"))
    )
    (net (code "257") (name "Net-(IC13C-+IN)") (class "Default")
      (node (ref "C19") (pin "1") (pinfunction "1_1") (pintype "passive"))
      (node (ref "IC13") (pin "9") (pinfunction "+IN_9") (pintype "input"))
      (node (ref "R84") (pin "2") (pinfunction "2_2") (pintype "passive"))
      (node (ref "R93") (pin "2") (pinfunction "2_2") (pintype "passive"))
    )
    (net (code "258") (name "Net-(IC13C-OUT)") (class "Default")
      (node (ref "C20") (pin "2") (pinfunction "2_2") (pintype "passive"))
      (node (ref "IC13") (pin "14") (pinfunction "OUT_14") (pintype "open_collector"))
      (node (ref "R83") (pin "2") (pinfunction "2_2") (pintype "passive"))
    )
    (net (code "259") (name "Net-(IC13D-OUT)") (class "Default")
      (node (ref "IC13") (pin "13") (pinfunction "OUT_13") (pintype "open_collector"))
      (node (ref "JP7") (pin "1") (pinfunction "1_1") (pintype "passive"))
      (node (ref "Q19") (pin "1") (pinfunction "G_1") (pintype "passive"))
      (node (ref "R96") (pin "2") (pinfunction "2_2") (pintype "passive"))
    )
    (net (code "260") (name "Net-(IC15-CV)") (class "Default")
      (node (ref "IC15") (pin "5") (pinfunction "CV_5") (pintype "input"))
      (node (ref "R98") (pin "2") (pinfunction "2_2") (pintype "passive"))
    )
    (net (code "261") (name "Net-(IC15-Q)") (class "Default")
      (node (ref "IC15") (pin "3") (pinfunction "Q_3") (pintype "output"))
      (node (ref "IC16") (pin "12") (pinfunction "A_12") (pintype "input"))
      (node (ref "IC16") (pin "4") (pinfunction "A_4") (pintype "input"))
      (node (ref "R98") (pin "1") (pinfunction "1_1") (pintype "passive"))
    )
    (net (code "262") (name "Net-(IC16A-T2)") (class "Default")
      (node (ref "C25") (pin "2") (pinfunction "2_2") (pintype "passive"))
      (node (ref "IC16") (pin "2") (pinfunction "T2_2") (pintype "input"))
      (node (ref "R163") (pin "1") (pinfunction "1_1") (pintype "passive"))
    )
    (net (code "263") (name "Net-(IC16A-~{Q})") (class "Default")
      (node (ref "IC16") (pin "7") (pinfunction "~{Q}_7") (pintype "output"))
      (node (ref "Q23") (pin "1") (pinfunction "G_1") (pintype "passive"))
    )
    (net (code "264") (name "Net-(IC16B-B)") (class "Default")
      (node (ref "IC16") (pin "11") (pinfunction "B_11") (pintype "input"))
      (node (ref "IC16") (pin "9") (pinfunction "~{Q}_9") (pintype "output"))
      (node (ref "R148") (pin "2") (pinfunction "2_2") (pintype "passive"))
    )
    (net (code "265") (name "Net-(IC16B-T2)") (class "Default")
      (node (ref "C23") (pin "1") (pinfunction "1_1") (pintype "passive"))
      (node (ref "IC16") (pin "14") (pinfunction "T2_14") (pintype "input"))
      (node (ref "R139") (pin "1") (pinfunction "1_1") (pintype "passive"))
    )
    (net (code "266") (name "Net-(IC18A-+IN)") (class "Default")
      (node (ref "C18") (pin "1") (pinfunction "1_1") (pintype "passive"))
      (node (ref "IC18") (pin "3") (pinfunction "+IN_3") (pintype "input"))
      (node (ref "R73") (pin "1") (pinfunction "1_1") (pintype "passive"))
    )
    (net (code "267") (name "Net-(IC18A--IN)") (class "Default")
      (node (ref "IC18") (pin "2") (pinfunction "-IN_2") (pintype "input"))
      (node (ref "R74") (pin "2") (pinfunction "2_2") (pintype "passive"))
    )
    (net (code "268") (name "Net-(IC18A-OUT)") (class "Default")
      (node (ref "IC18") (pin "1") (pinfunction "OUT_1") (pintype "output"))
      (node (ref "R149") (pin "2") (pinfunction "2_2") (pintype "passive"))
    )
    (net (code "269") (name "Net-(IC18B-+IN)") (class "Default")
      (node (ref "IC18") (pin "5") (pinfunction "+IN_5") (pintype "input"))
      (node (ref "Q21") (pin "3") (pinfunction "D_3") (pintype "passive"))
      (node (ref "R150") (pin "2") (pinfunction "2_2") (pintype "passive"))
      (node (ref "R151") (pin "2") (pinfunction "2_2") (pintype "passive"))
    )
    (net (code "270") (name "Net-(IC18B--IN)") (class "Default")
      (node (ref "IC18") (pin "6") (pinfunction "-IN_6") (pintype "input"))
      (node (ref "R152") (pin "1") (pinfunction "1_1") (pintype "passive"))
      (node (ref "R153") (pin "2") (pinfunction "2_2") (pintype "passive"))
    )
    (net (code "271") (name "Net-(IC18B-OUT)") (class "Default")
      (node (ref "IC18") (pin "7") (pinfunction "OUT_7") (pintype "output"))
      (node (ref "R151") (pin "1") (pinfunction "1_1") (pintype "passive"))
      (node (ref "R87") (pin "2") (pinfunction "2_2") (pintype "passive"))
      (node (ref "R94") (pin "1") (pinfunction "1_1") (pintype "passive"))
    )
    (net (code "272") (name "Net-(IC19A-A)") (class "Default")
      (node (ref "IC19") (pin "10") (pinfunction "A_10") (pintype "input"))
      (node (ref "R171") (pin "1") (pinfunction "1_1") (pintype "passive"))
      (node (ref "R212") (pin "1") (pinfunction "1_1") (pintype "passive"))
      (node (ref "R212") (pin "2") (pinfunction "2_2") (pintype "passive"))
      (node (ref "X7") (pin "4") (pinfunction "4_4") (pintype "passive"))
      (node (ref "X8") (pin "2") (pinfunction "S_2") (pintype "passive"))
    )
    (net (code "273") (name "Net-(IC19A-B)") (class "Default")
      (node (ref "IC19") (pin "13") (pinfunction "B_13") (pintype "input"))
      (node (ref "R170") (pin "1") (pinfunction "1_1") (pintype "passive"))
      (node (ref "R211") (pin "1") (pinfunction "1_1") (pintype "passive"))
      (node (ref "R211") (pin "2") (pinfunction "2_2") (pintype "passive"))
      (node (ref "X7") (pin "3") (pinfunction "3_3") (pintype "passive"))
      (node (ref "X8") (pin "3") (pinfunction "S_3") (pintype "passive"))
    )
    (net (code "274") (name "Net-(IC19A-C)") (class "Default")
      (node (ref "IC19") (pin "12") (pinfunction "C_12") (pintype "input"))
      (node (ref "R169") (pin "1") (pinfunction "1_1") (pintype "passive"))
      (node (ref "R210") (pin "1") (pinfunction "1_1") (pintype "passive"))
      (node (ref "R210") (pin "2") (pinfunction "2_2") (pintype "passive"))
      (node (ref "X7") (pin "2") (pinfunction "2_2") (pintype "passive"))
      (node (ref "X8") (pin "4") (pinfunction "S_4") (pintype "passive"))
    )
    (net (code "275") (name "Net-(IC19A-Q0)") (class "Default")
      (node (ref "IC19") (pin "3") (pinfunction "Q0_3") (pintype "output"))
      (node (ref "IC21") (pin "1") (pinfunction "I1_1") (pintype "input"))
      (node (ref "IC21") (pin "2") (pinfunction "I2_2") (pintype "input"))
      (node (ref "Q30") (pin "1") (pinfunction "G_1") (pintype "passive"))
      (node (ref "Q31") (pin "1") (pinfunction "G_1") (pintype "passive"))
    )
    (net (code "276") (name "Net-(IC19A-Q1)") (class "Default")
      (node (ref "IC19") (pin "14") (pinfunction "Q1_14") (pintype "output"))
      (node (ref "IC21") (pin "6") (pinfunction "I6_6") (pintype "input"))
    )
    (net (code "277") (name "Net-(IC19A-Q2)") (class "Default")
      (node (ref "IC19") (pin "2") (pinfunction "Q2_2") (pintype "output"))
      (node (ref "IC21") (pin "7") (pinfunction "I7_7") (pintype "input"))
    )
    (net (code "278") (name "Net-(IC19A-Q3)") (class "Default")
      (node (ref "IC19") (pin "15") (pinfunction "Q3_15") (pintype "output"))
      (node (ref "IC21") (pin "5") (pinfunction "I5_5") (pintype "input"))
    )
    (net (code "279") (name "Net-(IC19A-Q4)") (class "Default")
      (node (ref "IC19") (pin "1") (pinfunction "Q4_1") (pintype "output"))
      (node (ref "IC21") (pin "4") (pinfunction "I4_4") (pintype "input"))
    )
    (net (code "280") (name "Net-(IC19A-Q5)") (class "Default")
      (node (ref "IC19") (pin "6") (pinfunction "Q5_6") (pintype "output"))
      (node (ref "IC21") (pin "3") (pinfunction "I3_3") (pintype "input"))
    )
    (net (code "281") (name "Net-(IC20-ADJ)") (class "Default")
      (node (ref "IC20") (pin "1") (pinfunction "ADJ_1") (pintype "input"))
      (node (ref "R167") (pin "1") (pinfunction "1_1") (pintype "passive"))
      (node (ref "R174") (pin "2") (pinfunction "2_2") (pintype "passive"))
      (node (ref "X7") (pin "7") (pinfunction "7_7") (pintype "passive"))
    )
    (net (code "282") (name "Net-(IC20-VI)") (class "Default")
      (node (ref "IC20") (pin "3") (pinfunction "VI_3") (pintype "input"))
      (node (ref "Q27") (pin "2") (pinfunction "C_2") (pintype "passive"))
    )
    (net (code "283") (name "Net-(IC20-VO)") (class "Default")
      (node (ref "IC20") (pin "2") (pinfunction "VO_2") (pintype "passive"))
      (node (ref "R167") (pin "2") (pinfunction "2_2") (pintype "passive"))
    )
    (net (code "284") (name "Net-(IC21-O1)") (class "Default")
      (node (ref "IC21") (pin "16") (pinfunction "O1_16") (pintype "open_collector"))
      (node (ref "Q30") (pin "3") (pinfunction "D_3") (pintype "passive"))
      (node (ref "R216") (pin "1") (pinfunction "1_1") (pintype "passive"))
    )
    (net (code "285") (name "Net-(IC21-O2)") (class "Default")
      (node (ref "IC21") (pin "15") (pinfunction "O2_15") (pintype "open_collector"))
      (node (ref "R189") (pin "1") (pinfunction "1_1") (pintype "passive"))
    )
    (net (code "286") (name "Net-(IC22A-+IN)") (class "Default")
      (node (ref "IC22") (pin "11") (pinfunction "+IN_11") (pintype "input"))
      (node (ref "IC22") (pin "5") (pinfunction "+IN_5") (pintype "input"))
      (node (ref "R178") (pin "1") (pinfunction "1_1") (pintype "passive"))
      (node (ref "R179") (pin "2") (pinfunction "2_2") (pintype "passive"))
      (node (ref "R180") (pin "2") (pinfunction "2_2") (pintype "passive"))
    )
    (net (code "287") (name "Net-(IC22A--IN)") (class "Default")
      (node (ref "C28") (pin "1") (pinfunction "1_1") (pintype "passive"))
      (node (ref "IC22") (pin "10") (pinfunction "-IN_10") (pintype "input"))
      (node (ref "IC22") (pin "4") (pinfunction "-IN_4") (pintype "input"))
      (node (ref "R177") (pin "1") (pinfunction "1_1") (pintype "passive"))
    )
    (net (code "288") (name "Net-(IC22A-OUT)") (class "Default")
      (node (ref "IC22") (pin "2") (pinfunction "OUT_2") (pintype "open_collector"))
      (node (ref "R180") (pin "1") (pinfunction "1_1") (pintype "passive"))
    )
    (net (code "289") (name "Net-(IC22B-+IN)") (class "Default")
      (node (ref "IC22") (pin "7") (pinfunction "+IN_7") (pintype "input"))
      (node (ref "R175") (pin "1") (pinfunction "1_1") (pintype "passive"))
      (node (ref "R192") (pin "1") (pinfunction "1_1") (pintype "passive"))
    )
    (net (code "290") (name "Net-(IC22B--IN)") (class "Default")
      (node (ref "IC22") (pin "6") (pinfunction "-IN_6") (pintype "input"))
      (node (ref "IC22") (pin "8") (pinfunction "-IN_8") (pintype "input"))
      (node (ref "R174") (pin "1") (pinfunction "1_1") (pintype "passive"))
    )
    (net (code "291") (name "Net-(IC22B-OUT)") (class "Default")
      (node (ref "IC22") (pin "1") (pinfunction "OUT_1") (pintype "open_collector"))
      (node (ref "R176") (pin "2") (pinfunction "2_2") (pintype "passive"))
      (node (ref "R181") (pin "2") (pinfunction "2_2") (pintype "passive"))
    )
    (net (code "292") (name "Net-(IC22C-+IN)") (class "Default")
      (node (ref "C31") (pin "1") (pinfunction "1_1") (pintype "passive"))
      (node (ref "IC22") (pin "9") (pinfunction "+IN_9") (pintype "input"))
      (node (ref "R183") (pin "2") (pinfunction "2_2") (pintype "passive"))
      (node (ref "R192") (pin "2") (pinfunction "2_2") (pintype "passive"))
    )
    (net (code "293") (name "Net-(IC22C-OUT)") (class "Default")
      (node (ref "C32") (pin "2") (pinfunction "2_2") (pintype "passive"))
      (node (ref "IC22") (pin "14") (pinfunction "OUT_14") (pintype "open_collector"))
      (node (ref "R182") (pin "2") (pinfunction "2_2") (pintype "passive"))
    )
    (net (code "294") (name "Net-(IC22D-OUT)") (class "Default")
      (node (ref "IC22") (pin "13") (pinfunction "OUT_13") (pintype "open_collector"))
      (node (ref "JP12") (pin "1") (pinfunction "1_1") (pintype "passive"))
      (node (ref "Q29") (pin "1") (pinfunction "G_1") (pintype "passive"))
      (node (ref "R195") (pin "2") (pinfunction "2_2") (pintype "passive"))
    )
    (net (code "295") (name "Net-(IC24-CV)") (class "Default")
      (node (ref "IC24") (pin "5") (pinfunction "CV_5") (pintype "input"))
      (node (ref "R197") (pin "2") (pinfunction "2_2") (pintype "passive"))
    )
    (net (code "296") (name "Net-(IC24-Q)") (class "Default")
      (node (ref "IC24") (pin "3") (pinfunction "Q_3") (pintype "output"))
      (node (ref "IC25") (pin "12") (pinfunction "A_12") (pintype "input"))
      (node (ref "IC25") (pin "4") (pinfunction "A_4") (pintype "input"))
      (node (ref "R197") (pin "1") (pinfunction "1_1") (pintype "passive"))
    )
    (net (code "297") (name "Net-(IC25A-T2)") (class "Default")
      (node (ref "C37") (pin "2") (pinfunction "2_2") (pintype "passive"))
      (node (ref "IC25") (pin "2") (pinfunction "T2_2") (pintype "input"))
      (node (ref "R218") (pin "1") (pinfunction "1_1") (pintype "passive"))
    )
    (net (code "298") (name "Net-(IC25A-~{Q})") (class "Default")
      (node (ref "IC25") (pin "7") (pinfunction "~{Q}_7") (pintype "output"))
      (node (ref "Q33") (pin "1") (pinfunction "G_1") (pintype "passive"))
    )
    (net (code "299") (name "Net-(IC25B-B)") (class "Default")
      (node (ref "IC25") (pin "11") (pinfunction "B_11") (pintype "input"))
      (node (ref "IC25") (pin "9") (pinfunction "~{Q}_9") (pintype "output"))
      (node (ref "R203") (pin "2") (pinfunction "2_2") (pintype "passive"))
    )
    (net (code "300") (name "Net-(IC25B-T2)") (class "Default")
      (node (ref "C35") (pin "1") (pinfunction "1_1") (pintype "passive"))
      (node (ref "IC25") (pin "14") (pinfunction "T2_14") (pintype "input"))
      (node (ref "R201") (pin "1") (pinfunction "1_1") (pintype "passive"))
    )
    (net (code "301") (name "Net-(IC27A-+IN)") (class "Default")
      (node (ref "C30") (pin "1") (pinfunction "1_1") (pintype "passive"))
      (node (ref "IC27") (pin "3") (pinfunction "+IN_3") (pintype "input"))
      (node (ref "R172") (pin "1") (pinfunction "1_1") (pintype "passive"))
    )
    (net (code "302") (name "Net-(IC27A--IN)") (class "Default")
      (node (ref "IC27") (pin "2") (pinfunction "-IN_2") (pintype "input"))
      (node (ref "R173") (pin "2") (pinfunction "2_2") (pintype "passive"))
    )
    (net (code "303") (name "Net-(IC27A-OUT)") (class "Default")
      (node (ref "IC27") (pin "1") (pinfunction "OUT_1") (pintype "output"))
      (node (ref "R204") (pin "2") (pinfunction "2_2") (pintype "passive"))
    )
    (net (code "304") (name "Net-(IC27B-+IN)") (class "Default")
      (node (ref "IC27") (pin "5") (pinfunction "+IN_5") (pintype "input"))
      (node (ref "Q31") (pin "3") (pinfunction "D_3") (pintype "passive"))
      (node (ref "R205") (pin "2") (pinfunction "2_2") (pintype "passive"))
      (node (ref "R206") (pin "2") (pinfunction "2_2") (pintype "passive"))
    )
    (net (code "305") (name "Net-(IC27B--IN)") (class "Default")
      (node (ref "IC27") (pin "6") (pinfunction "-IN_6") (pintype "input"))
      (node (ref "R207") (pin "1") (pinfunction "1_1") (pintype "passive"))
      (node (ref "R208") (pin "2") (pinfunction "2_2") (pintype "passive"))
    )
    (net (code "306") (name "Net-(IC27B-OUT)") (class "Default")
      (node (ref "IC27") (pin "7") (pinfunction "OUT_7") (pintype "output"))
      (node (ref "R186") (pin "2") (pinfunction "2_2") (pintype "passive"))
      (node (ref "R193") (pin "1") (pinfunction "1_1") (pintype "passive"))
      (node (ref "R206") (pin "1") (pinfunction "1_1") (pintype "passive"))
    )
    (net (code "307") (name "Net-(IC28A-A)") (class "Default")
      (node (ref "IC28") (pin "10") (pinfunction "A_10") (pintype "input"))
      (node (ref "R226") (pin "1") (pinfunction "1_1") (pintype "passive"))
      (node (ref "R267") (pin "1") (pinfunction "1_1") (pintype "passive"))
      (node (ref "R267") (pin "2") (pinfunction "2_2") (pintype "passive"))
      (node (ref "X10") (pin "4") (pinfunction "4_4") (pintype "passive"))
      (node (ref "X11") (pin "2") (pinfunction "S_2") (pintype "passive"))
    )
    (net (code "308") (name "Net-(IC28A-B)") (class "Default")
      (node (ref "IC28") (pin "13") (pinfunction "B_13") (pintype "input"))
      (node (ref "R225") (pin "1") (pinfunction "1_1") (pintype "passive"))
      (node (ref "R266") (pin "1") (pinfunction "1_1") (pintype "passive"))
      (node (ref "R266") (pin "2") (pinfunction "2_2") (pintype "passive"))
      (node (ref "X10") (pin "3") (pinfunction "3_3") (pintype "passive"))
      (node (ref "X11") (pin "3") (pinfunction "S_3") (pintype "passive"))
    )
    (net (code "309") (name "Net-(IC28A-C)") (class "Default")
      (node (ref "IC28") (pin "12") (pinfunction "C_12") (pintype "input"))
      (node (ref "R224") (pin "1") (pinfunction "1_1") (pintype "passive"))
      (node (ref "R265") (pin "1") (pinfunction "1_1") (pintype "passive"))
      (node (ref "R265") (pin "2") (pinfunction "2_2") (pintype "passive"))
      (node (ref "X10") (pin "2") (pinfunction "2_2") (pintype "passive"))
      (node (ref "X11") (pin "4") (pinfunction "S_4") (pintype "passive"))
    )
    (net (code "310") (name "Net-(IC28A-Q0)") (class "Default")
      (node (ref "IC28") (pin "3") (pinfunction "Q0_3") (pintype "output"))
      (node (ref "IC30") (pin "1") (pinfunction "I1_1") (pintype "input"))
      (node (ref "IC30") (pin "2") (pinfunction "I2_2") (pintype "input"))
      (node (ref "Q40") (pin "1") (pinfunction "G_1") (pintype "passive"))
      (node (ref "Q41") (pin "1") (pinfunction "G_1") (pintype "passive"))
    )
    (net (code "311") (name "Net-(IC28A-Q1)") (class "Default")
      (node (ref "IC28") (pin "14") (pinfunction "Q1_14") (pintype "output"))
      (node (ref "IC30") (pin "6") (pinfunction "I6_6") (pintype "input"))
    )
    (net (code "312") (name "Net-(IC28A-Q2)") (class "Default")
      (node (ref "IC28") (pin "2") (pinfunction "Q2_2") (pintype "output"))
      (node (ref "IC30") (pin "7") (pinfunction "I7_7") (pintype "input"))
    )
    (net (code "313") (name "Net-(IC28A-Q3)") (class "Default")
      (node (ref "IC28") (pin "15") (pinfunction "Q3_15") (pintype "output"))
      (node (ref "IC30") (pin "5") (pinfunction "I5_5") (pintype "input"))
    )
    (net (code "314") (name "Net-(IC28A-Q4)") (class "Default")
      (node (ref "IC28") (pin "1") (pinfunction "Q4_1") (pintype "output"))
      (node (ref "IC30") (pin "4") (pinfunction "I4_4") (pintype "input"))
    )
    (net (code "315") (name "Net-(IC28A-Q5)") (class "Default")
      (node (ref "IC28") (pin "6") (pinfunction "Q5_6") (pintype "output"))
      (node (ref "IC30") (pin "3") (pinfunction "I3_3") (pintype "input"))
    )
    (net (code "316") (name "Net-(IC29-ADJ)") (class "Default")
      (node (ref "IC29") (pin "1") (pinfunction "ADJ_1") (pintype "input"))
      (node (ref "R222") (pin "1") (pinfunction "1_1") (pintype "passive"))
      (node (ref "R229") (pin "2") (pinfunction "2_2") (pintype "passive"))
      (node (ref "X10") (pin "7") (pinfunction "7_7") (pintype "passive"))
    )
    (net (code "317") (name "Net-(IC29-VI)") (class "Default")
      (node (ref "IC29") (pin "3") (pinfunction "VI_3") (pintype "input"))
      (node (ref "Q37") (pin "2") (pinfunction "C_2") (pintype "passive"))
    )
    (net (code "318") (name "Net-(IC29-VO)") (class "Default")
      (node (ref "IC29") (pin "2") (pinfunction "VO_2") (pintype "passive"))
      (node (ref "R222") (pin "2") (pinfunction "2_2") (pintype "passive"))
    )
    (net (code "319") (name "Net-(IC30-O1)") (class "Default")
      (node (ref "IC30") (pin "16") (pinfunction "O1_16") (pintype "open_collector"))
      (node (ref "Q40") (pin "3") (pinfunction "D_3") (pintype "passive"))
      (node (ref "R271") (pin "1") (pinfunction "1_1") (pintype "passive"))
    )
    (net (code "320") (name "Net-(IC30-O2)") (class "Default")
      (node (ref "IC30") (pin "15") (pinfunction "O2_15") (pintype "open_collector"))
      (node (ref "R244") (pin "1") (pinfunction "1_1") (pintype "passive"))
    )
    (net (code "321") (name "Net-(IC31A-+IN)") (class "Default")
      (node (ref "IC31") (pin "11") (pinfunction "+IN_11") (pintype "input"))
      (node (ref "IC31") (pin "5") (pinfunction "+IN_5") (pintype "input"))
      (node (ref "R233") (pin "1") (pinfunction "1_1") (pintype "passive"))
      (node (ref "R234") (pin "2") (pinfunction "2_2") (pintype "passive"))
      (node (ref "R235") (pin "2") (pinfunction "2_2") (pintype "passive"))
    )
    (net (code "322") (name "Net-(IC31A--IN)") (class "Default")
      (node (ref "C40") (pin "1") (pinfunction "1_1") (pintype "passive"))
      (node (ref "IC31") (pin "10") (pinfunction "-IN_10") (pintype "input"))
      (node (ref "IC31") (pin "4") (pinfunction "-IN_4") (pintype "input"))
      (node (ref "R232") (pin "1") (pinfunction "1_1") (pintype "passive"))
    )
    (net (code "323") (name "Net-(IC31A-OUT)") (class "Default")
      (node (ref "IC31") (pin "2") (pinfunction "OUT_2") (pintype "open_collector"))
      (node (ref "R235") (pin "1") (pinfunction "1_1") (pintype "passive"))
    )
    (net (code "324") (name "Net-(IC31B-+IN)") (class "Default")
      (node (ref "IC31") (pin "7") (pinfunction "+IN_7") (pintype "input"))
      (node (ref "R230") (pin "1") (pinfunction "1_1") (pintype "passive"))
      (node (ref "R247") (pin "1") (pinfunction "1_1") (pintype "passive"))
    )
    (net (code "325") (name "Net-(IC31B--IN)") (class "Default")
      (node (ref "IC31") (pin "6") (pinfunction "-IN_6") (pintype "input"))
      (node (ref "IC31") (pin "8") (pinfunction "-IN_8") (pintype "input"))
      (node (ref "R229") (pin "1") (pinfunction "1_1") (pintype "passive"))
    )
    (net (code "326") (name "Net-(IC31B-OUT)") (class "Default")
      (node (ref "IC31") (pin "1") (pinfunction "OUT_1") (pintype "open_collector"))
      (node (ref "R231") (pin "2") (pinfunction "2_2") (pintype "passive"))
      (node (ref "R236") (pin "2") (pinfunction "2_2") (pintype "passive"))
    )
    (net (code "327") (name "Net-(IC31C-+IN)") (class "Default")
      (node (ref "C43") (pin "1") (pinfunction "1_1") (pintype "passive"))
      (node (ref "IC31") (pin "9") (pinfunction "+IN_9") (pintype "input"))
      (node (ref "R238") (pin "2") (pinfunction "2_2") (pintype "passive"))
      (node (ref "R247") (pin "2") (pinfunction "2_2") (pintype "passive"))
    )
    (net (code "328") (name "Net-(IC31C-OUT)") (class "Default")
      (node (ref "C44") (pin "2") (pinfunction "2_2") (pintype "passive"))
      (node (ref "IC31") (pin "14") (pinfunction "OUT_14") (pintype "open_collector"))
      (node (ref "R237") (pin "2") (pinfunction "2_2") (pintype "passive"))
    )
    (net (code "329") (name "Net-(IC31D-OUT)") (class "Default")
      (node (ref "IC31") (pin "13") (pinfunction "OUT_13") (pintype "open_collector"))
      (node (ref "JP17") (pin "1") (pinfunction "1_1") (pintype "passive"))
      (node (ref "Q39") (pin "1") (pinfunction "G_1") (pintype "passive"))
      (node (ref "R250") (pin "2") (pinfunction "2_2") (pintype "passive"))
    )
    (net (code "330") (name "Net-(IC33-CV)") (class "Default")
      (node (ref "IC33") (pin "5") (pinfunction "CV_5") (pintype "input"))
      (node (ref "R252") (pin "2") (pinfunction "2_2") (pintype "passive"))
    )
    (net (code "331") (name "Net-(IC33-Q)") (class "Default")
      (node (ref "IC33") (pin "3") (pinfunction "Q_3") (pintype "output"))
      (node (ref "IC34") (pin "12") (pinfunction "A_12") (pintype "input"))
      (node (ref "IC34") (pin "4") (pinfunction "A_4") (pintype "input"))
      (node (ref "R252") (pin "1") (pinfunction "1_1") (pintype "passive"))
    )
    (net (code "332") (name "Net-(IC34A-T2)") (class "Default")
      (node (ref "C49") (pin "2") (pinfunction "2_2") (pintype "passive"))
      (node (ref "IC34") (pin "2") (pinfunction "T2_2") (pintype "input"))
      (node (ref "R273") (pin "1") (pinfunction "1_1") (pintype "passive"))
    )
    (net (code "333") (name "Net-(IC34A-~{Q})") (class "Default")
      (node (ref "IC34") (pin "7") (pinfunction "~{Q}_7") (pintype "output"))
      (node (ref "Q43") (pin "1") (pinfunction "G_1") (pintype "passive"))
    )
    (net (code "334") (name "Net-(IC34B-B)") (class "Default")
      (node (ref "IC34") (pin "11") (pinfunction "B_11") (pintype "input"))
      (node (ref "IC34") (pin "9") (pinfunction "~{Q}_9") (pintype "output"))
      (node (ref "R258") (pin "2") (pinfunction "2_2") (pintype "passive"))
    )
    (net (code "335") (name "Net-(IC34B-T2)") (class "Default")
      (node (ref "C47") (pin "1") (pinfunction "1_1") (pintype "passive"))
      (node (ref "IC34") (pin "14") (pinfunction "T2_14") (pintype "input"))
      (node (ref "R256") (pin "1") (pinfunction "1_1") (pintype "passive"))
    )
    (net (code "336") (name "Net-(IC36A-+IN)") (class "Default")
      (node (ref "C42") (pin "1") (pinfunction "1_1") (pintype "passive"))
      (node (ref "IC36") (pin "3") (pinfunction "+IN_3") (pintype "input"))
      (node (ref "R227") (pin "1") (pinfunction "1_1") (pintype "passive"))
    )
    (net (code "337") (name "Net-(IC36A--IN)") (class "Default")
      (node (ref "IC36") (pin "2") (pinfunction "-IN_2") (pintype "input"))
      (node (ref "R228") (pin "2") (pinfunction "2_2") (pintype "passive"))
    )
    (net (code "338") (name "Net-(IC36A-OUT)") (class "Default")
      (node (ref "IC36") (pin "1") (pinfunction "OUT_1") (pintype "output"))
      (node (ref "R259") (pin "2") (pinfunction "2_2") (pintype "passive"))
    )
    (net (code "339") (name "Net-(IC36B-+IN)") (class "Default")
      (node (ref "IC36") (pin "5") (pinfunction "+IN_5") (pintype "input"))
      (node (ref "Q41") (pin "3") (pinfunction "D_3") (pintype "passive"))
      (node (ref "R260") (pin "2") (pinfunction "2_2") (pintype "passive"))
      (node (ref "R261") (pin "2") (pinfunction "2_2") (pintype "passive"))
    )
    (net (code "340") (name "Net-(IC36B--IN)") (class "Default")
      (node (ref "IC36") (pin "6") (pinfunction "-IN_6") (pintype "input"))
      (node (ref "R262") (pin "1") (pinfunction "1_1") (pintype "passive"))
      (node (ref "R263") (pin "2") (pinfunction "2_2") (pintype "passive"))
    )
    (net (code "341") (name "Net-(IC36B-OUT)") (class "Default")
      (node (ref "IC36") (pin "7") (pinfunction "OUT_7") (pintype "output"))
      (node (ref "R241") (pin "2") (pinfunction "2_2") (pintype "passive"))
      (node (ref "R248") (pin "1") (pinfunction "1_1") (pintype "passive"))
      (node (ref "R261") (pin "1") (pinfunction "1_1") (pintype "passive"))
    )
    (net (code "342") (name "Net-(IC37A-A)") (class "Default")
      (node (ref "IC37") (pin "10") (pinfunction "A_10") (pintype "input"))
      (node (ref "R281") (pin "1") (pinfunction "1_1") (pintype "passive"))
      (node (ref "R322") (pin "1") (pinfunction "1_1") (pintype "passive"))
      (node (ref "R322") (pin "2") (pinfunction "2_2") (pintype "passive"))
      (node (ref "X13") (pin "4") (pinfunction "4_4") (pintype "passive"))
      (node (ref "X14") (pin "2") (pinfunction "S_2") (pintype "passive"))
    )
    (net (code "343") (name "Net-(IC37A-B)") (class "Default")
      (node (ref "IC37") (pin "13") (pinfunction "B_13") (pintype "input"))
      (node (ref "R280") (pin "1") (pinfunction "1_1") (pintype "passive"))
      (node (ref "R321") (pin "1") (pinfunction "1_1") (pintype "passive"))
      (node (ref "R321") (pin "2") (pinfunction "2_2") (pintype "passive"))
      (node (ref "X13") (pin "3") (pinfunction "3_3") (pintype "passive"))
      (node (ref "X14") (pin "3") (pinfunction "S_3") (pintype "passive"))
    )
    (net (code "344") (name "Net-(IC37A-C)") (class "Default")
      (node (ref "IC37") (pin "12") (pinfunction "C_12") (pintype "input"))
      (node (ref "R279") (pin "1") (pinfunction "1_1") (pintype "passive"))
      (node (ref "R320") (pin "1") (pinfunction "1_1") (pintype "passive"))
      (node (ref "R320") (pin "2") (pinfunction "2_2") (pintype "passive"))
      (node (ref "X13") (pin "2") (pinfunction "2_2") (pintype "passive"))
      (node (ref "X14") (pin "4") (pinfunction "S_4") (pintype "passive"))
    )
    (net (code "345") (name "Net-(IC37A-Q0)") (class "Default")
      (node (ref "IC37") (pin "3") (pinfunction "Q0_3") (pintype "output"))
      (node (ref "IC39") (pin "1") (pinfunction "I1_1") (pintype "input"))
      (node (ref "IC39") (pin "2") (pinfunction "I2_2") (pintype "input"))
      (node (ref "Q50") (pin "1") (pinfunction "G_1") (pintype "passive"))
      (node (ref "Q51") (pin "1") (pinfunction "G_1") (pintype "passive"))
    )
    (net (code "346") (name "Net-(IC37A-Q1)") (class "Default")
      (node (ref "IC37") (pin "14") (pinfunction "Q1_14") (pintype "output"))
      (node (ref "IC39") (pin "6") (pinfunction "I6_6") (pintype "input"))
    )
    (net (code "347") (name "Net-(IC37A-Q2)") (class "Default")
      (node (ref "IC37") (pin "2") (pinfunction "Q2_2") (pintype "output"))
      (node (ref "IC39") (pin "7") (pinfunction "I7_7") (pintype "input"))
    )
    (net (code "348") (name "Net-(IC37A-Q3)") (class "Default")
      (node (ref "IC37") (pin "15") (pinfunction "Q3_15") (pintype "output"))
      (node (ref "IC39") (pin "5") (pinfunction "I5_5") (pintype "input"))
    )
    (net (code "349") (name "Net-(IC37A-Q4)") (class "Default")
      (node (ref "IC37") (pin "1") (pinfunction "Q4_1") (pintype "output"))
      (node (ref "IC39") (pin "4") (pinfunction "I4_4") (pintype "input"))
    )
    (net (code "350") (name "Net-(IC37A-Q5)") (class "Default")
      (node (ref "IC37") (pin "6") (pinfunction "Q5_6") (pintype "output"))
      (node (ref "IC39") (pin "3") (pinfunction "I3_3") (pintype "input"))
    )
    (net (code "351") (name "Net-(IC38-ADJ)") (class "Default")
      (node (ref "IC38") (pin "1") (pinfunction "ADJ_1") (pintype "input"))
      (node (ref "R277") (pin "1") (pinfunction "1_1") (pintype "passive"))
      (node (ref "R284") (pin "2") (pinfunction "2_2") (pintype "passive"))
      (node (ref "X13") (pin "7") (pinfunction "7_7") (pintype "passive"))
    )
    (net (code "352") (name "Net-(IC38-VI)") (class "Default")
      (node (ref "IC38") (pin "3") (pinfunction "VI_3") (pintype "input"))
      (node (ref "Q47") (pin "2") (pinfunction "C_2") (pintype "passive"))
    )
    (net (code "353") (name "Net-(IC38-VO)") (class "Default")
      (node (ref "IC38") (pin "2") (pinfunction "VO_2") (pintype "passive"))
      (node (ref "R277") (pin "2") (pinfunction "2_2") (pintype "passive"))
    )
    (net (code "354") (name "Net-(IC39-O1)") (class "Default")
      (node (ref "IC39") (pin "16") (pinfunction "O1_16") (pintype "open_collector"))
      (node (ref "Q50") (pin "3") (pinfunction "D_3") (pintype "passive"))
      (node (ref "R326") (pin "1") (pinfunction "1_1") (pintype "passive"))
    )
    (net (code "355") (name "Net-(IC39-O2)") (class "Default")
      (node (ref "IC39") (pin "15") (pinfunction "O2_15") (pintype "open_collector"))
      (node (ref "R299") (pin "1") (pinfunction "1_1") (pintype "passive"))
    )
    (net (code "356") (name "Net-(IC40A-+IN)") (class "Default")
      (node (ref "IC40") (pin "11") (pinfunction "+IN_11") (pintype "input"))
      (node (ref "IC40") (pin "5") (pinfunction "+IN_5") (pintype "input"))
      (node (ref "R288") (pin "1") (pinfunction "1_1") (pintype "passive"))
      (node (ref "R289") (pin "2") (pinfunction "2_2") (pintype "passive"))
      (node (ref "R290") (pin "2") (pinfunction "2_2") (pintype "passive"))
    )
    (net (code "357") (name "Net-(IC40A--IN)") (class "Default")
      (node (ref "C52") (pin "1") (pinfunction "1_1") (pintype "passive"))
      (node (ref "IC40") (pin "10") (pinfunction "-IN_10") (pintype "input"))
      (node (ref "IC40") (pin "4") (pinfunction "-IN_4") (pintype "input"))
      (node (ref "R287") (pin "1") (pinfunction "1_1") (pintype "passive"))
    )
    (net (code "358") (name "Net-(IC40A-OUT)") (class "Default")
      (node (ref "IC40") (pin "2") (pinfunction "OUT_2") (pintype "open_collector"))
      (node (ref "R290") (pin "1") (pinfunction "1_1") (pintype "passive"))
    )
    (net (code "359") (name "Net-(IC40B-+IN)") (class "Default")
      (node (ref "IC40") (pin "7") (pinfunction "+IN_7") (pintype "input"))
      (node (ref "R285") (pin "1") (pinfunction "1_1") (pintype "passive"))
      (node (ref "R302") (pin "1") (pinfunction "1_1") (pintype "passive"))
    )
    (net (code "360") (name "Net-(IC40B--IN)") (class "Default")
      (node (ref "IC40") (pin "6") (pinfunction "-IN_6") (pintype "input"))
      (node (ref "IC40") (pin "8") (pinfunction "-IN_8") (pintype "input"))
      (node (ref "R284") (pin "1") (pinfunction "1_1") (pintype "passive"))
    )
    (net (code "361") (name "Net-(IC40B-OUT)") (class "Default")
      (node (ref "IC40") (pin "1") (pinfunction "OUT_1") (pintype "open_collector"))
      (node (ref "R286") (pin "2") (pinfunction "2_2") (pintype "passive"))
      (node (ref "R291") (pin "2") (pinfunction "2_2") (pintype "passive"))
    )
    (net (code "362") (name "Net-(IC40C-+IN)") (class "Default")
      (node (ref "C55") (pin "1") (pinfunction "1_1") (pintype "passive"))
      (node (ref "IC40") (pin "9") (pinfunction "+IN_9") (pintype "input"))
      (node (ref "R293") (pin "2") (pinfunction "2_2") (pintype "passive"))
      (node (ref "R302") (pin "2") (pinfunction "2_2") (pintype "passive"))
    )
    (net (code "363") (name "Net-(IC40C-OUT)") (class "Default")
      (node (ref "C56") (pin "2") (pinfunction "2_2") (pintype "passive"))
      (node (ref "IC40") (pin "14") (pinfunction "OUT_14") (pintype "open_collector"))
      (node (ref "R292") (pin "2") (pinfunction "2_2") (pintype "passive"))
    )
    (net (code "364") (name "Net-(IC40D-OUT)") (class "Default")
      (node (ref "IC40") (pin "13") (pinfunction "OUT_13") (pintype "open_collector"))
      (node (ref "JP22") (pin "1") (pinfunction "1_1") (pintype "passive"))
      (node (ref "Q49") (pin "1") (pinfunction "G_1") (pintype "passive"))
      (node (ref "R305") (pin "2") (pinfunction "2_2") (pintype "passive"))
    )
    (net (code "365") (name "Net-(IC42-CV)") (class "Default")
      (node (ref "IC42") (pin "5") (pinfunction "CV_5") (pintype "input"))
      (node (ref "R307") (pin "2") (pinfunction "2_2") (pintype "passive"))
    )
    (net (code "366") (name "Net-(IC42-Q)") (class "Default")
      (node (ref "IC42") (pin "3") (pinfunction "Q_3") (pintype "output"))
      (node (ref "IC43") (pin "12") (pinfunction "A_12") (pintype "input"))
      (node (ref "IC43") (pin "4") (pinfunction "A_4") (pintype "input"))
      (node (ref "R307") (pin "1") (pinfunction "1_1") (pintype "passive"))
    )
    (net (code "367") (name "Net-(IC43A-T2)") (class "Default")
      (node (ref "C61") (pin "2") (pinfunction "2_2") (pintype "passive"))
      (node (ref "IC43") (pin "2") (pinfunction "T2_2") (pintype "input"))
      (node (ref "R328") (pin "1") (pinfunction "1_1") (pintype "passive"))
    )
    (net (code "368") (name "Net-(IC43A-~{Q})") (class "Default")
      (node (ref "IC43") (pin "7") (pinfunction "~{Q}_7") (pintype "output"))
      (node (ref "Q53") (pin "1") (pinfunction "G_1") (pintype "passive"))
    )
    (net (code "369") (name "Net-(IC43B-B)") (class "Default")
      (node (ref "IC43") (pin "11") (pinfunction "B_11") (pintype "input"))
      (node (ref "IC43") (pin "9") (pinfunction "~{Q}_9") (pintype "output"))
      (node (ref "R313") (pin "2") (pinfunction "2_2") (pintype "passive"))
    )
    (net (code "370") (name "Net-(IC43B-T2)") (class "Default")
      (node (ref "C59") (pin "1") (pinfunction "1_1") (pintype "passive"))
      (node (ref "IC43") (pin "14") (pinfunction "T2_14") (pintype "input"))
      (node (ref "R311") (pin "1") (pinfunction "1_1") (pintype "passive"))
    )
    (net (code "371") (name "Net-(IC45A-+IN)") (class "Default")
      (node (ref "C54") (pin "1") (pinfunction "1_1") (pintype "passive"))
      (node (ref "IC45") (pin "3") (pinfunction "+IN_3") (pintype "input"))
      (node (ref "R282") (pin "1") (pinfunction "1_1") (pintype "passive"))
    )
    (net (code "372") (name "Net-(IC45A--IN)") (class "Default")
      (node (ref "IC45") (pin "2") (pinfunction "-IN_2") (pintype "input"))
      (node (ref "R283") (pin "2") (pinfunction "2_2") (pintype "passive"))
    )
    (net (code "373") (name "Net-(IC45A-OUT)") (class "Default")
      (node (ref "IC45") (pin "1") (pinfunction "OUT_1") (pintype "output"))
      (node (ref "R314") (pin "2") (pinfunction "2_2") (pintype "passive"))
    )
    (net (code "374") (name "Net-(IC45B-+IN)") (class "Default")
      (node (ref "IC45") (pin "5") (pinfunction "+IN_5") (pintype "input"))
      (node (ref "Q51") (pin "3") (pinfunction "D_3") (pintype "passive"))
      (node (ref "R315") (pin "2") (pinfunction "2_2") (pintype "passive"))
      (node (ref "R316") (pin "2") (pinfunction "2_2") (pintype "passive"))
    )
    (net (code "375") (name "Net-(IC45B--IN)") (class "Default")
      (node (ref "IC45") (pin "6") (pinfunction "-IN_6") (pintype "input"))
      (node (ref "R317") (pin "1") (pinfunction "1_1") (pintype "passive"))
      (node (ref "R318") (pin "2") (pinfunction "2_2") (pintype "passive"))
    )
    (net (code "376") (name "Net-(IC45B-OUT)") (class "Default")
      (node (ref "IC45") (pin "7") (pinfunction "OUT_7") (pintype "output"))
      (node (ref "R296") (pin "2") (pinfunction "2_2") (pintype "passive"))
      (node (ref "R303") (pin "1") (pinfunction "1_1") (pintype "passive"))
      (node (ref "R316") (pin "1") (pinfunction "1_1") (pintype "passive"))
    )
    (net (code "377") (name "Net-(IC101A-+IN)") (class "Default")
      (node (ref "C101") (pin "1") (pinfunction "1_1") (pintype "passive"))
      (node (ref "IC101") (pin "3") (pinfunction "+IN_3") (pintype "input"))
      (node (ref "R105") (pin "1") (pinfunction "1_1") (pintype "passive"))
    )
    (net (code "378") (name "Net-(IC101A--IN)") (class "Default")
      (node (ref "IC101") (pin "2") (pinfunction "-IN_2") (pintype "input"))
      (node (ref "R107") (pin "2") (pinfunction "2_2") (pintype "passive"))
    )
    (net (code "379") (name "Net-(IC101A-OUT)") (class "Default")
      (node (ref "IC101") (pin "1") (pinfunction "OUT_1") (pintype "output"))
      (node (ref "R108") (pin "2") (pinfunction "2_2") (pintype "passive"))
    )
    (net (code "380") (name "Net-(IC101B-+IN)") (class "Default")
      (node (ref "IC101") (pin "5") (pinfunction "+IN_5") (pintype "input"))
      (node (ref "Q1") (pin "3") (pinfunction "D_3") (pintype "passive"))
      (node (ref "R112") (pin "2") (pinfunction "2_2") (pintype "passive"))
      (node (ref "R117") (pin "2") (pinfunction "2_2") (pintype "passive"))
    )
    (net (code "381") (name "Net-(IC101B--IN)") (class "Default")
      (node (ref "IC101") (pin "6") (pinfunction "-IN_6") (pintype "input"))
      (node (ref "R113") (pin "1") (pinfunction "1_1") (pintype "passive"))
      (node (ref "R114") (pin "2") (pinfunction "2_2") (pintype "passive"))
    )
    (net (code "382") (name "Net-(IC101B-OUT)") (class "Default")
      (node (ref "IC101") (pin "7") (pinfunction "OUT_7") (pintype "output"))
      (node (ref "R115") (pin "2") (pinfunction "2_2") (pintype "passive"))
      (node (ref "R116") (pin "1") (pinfunction "1_1") (pintype "passive"))
      (node (ref "R117") (pin "1") (pinfunction "1_1") (pintype "passive"))
    )
    (net (code "383") (name "Net-(IC105A-A)") (class "Default")
      (node (ref "IC105") (pin "10") (pinfunction "A_10") (pintype "input"))
      (node (ref "R111") (pin "1") (pinfunction "1_1") (pintype "passive"))
      (node (ref "R3") (pin "1") (pinfunction "1_1") (pintype "passive"))
      (node (ref "R3") (pin "2") (pinfunction "2_2") (pintype "passive"))
      (node (ref "X101") (pin "4") (pinfunction "4_4") (pintype "passive"))
      (node (ref "X103") (pin "2") (pinfunction "S_2") (pintype "passive"))
    )
    (net (code "384") (name "Net-(IC105A-B)") (class "Default")
      (node (ref "IC105") (pin "13") (pinfunction "B_13") (pintype "input"))
      (node (ref "R110") (pin "1") (pinfunction "1_1") (pintype "passive"))
      (node (ref "R2") (pin "1") (pinfunction "1_1") (pintype "passive"))
      (node (ref "R2") (pin "2") (pinfunction "2_2") (pintype "passive"))
      (node (ref "X101") (pin "3") (pinfunction "3_3") (pintype "passive"))
      (node (ref "X103") (pin "3") (pinfunction "S_3") (pintype "passive"))
    )
    (net (code "385") (name "Net-(IC105A-C)") (class "Default")
      (node (ref "IC105") (pin "12") (pinfunction "C_12") (pintype "input"))
      (node (ref "R1") (pin "1") (pinfunction "1_1") (pintype "passive"))
      (node (ref "R1") (pin "2") (pinfunction "2_2") (pintype "passive"))
      (node (ref "R109") (pin "1") (pinfunction "1_1") (pintype "passive"))
      (node (ref "X101") (pin "2") (pinfunction "2_2") (pintype "passive"))
      (node (ref "X103") (pin "4") (pinfunction "S_4") (pintype "passive"))
    )
    (net (code "386") (name "Net-(IC105A-Q0)") (class "Default")
      (node (ref "IC105") (pin "3") (pinfunction "Q0_3") (pintype "output"))
      (node (ref "IC107") (pin "1") (pinfunction "I1_1") (pintype "input"))
      (node (ref "IC107") (pin "2") (pinfunction "I2_2") (pintype "input"))
      (node (ref "Q1") (pin "1") (pinfunction "G_1") (pintype "passive"))
      (node (ref "Q106") (pin "1") (pinfunction "G_1") (pintype "passive"))
    )
    (net (code "387") (name "Net-(IC105A-Q1)") (class "Default")
      (node (ref "IC105") (pin "14") (pinfunction "Q1_14") (pintype "output"))
      (node (ref "IC107") (pin "6") (pinfunction "I6_6") (pintype "input"))
    )
    (net (code "388") (name "Net-(IC105A-Q2)") (class "Default")
      (node (ref "IC105") (pin "2") (pinfunction "Q2_2") (pintype "output"))
      (node (ref "IC107") (pin "7") (pinfunction "I7_7") (pintype "input"))
    )
    (net (code "389") (name "Net-(IC105A-Q3)") (class "Default")
      (node (ref "IC105") (pin "15") (pinfunction "Q3_15") (pintype "output"))
      (node (ref "IC107") (pin "5") (pinfunction "I5_5") (pintype "input"))
    )
    (net (code "390") (name "Net-(IC105A-Q4)") (class "Default")
      (node (ref "IC105") (pin "1") (pinfunction "Q4_1") (pintype "output"))
      (node (ref "IC107") (pin "4") (pinfunction "I4_4") (pintype "input"))
    )
    (net (code "391") (name "Net-(IC105A-Q5)") (class "Default")
      (node (ref "IC105") (pin "6") (pinfunction "Q5_6") (pintype "output"))
      (node (ref "IC107") (pin "3") (pinfunction "I3_3") (pintype "input"))
    )
    (net (code "392") (name "Net-(IC107-O1)") (class "Default")
      (node (ref "IC107") (pin "16") (pinfunction "O1_16") (pintype "open_collector"))
      (node (ref "Q106") (pin "3") (pinfunction "D_3") (pintype "passive"))
      (node (ref "R9") (pin "1") (pinfunction "1_1") (pintype "passive"))
    )
    (net (code "393") (name "Net-(IC107-O2)") (class "Default")
      (node (ref "IC107") (pin "15") (pinfunction "O2_15") (pintype "open_collector"))
      (node (ref "R128") (pin "1") (pinfunction "1_1") (pintype "passive"))
    )
    (net (code "394") (name "Net-(IC108A-+IN)") (class "Default")
      (node (ref "IC108") (pin "11") (pinfunction "+IN_11") (pintype "input"))
      (node (ref "IC108") (pin "5") (pinfunction "+IN_5") (pintype "input"))
      (node (ref "R131") (pin "1") (pinfunction "1_1") (pintype "passive"))
      (node (ref "R132") (pin "2") (pinfunction "2_2") (pintype "passive"))
      (node (ref "R133") (pin "2") (pinfunction "2_2") (pintype "passive"))
    )
    (net (code "395") (name "Net-(IC108A--IN)") (class "Default")
      (node (ref "C108") (pin "1") (pinfunction "1_1") (pintype "passive"))
      (node (ref "IC108") (pin "10") (pinfunction "-IN_10") (pintype "input"))
      (node (ref "IC108") (pin "4") (pinfunction "-IN_4") (pintype "input"))
      (node (ref "R130") (pin "1") (pinfunction "1_1") (pintype "passive"))
    )
    (net (code "396") (name "Net-(IC108A-OUT)") (class "Default")
      (node (ref "IC108") (pin "2") (pinfunction "OUT_2") (pintype "open_collector"))
      (node (ref "R133") (pin "1") (pinfunction "1_1") (pintype "passive"))
    )
    (net (code "397") (name "Net-(IC108B-+IN)") (class "Default")
      (node (ref "IC108") (pin "7") (pinfunction "+IN_7") (pintype "input"))
      (node (ref "R121") (pin "1") (pinfunction "1_1") (pintype "passive"))
      (node (ref "R122") (pin "1") (pinfunction "1_1") (pintype "passive"))
    )
    (net (code "398") (name "Net-(IC108B--IN)") (class "Default")
      (node (ref "IC108") (pin "6") (pinfunction "-IN_6") (pintype "input"))
      (node (ref "IC108") (pin "8") (pinfunction "-IN_8") (pintype "input"))
      (node (ref "R120") (pin "1") (pinfunction "1_1") (pintype "passive"))
    )
    (net (code "399") (name "Net-(IC108B-OUT)") (class "Default")
      (node (ref "IC108") (pin "1") (pinfunction "OUT_1") (pintype "open_collector"))
      (node (ref "R124") (pin "2") (pinfunction "2_2") (pintype "passive"))
      (node (ref "R125") (pin "2") (pinfunction "2_2") (pintype "passive"))
    )
    (net (code "400") (name "Net-(IC108C-+IN)") (class "Default")
      (node (ref "C105") (pin "1") (pinfunction "1_1") (pintype "passive"))
      (node (ref "IC108") (pin "9") (pinfunction "+IN_9") (pintype "input"))
      (node (ref "R122") (pin "2") (pinfunction "2_2") (pintype "passive"))
      (node (ref "R123") (pin "2") (pinfunction "2_2") (pintype "passive"))
    )
    (net (code "401") (name "Net-(IC108C-OUT)") (class "Default")
      (node (ref "C106") (pin "2") (pinfunction "2_2") (pintype "passive"))
      (node (ref "IC108") (pin "14") (pinfunction "OUT_14") (pintype "open_collector"))
      (node (ref "R126") (pin "2") (pinfunction "2_2") (pintype "passive"))
    )
    (net (code "402") (name "Net-(IC108D-OUT)") (class "Default")
      (node (ref "IC108") (pin "13") (pinfunction "OUT_13") (pintype "open_collector"))
      (node (ref "JP105") (pin "1") (pinfunction "1_1") (pintype "passive"))
      (node (ref "Q107") (pin "1") (pinfunction "G_1") (pintype "passive"))
      (node (ref "R135") (pin "2") (pinfunction "2_2") (pintype "passive"))
    )
    (net (code "403") (name "Net-(IC109-ADJ)") (class "Default")
      (node (ref "IC109") (pin "1") (pinfunction "ADJ_1") (pintype "input"))
      (node (ref "R120") (pin "2") (pinfunction "2_2") (pintype "passive"))
      (node (ref "R134") (pin "1") (pinfunction "1_1") (pintype "passive"))
      (node (ref "X101") (pin "7") (pinfunction "7_7") (pintype "passive"))
    )
    (net (code "404") (name "Net-(IC109-VI)") (class "Default")
      (node (ref "IC109") (pin "3") (pinfunction "VI_3") (pintype "input"))
      (node (ref "Q105") (pin "2") (pinfunction "C_2") (pintype "passive"))
    )
    (net (code "405") (name "Net-(IC109-VO)") (class "Default")
      (node (ref "IC109") (pin "2") (pinfunction "VO_2") (pintype "passive"))
      (node (ref "R134") (pin "2") (pinfunction "2_2") (pintype "passive"))
    )
    (net (code "406") (name "Net-(IC110-CV)") (class "Default")
      (node (ref "IC110") (pin "5") (pinfunction "CV_5") (pintype "input"))
      (node (ref "R144") (pin "2") (pinfunction "2_2") (pintype "passive"))
    )
    (net (code "407") (name "Net-(IC110-Q)") (class "Default")
      (node (ref "IC110") (pin "3") (pinfunction "Q_3") (pintype "output"))
      (node (ref "IC111") (pin "12") (pinfunction "A_12") (pintype "input"))
      (node (ref "IC111") (pin "4") (pinfunction "A_4") (pintype "input"))
      (node (ref "R144") (pin "1") (pinfunction "1_1") (pintype "passive"))
    )
    (net (code "408") (name "Net-(IC111A-T2)") (class "Default")
      (node (ref "C15") (pin "2") (pinfunction "2_2") (pintype "passive"))
      (node (ref "IC111") (pin "2") (pinfunction "T2_2") (pintype "input"))
      (node (ref "R10") (pin "1") (pinfunction "1_1") (pintype "passive"))
    )
    (net (code "409") (name "Net-(IC111A-~{Q})") (class "Default")
      (node (ref "IC111") (pin "7") (pinfunction "~{Q}_7") (pintype "output"))
      (node (ref "Q3") (pin "1") (pinfunction "G_1") (pintype "passive"))
    )
    (net (code "410") (name "Net-(IC111B-B)") (class "Default")
      (node (ref "IC111") (pin "11") (pinfunction "B_11") (pintype "input"))
      (node (ref "IC111") (pin "9") (pinfunction "~{Q}_9") (pintype "output"))
      (node (ref "R146") (pin "2") (pinfunction "2_2") (pintype "passive"))
    )
    (net (code "411") (name "Net-(IC111B-T2)") (class "Default")
      (node (ref "C110") (pin "1") (pinfunction "1_1") (pintype "passive"))
      (node (ref "IC111") (pin "14") (pinfunction "T2_14") (pintype "input"))
      (node (ref "R145") (pin "1") (pinfunction "1_1") (pintype "passive"))
    )
    (net (code "412") (name "Net-(JP1-Pad1)") (class "Default")
      (node (ref "JP1") (pin "1") (pinfunction "1_1") (pintype "passive"))
      (node (ref "R48") (pin "2") (pinfunction "2_2") (pintype "passive"))
    )
    (net (code "413") (name "Net-(JP2-Pad3)") (class "Default")
      (node (ref "JP2") (pin "3") (pinfunction "3_3") (pintype "passive"))
      (node (ref "R40") (pin "1") (pinfunction "1_1") (pintype "passive"))
    )
    (net (code "414") (name "Net-(JP5-Pad2)") (class "Default")
      (node (ref "JP5") (pin "2") (pinfunction "2_2") (pintype "passive"))
      (node (ref "R45") (pin "2") (pinfunction "2_2") (pintype "passive"))
      (node (ref "R46") (pin "2") (pinfunction "2_2") (pintype "passive"))
      (node (ref "SJ1") (pin "2") (pinfunction "2_2") (pintype "passive"))
    )
    (net (code "415") (name "Net-(JP6-Pad1)") (class "Default")
      (node (ref "JP6") (pin "1") (pinfunction "1_1") (pintype "passive"))
      (node (ref "R147") (pin "2") (pinfunction "2_2") (pintype "passive"))
    )
    (net (code "416") (name "Net-(JP7-Pad3)") (class "Default")
      (node (ref "JP7") (pin "3") (pinfunction "3_3") (pintype "passive"))
      (node (ref "R95") (pin "1") (pinfunction "1_1") (pintype "passive"))
    )
    (net (code "417") (name "Net-(JP10-Pad2)") (class "Default")
      (node (ref "JP10") (pin "2") (pinfunction "2_2") (pintype "passive"))
      (node (ref "R100") (pin "2") (pinfunction "2_2") (pintype "passive"))
      (node (ref "R118") (pin "2") (pinfunction "2_2") (pintype "passive"))
      (node (ref "SJ4") (pin "2") (pinfunction "2_2") (pintype "passive"))
    )
    (net (code "418") (name "Net-(JP11-Pad1)") (class "Default")
      (node (ref "JP11") (pin "1") (pinfunction "1_1") (pintype "passive"))
      (node (ref "R202") (pin "2") (pinfunction "2_2") (pintype "passive"))
    )
    (net (code "419") (name "Net-(JP12-Pad3)") (class "Default")
      (node (ref "JP12") (pin "3") (pinfunction "3_3") (pintype "passive"))
      (node (ref "R194") (pin "1") (pinfunction "1_1") (pintype "passive"))
    )
    (net (code "420") (name "Net-(JP15-Pad2)") (class "Default")
      (node (ref "JP15") (pin "2") (pinfunction "2_2") (pintype "passive"))
      (node (ref "R199") (pin "2") (pinfunction "2_2") (pintype "passive"))
      (node (ref "R200") (pin "2") (pinfunction "2_2") (pintype "passive"))
      (node (ref "SJ6") (pin "2") (pinfunction "2_2") (pintype "passive"))
    )
    (net (code "421") (name "Net-(JP16-Pad1)") (class "Default")
      (node (ref "JP16") (pin "1") (pinfunction "1_1") (pintype "passive"))
      (node (ref "R257") (pin "2") (pinfunction "2_2") (pintype "passive"))
    )
    (net (code "422") (name "Net-(JP17-Pad3)") (class "Default")
      (node (ref "JP17") (pin "3") (pinfunction "3_3") (pintype "passive"))
      (node (ref "R249") (pin "1") (pinfunction "1_1") (pintype "passive"))
    )
    (net (code "423") (name "Net-(JP20-Pad2)") (class "Default")
      (node (ref "JP20") (pin "2") (pinfunction "2_2") (pintype "passive"))
      (node (ref "R254") (pin "2") (pinfunction "2_2") (pintype "passive"))
      (node (ref "R255") (pin "2") (pinfunction "2_2") (pintype "passive"))
      (node (ref "SJ8") (pin "2") (pinfunction "2_2") (pintype "passive"))
    )
    (net (code "424") (name "Net-(JP21-Pad1)") (class "Default")
      (node (ref "JP21") (pin "1") (pinfunction "1_1") (pintype "passive"))
      (node (ref "R312") (pin "2") (pinfunction "2_2") (pintype "passive"))
    )
    (net (code "425") (name "Net-(JP22-Pad3)") (class "Default")
      (node (ref "JP22") (pin "3") (pinfunction "3_3") (pintype "passive"))
      (node (ref "R304") (pin "1") (pinfunction "1_1") (pintype "passive"))
    )
    (net (code "426") (name "Net-(JP25-Pad2)") (class "Default")
      (node (ref "JP25") (pin "2") (pinfunction "2_2") (pintype "passive"))
      (node (ref "R309") (pin "2") (pinfunction "2_2") (pintype "passive"))
      (node (ref "R310") (pin "2") (pinfunction "2_2") (pintype "passive"))
      (node (ref "SJ10") (pin "2") (pinfunction "2_2") (pintype "passive"))
    )
    (net (code "427") (name "Net-(JP101-Pad1)") (class "Default")
      (node (ref "JP101") (pin "1") (pinfunction "1_1") (pintype "passive"))
      (node (ref "R119") (pin "2") (pinfunction "2_2") (pintype "passive"))
    )
    (net (code "428") (name "Net-(JP104-Pad2)") (class "Default")
      (node (ref "JP104") (pin "2") (pinfunction "2_2") (pintype "passive"))
      (node (ref "R136") (pin "2") (pinfunction "2_2") (pintype "passive"))
      (node (ref "R137") (pin "2") (pinfunction "2_2") (pintype "passive"))
      (node (ref "SJ101") (pin "2") (pinfunction "2_2") (pintype "passive"))
    )
    (net (code "429") (name "Net-(JP105-Pad3)") (class "Default")
      (node (ref "JP105") (pin "3") (pinfunction "3_3") (pintype "passive"))
      (node (ref "R138") (pin "1") (pinfunction "1_1") (pintype "passive"))
    )
    (net (code "430") (name "Net-(LED1-PadA)") (class "Default")
      (node (ref "LED1") (pin "A") (pinfunction "A_A") (pintype "passive"))
      (node (ref "LED2") (pin "A") (pinfunction "A_A") (pintype "passive"))
      (node (ref "LED3") (pin "A") (pinfunction "A_A") (pintype "passive"))
      (node (ref "LED4") (pin "A") (pinfunction "A_A") (pintype "passive"))
      (node (ref "LED6") (pin "A") (pinfunction "A_A") (pintype "passive"))
      (node (ref "R34") (pin "1") (pinfunction "1_1") (pintype "passive"))
    )
    (net (code "431") (name "Net-(LED5-C)") (class "Default")
      (node (ref "LED5") (pin "K") (pinfunction "C_K") (pintype "passive"))
      (node (ref "R33") (pin "1") (pinfunction "1_1") (pintype "passive"))
    )
    (net (code "432") (name "Net-(LED10-PadA)") (class "Default")
      (node (ref "LED10") (pin "A") (pinfunction "A_A") (pintype "passive"))
      (node (ref "LED12") (pin "A") (pinfunction "A_A") (pintype "passive"))
      (node (ref "LED7") (pin "A") (pinfunction "A_A") (pintype "passive"))
      (node (ref "LED8") (pin "A") (pinfunction "A_A") (pintype "passive"))
      (node (ref "LED9") (pin "A") (pinfunction "A_A") (pintype "passive"))
      (node (ref "R89") (pin "1") (pinfunction "1_1") (pintype "passive"))
    )
    (net (code "433") (name "Net-(LED11-C)") (class "Default")
      (node (ref "LED11") (pin "K") (pinfunction "C_K") (pintype "passive"))
      (node (ref "R88") (pin "1") (pinfunction "1_1") (pintype "passive"))
    )
    (net (code "434") (name "Net-(LED13-PadA)") (class "Default")
      (node (ref "LED13") (pin "A") (pinfunction "A_A") (pintype "passive"))
      (node (ref "LED14") (pin "A") (pinfunction "A_A") (pintype "passive"))
      (node (ref "LED15") (pin "A") (pinfunction "A_A") (pintype "passive"))
      (node (ref "LED16") (pin "A") (pinfunction "A_A") (pintype "passive"))
      (node (ref "LED18") (pin "A") (pinfunction "A_A") (pintype "passive"))
      (node (ref "R188") (pin "1") (pinfunction "1_1") (pintype "passive"))
    )
    (net (code "435") (name "Net-(LED17-C)") (class "Default")
      (node (ref "LED17") (pin "K") (pinfunction "C_K") (pintype "passive"))
      (node (ref "R187") (pin "1") (pinfunction "1_1") (pintype "passive"))
    )
    (net (code "436") (name "Net-(LED19-PadA)") (class "Default")
      (node (ref "LED19") (pin "A") (pinfunction "A_A") (pintype "passive"))
      (node (ref "LED20") (pin "A") (pinfunction "A_A") (pintype "passive"))
      (node (ref "LED21") (pin "A") (pinfunction "A_A") (pintype "passive"))
      (node (ref "LED22") (pin "A") (pinfunction "A_A") (pintype "passive"))
      (node (ref "LED24") (pin "A") (pinfunction "A_A") (pintype "passive"))
      (node (ref "R243") (pin "1") (pinfunction "1_1") (pintype "passive"))
    )
    (net (code "437") (name "Net-(LED23-C)") (class "Default")
      (node (ref "LED23") (pin "K") (pinfunction "C_K") (pintype "passive"))
      (node (ref "R242") (pin "1") (pinfunction "1_1") (pintype "passive"))
    )
    (net (code "438") (name "Net-(LED25-PadA)") (class "Default")
      (node (ref "LED25") (pin "A") (pinfunction "A_A") (pintype "passive"))
      (node (ref "LED26") (pin "A") (pinfunction "A_A") (pintype "passive"))
      (node (ref "LED27") (pin "A") (pinfunction "A_A") (pintype "passive"))
      (node (ref "LED28") (pin "A") (pinfunction "A_A") (pintype "passive"))
      (node (ref "LED30") (pin "A") (pinfunction "A_A") (pintype "passive"))
      (node (ref "R298") (pin "1") (pinfunction "1_1") (pintype "passive"))
    )
    (net (code "439") (name "Net-(LED29-C)") (class "Default")
      (node (ref "LED29") (pin "K") (pinfunction "C_K") (pintype "passive"))
      (node (ref "R297") (pin "1") (pinfunction "1_1") (pintype "passive"))
    )
    (net (code "440") (name "Net-(LED101-C)") (class "Default")
      (node (ref "LED101") (pin "K") (pinfunction "C_K") (pintype "passive"))
      (node (ref "R143") (pin "1") (pinfunction "1_1") (pintype "passive"))
    )
    (net (code "441") (name "Net-(LED102-PadA)") (class "Default")
      (node (ref "LED102") (pin "A") (pinfunction "A_A") (pintype "passive"))
      (node (ref "LED103") (pin "A") (pinfunction "A_A") (pintype "passive"))
      (node (ref "LED104") (pin "A") (pinfunction "A_A") (pintype "passive"))
      (node (ref "LED105") (pin "A") (pinfunction "A_A") (pintype "passive"))
      (node (ref "LED106") (pin "A") (pinfunction "A_A") (pintype "passive"))
      (node (ref "R142") (pin "1") (pinfunction "1_1") (pintype "passive"))
    )
    (net (code "442") (name "Net-(Q2-B)") (class "Default")
      (node (ref "Q2") (pin "1") (pinfunction "B_1") (pintype "passive"))
      (node (ref "R8") (pin "1") (pinfunction "1_1") (pintype "passive"))
    )
    (net (code "443") (name "Net-(Q2-C)") (class "Default")
      (node (ref "Q2") (pin "2") (pinfunction "C_2") (pintype "passive"))
      (node (ref "R129") (pin "2") (pinfunction "2_2") (pintype "passive"))
      (node (ref "SJ2") (pin "2") (pinfunction "2_2") (pintype "passive"))
    )
    (net (code "444") (name "Net-(Q3-D)") (class "Default")
      (node (ref "Q3") (pin "3") (pinfunction "D_3") (pintype "passive"))
      (node (ref "R8") (pin "2") (pinfunction "2_2") (pintype "passive"))
    )
    (net (code "445") (name "Net-(Q4-B)") (class "Default")
      (node (ref "Q4") (pin "1") (pinfunction "B_1") (pintype "passive"))
      (node (ref "R35") (pin "2") (pinfunction "2_2") (pintype "passive"))
    )
    (net (code "446") (name "Net-(Q5-B)") (class "Default")
      (node (ref "Q5") (pin "1") (pinfunction "B_1") (pintype "passive"))
      (node (ref "Q5") (pin "2") (pinfunction "C_2") (pintype "passive"))
      (node (ref "Q6") (pin "1") (pinfunction "B_1") (pintype "passive"))
      (node (ref "R30") (pin "1") (pinfunction "1_1") (pintype "passive"))
      (node (ref "R31") (pin "1") (pinfunction "1_1") (pintype "passive"))
      (node (ref "R55") (pin "1") (pinfunction "1_1") (pintype "passive"))
      (node (ref "X3") (pin "2") (pinfunction "S_2") (pintype "passive"))
    )
    (net (code "447") (name "Net-(Q5-E)") (class "Default")
      (node (ref "Q5") (pin "3") (pinfunction "E_3") (pintype "passive"))
      (node (ref "R36") (pin "2") (pinfunction "2_2") (pintype "passive"))
    )
    (net (code "448") (name "Net-(Q6-E)") (class "Default")
      (node (ref "Q6") (pin "3") (pinfunction "E_3") (pintype "passive"))
      (node (ref "R37") (pin "2") (pinfunction "2_2") (pintype "passive"))
    )
    (net (code "449") (name "Net-(Q7-B)") (class "Default")
      (node (ref "Q7") (pin "1") (pinfunction "B_1") (pintype "passive"))
      (node (ref "R28") (pin "1") (pinfunction "1_1") (pintype "passive"))
    )
    (net (code "450") (name "Net-(Q8-B)") (class "Default")
      (node (ref "Q8") (pin "1") (pinfunction "B_1") (pintype "passive"))
      (node (ref "R39") (pin "2") (pinfunction "2_2") (pintype "passive"))
      (node (ref "R60") (pin "1") (pinfunction "1_1") (pintype "passive"))
    )
    (net (code "451") (name "Net-(Q8-E)") (class "Default")
      (node (ref "Q8") (pin "3") (pinfunction "E_3") (pintype "passive"))
      (node (ref "R59") (pin "1") (pinfunction "1_1") (pintype "passive"))
    )
    (net (code "452") (name "Net-(Q9-D)") (class "Default")
      (node (ref "Q9") (pin "3") (pinfunction "D_3") (pintype "passive"))
      (node (ref "R40") (pin "2") (pinfunction "2_2") (pintype "passive"))
    )
    (net (code "453") (name "Net-(Q10-S)") (class "Default")
      (node (ref "Q10") (pin "2") (pinfunction "S_2") (pintype "passive"))
      (node (ref "R61") (pin "2") (pinfunction "2_2") (pintype "passive"))
    )
    (net (code "454") (name "Net-(Q12-B)") (class "Default")
      (node (ref "Q12") (pin "1") (pinfunction "B_1") (pintype "passive"))
      (node (ref "R63") (pin "1") (pinfunction "1_1") (pintype "passive"))
    )
    (net (code "455") (name "Net-(Q12-C)") (class "Default")
      (node (ref "Q12") (pin "2") (pinfunction "C_2") (pintype "passive"))
      (node (ref "R14") (pin "2") (pinfunction "2_2") (pintype "passive"))
      (node (ref "SJ3") (pin "2") (pinfunction "2_2") (pintype "passive"))
    )
    (net (code "456") (name "Net-(Q13-D)") (class "Default")
      (node (ref "Q13") (pin "3") (pinfunction "D_3") (pintype "passive"))
      (node (ref "R63") (pin "2") (pinfunction "2_2") (pintype "passive"))
    )
    (net (code "457") (name "Net-(Q14-B)") (class "Default")
      (node (ref "Q14") (pin "1") (pinfunction "B_1") (pintype "passive"))
      (node (ref "R90") (pin "2") (pinfunction "2_2") (pintype "passive"))
    )
    (net (code "458") (name "Net-(Q15-B)") (class "Default")
      (node (ref "Q15") (pin "1") (pinfunction "B_1") (pintype "passive"))
      (node (ref "Q15") (pin "2") (pinfunction "C_2") (pintype "passive"))
      (node (ref "Q16") (pin "1") (pinfunction "B_1") (pintype "passive"))
      (node (ref "R154") (pin "1") (pinfunction "1_1") (pintype "passive"))
      (node (ref "R85") (pin "1") (pinfunction "1_1") (pintype "passive"))
      (node (ref "R86") (pin "1") (pinfunction "1_1") (pintype "passive"))
      (node (ref "X6") (pin "2") (pinfunction "S_2") (pintype "passive"))
    )
    (net (code "459") (name "Net-(Q15-E)") (class "Default")
      (node (ref "Q15") (pin "3") (pinfunction "E_3") (pintype "passive"))
      (node (ref "R91") (pin "2") (pinfunction "2_2") (pintype "passive"))
    )
    (net (code "460") (name "Net-(Q16-E)") (class "Default")
      (node (ref "Q16") (pin "3") (pinfunction "E_3") (pintype "passive"))
      (node (ref "R92") (pin "2") (pinfunction "2_2") (pintype "passive"))
    )
    (net (code "461") (name "Net-(Q17-B)") (class "Default")
      (node (ref "Q17") (pin "1") (pinfunction "B_1") (pintype "passive"))
      (node (ref "R83") (pin "1") (pinfunction "1_1") (pintype "passive"))
    )
    (net (code "462") (name "Net-(Q18-B)") (class "Default")
      (node (ref "Q18") (pin "1") (pinfunction "B_1") (pintype "passive"))
      (node (ref "R159") (pin "1") (pinfunction "1_1") (pintype "passive"))
      (node (ref "R94") (pin "2") (pinfunction "2_2") (pintype "passive"))
    )
    (net (code "463") (name "Net-(Q18-E)") (class "Default")
      (node (ref "Q18") (pin "3") (pinfunction "E_3") (pintype "passive"))
      (node (ref "R158") (pin "1") (pinfunction "1_1") (pintype "passive"))
    )
    (net (code "464") (name "Net-(Q19-D)") (class "Default")
      (node (ref "Q19") (pin "3") (pinfunction "D_3") (pintype "passive"))
      (node (ref "R95") (pin "2") (pinfunction "2_2") (pintype "passive"))
    )
    (net (code "465") (name "Net-(Q20-S)") (class "Default")
      (node (ref "Q20") (pin "2") (pinfunction "S_2") (pintype "passive"))
      (node (ref "R160") (pin "2") (pinfunction "2_2") (pintype "passive"))
    )
    (net (code "466") (name "Net-(Q22-B)") (class "Default")
      (node (ref "Q22") (pin "1") (pinfunction "B_1") (pintype "passive"))
      (node (ref "R162") (pin "1") (pinfunction "1_1") (pintype "passive"))
    )
    (net (code "467") (name "Net-(Q22-C)") (class "Default")
      (node (ref "Q22") (pin "2") (pinfunction "C_2") (pintype "passive"))
      (node (ref "R69") (pin "2") (pinfunction "2_2") (pintype "passive"))
      (node (ref "SJ5") (pin "2") (pinfunction "2_2") (pintype "passive"))
    )
    (net (code "468") (name "Net-(Q23-D)") (class "Default")
      (node (ref "Q23") (pin "3") (pinfunction "D_3") (pintype "passive"))
      (node (ref "R162") (pin "2") (pinfunction "2_2") (pintype "passive"))
    )
    (net (code "469") (name "Net-(Q24-B)") (class "Default")
      (node (ref "Q24") (pin "1") (pinfunction "B_1") (pintype "passive"))
      (node (ref "R189") (pin "2") (pinfunction "2_2") (pintype "passive"))
    )
    (net (code "470") (name "Net-(Q25-B)") (class "Default")
      (node (ref "Q25") (pin "1") (pinfunction "B_1") (pintype "passive"))
      (node (ref "Q25") (pin "2") (pinfunction "C_2") (pintype "passive"))
      (node (ref "Q26") (pin "1") (pinfunction "B_1") (pintype "passive"))
      (node (ref "R184") (pin "1") (pinfunction "1_1") (pintype "passive"))
      (node (ref "R185") (pin "1") (pinfunction "1_1") (pintype "passive"))
      (node (ref "R209") (pin "1") (pinfunction "1_1") (pintype "passive"))
      (node (ref "X9") (pin "2") (pinfunction "S_2") (pintype "passive"))
    )
    (net (code "471") (name "Net-(Q25-E)") (class "Default")
      (node (ref "Q25") (pin "3") (pinfunction "E_3") (pintype "passive"))
      (node (ref "R190") (pin "2") (pinfunction "2_2") (pintype "passive"))
    )
    (net (code "472") (name "Net-(Q26-E)") (class "Default")
      (node (ref "Q26") (pin "3") (pinfunction "E_3") (pintype "passive"))
      (node (ref "R191") (pin "2") (pinfunction "2_2") (pintype "passive"))
    )
    (net (code "473") (name "Net-(Q27-B)") (class "Default")
      (node (ref "Q27") (pin "1") (pinfunction "B_1") (pintype "passive"))
      (node (ref "R182") (pin "1") (pinfunction "1_1") (pintype "passive"))
    )
    (net (code "474") (name "Net-(Q28-B)") (class "Default")
      (node (ref "Q28") (pin "1") (pinfunction "B_1") (pintype "passive"))
      (node (ref "R193") (pin "2") (pinfunction "2_2") (pintype "passive"))
      (node (ref "R214") (pin "1") (pinfunction "1_1") (pintype "passive"))
    )
    (net (code "475") (name "Net-(Q28-E)") (class "Default")
      (node (ref "Q28") (pin "3") (pinfunction "E_3") (pintype "passive"))
      (node (ref "R213") (pin "1") (pinfunction "1_1") (pintype "passive"))
    )
    (net (code "476") (name "Net-(Q29-D)") (class "Default")
      (node (ref "Q29") (pin "3") (pinfunction "D_3") (pintype "passive"))
      (node (ref "R194") (pin "2") (pinfunction "2_2") (pintype "passive"))
    )
    (net (code "477") (name "Net-(Q30-S)") (class "Default")
      (node (ref "Q30") (pin "2") (pinfunction "S_2") (pintype "passive"))
      (node (ref "R215") (pin "2") (pinfunction "2_2") (pintype "passive"))
    )
    (net (code "478") (name "Net-(Q32-B)") (class "Default")
      (node (ref "Q32") (pin "1") (pinfunction "B_1") (pintype "passive"))
      (node (ref "R217") (pin "1") (pinfunction "1_1") (pintype "passive"))
    )
    (net (code "479") (name "Net-(Q32-C)") (class "Default")
      (node (ref "Q32") (pin "2") (pinfunction "C_2") (pintype "passive"))
      (node (ref "R168") (pin "2") (pinfunction "2_2") (pintype "passive"))
      (node (ref "SJ7") (pin "2") (pinfunction "2_2") (pintype "passive"))
    )
    (net (code "480") (name "Net-(Q33-D)") (class "Default")
      (node (ref "Q33") (pin "3") (pinfunction "D_3") (pintype "passive"))
      (node (ref "R217") (pin "2") (pinfunction "2_2") (pintype "passive"))
    )
    (net (code "481") (name "Net-(Q34-B)") (class "Default")
      (node (ref "Q34") (pin "1") (pinfunction "B_1") (pintype "passive"))
      (node (ref "R244") (pin "2") (pinfunction "2_2") (pintype "passive"))
    )
    (net (code "482") (name "Net-(Q35-B)") (class "Default")
      (node (ref "Q35") (pin "1") (pinfunction "B_1") (pintype "passive"))
      (node (ref "Q35") (pin "2") (pinfunction "C_2") (pintype "passive"))
      (node (ref "Q36") (pin "1") (pinfunction "B_1") (pintype "passive"))
      (node (ref "R239") (pin "1") (pinfunction "1_1") (pintype "passive"))
      (node (ref "R240") (pin "1") (pinfunction "1_1") (pintype "passive"))
      (node (ref "R264") (pin "1") (pinfunction "1_1") (pintype "passive"))
      (node (ref "X12") (pin "2") (pinfunction "S_2") (pintype "passive"))
    )
    (net (code "483") (name "Net-(Q35-E)") (class "Default")
      (node (ref "Q35") (pin "3") (pinfunction "E_3") (pintype "passive"))
      (node (ref "R245") (pin "2") (pinfunction "2_2") (pintype "passive"))
    )
    (net (code "484") (name "Net-(Q36-E)") (class "Default")
      (node (ref "Q36") (pin "3") (pinfunction "E_3") (pintype "passive"))
      (node (ref "R246") (pin "2") (pinfunction "2_2") (pintype "passive"))
    )
    (net (code "485") (name "Net-(Q37-B)") (class "Default")
      (node (ref "Q37") (pin "1") (pinfunction "B_1") (pintype "passive"))
      (node (ref "R237") (pin "1") (pinfunction "1_1") (pintype "passive"))
    )
    (net (code "486") (name "Net-(Q38-B)") (class "Default")
      (node (ref "Q38") (pin "1") (pinfunction "B_1") (pintype "passive"))
      (node (ref "R248") (pin "2") (pinfunction "2_2") (pintype "passive"))
      (node (ref "R269") (pin "1") (pinfunction "1_1") (pintype "passive"))
    )
    (net (code "487") (name "Net-(Q38-E)") (class "Default")
      (node (ref "Q38") (pin "3") (pinfunction "E_3") (pintype "passive"))
      (node (ref "R268") (pin "1") (pinfunction "1_1") (pintype "passive"))
    )
    (net (code "488") (name "Net-(Q39-D)") (class "Default")
      (node (ref "Q39") (pin "3") (pinfunction "D_3") (pintype "passive"))
      (node (ref "R249") (pin "2") (pinfunction "2_2") (pintype "passive"))
    )
    (net (code "489") (name "Net-(Q40-S)") (class "Default")
      (node (ref "Q40") (pin "2") (pinfunction "S_2") (pintype "passive"))
      (node (ref "R270") (pin "2") (pinfunction "2_2") (pintype "passive"))
    )
    (net (code "490") (name "Net-(Q42-B)") (class "Default")
      (node (ref "Q42") (pin "1") (pinfunction "B_1") (pintype "passive"))
      (node (ref "R272") (pin "1") (pinfunction "1_1") (pintype "passive"))
    )
    (net (code "491") (name "Net-(Q42-C)") (class "Default")
      (node (ref "Q42") (pin "2") (pinfunction "C_2") (pintype "passive"))
      (node (ref "R223") (pin "2") (pinfunction "2_2") (pintype "passive"))
      (node (ref "SJ9") (pin "2") (pinfunction "2_2") (pintype "passive"))
    )
    (net (code "492") (name "Net-(Q43-D)") (class "Default")
      (node (ref "Q43") (pin "3") (pinfunction "D_3") (pintype "passive"))
      (node (ref "R272") (pin "2") (pinfunction "2_2") (pintype "passive"))
    )
    (net (code "493") (name "Net-(Q44-B)") (class "Default")
      (node (ref "Q44") (pin "1") (pinfunction "B_1") (pintype "passive"))
      (node (ref "R299") (pin "2") (pinfunction "2_2") (pintype "passive"))
    )
    (net (code "494") (name "Net-(Q45-B)") (class "Default")
      (node (ref "Q45") (pin "1") (pinfunction "B_1") (pintype "passive"))
      (node (ref "Q45") (pin "2") (pinfunction "C_2") (pintype "passive"))
      (node (ref "Q46") (pin "1") (pinfunction "B_1") (pintype "passive"))
      (node (ref "R294") (pin "1") (pinfunction "1_1") (pintype "passive"))
      (node (ref "R295") (pin "1") (pinfunction "1_1") (pintype "passive"))
      (node (ref "R319") (pin "1") (pinfunction "1_1") (pintype "passive"))
      (node (ref "X15") (pin "2") (pinfunction "S_2") (pintype "passive"))
    )
    (net (code "495") (name "Net-(Q45-E)") (class "Default")
      (node (ref "Q45") (pin "3") (pinfunction "E_3") (pintype "passive"))
      (node (ref "R300") (pin "2") (pinfunction "2_2") (pintype "passive"))
    )
    (net (code "496") (name "Net-(Q46-E)") (class "Default")
      (node (ref "Q46") (pin "3") (pinfunction "E_3") (pintype "passive"))
      (node (ref "R301") (pin "2") (pinfunction "2_2") (pintype "passive"))
    )
    (net (code "497") (name "Net-(Q47-B)") (class "Default")
      (node (ref "Q47") (pin "1") (pinfunction "B_1") (pintype "passive"))
      (node (ref "R292") (pin "1") (pinfunction "1_1") (pintype "passive"))
    )
    (net (code "498") (name "Net-(Q48-B)") (class "Default")
      (node (ref "Q48") (pin "1") (pinfunction "B_1") (pintype "passive"))
      (node (ref "R303") (pin "2") (pinfunction "2_2") (pintype "passive"))
      (node (ref "R324") (pin "1") (pinfunction "1_1") (pintype "passive"))
    )
    (net (code "499") (name "Net-(Q48-E)") (class "Default")
      (node (ref "Q48") (pin "3") (pinfunction "E_3") (pintype "passive"))
      (node (ref "R323") (pin "1") (pinfunction "1_1") (pintype "passive"))
    )
    (net (code "500") (name "Net-(Q49-D)") (class "Default")
      (node (ref "Q49") (pin "3") (pinfunction "D_3") (pintype "passive"))
      (node (ref "R304") (pin "2") (pinfunction "2_2") (pintype "passive"))
    )
    (net (code "501") (name "Net-(Q50-S)") (class "Default")
      (node (ref "Q50") (pin "2") (pinfunction "S_2") (pintype "passive"))
      (node (ref "R325") (pin "2") (pinfunction "2_2") (pintype "passive"))
    )
    (net (code "502") (name "Net-(Q52-B)") (class "Default")
      (node (ref "Q52") (pin "1") (pinfunction "B_1") (pintype "passive"))
      (node (ref "R327") (pin "1") (pinfunction "1_1") (pintype "passive"))
    )
    (net (code "503") (name "Net-(Q52-C)") (class "Default")
      (node (ref "Q52") (pin "2") (pinfunction "C_2") (pintype "passive"))
      (node (ref "R278") (pin "2") (pinfunction "2_2") (pintype "passive"))
      (node (ref "SJ11") (pin "2") (pinfunction "2_2") (pintype "passive"))
    )
    (net (code "504") (name "Net-(Q53-D)") (class "Default")
      (node (ref "Q53") (pin "3") (pinfunction "D_3") (pintype "passive"))
      (node (ref "R327") (pin "2") (pinfunction "2_2") (pintype "passive"))
    )
    (net (code "505") (name "Net-(Q101-B)") (class "Default")
      (node (ref "Q101") (pin "1") (pinfunction "B_1") (pintype "passive"))
      (node (ref "Q102") (pin "1") (pinfunction "B_1") (pintype "passive"))
      (node (ref "Q102") (pin "2") (pinfunction "C_2") (pintype "passive"))
      (node (ref "R101") (pin "1") (pinfunction "1_1") (pintype "passive"))
      (node (ref "R103") (pin "1") (pinfunction "1_1") (pintype "passive"))
      (node (ref "R104") (pin "1") (pinfunction "1_1") (pintype "passive"))
      (node (ref "X102") (pin "2") (pinfunction "S_2") (pintype "passive"))
    )
    (net (code "506") (name "Net-(Q101-E)") (class "Default")
      (node (ref "Q101") (pin "3") (pinfunction "E_3") (pintype "passive"))
      (node (ref "R102") (pin "2") (pinfunction "2_2") (pintype "passive"))
    )
    (net (code "507") (name "Net-(Q102-E)") (class "Default")
      (node (ref "Q102") (pin "3") (pinfunction "E_3") (pintype "passive"))
      (node (ref "R106") (pin "2") (pinfunction "2_2") (pintype "passive"))
    )
    (net (code "508") (name "Net-(Q103-B)") (class "Default")
      (node (ref "Q103") (pin "1") (pinfunction "B_1") (pintype "passive"))
      (node (ref "R116") (pin "2") (pinfunction "2_2") (pintype "passive"))
      (node (ref "R6") (pin "1") (pinfunction "1_1") (pintype "passive"))
    )
    (net (code "509") (name "Net-(Q103-E)") (class "Default")
      (node (ref "Q103") (pin "3") (pinfunction "E_3") (pintype "passive"))
      (node (ref "R5") (pin "1") (pinfunction "1_1") (pintype "passive"))
    )
    (net (code "510") (name "Net-(Q104-B)") (class "Default")
      (node (ref "Q104") (pin "1") (pinfunction "B_1") (pintype "passive"))
      (node (ref "R128") (pin "2") (pinfunction "2_2") (pintype "passive"))
    )
    (net (code "511") (name "Net-(Q105-B)") (class "Default")
      (node (ref "Q105") (pin "1") (pinfunction "B_1") (pintype "passive"))
      (node (ref "R126") (pin "1") (pinfunction "1_1") (pintype "passive"))
    )
    (net (code "512") (name "Net-(Q106-S)") (class "Default")
      (node (ref "Q106") (pin "2") (pinfunction "S_2") (pintype "passive"))
      (node (ref "R4") (pin "2") (pinfunction "2_2") (pintype "passive"))
    )
    (net (code "513") (name "Net-(Q107-D)") (class "Default")
      (node (ref "Q107") (pin "3") (pinfunction "D_3") (pintype "passive"))
      (node (ref "R138") (pin "2") (pinfunction "2_2") (pintype "passive"))
    )
    (net (code "514") (name "Net-(R14-Pad1)") (class "Default")
      (node (ref "R14") (pin "1") (pinfunction "1_1") (pintype "passive"))
      (node (ref "R7") (pin "2") (pinfunction "2_2") (pintype "passive"))
    )
    (net (code "515") (name "Net-(R32-Pad1)") (class "Default")
      (node (ref "R32") (pin "1") (pinfunction "1_1") (pintype "passive"))
      (node (ref "X1") (pin "21") (pinfunction "21_21") (pintype "passive"))
    )
    (net (code "516") (name "Net-(R44-Pad2)") (class "Default")
      (node (ref "R44") (pin "2") (pinfunction "2_2") (pintype "passive"))
      (node (ref "X1") (pin "16") (pinfunction "16_16") (pintype "passive"))
    )
    (net (code "517") (name "Net-(R67-Pad2)") (class "Default")
      (node (ref "R67") (pin "2") (pinfunction "2_2") (pintype "passive"))
      (node (ref "R69") (pin "1") (pinfunction "1_1") (pintype "passive"))
    )
    (net (code "518") (name "Net-(R87-Pad1)") (class "Default")
      (node (ref "R87") (pin "1") (pinfunction "1_1") (pintype "passive"))
      (node (ref "X4") (pin "21") (pinfunction "21_21") (pintype "passive"))
    )
    (net (code "519") (name "Net-(R99-Pad2)") (class "Default")
      (node (ref "R99") (pin "2") (pinfunction "2_2") (pintype "passive"))
      (node (ref "X4") (pin "16") (pinfunction "16_16") (pintype "passive"))
    )
    (net (code "520") (name "Net-(R115-Pad1)") (class "Default")
      (node (ref "R115") (pin "1") (pinfunction "1_1") (pintype "passive"))
      (node (ref "X101") (pin "21") (pinfunction "21_21") (pintype "passive"))
    )
    (net (code "521") (name "Net-(R127-Pad2)") (class "Default")
      (node (ref "R127") (pin "2") (pinfunction "2_2") (pintype "passive"))
      (node (ref "R129") (pin "1") (pinfunction "1_1") (pintype "passive"))
    )
    (net (code "522") (name "Net-(R140-Pad2)") (class "Default")
      (node (ref "R140") (pin "2") (pinfunction "2_2") (pintype "passive"))
      (node (ref "X101") (pin "16") (pinfunction "16_16") (pintype "passive"))
    )
    (net (code "523") (name "Net-(R166-Pad2)") (class "Default")
      (node (ref "R166") (pin "2") (pinfunction "2_2") (pintype "passive"))
      (node (ref "R168") (pin "1") (pinfunction "1_1") (pintype "passive"))
    )
    (net (code "524") (name "Net-(R186-Pad1)") (class "Default")
      (node (ref "R186") (pin "1") (pinfunction "1_1") (pintype "passive"))
      (node (ref "X7") (pin "21") (pinfunction "21_21") (pintype "passive"))
    )
    (net (code "525") (name "Net-(R198-Pad2)") (class "Default")
      (node (ref "R198") (pin "2") (pinfunction "2_2") (pintype "passive"))
      (node (ref "X7") (pin "16") (pinfunction "16_16") (pintype "passive"))
    )
    (net (code "526") (name "Net-(R221-Pad2)") (class "Default")
      (node (ref "R221") (pin "2") (pinfunction "2_2") (pintype "passive"))
      (node (ref "R223") (pin "1") (pinfunction "1_1") (pintype "passive"))
    )
    (net (code "527") (name "Net-(R241-Pad1)") (class "Default")
      (node (ref "R241") (pin "1") (pinfunction "1_1") (pintype "passive"))
      (node (ref "X10") (pin "21") (pinfunction "21_21") (pintype "passive"))
    )
    (net (code "528") (name "Net-(R253-Pad2)") (class "Default")
      (node (ref "R253") (pin "2") (pinfunction "2_2") (pintype "passive"))
      (node (ref "X10") (pin "16") (pinfunction "16_16") (pintype "passive"))
    )
    (net (code "529") (name "Net-(R276-Pad2)") (class "Default")
      (node (ref "R276") (pin "2") (pinfunction "2_2") (pintype "passive"))
      (node (ref "R278") (pin "1") (pinfunction "1_1") (pintype "passive"))
    )
    (net (code "530") (name "Net-(R296-Pad1)") (class "Default")
      (node (ref "R296") (pin "1") (pinfunction "1_1") (pintype "passive"))
      (node (ref "X13") (pin "21") (pinfunction "21_21") (pintype "passive"))
    )
    (net (code "531") (name "Net-(R308-Pad2)") (class "Default")
      (node (ref "R308") (pin "2") (pinfunction "2_2") (pintype "passive"))
      (node (ref "X13") (pin "16") (pinfunction "16_16") (pintype "passive"))
    )
    (net (code "532") (name "V+") (class "Default")
      (node (ref "D1") (pin "1") (pinfunction "+_1") (pintype "passive"))
      (node (ref "D15") (pin "1") (pinfunction "+_1") (pintype "passive"))
      (node (ref "D29") (pin "1") (pinfunction "+_1") (pintype "passive"))
      (node (ref "D43") (pin "1") (pinfunction "+_1") (pintype "passive"))
      (node (ref "D57") (pin "1") (pinfunction "+_1") (pintype "passive"))
      (node (ref "D71") (pin "1") (pinfunction "+_1") (pintype "passive"))
      (node (ref "Q104") (pin "3") (pinfunction "E_3") (pintype "passive"))
      (node (ref "Q105") (pin "3") (pinfunction "E_3") (pintype "passive"))
      (node (ref "Q12") (pin "3") (pinfunction "E_3") (pintype "passive"))
      (node (ref "Q14") (pin "3") (pinfunction "E_3") (pintype "passive"))
      (node (ref "Q17") (pin "3") (pinfunction "E_3") (pintype "passive"))
      (node (ref "Q2") (pin "3") (pinfunction "E_3") (pintype "passive"))
      (node (ref "Q22") (pin "3") (pinfunction "E_3") (pintype "passive"))
      (node (ref "Q24") (pin "3") (pinfunction "E_3") (pintype "passive"))
      (node (ref "Q27") (pin "3") (pinfunction "E_3") (pintype "passive"))
      (node (ref "Q32") (pin "3") (pinfunction "E_3") (pintype "passive"))
      (node (ref "Q34") (pin "3") (pinfunction "E_3") (pintype "passive"))
      (node (ref "Q37") (pin "3") (pinfunction "E_3") (pintype "passive"))
      (node (ref "Q4") (pin "3") (pinfunction "E_3") (pintype "passive"))
      (node (ref "Q42") (pin "3") (pinfunction "E_3") (pintype "passive"))
      (node (ref "Q44") (pin "3") (pinfunction "E_3") (pintype "passive"))
      (node (ref "Q47") (pin "3") (pinfunction "E_3") (pintype "passive"))
      (node (ref "Q52") (pin "3") (pinfunction "E_3") (pintype "passive"))
      (node (ref "Q7") (pin "3") (pinfunction "E_3") (pintype "passive"))
      (node (ref "SJ11") (pin "1") (pinfunction "1_1") (pintype "passive"))
      (node (ref "SJ2") (pin "1") (pinfunction "1_1") (pintype "passive"))
      (node (ref "SJ3") (pin "1") (pinfunction "1_1") (pintype "passive"))
      (node (ref "SJ5") (pin "1") (pinfunction "1_1") (pintype "passive"))
      (node (ref "SJ7") (pin "1") (pinfunction "1_1") (pintype "passive"))
      (node (ref "SJ9") (pin "1") (pinfunction "1_1") (pintype "passive"))
      (node (ref "X1") (pin "6") (pinfunction "6_6") (pintype "passive"))
      (node (ref "X10") (pin "6") (pinfunction "6_6") (pintype "passive"))
      (node (ref "X101") (pin "6") (pinfunction "6_6") (pintype "passive"))
      (node (ref "X13") (pin "6") (pinfunction "6_6") (pintype "passive"))
      (node (ref "X4") (pin "6") (pinfunction "6_6") (pintype "passive"))
      (node (ref "X7") (pin "6") (pinfunction "6_6") (pintype "passive"))
    )
    (net (code "533") (name "VCC") (class "Default")
      (node (ref "6V") (pin "TP") (pinfunction "PP_TP") (pintype "input"))
      (node (ref "6V1") (pin "TP") (pinfunction "PP_TP") (pintype "input"))
      (node (ref "6V2") (pin "TP") (pinfunction "PP_TP") (pintype "input"))
      (node (ref "6V3") (pin "TP") (pinfunction "PP_TP") (pintype "input"))
      (node (ref "6V4") (pin "TP") (pinfunction "PP_TP") (pintype "input"))
      (node (ref "6V5") (pin "TP") (pinfunction "PP_TP") (pintype "input"))
      (node (ref "C104") (pin "1") (pinfunction "1_1") (pintype "passive"))
      (node (ref "C17") (pin "1") (pinfunction "1_1") (pintype "passive"))
      (node (ref "C29") (pin "1") (pinfunction "1_1") (pintype "passive"))
      (node (ref "C4") (pin "1") (pinfunction "1_1") (pintype "passive"))
      (node (ref "C41") (pin "1") (pinfunction "1_1") (pintype "passive"))
      (node (ref "C53") (pin "1") (pinfunction "1_1") (pintype "passive"))
      (node (ref "IC101") (pin "8") (pinfunction "V+_8") (pintype "power_in"))
      (node (ref "IC102") (pin "1") (pinfunction "OUT_1") (pintype "passive"))
      (node (ref "IC108") (pin "3") (pinfunction "V+_3") (pintype "power_in"))
      (node (ref "IC13") (pin "3") (pinfunction "V+_3") (pintype "power_in"))
      (node (ref "IC14") (pin "1") (pinfunction "OUT_1") (pintype "passive"))
      (node (ref "IC18") (pin "8") (pinfunction "V+_8") (pintype "power_in"))
      (node (ref "IC22") (pin "3") (pinfunction "V+_3") (pintype "power_in"))
      (node (ref "IC23") (pin "1") (pinfunction "OUT_1") (pintype "passive"))
      (node (ref "IC27") (pin "8") (pinfunction "V+_8") (pintype "power_in"))
      (node (ref "IC31") (pin "3") (pinfunction "V+_3") (pintype "power_in"))
      (node (ref "IC32") (pin "1") (pinfunction "OUT_1") (pintype "passive"))
      (node (ref "IC36") (pin "8") (pinfunction "V+_8") (pintype "power_in"))
      (node (ref "IC4") (pin "3") (pinfunction "V+_3") (pintype "power_in"))
      (node (ref "IC40") (pin "3") (pinfunction "V+_3") (pintype "power_in"))
      (node (ref "IC41") (pin "1") (pinfunction "OUT_1") (pintype "passive"))
      (node (ref "IC45") (pin "8") (pinfunction "V+_8") (pintype "power_in"))
      (node (ref "IC5") (pin "1") (pinfunction "OUT_1") (pintype "passive"))
      (node (ref "IC9") (pin "8") (pinfunction "V+_8") (pintype "power_in"))
      (node (ref "R113") (pin "2") (pinfunction "2_2") (pintype "passive"))
      (node (ref "R121") (pin "2") (pinfunction "2_2") (pintype "passive"))
      (node (ref "R124") (pin "1") (pinfunction "1_1") (pintype "passive"))
      (node (ref "R131") (pin "2") (pinfunction "2_2") (pintype "passive"))
      (node (ref "R142") (pin "2") (pinfunction "2_2") (pintype "passive"))
      (node (ref "R152") (pin "2") (pinfunction "2_2") (pintype "passive"))
      (node (ref "R175") (pin "2") (pinfunction "2_2") (pintype "passive"))
      (node (ref "R178") (pin "2") (pinfunction "2_2") (pintype "passive"))
      (node (ref "R181") (pin "1") (pinfunction "1_1") (pintype "passive"))
      (node (ref "R188") (pin "2") (pinfunction "2_2") (pintype "passive"))
      (node (ref "R207") (pin "2") (pinfunction "2_2") (pintype "passive"))
      (node (ref "R21") (pin "2") (pinfunction "2_2") (pintype "passive"))
      (node (ref "R230") (pin "2") (pinfunction "2_2") (pintype "passive"))
      (node (ref "R233") (pin "2") (pinfunction "2_2") (pintype "passive"))
      (node (ref "R236") (pin "1") (pinfunction "1_1") (pintype "passive"))
      (node (ref "R24") (pin "2") (pinfunction "2_2") (pintype "passive"))
      (node (ref "R243") (pin "2") (pinfunction "2_2") (pintype "passive"))
      (node (ref "R262") (pin "2") (pinfunction "2_2") (pintype "passive"))
      (node (ref "R27") (pin "1") (pinfunction "1_1") (pintype "passive"))
      (node (ref "R285") (pin "2") (pinfunction "2_2") (pintype "passive"))
      (node (ref "R288") (pin "2") (pinfunction "2_2") (pintype "passive"))
      (node (ref "R291") (pin "1") (pinfunction "1_1") (pintype "passive"))
      (node (ref "R298") (pin "2") (pinfunction "2_2") (pintype "passive"))
      (node (ref "R317") (pin "2") (pinfunction "2_2") (pintype "passive"))
      (node (ref "R34") (pin "2") (pinfunction "2_2") (pintype "passive"))
      (node (ref "R53") (pin "2") (pinfunction "2_2") (pintype "passive"))
      (node (ref "R76") (pin "2") (pinfunction "2_2") (pintype "passive"))
      (node (ref "R79") (pin "2") (pinfunction "2_2") (pintype "passive"))
      (node (ref "R82") (pin "1") (pinfunction "1_1") (pintype "passive"))
      (node (ref "R89") (pin "2") (pinfunction "2_2") (pintype "passive"))
    )
    (net (code "534") (name "unconnected-(IC1A-Q6-Pad7)") (class "Default")
      (node (ref "IC1") (pin "7") (pinfunction "Q6_7") (pintype "output"))
    )
    (net (code "535") (name "unconnected-(IC1A-Q7-Pad4)") (class "Default")
      (node (ref "IC1") (pin "4") (pinfunction "Q7_4") (pintype "output"))
    )
    (net (code "536") (name "unconnected-(IC1A-Q8-Pad9)") (class "Default")
      (node (ref "IC1") (pin "9") (pinfunction "Q8_9") (pintype "output"))
    )
    (net (code "537") (name "unconnected-(IC1A-Q9-Pad5)") (class "Default")
      (node (ref "IC1") (pin "5") (pinfunction "Q9_5") (pintype "output"))
    )
    (net (code "538") (name "unconnected-(IC6-DIS-Pad7)") (class "Default")
      (node (ref "IC6") (pin "7") (pinfunction "DIS_7") (pintype "input"))
    )
    (net (code "539") (name "unconnected-(IC7A-Q-Pad6)") (class "Default")
      (node (ref "IC7") (pin "6") (pinfunction "Q_6") (pintype "output"))
    )
    (net (code "540") (name "unconnected-(IC7B-Q-Pad10)") (class "Default")
      (node (ref "IC7") (pin "10") (pinfunction "Q_10") (pintype "output"))
    )
    (net (code "541") (name "unconnected-(IC10A-Q6-Pad7)") (class "Default")
      (node (ref "IC10") (pin "7") (pinfunction "Q6_7") (pintype "output"))
    )
    (net (code "542") (name "unconnected-(IC10A-Q7-Pad4)") (class "Default")
      (node (ref "IC10") (pin "4") (pinfunction "Q7_4") (pintype "output"))
    )
    (net (code "543") (name "unconnected-(IC10A-Q8-Pad9)") (class "Default")
      (node (ref "IC10") (pin "9") (pinfunction "Q8_9") (pintype "output"))
    )
    (net (code "544") (name "unconnected-(IC10A-Q9-Pad5)") (class "Default")
      (node (ref "IC10") (pin "5") (pinfunction "Q9_5") (pintype "output"))
    )
    (net (code "545") (name "unconnected-(IC15-DIS-Pad7)") (class "Default")
      (node (ref "IC15") (pin "7") (pinfunction "DIS_7") (pintype "input"))
    )
    (net (code "546") (name "unconnected-(IC16A-Q-Pad6)") (class "Default")
      (node (ref "IC16") (pin "6") (pinfunction "Q_6") (pintype "output"))
    )
    (net (code "547") (name "unconnected-(IC16B-Q-Pad10)") (class "Default")
      (node (ref "IC16") (pin "10") (pinfunction "Q_10") (pintype "output"))
    )
    (net (code "548") (name "unconnected-(IC19A-Q6-Pad7)") (class "Default")
      (node (ref "IC19") (pin "7") (pinfunction "Q6_7") (pintype "output"))
    )
    (net (code "549") (name "unconnected-(IC19A-Q7-Pad4)") (class "Default")
      (node (ref "IC19") (pin "4") (pinfunction "Q7_4") (pintype "output"))
    )
    (net (code "550") (name "unconnected-(IC19A-Q8-Pad9)") (class "Default")
      (node (ref "IC19") (pin "9") (pinfunction "Q8_9") (pintype "output"))
    )
    (net (code "551") (name "unconnected-(IC19A-Q9-Pad5)") (class "Default")
      (node (ref "IC19") (pin "5") (pinfunction "Q9_5") (pintype "output"))
    )
    (net (code "552") (name "unconnected-(IC24-DIS-Pad7)") (class "Default")
      (node (ref "IC24") (pin "7") (pinfunction "DIS_7") (pintype "input"))
    )
    (net (code "553") (name "unconnected-(IC25A-Q-Pad6)") (class "Default")
      (node (ref "IC25") (pin "6") (pinfunction "Q_6") (pintype "output"))
    )
    (net (code "554") (name "unconnected-(IC25B-Q-Pad10)") (class "Default")
      (node (ref "IC25") (pin "10") (pinfunction "Q_10") (pintype "output"))
    )
    (net (code "555") (name "unconnected-(IC28A-Q6-Pad7)") (class "Default")
      (node (ref "IC28") (pin "7") (pinfunction "Q6_7") (pintype "output"))
    )
    (net (code "556") (name "unconnected-(IC28A-Q7-Pad4)") (class "Default")
      (node (ref "IC28") (pin "4") (pinfunction "Q7_4") (pintype "output"))
    )
    (net (code "557") (name "unconnected-(IC28A-Q8-Pad9)") (class "Default")
      (node (ref "IC28") (pin "9") (pinfunction "Q8_9") (pintype "output"))
    )
    (net (code "558") (name "unconnected-(IC28A-Q9-Pad5)") (class "Default")
      (node (ref "IC28") (pin "5") (pinfunction "Q9_5") (pintype "output"))
    )
    (net (code "559") (name "unconnected-(IC33-DIS-Pad7)") (class "Default")
      (node (ref "IC33") (pin "7") (pinfunction "DIS_7") (pintype "input"))
    )
    (net (code "560") (name "unconnected-(IC34A-Q-Pad6)") (class "Default")
      (node (ref "IC34") (pin "6") (pinfunction "Q_6") (pintype "output"))
    )
    (net (code "561") (name "unconnected-(IC34B-Q-Pad10)") (class "Default")
      (node (ref "IC34") (pin "10") (pinfunction "Q_10") (pintype "output"))
    )
    (net (code "562") (name "unconnected-(IC37A-Q6-Pad7)") (class "Default")
      (node (ref "IC37") (pin "7") (pinfunction "Q6_7") (pintype "output"))
    )
    (net (code "563") (name "unconnected-(IC37A-Q7-Pad4)") (class "Default")
      (node (ref "IC37") (pin "4") (pinfunction "Q7_4") (pintype "output"))
    )
    (net (code "564") (name "unconnected-(IC37A-Q8-Pad9)") (class "Default")
      (node (ref "IC37") (pin "9") (pinfunction "Q8_9") (pintype "output"))
    )
    (net (code "565") (name "unconnected-(IC37A-Q9-Pad5)") (class "Default")
      (node (ref "IC37") (pin "5") (pinfunction "Q9_5") (pintype "output"))
    )
    (net (code "566") (name "unconnected-(IC42-DIS-Pad7)") (class "Default")
      (node (ref "IC42") (pin "7") (pinfunction "DIS_7") (pintype "input"))
    )
    (net (code "567") (name "unconnected-(IC43A-Q-Pad6)") (class "Default")
      (node (ref "IC43") (pin "6") (pinfunction "Q_6") (pintype "output"))
    )
    (net (code "568") (name "unconnected-(IC43B-Q-Pad10)") (class "Default")
      (node (ref "IC43") (pin "10") (pinfunction "Q_10") (pintype "output"))
    )
    (net (code "569") (name "unconnected-(IC105A-Q6-Pad7)") (class "Default")
      (node (ref "IC105") (pin "7") (pinfunction "Q6_7") (pintype "output"))
    )
    (net (code "570") (name "unconnected-(IC105A-Q7-Pad4)") (class "Default")
      (node (ref "IC105") (pin "4") (pinfunction "Q7_4") (pintype "output"))
    )
    (net (code "571") (name "unconnected-(IC105A-Q8-Pad9)") (class "Default")
      (node (ref "IC105") (pin "9") (pinfunction "Q8_9") (pintype "output"))
    )
    (net (code "572") (name "unconnected-(IC105A-Q9-Pad5)") (class "Default")
      (node (ref "IC105") (pin "5") (pinfunction "Q9_5") (pintype "output"))
    )
    (net (code "573") (name "unconnected-(IC110-DIS-Pad7)") (class "Default")
      (node (ref "IC110") (pin "7") (pinfunction "DIS_7") (pintype "input"))
    )
    (net (code "574") (name "unconnected-(IC111A-Q-Pad6)") (class "Default")
      (node (ref "IC111") (pin "6") (pinfunction "Q_6") (pintype "output"))
    )
    (net (code "575") (name "unconnected-(IC111B-Q-Pad10)") (class "Default")
      (node (ref "IC111") (pin "10") (pinfunction "Q_10") (pintype "output"))
    )
    (net (code "576") (name "unconnected-(X1-Pad20)") (class "Default")
      (node (ref "X1") (pin "20") (pinfunction "20_20") (pintype "passive"))
    )
    (net (code "577") (name "unconnected-(X1-Pad24)") (class "Default")
      (node (ref "X1") (pin "24") (pinfunction "24_24") (pintype "passive"))
    )
    (net (code "578") (name "unconnected-(X4-Pad20)") (class "Default")
      (node (ref "X4") (pin "20") (pinfunction "20_20") (pintype "passive"))
    )
    (net (code "579") (name "unconnected-(X4-Pad24)") (class "Default")
      (node (ref "X4") (pin "24") (pinfunction "24_24") (pintype "passive"))
    )
    (net (code "580") (name "unconnected-(X7-Pad20)") (class "Default")
      (node (ref "X7") (pin "20") (pinfunction "20_20") (pintype "passive"))
    )
    (net (code "581") (name "unconnected-(X7-Pad24)") (class "Default")
      (node (ref "X7") (pin "24") (pinfunction "24_24") (pintype "passive"))
    )
    (net (code "582") (name "unconnected-(X10-Pad20)") (class "Default")
      (node (ref "X10") (pin "20") (pinfunction "20_20") (pintype "passive"))
    )
    (net (code "583") (name "unconnected-(X10-Pad24)") (class "Default")
      (node (ref "X10") (pin "24") (pinfunction "24_24") (pintype "passive"))
    )
    (net (code "584") (name "unconnected-(X13-Pad20)") (class "Default")
      (node (ref "X13") (pin "20") (pinfunction "20_20") (pintype "passive"))
    )
    (net (code "585") (name "unconnected-(X13-Pad24)") (class "Default")
      (node (ref "X13") (pin "24") (pinfunction "24_24") (pintype "passive"))
    )
    (net (code "586") (name "unconnected-(X101-Pad20)") (class "Default")
      (node (ref "X101") (pin "20") (pinfunction "20_20") (pintype "passive"))
    )
    (net (code "587") (name "unconnected-(X101-Pad24)") (class "Default")
      (node (ref "X101") (pin "24") (pinfunction "24_24") (pintype "passive"))
    )
  )
)
